# AutoPad-R2-RevA-Pads.net
KiCad netlist of a schematic drawn in EAGLE
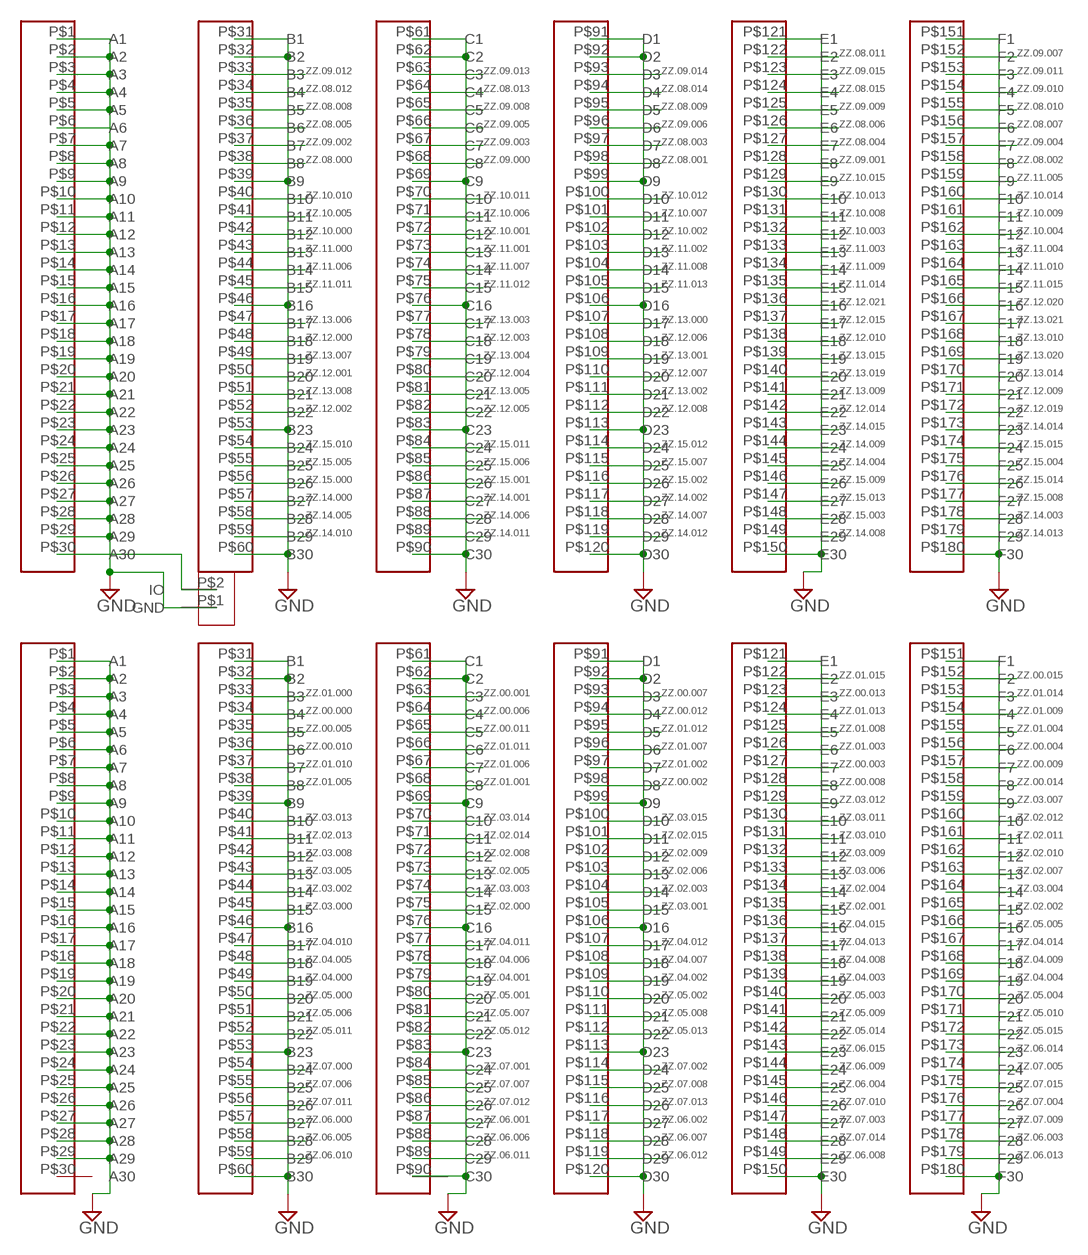
[diagram p0: schematic, sheet 1]
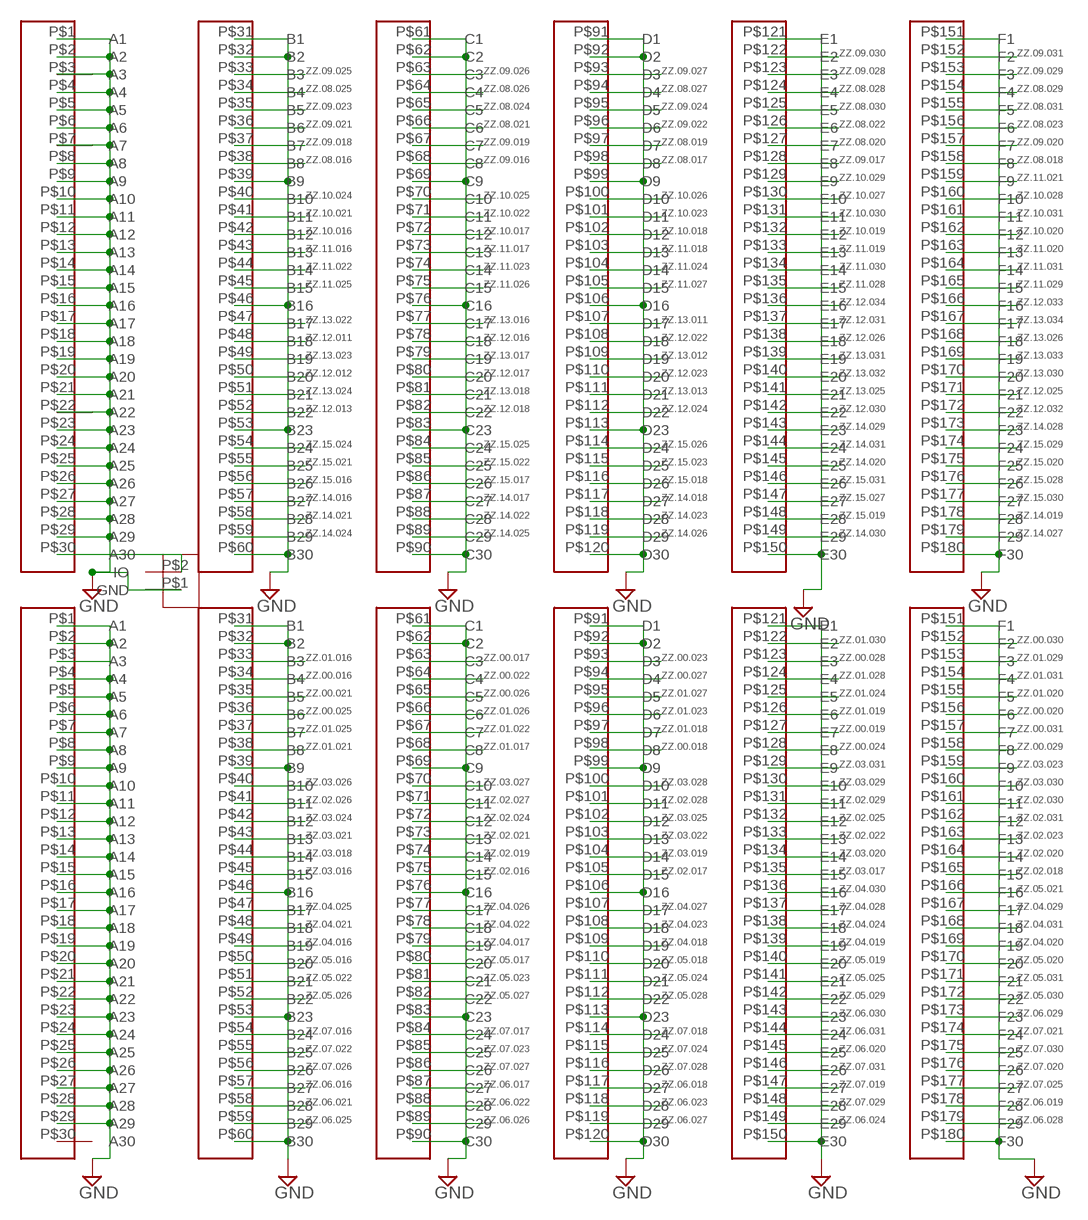
[diagram p1: schematic, sheet 2]
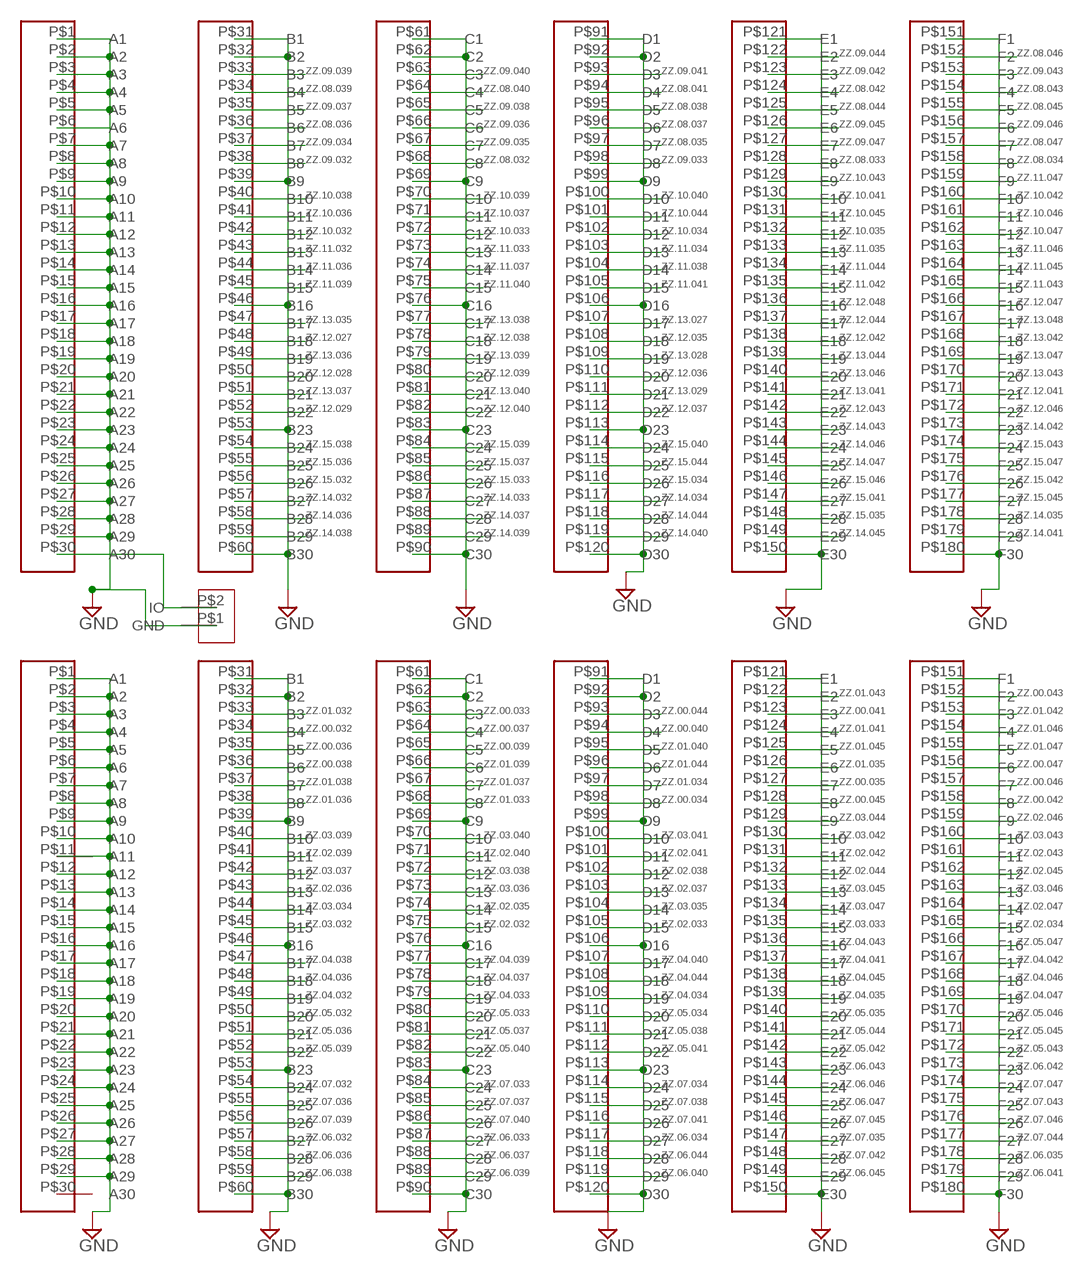
[diagram p2: schematic, sheet 3]
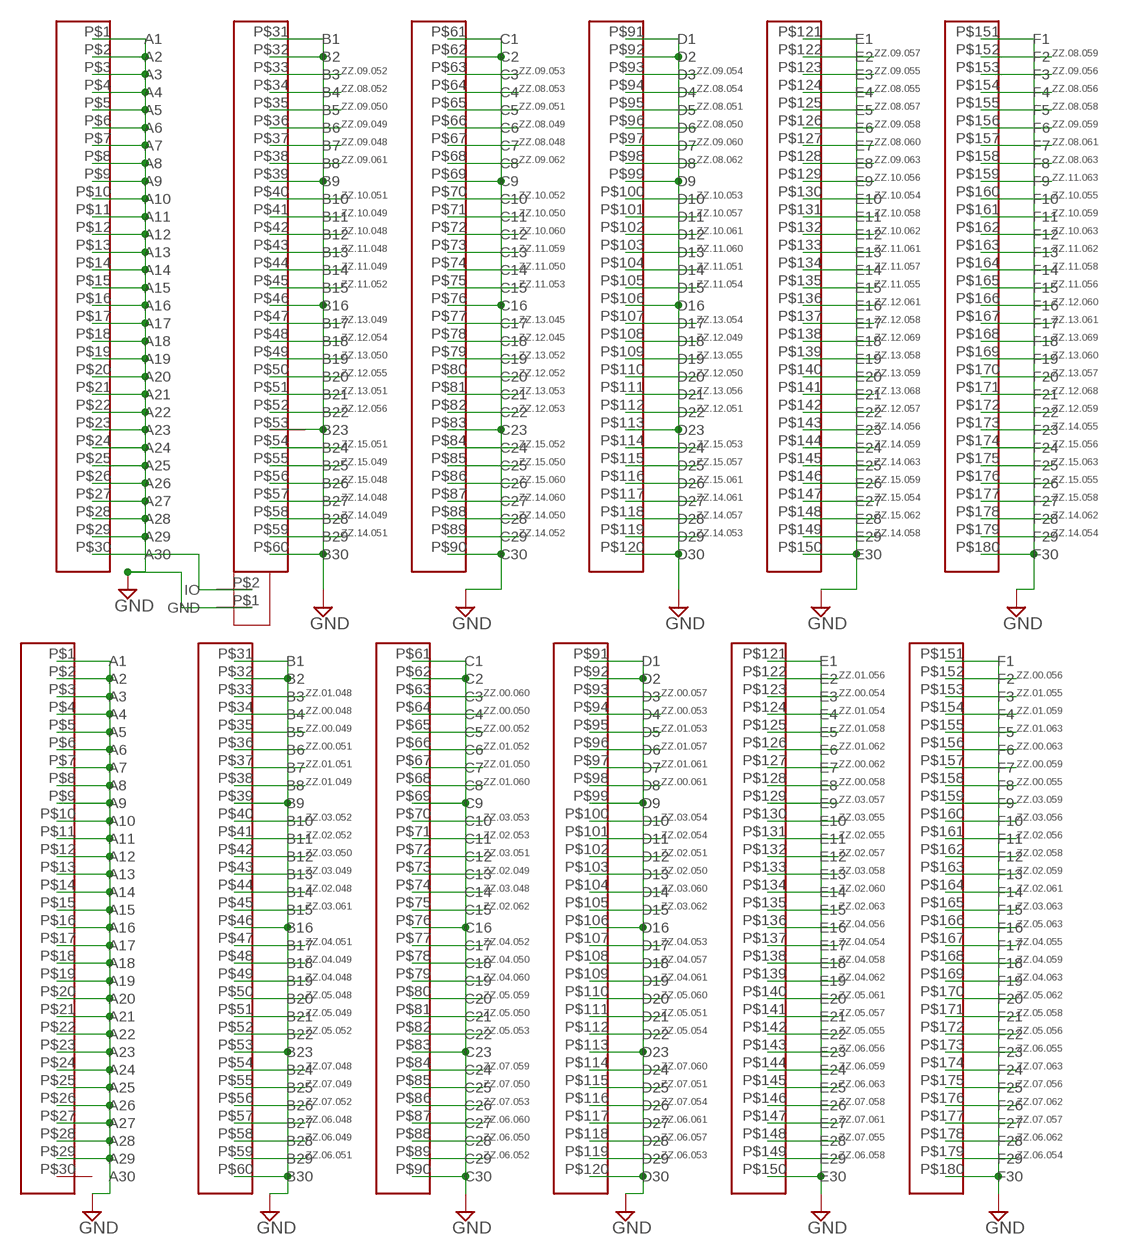
[diagram p3: schematic, sheet 4]
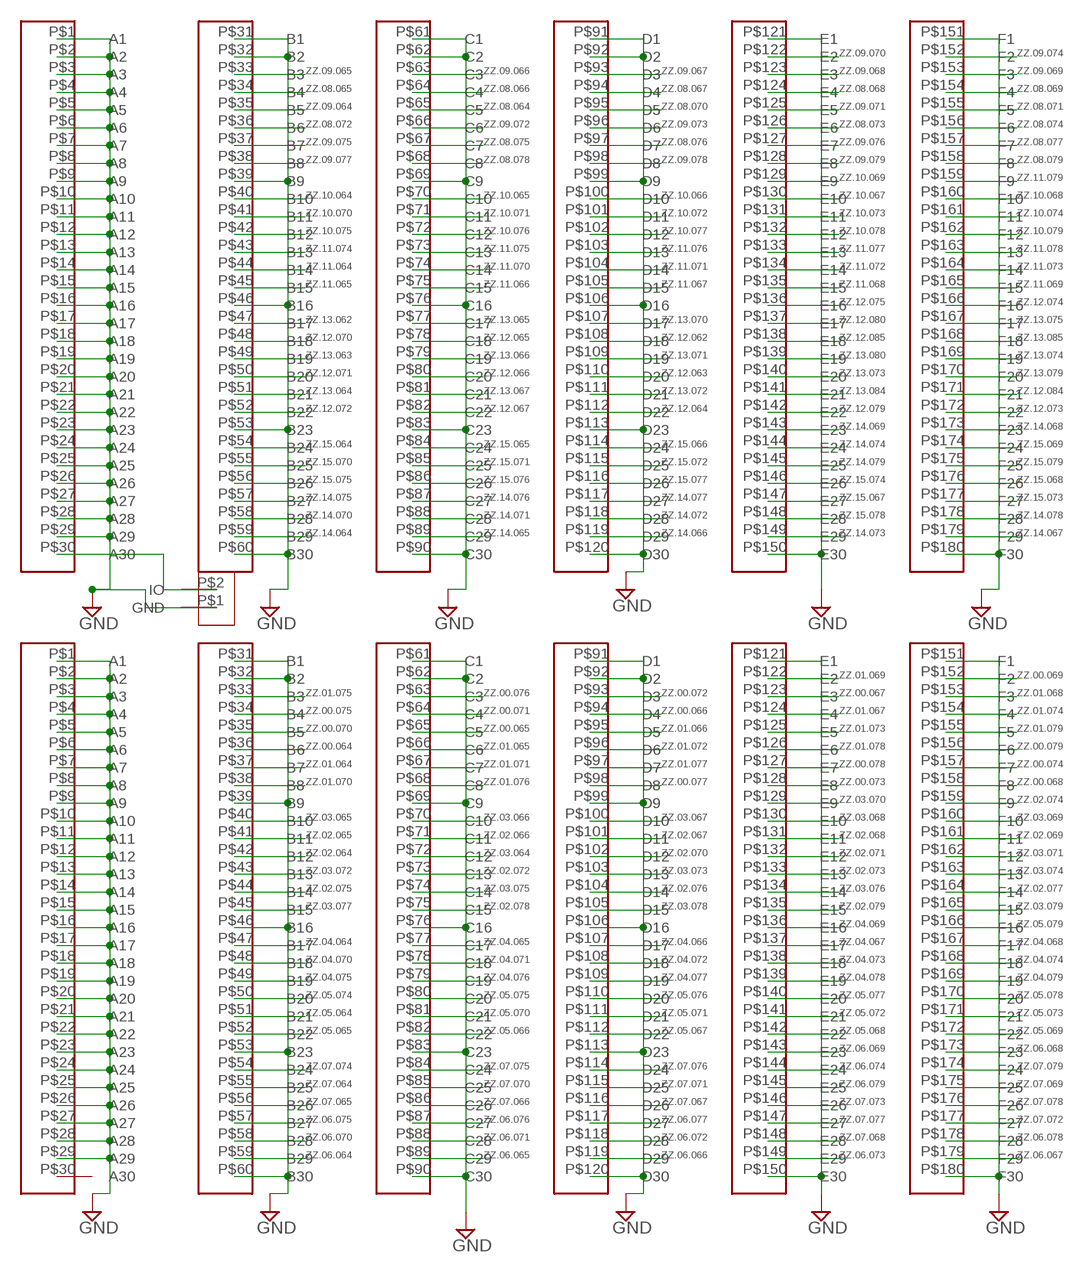
[diagram p4: schematic, sheet 5]
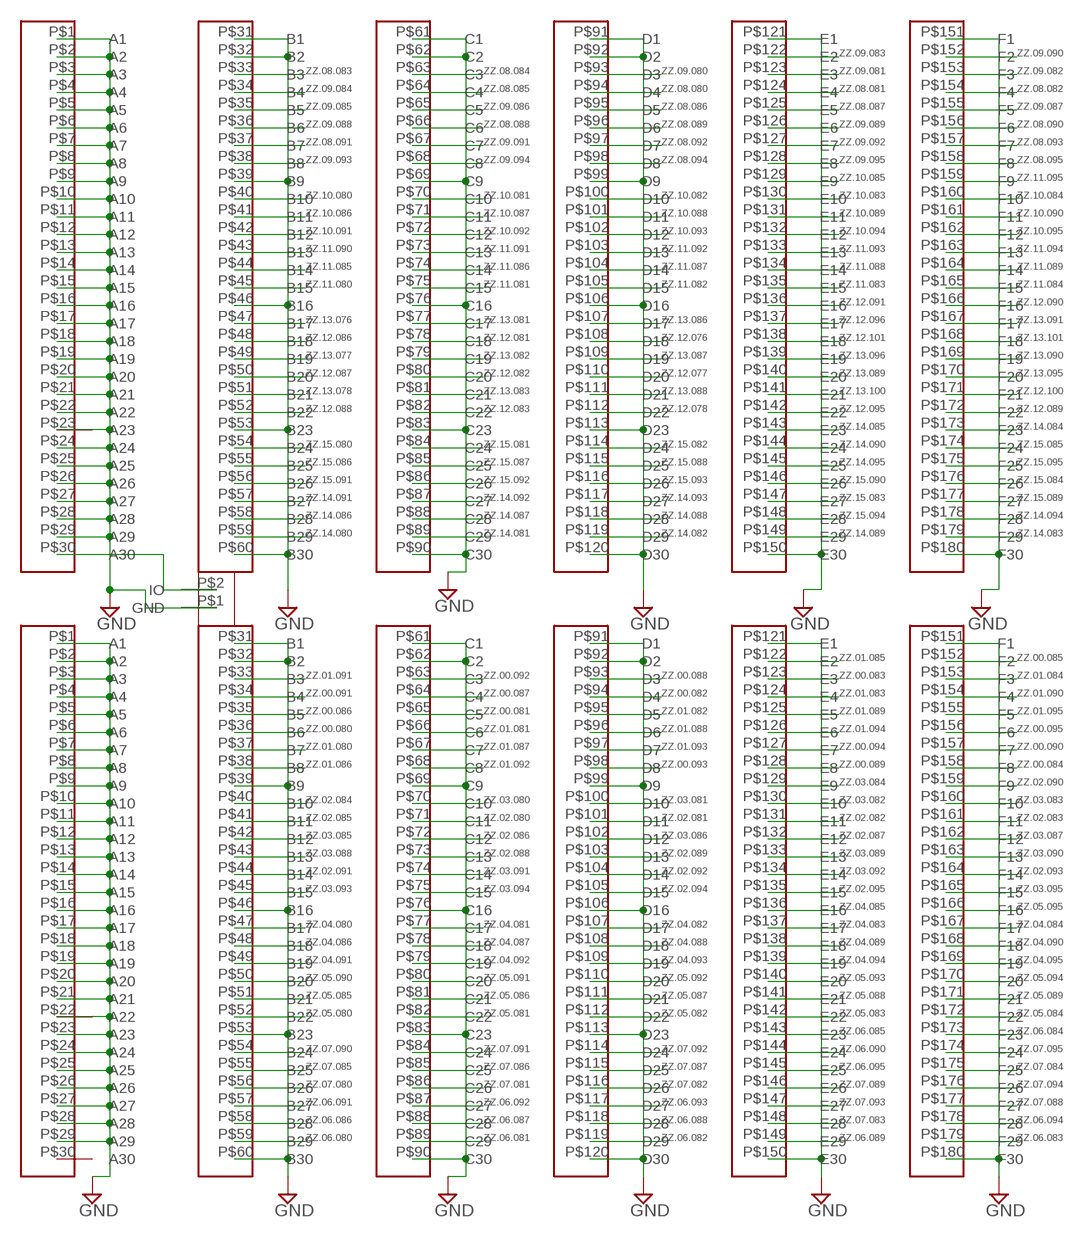
[diagram p5: schematic, sheet 6]
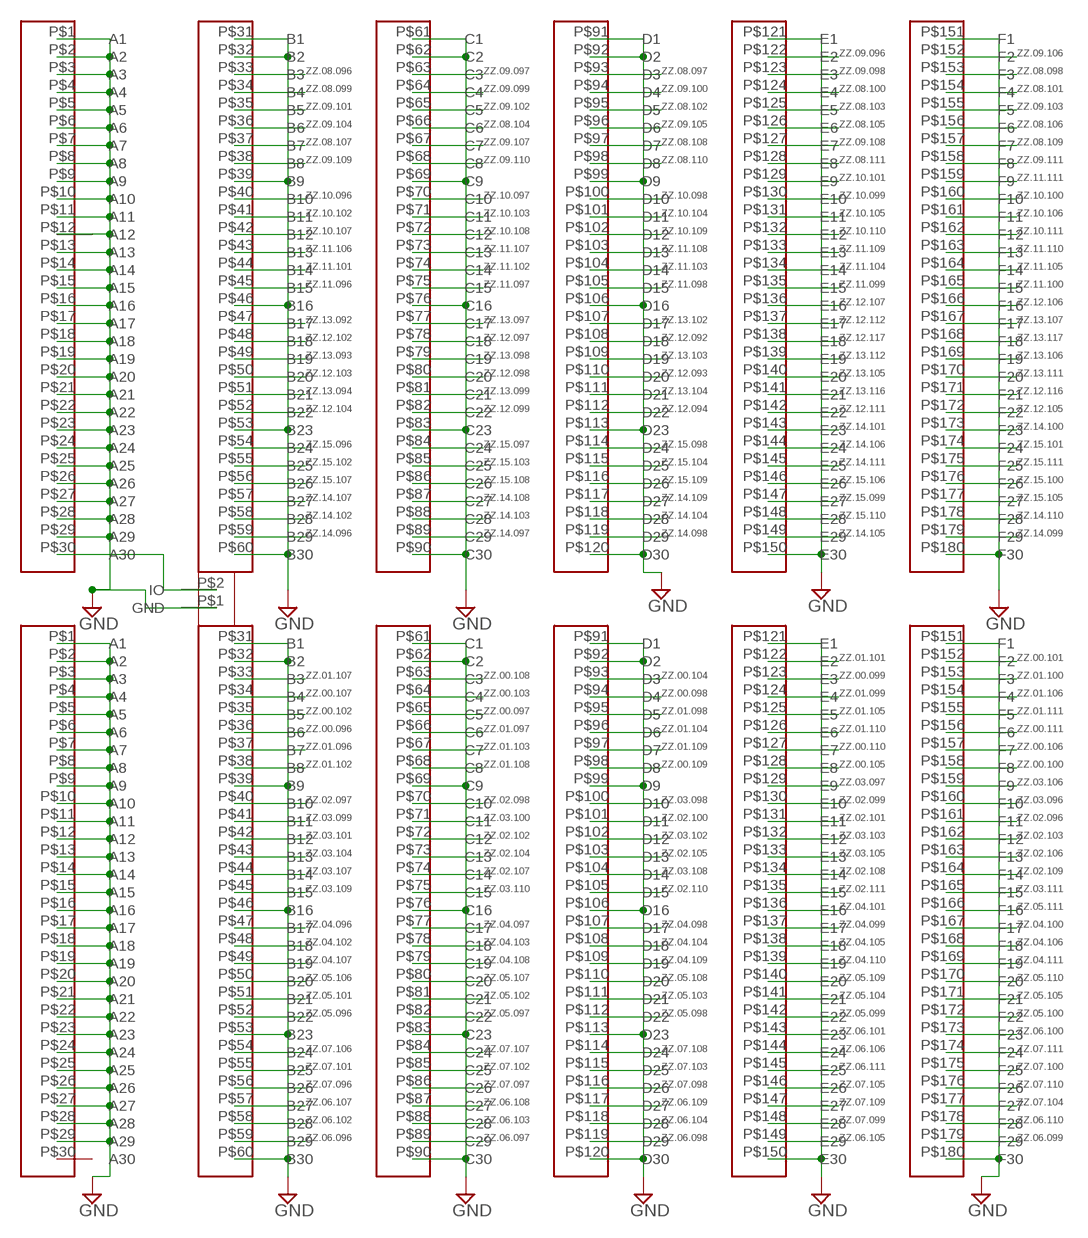
[diagram p6: schematic, sheet 7]
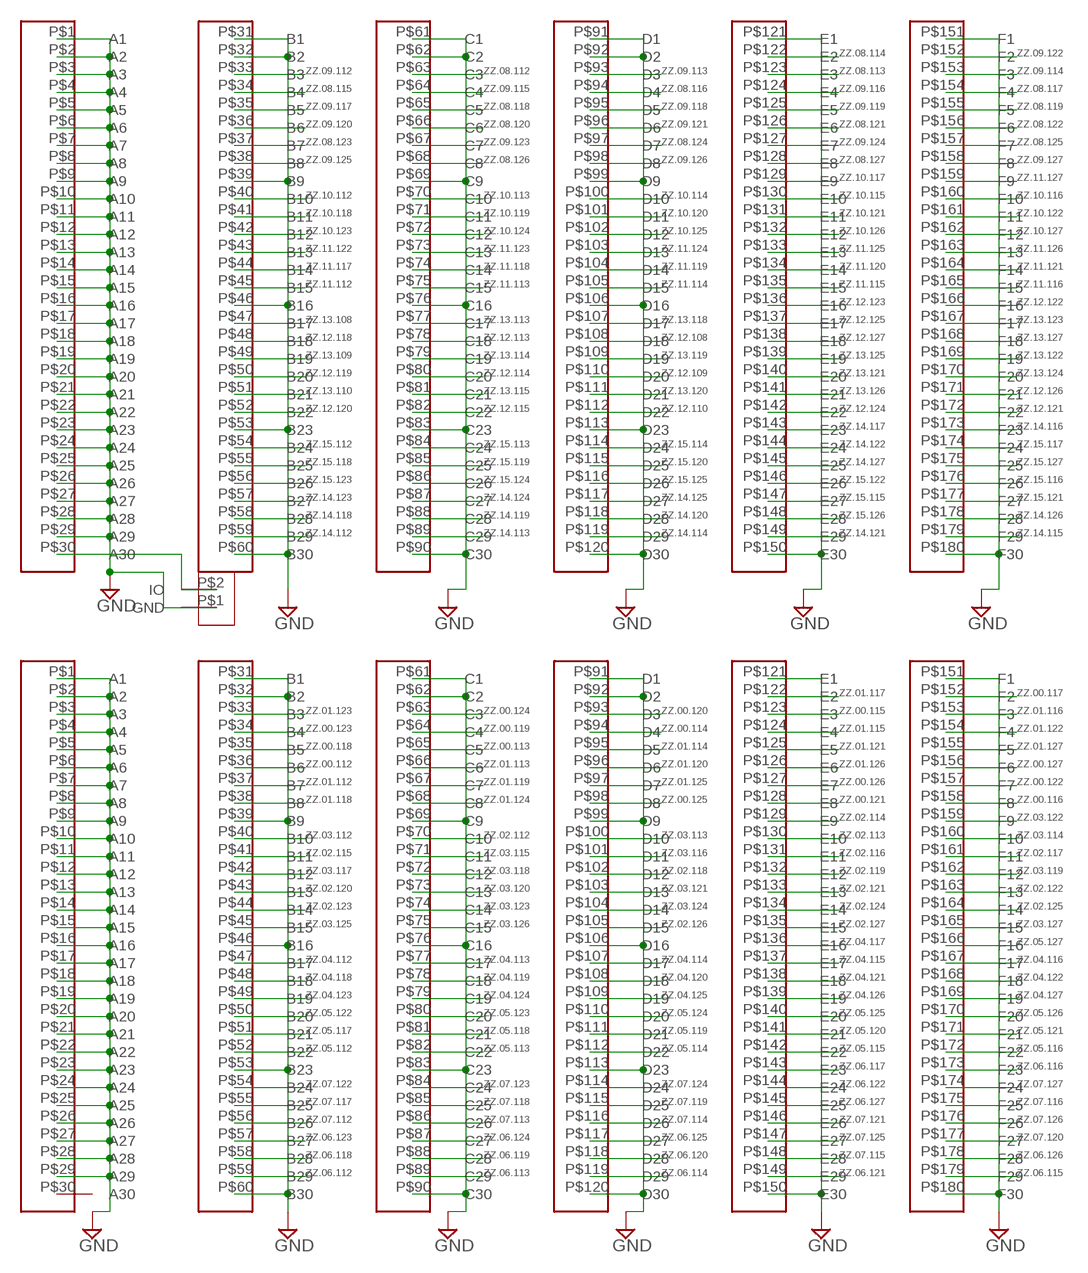
[diagram p7: schematic, sheet 8]

(export (version "E")
  (design (tool "Eeschema 10.0.6"))
  (components
    (comp (ref "U$9")
      (value "SEAM-30-02.0-L-06-1-A-K-TR")
      (footprint "eagle-import:SEAM-30-02.0-L-06-1-A-K-TR")
      (libsource (lib "eagle-import") (part "SEAM-30-02.0-L-06-1-A-K-TR"))
    )
    (comp (ref "U$10")
      (value "SEAM-30-02.0-L-06-1-A-K-TR")
      (footprint "eagle-import:SEAM-30-02.0-L-06-1-A-K-TR")
      (libsource (lib "eagle-import") (part "SEAM-30-02.0-L-06-1-A-K-TR"))
    )
    (comp (ref "U$21")
      (value "DS2431")
      (footprint "eagle-import:SD2431")
      (libsource (lib "eagle-import") (part "DS2431"))
    )
    (comp (ref "U$3")
      (value "SEAM-30-02.0-L-06-1-A-K-TR")
      (footprint "eagle-import:SEAM-30-02.0-L-06-1-A-K-TR")
      (libsource (lib "eagle-import") (part "SEAM-30-02.0-L-06-1-A-K-TR"))
    )
    (comp (ref "U$4")
      (value "SEAM-30-02.0-L-06-1-A-K-TR")
      (footprint "eagle-import:SEAM-30-02.0-L-06-1-A-K-TR")
      (libsource (lib "eagle-import") (part "SEAM-30-02.0-L-06-1-A-K-TR"))
    )
    (comp (ref "U$18")
      (value "DS2431")
      (footprint "eagle-import:SD2431")
      (libsource (lib "eagle-import") (part "DS2431"))
    )
    (comp (ref "U$15")
      (value "SEAM-30-02.0-L-06-1-A-K-TR")
      (footprint "eagle-import:SEAM-30-02.0-L-06-1-A-K-TR")
      (libsource (lib "eagle-import") (part "SEAM-30-02.0-L-06-1-A-K-TR"))
    )
    (comp (ref "U$16")
      (value "SEAM-30-02.0-L-06-1-A-K-TR")
      (footprint "eagle-import:SEAM-30-02.0-L-06-1-A-K-TR")
      (libsource (lib "eagle-import") (part "SEAM-30-02.0-L-06-1-A-K-TR"))
    )
    (comp (ref "U$24")
      (value "DS2431")
      (footprint "eagle-import:SD2431")
      (libsource (lib "eagle-import") (part "DS2431"))
    )
    (comp (ref "U$13")
      (value "SEAM-30-02.0-L-06-1-A-K-TR")
      (footprint "eagle-import:SEAM-30-02.0-L-06-1-A-K-TR")
      (libsource (lib "eagle-import") (part "SEAM-30-02.0-L-06-1-A-K-TR"))
    )
    (comp (ref "U$14")
      (value "SEAM-30-02.0-L-06-1-A-K-TR")
      (footprint "eagle-import:SEAM-30-02.0-L-06-1-A-K-TR")
      (libsource (lib "eagle-import") (part "SEAM-30-02.0-L-06-1-A-K-TR"))
    )
    (comp (ref "U$23")
      (value "DS2431")
      (footprint "eagle-import:SD2431")
      (libsource (lib "eagle-import") (part "DS2431"))
    )
    (comp (ref "U$1")
      (value "SEAM-30-02.0-L-06-1-A-K-TR")
      (footprint "eagle-import:SEAM-30-02.0-L-06-1-A-K-TR")
      (libsource (lib "eagle-import") (part "SEAM-30-02.0-L-06-1-A-K-TR"))
    )
    (comp (ref "U$2")
      (value "SEAM-30-02.0-L-06-1-A-K-TR")
      (footprint "eagle-import:SEAM-30-02.0-L-06-1-A-K-TR")
      (libsource (lib "eagle-import") (part "SEAM-30-02.0-L-06-1-A-K-TR"))
    )
    (comp (ref "U$17")
      (value "DS2431")
      (footprint "eagle-import:SD2431")
      (libsource (lib "eagle-import") (part "DS2431"))
    )
    (comp (ref "U$5")
      (value "SEAM-30-02.0-L-06-1-A-K-TR")
      (footprint "eagle-import:SEAM-30-02.0-L-06-1-A-K-TR")
      (libsource (lib "eagle-import") (part "SEAM-30-02.0-L-06-1-A-K-TR"))
    )
    (comp (ref "U$6")
      (value "SEAM-30-02.0-L-06-1-A-K-TR")
      (footprint "eagle-import:SEAM-30-02.0-L-06-1-A-K-TR")
      (libsource (lib "eagle-import") (part "SEAM-30-02.0-L-06-1-A-K-TR"))
    )
    (comp (ref "U$19")
      (value "DS2431")
      (footprint "eagle-import:SD2431")
      (libsource (lib "eagle-import") (part "DS2431"))
    )
    (comp (ref "U$11")
      (value "SEAM-30-02.0-L-06-1-A-K-TR")
      (footprint "eagle-import:SEAM-30-02.0-L-06-1-A-K-TR")
      (libsource (lib "eagle-import") (part "SEAM-30-02.0-L-06-1-A-K-TR"))
    )
    (comp (ref "U$12")
      (value "SEAM-30-02.0-L-06-1-A-K-TR")
      (footprint "eagle-import:SEAM-30-02.0-L-06-1-A-K-TR")
      (libsource (lib "eagle-import") (part "SEAM-30-02.0-L-06-1-A-K-TR"))
    )
    (comp (ref "U$22")
      (value "DS2431")
      (footprint "eagle-import:SD2431")
      (libsource (lib "eagle-import") (part "DS2431"))
    )
    (comp (ref "U$7")
      (value "SEAM-30-02.0-L-06-1-A-K-TR")
      (footprint "eagle-import:SEAM-30-02.0-L-06-1-A-K-TR")
      (libsource (lib "eagle-import") (part "SEAM-30-02.0-L-06-1-A-K-TR"))
    )
    (comp (ref "U$8")
      (value "SEAM-30-02.0-L-06-1-A-K-TR")
      (footprint "eagle-import:SEAM-30-02.0-L-06-1-A-K-TR")
      (libsource (lib "eagle-import") (part "SEAM-30-02.0-L-06-1-A-K-TR"))
    )
    (comp (ref "U$20")
      (value "DS2431")
      (footprint "eagle-import:SD2431")
      (libsource (lib "eagle-import") (part "DS2431"))
    )
  )
  (nets
    (net (code "1") (name "GND") (class "Default")
      (node (ref "U$1") (pin "P$1") (pinfunction "A1_P$1") (pintype "bidirectional"))
      (node (ref "U$1") (pin "P$10") (pinfunction "A10_P$10") (pintype "bidirectional"))
      (node (ref "U$1") (pin "P$106") (pinfunction "D16_P$106") (pintype "bidirectional"))
      (node (ref "U$1") (pin "P$11") (pinfunction "A11_P$11") (pintype "bidirectional"))
      (node (ref "U$1") (pin "P$113") (pinfunction "D23_P$113") (pintype "bidirectional"))
      (node (ref "U$1") (pin "P$12") (pinfunction "A12_P$12") (pintype "bidirectional"))
      (node (ref "U$1") (pin "P$120") (pinfunction "D30_P$120") (pintype "bidirectional"))
      (node (ref "U$1") (pin "P$121") (pinfunction "E1_P$121") (pintype "bidirectional"))
      (node (ref "U$1") (pin "P$13") (pinfunction "A13_P$13") (pintype "bidirectional"))
      (node (ref "U$1") (pin "P$14") (pinfunction "A14_P$14") (pintype "bidirectional"))
      (node (ref "U$1") (pin "P$15") (pinfunction "A15_P$15") (pintype "bidirectional"))
      (node (ref "U$1") (pin "P$150") (pinfunction "E30_P$150") (pintype "bidirectional"))
      (node (ref "U$1") (pin "P$151") (pinfunction "F1_P$151") (pintype "bidirectional"))
      (node (ref "U$1") (pin "P$16") (pinfunction "A16_P$16") (pintype "bidirectional"))
      (node (ref "U$1") (pin "P$17") (pinfunction "A17_P$17") (pintype "bidirectional"))
      (node (ref "U$1") (pin "P$18") (pinfunction "A18_P$18") (pintype "bidirectional"))
      (node (ref "U$1") (pin "P$180") (pinfunction "F30_P$180") (pintype "bidirectional"))
      (node (ref "U$1") (pin "P$19") (pinfunction "A19_P$19") (pintype "bidirectional"))
      (node (ref "U$1") (pin "P$2") (pinfunction "A2_P$2") (pintype "bidirectional"))
      (node (ref "U$1") (pin "P$20") (pinfunction "A20_P$20") (pintype "bidirectional"))
      (node (ref "U$1") (pin "P$21") (pinfunction "A21_P$21") (pintype "bidirectional"))
      (node (ref "U$1") (pin "P$22") (pinfunction "A22_P$22") (pintype "bidirectional"))
      (node (ref "U$1") (pin "P$23") (pinfunction "A23_P$23") (pintype "bidirectional"))
      (node (ref "U$1") (pin "P$24") (pinfunction "A24_P$24") (pintype "bidirectional"))
      (node (ref "U$1") (pin "P$25") (pinfunction "A25_P$25") (pintype "bidirectional"))
      (node (ref "U$1") (pin "P$26") (pinfunction "A26_P$26") (pintype "bidirectional"))
      (node (ref "U$1") (pin "P$27") (pinfunction "A27_P$27") (pintype "bidirectional"))
      (node (ref "U$1") (pin "P$28") (pinfunction "A28_P$28") (pintype "bidirectional"))
      (node (ref "U$1") (pin "P$29") (pinfunction "A29_P$29") (pintype "bidirectional"))
      (node (ref "U$1") (pin "P$3") (pinfunction "A3_P$3") (pintype "bidirectional"))
      (node (ref "U$1") (pin "P$31") (pinfunction "B1_P$31") (pintype "bidirectional"))
      (node (ref "U$1") (pin "P$32") (pinfunction "B2_P$32") (pintype "bidirectional"))
      (node (ref "U$1") (pin "P$39") (pinfunction "B9_P$39") (pintype "bidirectional"))
      (node (ref "U$1") (pin "P$4") (pinfunction "A4_P$4") (pintype "bidirectional"))
      (node (ref "U$1") (pin "P$46") (pinfunction "B16_P$46") (pintype "bidirectional"))
      (node (ref "U$1") (pin "P$5") (pinfunction "A5_P$5") (pintype "bidirectional"))
      (node (ref "U$1") (pin "P$53") (pinfunction "B23_P$53") (pintype "bidirectional"))
      (node (ref "U$1") (pin "P$6") (pinfunction "A6_P$6") (pintype "bidirectional"))
      (node (ref "U$1") (pin "P$60") (pinfunction "B30_P$60") (pintype "bidirectional"))
      (node (ref "U$1") (pin "P$61") (pinfunction "C1_P$61") (pintype "bidirectional"))
      (node (ref "U$1") (pin "P$62") (pinfunction "C2_P$62") (pintype "bidirectional"))
      (node (ref "U$1") (pin "P$69") (pinfunction "C9_P$69") (pintype "bidirectional"))
      (node (ref "U$1") (pin "P$7") (pinfunction "A7_P$7") (pintype "bidirectional"))
      (node (ref "U$1") (pin "P$76") (pinfunction "C16_P$76") (pintype "bidirectional"))
      (node (ref "U$1") (pin "P$8") (pinfunction "A8_P$8") (pintype "bidirectional"))
      (node (ref "U$1") (pin "P$83") (pinfunction "C23_P$83") (pintype "bidirectional"))
      (node (ref "U$1") (pin "P$9") (pinfunction "A9_P$9") (pintype "bidirectional"))
      (node (ref "U$1") (pin "P$90") (pinfunction "C30_P$90") (pintype "bidirectional"))
      (node (ref "U$1") (pin "P$91") (pinfunction "D1_P$91") (pintype "bidirectional"))
      (node (ref "U$1") (pin "P$92") (pinfunction "D2_P$92") (pintype "bidirectional"))
      (node (ref "U$1") (pin "P$99") (pinfunction "D9_P$99") (pintype "bidirectional"))
      (node (ref "U$10") (pin "P$1") (pinfunction "A1_P$1") (pintype "bidirectional"))
      (node (ref "U$10") (pin "P$10") (pinfunction "A10_P$10") (pintype "bidirectional"))
      (node (ref "U$10") (pin "P$106") (pinfunction "D16_P$106") (pintype "bidirectional"))
      (node (ref "U$10") (pin "P$11") (pinfunction "A11_P$11") (pintype "bidirectional"))
      (node (ref "U$10") (pin "P$113") (pinfunction "D23_P$113") (pintype "bidirectional"))
      (node (ref "U$10") (pin "P$12") (pinfunction "A12_P$12") (pintype "bidirectional"))
      (node (ref "U$10") (pin "P$120") (pinfunction "D30_P$120") (pintype "bidirectional"))
      (node (ref "U$10") (pin "P$121") (pinfunction "E1_P$121") (pintype "bidirectional"))
      (node (ref "U$10") (pin "P$13") (pinfunction "A13_P$13") (pintype "bidirectional"))
      (node (ref "U$10") (pin "P$14") (pinfunction "A14_P$14") (pintype "bidirectional"))
      (node (ref "U$10") (pin "P$15") (pinfunction "A15_P$15") (pintype "bidirectional"))
      (node (ref "U$10") (pin "P$150") (pinfunction "E30_P$150") (pintype "bidirectional"))
      (node (ref "U$10") (pin "P$151") (pinfunction "F1_P$151") (pintype "bidirectional"))
      (node (ref "U$10") (pin "P$16") (pinfunction "A16_P$16") (pintype "bidirectional"))
      (node (ref "U$10") (pin "P$17") (pinfunction "A17_P$17") (pintype "bidirectional"))
      (node (ref "U$10") (pin "P$18") (pinfunction "A18_P$18") (pintype "bidirectional"))
      (node (ref "U$10") (pin "P$180") (pinfunction "F30_P$180") (pintype "bidirectional"))
      (node (ref "U$10") (pin "P$19") (pinfunction "A19_P$19") (pintype "bidirectional"))
      (node (ref "U$10") (pin "P$2") (pinfunction "A2_P$2") (pintype "bidirectional"))
      (node (ref "U$10") (pin "P$20") (pinfunction "A20_P$20") (pintype "bidirectional"))
      (node (ref "U$10") (pin "P$21") (pinfunction "A21_P$21") (pintype "bidirectional"))
      (node (ref "U$10") (pin "P$22") (pinfunction "A22_P$22") (pintype "bidirectional"))
      (node (ref "U$10") (pin "P$23") (pinfunction "A23_P$23") (pintype "bidirectional"))
      (node (ref "U$10") (pin "P$24") (pinfunction "A24_P$24") (pintype "bidirectional"))
      (node (ref "U$10") (pin "P$25") (pinfunction "A25_P$25") (pintype "bidirectional"))
      (node (ref "U$10") (pin "P$26") (pinfunction "A26_P$26") (pintype "bidirectional"))
      (node (ref "U$10") (pin "P$27") (pinfunction "A27_P$27") (pintype "bidirectional"))
      (node (ref "U$10") (pin "P$28") (pinfunction "A28_P$28") (pintype "bidirectional"))
      (node (ref "U$10") (pin "P$29") (pinfunction "A29_P$29") (pintype "bidirectional"))
      (node (ref "U$10") (pin "P$3") (pinfunction "A3_P$3") (pintype "bidirectional"))
      (node (ref "U$10") (pin "P$31") (pinfunction "B1_P$31") (pintype "bidirectional"))
      (node (ref "U$10") (pin "P$32") (pinfunction "B2_P$32") (pintype "bidirectional"))
      (node (ref "U$10") (pin "P$39") (pinfunction "B9_P$39") (pintype "bidirectional"))
      (node (ref "U$10") (pin "P$4") (pinfunction "A4_P$4") (pintype "bidirectional"))
      (node (ref "U$10") (pin "P$46") (pinfunction "B16_P$46") (pintype "bidirectional"))
      (node (ref "U$10") (pin "P$5") (pinfunction "A5_P$5") (pintype "bidirectional"))
      (node (ref "U$10") (pin "P$53") (pinfunction "B23_P$53") (pintype "bidirectional"))
      (node (ref "U$10") (pin "P$6") (pinfunction "A6_P$6") (pintype "bidirectional"))
      (node (ref "U$10") (pin "P$60") (pinfunction "B30_P$60") (pintype "bidirectional"))
      (node (ref "U$10") (pin "P$61") (pinfunction "C1_P$61") (pintype "bidirectional"))
      (node (ref "U$10") (pin "P$62") (pinfunction "C2_P$62") (pintype "bidirectional"))
      (node (ref "U$10") (pin "P$69") (pinfunction "C9_P$69") (pintype "bidirectional"))
      (node (ref "U$10") (pin "P$7") (pinfunction "A7_P$7") (pintype "bidirectional"))
      (node (ref "U$10") (pin "P$76") (pinfunction "C16_P$76") (pintype "bidirectional"))
      (node (ref "U$10") (pin "P$8") (pinfunction "A8_P$8") (pintype "bidirectional"))
      (node (ref "U$10") (pin "P$83") (pinfunction "C23_P$83") (pintype "bidirectional"))
      (node (ref "U$10") (pin "P$9") (pinfunction "A9_P$9") (pintype "bidirectional"))
      (node (ref "U$10") (pin "P$90") (pinfunction "C30_P$90") (pintype "bidirectional"))
      (node (ref "U$10") (pin "P$91") (pinfunction "D1_P$91") (pintype "bidirectional"))
      (node (ref "U$10") (pin "P$92") (pinfunction "D2_P$92") (pintype "bidirectional"))
      (node (ref "U$10") (pin "P$99") (pinfunction "D9_P$99") (pintype "bidirectional"))
      (node (ref "U$11") (pin "P$1") (pinfunction "A1_P$1") (pintype "bidirectional"))
      (node (ref "U$11") (pin "P$10") (pinfunction "A10_P$10") (pintype "bidirectional"))
      (node (ref "U$11") (pin "P$106") (pinfunction "D16_P$106") (pintype "bidirectional"))
      (node (ref "U$11") (pin "P$11") (pinfunction "A11_P$11") (pintype "bidirectional"))
      (node (ref "U$11") (pin "P$113") (pinfunction "D23_P$113") (pintype "bidirectional"))
      (node (ref "U$11") (pin "P$12") (pinfunction "A12_P$12") (pintype "bidirectional"))
      (node (ref "U$11") (pin "P$120") (pinfunction "D30_P$120") (pintype "bidirectional"))
      (node (ref "U$11") (pin "P$121") (pinfunction "E1_P$121") (pintype "bidirectional"))
      (node (ref "U$11") (pin "P$13") (pinfunction "A13_P$13") (pintype "bidirectional"))
      (node (ref "U$11") (pin "P$14") (pinfunction "A14_P$14") (pintype "bidirectional"))
      (node (ref "U$11") (pin "P$15") (pinfunction "A15_P$15") (pintype "bidirectional"))
      (node (ref "U$11") (pin "P$150") (pinfunction "E30_P$150") (pintype "bidirectional"))
      (node (ref "U$11") (pin "P$151") (pinfunction "F1_P$151") (pintype "bidirectional"))
      (node (ref "U$11") (pin "P$16") (pinfunction "A16_P$16") (pintype "bidirectional"))
      (node (ref "U$11") (pin "P$17") (pinfunction "A17_P$17") (pintype "bidirectional"))
      (node (ref "U$11") (pin "P$18") (pinfunction "A18_P$18") (pintype "bidirectional"))
      (node (ref "U$11") (pin "P$180") (pinfunction "F30_P$180") (pintype "bidirectional"))
      (node (ref "U$11") (pin "P$19") (pinfunction "A19_P$19") (pintype "bidirectional"))
      (node (ref "U$11") (pin "P$2") (pinfunction "A2_P$2") (pintype "bidirectional"))
      (node (ref "U$11") (pin "P$20") (pinfunction "A20_P$20") (pintype "bidirectional"))
      (node (ref "U$11") (pin "P$21") (pinfunction "A21_P$21") (pintype "bidirectional"))
      (node (ref "U$11") (pin "P$22") (pinfunction "A22_P$22") (pintype "bidirectional"))
      (node (ref "U$11") (pin "P$23") (pinfunction "A23_P$23") (pintype "bidirectional"))
      (node (ref "U$11") (pin "P$24") (pinfunction "A24_P$24") (pintype "bidirectional"))
      (node (ref "U$11") (pin "P$25") (pinfunction "A25_P$25") (pintype "bidirectional"))
      (node (ref "U$11") (pin "P$26") (pinfunction "A26_P$26") (pintype "bidirectional"))
      (node (ref "U$11") (pin "P$27") (pinfunction "A27_P$27") (pintype "bidirectional"))
      (node (ref "U$11") (pin "P$28") (pinfunction "A28_P$28") (pintype "bidirectional"))
      (node (ref "U$11") (pin "P$29") (pinfunction "A29_P$29") (pintype "bidirectional"))
      (node (ref "U$11") (pin "P$3") (pinfunction "A3_P$3") (pintype "bidirectional"))
      (node (ref "U$11") (pin "P$31") (pinfunction "B1_P$31") (pintype "bidirectional"))
      (node (ref "U$11") (pin "P$32") (pinfunction "B2_P$32") (pintype "bidirectional"))
      (node (ref "U$11") (pin "P$39") (pinfunction "B9_P$39") (pintype "bidirectional"))
      (node (ref "U$11") (pin "P$4") (pinfunction "A4_P$4") (pintype "bidirectional"))
      (node (ref "U$11") (pin "P$46") (pinfunction "B16_P$46") (pintype "bidirectional"))
      (node (ref "U$11") (pin "P$5") (pinfunction "A5_P$5") (pintype "bidirectional"))
      (node (ref "U$11") (pin "P$53") (pinfunction "B23_P$53") (pintype "bidirectional"))
      (node (ref "U$11") (pin "P$6") (pinfunction "A6_P$6") (pintype "bidirectional"))
      (node (ref "U$11") (pin "P$60") (pinfunction "B30_P$60") (pintype "bidirectional"))
      (node (ref "U$11") (pin "P$61") (pinfunction "C1_P$61") (pintype "bidirectional"))
      (node (ref "U$11") (pin "P$62") (pinfunction "C2_P$62") (pintype "bidirectional"))
      (node (ref "U$11") (pin "P$69") (pinfunction "C9_P$69") (pintype "bidirectional"))
      (node (ref "U$11") (pin "P$7") (pinfunction "A7_P$7") (pintype "bidirectional"))
      (node (ref "U$11") (pin "P$76") (pinfunction "C16_P$76") (pintype "bidirectional"))
      (node (ref "U$11") (pin "P$8") (pinfunction "A8_P$8") (pintype "bidirectional"))
      (node (ref "U$11") (pin "P$83") (pinfunction "C23_P$83") (pintype "bidirectional"))
      (node (ref "U$11") (pin "P$9") (pinfunction "A9_P$9") (pintype "bidirectional"))
      (node (ref "U$11") (pin "P$90") (pinfunction "C30_P$90") (pintype "bidirectional"))
      (node (ref "U$11") (pin "P$91") (pinfunction "D1_P$91") (pintype "bidirectional"))
      (node (ref "U$11") (pin "P$92") (pinfunction "D2_P$92") (pintype "bidirectional"))
      (node (ref "U$11") (pin "P$99") (pinfunction "D9_P$99") (pintype "bidirectional"))
      (node (ref "U$12") (pin "P$1") (pinfunction "A1_P$1") (pintype "bidirectional"))
      (node (ref "U$12") (pin "P$10") (pinfunction "A10_P$10") (pintype "bidirectional"))
      (node (ref "U$12") (pin "P$106") (pinfunction "D16_P$106") (pintype "bidirectional"))
      (node (ref "U$12") (pin "P$11") (pinfunction "A11_P$11") (pintype "bidirectional"))
      (node (ref "U$12") (pin "P$113") (pinfunction "D23_P$113") (pintype "bidirectional"))
      (node (ref "U$12") (pin "P$12") (pinfunction "A12_P$12") (pintype "bidirectional"))
      (node (ref "U$12") (pin "P$120") (pinfunction "D30_P$120") (pintype "bidirectional"))
      (node (ref "U$12") (pin "P$121") (pinfunction "E1_P$121") (pintype "bidirectional"))
      (node (ref "U$12") (pin "P$13") (pinfunction "A13_P$13") (pintype "bidirectional"))
      (node (ref "U$12") (pin "P$14") (pinfunction "A14_P$14") (pintype "bidirectional"))
      (node (ref "U$12") (pin "P$15") (pinfunction "A15_P$15") (pintype "bidirectional"))
      (node (ref "U$12") (pin "P$150") (pinfunction "E30_P$150") (pintype "bidirectional"))
      (node (ref "U$12") (pin "P$151") (pinfunction "F1_P$151") (pintype "bidirectional"))
      (node (ref "U$12") (pin "P$16") (pinfunction "A16_P$16") (pintype "bidirectional"))
      (node (ref "U$12") (pin "P$17") (pinfunction "A17_P$17") (pintype "bidirectional"))
      (node (ref "U$12") (pin "P$18") (pinfunction "A18_P$18") (pintype "bidirectional"))
      (node (ref "U$12") (pin "P$180") (pinfunction "F30_P$180") (pintype "bidirectional"))
      (node (ref "U$12") (pin "P$19") (pinfunction "A19_P$19") (pintype "bidirectional"))
      (node (ref "U$12") (pin "P$2") (pinfunction "A2_P$2") (pintype "bidirectional"))
      (node (ref "U$12") (pin "P$20") (pinfunction "A20_P$20") (pintype "bidirectional"))
      (node (ref "U$12") (pin "P$21") (pinfunction "A21_P$21") (pintype "bidirectional"))
      (node (ref "U$12") (pin "P$22") (pinfunction "A22_P$22") (pintype "bidirectional"))
      (node (ref "U$12") (pin "P$23") (pinfunction "A23_P$23") (pintype "bidirectional"))
      (node (ref "U$12") (pin "P$24") (pinfunction "A24_P$24") (pintype "bidirectional"))
      (node (ref "U$12") (pin "P$25") (pinfunction "A25_P$25") (pintype "bidirectional"))
      (node (ref "U$12") (pin "P$26") (pinfunction "A26_P$26") (pintype "bidirectional"))
      (node (ref "U$12") (pin "P$27") (pinfunction "A27_P$27") (pintype "bidirectional"))
      (node (ref "U$12") (pin "P$28") (pinfunction "A28_P$28") (pintype "bidirectional"))
      (node (ref "U$12") (pin "P$29") (pinfunction "A29_P$29") (pintype "bidirectional"))
      (node (ref "U$12") (pin "P$3") (pinfunction "A3_P$3") (pintype "bidirectional"))
      (node (ref "U$12") (pin "P$31") (pinfunction "B1_P$31") (pintype "bidirectional"))
      (node (ref "U$12") (pin "P$32") (pinfunction "B2_P$32") (pintype "bidirectional"))
      (node (ref "U$12") (pin "P$39") (pinfunction "B9_P$39") (pintype "bidirectional"))
      (node (ref "U$12") (pin "P$4") (pinfunction "A4_P$4") (pintype "bidirectional"))
      (node (ref "U$12") (pin "P$46") (pinfunction "B16_P$46") (pintype "bidirectional"))
      (node (ref "U$12") (pin "P$5") (pinfunction "A5_P$5") (pintype "bidirectional"))
      (node (ref "U$12") (pin "P$53") (pinfunction "B23_P$53") (pintype "bidirectional"))
      (node (ref "U$12") (pin "P$6") (pinfunction "A6_P$6") (pintype "bidirectional"))
      (node (ref "U$12") (pin "P$60") (pinfunction "B30_P$60") (pintype "bidirectional"))
      (node (ref "U$12") (pin "P$61") (pinfunction "C1_P$61") (pintype "bidirectional"))
      (node (ref "U$12") (pin "P$62") (pinfunction "C2_P$62") (pintype "bidirectional"))
      (node (ref "U$12") (pin "P$69") (pinfunction "C9_P$69") (pintype "bidirectional"))
      (node (ref "U$12") (pin "P$7") (pinfunction "A7_P$7") (pintype "bidirectional"))
      (node (ref "U$12") (pin "P$76") (pinfunction "C16_P$76") (pintype "bidirectional"))
      (node (ref "U$12") (pin "P$8") (pinfunction "A8_P$8") (pintype "bidirectional"))
      (node (ref "U$12") (pin "P$83") (pinfunction "C23_P$83") (pintype "bidirectional"))
      (node (ref "U$12") (pin "P$9") (pinfunction "A9_P$9") (pintype "bidirectional"))
      (node (ref "U$12") (pin "P$90") (pinfunction "C30_P$90") (pintype "bidirectional"))
      (node (ref "U$12") (pin "P$91") (pinfunction "D1_P$91") (pintype "bidirectional"))
      (node (ref "U$12") (pin "P$92") (pinfunction "D2_P$92") (pintype "bidirectional"))
      (node (ref "U$12") (pin "P$99") (pinfunction "D9_P$99") (pintype "bidirectional"))
      (node (ref "U$13") (pin "P$1") (pinfunction "A1_P$1") (pintype "bidirectional"))
      (node (ref "U$13") (pin "P$10") (pinfunction "A10_P$10") (pintype "bidirectional"))
      (node (ref "U$13") (pin "P$106") (pinfunction "D16_P$106") (pintype "bidirectional"))
      (node (ref "U$13") (pin "P$11") (pinfunction "A11_P$11") (pintype "bidirectional"))
      (node (ref "U$13") (pin "P$113") (pinfunction "D23_P$113") (pintype "bidirectional"))
      (node (ref "U$13") (pin "P$12") (pinfunction "A12_P$12") (pintype "bidirectional"))
      (node (ref "U$13") (pin "P$120") (pinfunction "D30_P$120") (pintype "bidirectional"))
      (node (ref "U$13") (pin "P$121") (pinfunction "E1_P$121") (pintype "bidirectional"))
      (node (ref "U$13") (pin "P$13") (pinfunction "A13_P$13") (pintype "bidirectional"))
      (node (ref "U$13") (pin "P$14") (pinfunction "A14_P$14") (pintype "bidirectional"))
      (node (ref "U$13") (pin "P$15") (pinfunction "A15_P$15") (pintype "bidirectional"))
      (node (ref "U$13") (pin "P$150") (pinfunction "E30_P$150") (pintype "bidirectional"))
      (node (ref "U$13") (pin "P$151") (pinfunction "F1_P$151") (pintype "bidirectional"))
      (node (ref "U$13") (pin "P$16") (pinfunction "A16_P$16") (pintype "bidirectional"))
      (node (ref "U$13") (pin "P$17") (pinfunction "A17_P$17") (pintype "bidirectional"))
      (node (ref "U$13") (pin "P$18") (pinfunction "A18_P$18") (pintype "bidirectional"))
      (node (ref "U$13") (pin "P$180") (pinfunction "F30_P$180") (pintype "bidirectional"))
      (node (ref "U$13") (pin "P$19") (pinfunction "A19_P$19") (pintype "bidirectional"))
      (node (ref "U$13") (pin "P$2") (pinfunction "A2_P$2") (pintype "bidirectional"))
      (node (ref "U$13") (pin "P$20") (pinfunction "A20_P$20") (pintype "bidirectional"))
      (node (ref "U$13") (pin "P$21") (pinfunction "A21_P$21") (pintype "bidirectional"))
      (node (ref "U$13") (pin "P$22") (pinfunction "A22_P$22") (pintype "bidirectional"))
      (node (ref "U$13") (pin "P$23") (pinfunction "A23_P$23") (pintype "bidirectional"))
      (node (ref "U$13") (pin "P$24") (pinfunction "A24_P$24") (pintype "bidirectional"))
      (node (ref "U$13") (pin "P$25") (pinfunction "A25_P$25") (pintype "bidirectional"))
      (node (ref "U$13") (pin "P$26") (pinfunction "A26_P$26") (pintype "bidirectional"))
      (node (ref "U$13") (pin "P$27") (pinfunction "A27_P$27") (pintype "bidirectional"))
      (node (ref "U$13") (pin "P$28") (pinfunction "A28_P$28") (pintype "bidirectional"))
      (node (ref "U$13") (pin "P$29") (pinfunction "A29_P$29") (pintype "bidirectional"))
      (node (ref "U$13") (pin "P$3") (pinfunction "A3_P$3") (pintype "bidirectional"))
      (node (ref "U$13") (pin "P$31") (pinfunction "B1_P$31") (pintype "bidirectional"))
      (node (ref "U$13") (pin "P$32") (pinfunction "B2_P$32") (pintype "bidirectional"))
      (node (ref "U$13") (pin "P$39") (pinfunction "B9_P$39") (pintype "bidirectional"))
      (node (ref "U$13") (pin "P$4") (pinfunction "A4_P$4") (pintype "bidirectional"))
      (node (ref "U$13") (pin "P$46") (pinfunction "B16_P$46") (pintype "bidirectional"))
      (node (ref "U$13") (pin "P$5") (pinfunction "A5_P$5") (pintype "bidirectional"))
      (node (ref "U$13") (pin "P$53") (pinfunction "B23_P$53") (pintype "bidirectional"))
      (node (ref "U$13") (pin "P$6") (pinfunction "A6_P$6") (pintype "bidirectional"))
      (node (ref "U$13") (pin "P$60") (pinfunction "B30_P$60") (pintype "bidirectional"))
      (node (ref "U$13") (pin "P$61") (pinfunction "C1_P$61") (pintype "bidirectional"))
      (node (ref "U$13") (pin "P$62") (pinfunction "C2_P$62") (pintype "bidirectional"))
      (node (ref "U$13") (pin "P$69") (pinfunction "C9_P$69") (pintype "bidirectional"))
      (node (ref "U$13") (pin "P$7") (pinfunction "A7_P$7") (pintype "bidirectional"))
      (node (ref "U$13") (pin "P$76") (pinfunction "C16_P$76") (pintype "bidirectional"))
      (node (ref "U$13") (pin "P$8") (pinfunction "A8_P$8") (pintype "bidirectional"))
      (node (ref "U$13") (pin "P$83") (pinfunction "C23_P$83") (pintype "bidirectional"))
      (node (ref "U$13") (pin "P$9") (pinfunction "A9_P$9") (pintype "bidirectional"))
      (node (ref "U$13") (pin "P$90") (pinfunction "C30_P$90") (pintype "bidirectional"))
      (node (ref "U$13") (pin "P$91") (pinfunction "D1_P$91") (pintype "bidirectional"))
      (node (ref "U$13") (pin "P$92") (pinfunction "D2_P$92") (pintype "bidirectional"))
      (node (ref "U$13") (pin "P$99") (pinfunction "D9_P$99") (pintype "bidirectional"))
      (node (ref "U$14") (pin "P$1") (pinfunction "A1_P$1") (pintype "bidirectional"))
      (node (ref "U$14") (pin "P$10") (pinfunction "A10_P$10") (pintype "bidirectional"))
      (node (ref "U$14") (pin "P$106") (pinfunction "D16_P$106") (pintype "bidirectional"))
      (node (ref "U$14") (pin "P$11") (pinfunction "A11_P$11") (pintype "bidirectional"))
      (node (ref "U$14") (pin "P$113") (pinfunction "D23_P$113") (pintype "bidirectional"))
      (node (ref "U$14") (pin "P$12") (pinfunction "A12_P$12") (pintype "bidirectional"))
      (node (ref "U$14") (pin "P$120") (pinfunction "D30_P$120") (pintype "bidirectional"))
      (node (ref "U$14") (pin "P$121") (pinfunction "E1_P$121") (pintype "bidirectional"))
      (node (ref "U$14") (pin "P$13") (pinfunction "A13_P$13") (pintype "bidirectional"))
      (node (ref "U$14") (pin "P$14") (pinfunction "A14_P$14") (pintype "bidirectional"))
      (node (ref "U$14") (pin "P$15") (pinfunction "A15_P$15") (pintype "bidirectional"))
      (node (ref "U$14") (pin "P$150") (pinfunction "E30_P$150") (pintype "bidirectional"))
      (node (ref "U$14") (pin "P$151") (pinfunction "F1_P$151") (pintype "bidirectional"))
      (node (ref "U$14") (pin "P$16") (pinfunction "A16_P$16") (pintype "bidirectional"))
      (node (ref "U$14") (pin "P$17") (pinfunction "A17_P$17") (pintype "bidirectional"))
      (node (ref "U$14") (pin "P$18") (pinfunction "A18_P$18") (pintype "bidirectional"))
      (node (ref "U$14") (pin "P$180") (pinfunction "F30_P$180") (pintype "bidirectional"))
      (node (ref "U$14") (pin "P$19") (pinfunction "A19_P$19") (pintype "bidirectional"))
      (node (ref "U$14") (pin "P$2") (pinfunction "A2_P$2") (pintype "bidirectional"))
      (node (ref "U$14") (pin "P$20") (pinfunction "A20_P$20") (pintype "bidirectional"))
      (node (ref "U$14") (pin "P$21") (pinfunction "A21_P$21") (pintype "bidirectional"))
      (node (ref "U$14") (pin "P$22") (pinfunction "A22_P$22") (pintype "bidirectional"))
      (node (ref "U$14") (pin "P$23") (pinfunction "A23_P$23") (pintype "bidirectional"))
      (node (ref "U$14") (pin "P$24") (pinfunction "A24_P$24") (pintype "bidirectional"))
      (node (ref "U$14") (pin "P$25") (pinfunction "A25_P$25") (pintype "bidirectional"))
      (node (ref "U$14") (pin "P$26") (pinfunction "A26_P$26") (pintype "bidirectional"))
      (node (ref "U$14") (pin "P$27") (pinfunction "A27_P$27") (pintype "bidirectional"))
      (node (ref "U$14") (pin "P$28") (pinfunction "A28_P$28") (pintype "bidirectional"))
      (node (ref "U$14") (pin "P$29") (pinfunction "A29_P$29") (pintype "bidirectional"))
      (node (ref "U$14") (pin "P$3") (pinfunction "A3_P$3") (pintype "bidirectional"))
      (node (ref "U$14") (pin "P$31") (pinfunction "B1_P$31") (pintype "bidirectional"))
      (node (ref "U$14") (pin "P$32") (pinfunction "B2_P$32") (pintype "bidirectional"))
      (node (ref "U$14") (pin "P$39") (pinfunction "B9_P$39") (pintype "bidirectional"))
      (node (ref "U$14") (pin "P$4") (pinfunction "A4_P$4") (pintype "bidirectional"))
      (node (ref "U$14") (pin "P$46") (pinfunction "B16_P$46") (pintype "bidirectional"))
      (node (ref "U$14") (pin "P$5") (pinfunction "A5_P$5") (pintype "bidirectional"))
      (node (ref "U$14") (pin "P$53") (pinfunction "B23_P$53") (pintype "bidirectional"))
      (node (ref "U$14") (pin "P$6") (pinfunction "A6_P$6") (pintype "bidirectional"))
      (node (ref "U$14") (pin "P$60") (pinfunction "B30_P$60") (pintype "bidirectional"))
      (node (ref "U$14") (pin "P$61") (pinfunction "C1_P$61") (pintype "bidirectional"))
      (node (ref "U$14") (pin "P$62") (pinfunction "C2_P$62") (pintype "bidirectional"))
      (node (ref "U$14") (pin "P$69") (pinfunction "C9_P$69") (pintype "bidirectional"))
      (node (ref "U$14") (pin "P$7") (pinfunction "A7_P$7") (pintype "bidirectional"))
      (node (ref "U$14") (pin "P$76") (pinfunction "C16_P$76") (pintype "bidirectional"))
      (node (ref "U$14") (pin "P$8") (pinfunction "A8_P$8") (pintype "bidirectional"))
      (node (ref "U$14") (pin "P$83") (pinfunction "C23_P$83") (pintype "bidirectional"))
      (node (ref "U$14") (pin "P$9") (pinfunction "A9_P$9") (pintype "bidirectional"))
      (node (ref "U$14") (pin "P$90") (pinfunction "C30_P$90") (pintype "bidirectional"))
      (node (ref "U$14") (pin "P$91") (pinfunction "D1_P$91") (pintype "bidirectional"))
      (node (ref "U$14") (pin "P$92") (pinfunction "D2_P$92") (pintype "bidirectional"))
      (node (ref "U$14") (pin "P$99") (pinfunction "D9_P$99") (pintype "bidirectional"))
      (node (ref "U$15") (pin "P$1") (pinfunction "A1_P$1") (pintype "bidirectional"))
      (node (ref "U$15") (pin "P$10") (pinfunction "A10_P$10") (pintype "bidirectional"))
      (node (ref "U$15") (pin "P$106") (pinfunction "D16_P$106") (pintype "bidirectional"))
      (node (ref "U$15") (pin "P$11") (pinfunction "A11_P$11") (pintype "bidirectional"))
      (node (ref "U$15") (pin "P$113") (pinfunction "D23_P$113") (pintype "bidirectional"))
      (node (ref "U$15") (pin "P$12") (pinfunction "A12_P$12") (pintype "bidirectional"))
      (node (ref "U$15") (pin "P$120") (pinfunction "D30_P$120") (pintype "bidirectional"))
      (node (ref "U$15") (pin "P$121") (pinfunction "E1_P$121") (pintype "bidirectional"))
      (node (ref "U$15") (pin "P$13") (pinfunction "A13_P$13") (pintype "bidirectional"))
      (node (ref "U$15") (pin "P$14") (pinfunction "A14_P$14") (pintype "bidirectional"))
      (node (ref "U$15") (pin "P$15") (pinfunction "A15_P$15") (pintype "bidirectional"))
      (node (ref "U$15") (pin "P$150") (pinfunction "E30_P$150") (pintype "bidirectional"))
      (node (ref "U$15") (pin "P$151") (pinfunction "F1_P$151") (pintype "bidirectional"))
      (node (ref "U$15") (pin "P$16") (pinfunction "A16_P$16") (pintype "bidirectional"))
      (node (ref "U$15") (pin "P$17") (pinfunction "A17_P$17") (pintype "bidirectional"))
      (node (ref "U$15") (pin "P$18") (pinfunction "A18_P$18") (pintype "bidirectional"))
      (node (ref "U$15") (pin "P$180") (pinfunction "F30_P$180") (pintype "bidirectional"))
      (node (ref "U$15") (pin "P$19") (pinfunction "A19_P$19") (pintype "bidirectional"))
      (node (ref "U$15") (pin "P$2") (pinfunction "A2_P$2") (pintype "bidirectional"))
      (node (ref "U$15") (pin "P$20") (pinfunction "A20_P$20") (pintype "bidirectional"))
      (node (ref "U$15") (pin "P$21") (pinfunction "A21_P$21") (pintype "bidirectional"))
      (node (ref "U$15") (pin "P$22") (pinfunction "A22_P$22") (pintype "bidirectional"))
      (node (ref "U$15") (pin "P$23") (pinfunction "A23_P$23") (pintype "bidirectional"))
      (node (ref "U$15") (pin "P$24") (pinfunction "A24_P$24") (pintype "bidirectional"))
      (node (ref "U$15") (pin "P$25") (pinfunction "A25_P$25") (pintype "bidirectional"))
      (node (ref "U$15") (pin "P$26") (pinfunction "A26_P$26") (pintype "bidirectional"))
      (node (ref "U$15") (pin "P$27") (pinfunction "A27_P$27") (pintype "bidirectional"))
      (node (ref "U$15") (pin "P$28") (pinfunction "A28_P$28") (pintype "bidirectional"))
      (node (ref "U$15") (pin "P$29") (pinfunction "A29_P$29") (pintype "bidirectional"))
      (node (ref "U$15") (pin "P$3") (pinfunction "A3_P$3") (pintype "bidirectional"))
      (node (ref "U$15") (pin "P$31") (pinfunction "B1_P$31") (pintype "bidirectional"))
      (node (ref "U$15") (pin "P$32") (pinfunction "B2_P$32") (pintype "bidirectional"))
      (node (ref "U$15") (pin "P$39") (pinfunction "B9_P$39") (pintype "bidirectional"))
      (node (ref "U$15") (pin "P$4") (pinfunction "A4_P$4") (pintype "bidirectional"))
      (node (ref "U$15") (pin "P$46") (pinfunction "B16_P$46") (pintype "bidirectional"))
      (node (ref "U$15") (pin "P$5") (pinfunction "A5_P$5") (pintype "bidirectional"))
      (node (ref "U$15") (pin "P$53") (pinfunction "B23_P$53") (pintype "bidirectional"))
      (node (ref "U$15") (pin "P$6") (pinfunction "A6_P$6") (pintype "bidirectional"))
      (node (ref "U$15") (pin "P$60") (pinfunction "B30_P$60") (pintype "bidirectional"))
      (node (ref "U$15") (pin "P$61") (pinfunction "C1_P$61") (pintype "bidirectional"))
      (node (ref "U$15") (pin "P$62") (pinfunction "C2_P$62") (pintype "bidirectional"))
      (node (ref "U$15") (pin "P$69") (pinfunction "C9_P$69") (pintype "bidirectional"))
      (node (ref "U$15") (pin "P$7") (pinfunction "A7_P$7") (pintype "bidirectional"))
      (node (ref "U$15") (pin "P$76") (pinfunction "C16_P$76") (pintype "bidirectional"))
      (node (ref "U$15") (pin "P$8") (pinfunction "A8_P$8") (pintype "bidirectional"))
      (node (ref "U$15") (pin "P$83") (pinfunction "C23_P$83") (pintype "bidirectional"))
      (node (ref "U$15") (pin "P$9") (pinfunction "A9_P$9") (pintype "bidirectional"))
      (node (ref "U$15") (pin "P$90") (pinfunction "C30_P$90") (pintype "bidirectional"))
      (node (ref "U$15") (pin "P$91") (pinfunction "D1_P$91") (pintype "bidirectional"))
      (node (ref "U$15") (pin "P$92") (pinfunction "D2_P$92") (pintype "bidirectional"))
      (node (ref "U$15") (pin "P$99") (pinfunction "D9_P$99") (pintype "bidirectional"))
      (node (ref "U$16") (pin "P$1") (pinfunction "A1_P$1") (pintype "bidirectional"))
      (node (ref "U$16") (pin "P$10") (pinfunction "A10_P$10") (pintype "bidirectional"))
      (node (ref "U$16") (pin "P$106") (pinfunction "D16_P$106") (pintype "bidirectional"))
      (node (ref "U$16") (pin "P$11") (pinfunction "A11_P$11") (pintype "bidirectional"))
      (node (ref "U$16") (pin "P$113") (pinfunction "D23_P$113") (pintype "bidirectional"))
      (node (ref "U$16") (pin "P$12") (pinfunction "A12_P$12") (pintype "bidirectional"))
      (node (ref "U$16") (pin "P$120") (pinfunction "D30_P$120") (pintype "bidirectional"))
      (node (ref "U$16") (pin "P$121") (pinfunction "E1_P$121") (pintype "bidirectional"))
      (node (ref "U$16") (pin "P$13") (pinfunction "A13_P$13") (pintype "bidirectional"))
      (node (ref "U$16") (pin "P$14") (pinfunction "A14_P$14") (pintype "bidirectional"))
      (node (ref "U$16") (pin "P$15") (pinfunction "A15_P$15") (pintype "bidirectional"))
      (node (ref "U$16") (pin "P$150") (pinfunction "E30_P$150") (pintype "bidirectional"))
      (node (ref "U$16") (pin "P$151") (pinfunction "F1_P$151") (pintype "bidirectional"))
      (node (ref "U$16") (pin "P$16") (pinfunction "A16_P$16") (pintype "bidirectional"))
      (node (ref "U$16") (pin "P$17") (pinfunction "A17_P$17") (pintype "bidirectional"))
      (node (ref "U$16") (pin "P$18") (pinfunction "A18_P$18") (pintype "bidirectional"))
      (node (ref "U$16") (pin "P$180") (pinfunction "F30_P$180") (pintype "bidirectional"))
      (node (ref "U$16") (pin "P$19") (pinfunction "A19_P$19") (pintype "bidirectional"))
      (node (ref "U$16") (pin "P$2") (pinfunction "A2_P$2") (pintype "bidirectional"))
      (node (ref "U$16") (pin "P$20") (pinfunction "A20_P$20") (pintype "bidirectional"))
      (node (ref "U$16") (pin "P$21") (pinfunction "A21_P$21") (pintype "bidirectional"))
      (node (ref "U$16") (pin "P$22") (pinfunction "A22_P$22") (pintype "bidirectional"))
      (node (ref "U$16") (pin "P$23") (pinfunction "A23_P$23") (pintype "bidirectional"))
      (node (ref "U$16") (pin "P$24") (pinfunction "A24_P$24") (pintype "bidirectional"))
      (node (ref "U$16") (pin "P$25") (pinfunction "A25_P$25") (pintype "bidirectional"))
      (node (ref "U$16") (pin "P$26") (pinfunction "A26_P$26") (pintype "bidirectional"))
      (node (ref "U$16") (pin "P$27") (pinfunction "A27_P$27") (pintype "bidirectional"))
      (node (ref "U$16") (pin "P$28") (pinfunction "A28_P$28") (pintype "bidirectional"))
      (node (ref "U$16") (pin "P$29") (pinfunction "A29_P$29") (pintype "bidirectional"))
      (node (ref "U$16") (pin "P$3") (pinfunction "A3_P$3") (pintype "bidirectional"))
      (node (ref "U$16") (pin "P$31") (pinfunction "B1_P$31") (pintype "bidirectional"))
      (node (ref "U$16") (pin "P$32") (pinfunction "B2_P$32") (pintype "bidirectional"))
      (node (ref "U$16") (pin "P$39") (pinfunction "B9_P$39") (pintype "bidirectional"))
      (node (ref "U$16") (pin "P$4") (pinfunction "A4_P$4") (pintype "bidirectional"))
      (node (ref "U$16") (pin "P$46") (pinfunction "B16_P$46") (pintype "bidirectional"))
      (node (ref "U$16") (pin "P$5") (pinfunction "A5_P$5") (pintype "bidirectional"))
      (node (ref "U$16") (pin "P$53") (pinfunction "B23_P$53") (pintype "bidirectional"))
      (node (ref "U$16") (pin "P$6") (pinfunction "A6_P$6") (pintype "bidirectional"))
      (node (ref "U$16") (pin "P$60") (pinfunction "B30_P$60") (pintype "bidirectional"))
      (node (ref "U$16") (pin "P$61") (pinfunction "C1_P$61") (pintype "bidirectional"))
      (node (ref "U$16") (pin "P$62") (pinfunction "C2_P$62") (pintype "bidirectional"))
      (node (ref "U$16") (pin "P$69") (pinfunction "C9_P$69") (pintype "bidirectional"))
      (node (ref "U$16") (pin "P$7") (pinfunction "A7_P$7") (pintype "bidirectional"))
      (node (ref "U$16") (pin "P$76") (pinfunction "C16_P$76") (pintype "bidirectional"))
      (node (ref "U$16") (pin "P$8") (pinfunction "A8_P$8") (pintype "bidirectional"))
      (node (ref "U$16") (pin "P$83") (pinfunction "C23_P$83") (pintype "bidirectional"))
      (node (ref "U$16") (pin "P$9") (pinfunction "A9_P$9") (pintype "bidirectional"))
      (node (ref "U$16") (pin "P$90") (pinfunction "C30_P$90") (pintype "bidirectional"))
      (node (ref "U$16") (pin "P$91") (pinfunction "D1_P$91") (pintype "bidirectional"))
      (node (ref "U$16") (pin "P$92") (pinfunction "D2_P$92") (pintype "bidirectional"))
      (node (ref "U$16") (pin "P$99") (pinfunction "D9_P$99") (pintype "bidirectional"))
      (node (ref "U$17") (pin "P$1") (pinfunction "GND_P$1") (pintype "bidirectional"))
      (node (ref "U$18") (pin "P$1") (pinfunction "GND_P$1") (pintype "bidirectional"))
      (node (ref "U$19") (pin "P$1") (pinfunction "GND_P$1") (pintype "bidirectional"))
      (node (ref "U$2") (pin "P$1") (pinfunction "A1_P$1") (pintype "bidirectional"))
      (node (ref "U$2") (pin "P$10") (pinfunction "A10_P$10") (pintype "bidirectional"))
      (node (ref "U$2") (pin "P$106") (pinfunction "D16_P$106") (pintype "bidirectional"))
      (node (ref "U$2") (pin "P$11") (pinfunction "A11_P$11") (pintype "bidirectional"))
      (node (ref "U$2") (pin "P$113") (pinfunction "D23_P$113") (pintype "bidirectional"))
      (node (ref "U$2") (pin "P$12") (pinfunction "A12_P$12") (pintype "bidirectional"))
      (node (ref "U$2") (pin "P$120") (pinfunction "D30_P$120") (pintype "bidirectional"))
      (node (ref "U$2") (pin "P$121") (pinfunction "E1_P$121") (pintype "bidirectional"))
      (node (ref "U$2") (pin "P$13") (pinfunction "A13_P$13") (pintype "bidirectional"))
      (node (ref "U$2") (pin "P$14") (pinfunction "A14_P$14") (pintype "bidirectional"))
      (node (ref "U$2") (pin "P$15") (pinfunction "A15_P$15") (pintype "bidirectional"))
      (node (ref "U$2") (pin "P$150") (pinfunction "E30_P$150") (pintype "bidirectional"))
      (node (ref "U$2") (pin "P$151") (pinfunction "F1_P$151") (pintype "bidirectional"))
      (node (ref "U$2") (pin "P$16") (pinfunction "A16_P$16") (pintype "bidirectional"))
      (node (ref "U$2") (pin "P$17") (pinfunction "A17_P$17") (pintype "bidirectional"))
      (node (ref "U$2") (pin "P$18") (pinfunction "A18_P$18") (pintype "bidirectional"))
      (node (ref "U$2") (pin "P$180") (pinfunction "F30_P$180") (pintype "bidirectional"))
      (node (ref "U$2") (pin "P$19") (pinfunction "A19_P$19") (pintype "bidirectional"))
      (node (ref "U$2") (pin "P$2") (pinfunction "A2_P$2") (pintype "bidirectional"))
      (node (ref "U$2") (pin "P$20") (pinfunction "A20_P$20") (pintype "bidirectional"))
      (node (ref "U$2") (pin "P$21") (pinfunction "A21_P$21") (pintype "bidirectional"))
      (node (ref "U$2") (pin "P$22") (pinfunction "A22_P$22") (pintype "bidirectional"))
      (node (ref "U$2") (pin "P$23") (pinfunction "A23_P$23") (pintype "bidirectional"))
      (node (ref "U$2") (pin "P$24") (pinfunction "A24_P$24") (pintype "bidirectional"))
      (node (ref "U$2") (pin "P$25") (pinfunction "A25_P$25") (pintype "bidirectional"))
      (node (ref "U$2") (pin "P$26") (pinfunction "A26_P$26") (pintype "bidirectional"))
      (node (ref "U$2") (pin "P$27") (pinfunction "A27_P$27") (pintype "bidirectional"))
      (node (ref "U$2") (pin "P$28") (pinfunction "A28_P$28") (pintype "bidirectional"))
      (node (ref "U$2") (pin "P$29") (pinfunction "A29_P$29") (pintype "bidirectional"))
      (node (ref "U$2") (pin "P$3") (pinfunction "A3_P$3") (pintype "bidirectional"))
      (node (ref "U$2") (pin "P$31") (pinfunction "B1_P$31") (pintype "bidirectional"))
      (node (ref "U$2") (pin "P$32") (pinfunction "B2_P$32") (pintype "bidirectional"))
      (node (ref "U$2") (pin "P$39") (pinfunction "B9_P$39") (pintype "bidirectional"))
      (node (ref "U$2") (pin "P$4") (pinfunction "A4_P$4") (pintype "bidirectional"))
      (node (ref "U$2") (pin "P$46") (pinfunction "B16_P$46") (pintype "bidirectional"))
      (node (ref "U$2") (pin "P$5") (pinfunction "A5_P$5") (pintype "bidirectional"))
      (node (ref "U$2") (pin "P$53") (pinfunction "B23_P$53") (pintype "bidirectional"))
      (node (ref "U$2") (pin "P$6") (pinfunction "A6_P$6") (pintype "bidirectional"))
      (node (ref "U$2") (pin "P$60") (pinfunction "B30_P$60") (pintype "bidirectional"))
      (node (ref "U$2") (pin "P$61") (pinfunction "C1_P$61") (pintype "bidirectional"))
      (node (ref "U$2") (pin "P$62") (pinfunction "C2_P$62") (pintype "bidirectional"))
      (node (ref "U$2") (pin "P$69") (pinfunction "C9_P$69") (pintype "bidirectional"))
      (node (ref "U$2") (pin "P$7") (pinfunction "A7_P$7") (pintype "bidirectional"))
      (node (ref "U$2") (pin "P$76") (pinfunction "C16_P$76") (pintype "bidirectional"))
      (node (ref "U$2") (pin "P$8") (pinfunction "A8_P$8") (pintype "bidirectional"))
      (node (ref "U$2") (pin "P$83") (pinfunction "C23_P$83") (pintype "bidirectional"))
      (node (ref "U$2") (pin "P$9") (pinfunction "A9_P$9") (pintype "bidirectional"))
      (node (ref "U$2") (pin "P$90") (pinfunction "C30_P$90") (pintype "bidirectional"))
      (node (ref "U$2") (pin "P$91") (pinfunction "D1_P$91") (pintype "bidirectional"))
      (node (ref "U$2") (pin "P$92") (pinfunction "D2_P$92") (pintype "bidirectional"))
      (node (ref "U$2") (pin "P$99") (pinfunction "D9_P$99") (pintype "bidirectional"))
      (node (ref "U$20") (pin "P$1") (pinfunction "GND_P$1") (pintype "bidirectional"))
      (node (ref "U$21") (pin "P$1") (pinfunction "GND_P$1") (pintype "bidirectional"))
      (node (ref "U$22") (pin "P$1") (pinfunction "GND_P$1") (pintype "bidirectional"))
      (node (ref "U$23") (pin "P$1") (pinfunction "GND_P$1") (pintype "bidirectional"))
      (node (ref "U$24") (pin "P$1") (pinfunction "GND_P$1") (pintype "bidirectional"))
      (node (ref "U$3") (pin "P$1") (pinfunction "A1_P$1") (pintype "bidirectional"))
      (node (ref "U$3") (pin "P$10") (pinfunction "A10_P$10") (pintype "bidirectional"))
      (node (ref "U$3") (pin "P$106") (pinfunction "D16_P$106") (pintype "bidirectional"))
      (node (ref "U$3") (pin "P$11") (pinfunction "A11_P$11") (pintype "bidirectional"))
      (node (ref "U$3") (pin "P$113") (pinfunction "D23_P$113") (pintype "bidirectional"))
      (node (ref "U$3") (pin "P$12") (pinfunction "A12_P$12") (pintype "bidirectional"))
      (node (ref "U$3") (pin "P$120") (pinfunction "D30_P$120") (pintype "bidirectional"))
      (node (ref "U$3") (pin "P$121") (pinfunction "E1_P$121") (pintype "bidirectional"))
      (node (ref "U$3") (pin "P$13") (pinfunction "A13_P$13") (pintype "bidirectional"))
      (node (ref "U$3") (pin "P$14") (pinfunction "A14_P$14") (pintype "bidirectional"))
      (node (ref "U$3") (pin "P$15") (pinfunction "A15_P$15") (pintype "bidirectional"))
      (node (ref "U$3") (pin "P$150") (pinfunction "E30_P$150") (pintype "bidirectional"))
      (node (ref "U$3") (pin "P$151") (pinfunction "F1_P$151") (pintype "bidirectional"))
      (node (ref "U$3") (pin "P$16") (pinfunction "A16_P$16") (pintype "bidirectional"))
      (node (ref "U$3") (pin "P$17") (pinfunction "A17_P$17") (pintype "bidirectional"))
      (node (ref "U$3") (pin "P$18") (pinfunction "A18_P$18") (pintype "bidirectional"))
      (node (ref "U$3") (pin "P$180") (pinfunction "F30_P$180") (pintype "bidirectional"))
      (node (ref "U$3") (pin "P$19") (pinfunction "A19_P$19") (pintype "bidirectional"))
      (node (ref "U$3") (pin "P$2") (pinfunction "A2_P$2") (pintype "bidirectional"))
      (node (ref "U$3") (pin "P$20") (pinfunction "A20_P$20") (pintype "bidirectional"))
      (node (ref "U$3") (pin "P$21") (pinfunction "A21_P$21") (pintype "bidirectional"))
      (node (ref "U$3") (pin "P$22") (pinfunction "A22_P$22") (pintype "bidirectional"))
      (node (ref "U$3") (pin "P$23") (pinfunction "A23_P$23") (pintype "bidirectional"))
      (node (ref "U$3") (pin "P$24") (pinfunction "A24_P$24") (pintype "bidirectional"))
      (node (ref "U$3") (pin "P$25") (pinfunction "A25_P$25") (pintype "bidirectional"))
      (node (ref "U$3") (pin "P$26") (pinfunction "A26_P$26") (pintype "bidirectional"))
      (node (ref "U$3") (pin "P$27") (pinfunction "A27_P$27") (pintype "bidirectional"))
      (node (ref "U$3") (pin "P$28") (pinfunction "A28_P$28") (pintype "bidirectional"))
      (node (ref "U$3") (pin "P$29") (pinfunction "A29_P$29") (pintype "bidirectional"))
      (node (ref "U$3") (pin "P$3") (pinfunction "A3_P$3") (pintype "bidirectional"))
      (node (ref "U$3") (pin "P$31") (pinfunction "B1_P$31") (pintype "bidirectional"))
      (node (ref "U$3") (pin "P$32") (pinfunction "B2_P$32") (pintype "bidirectional"))
      (node (ref "U$3") (pin "P$39") (pinfunction "B9_P$39") (pintype "bidirectional"))
      (node (ref "U$3") (pin "P$4") (pinfunction "A4_P$4") (pintype "bidirectional"))
      (node (ref "U$3") (pin "P$46") (pinfunction "B16_P$46") (pintype "bidirectional"))
      (node (ref "U$3") (pin "P$5") (pinfunction "A5_P$5") (pintype "bidirectional"))
      (node (ref "U$3") (pin "P$53") (pinfunction "B23_P$53") (pintype "bidirectional"))
      (node (ref "U$3") (pin "P$6") (pinfunction "A6_P$6") (pintype "bidirectional"))
      (node (ref "U$3") (pin "P$60") (pinfunction "B30_P$60") (pintype "bidirectional"))
      (node (ref "U$3") (pin "P$61") (pinfunction "C1_P$61") (pintype "bidirectional"))
      (node (ref "U$3") (pin "P$62") (pinfunction "C2_P$62") (pintype "bidirectional"))
      (node (ref "U$3") (pin "P$69") (pinfunction "C9_P$69") (pintype "bidirectional"))
      (node (ref "U$3") (pin "P$7") (pinfunction "A7_P$7") (pintype "bidirectional"))
      (node (ref "U$3") (pin "P$76") (pinfunction "C16_P$76") (pintype "bidirectional"))
      (node (ref "U$3") (pin "P$8") (pinfunction "A8_P$8") (pintype "bidirectional"))
      (node (ref "U$3") (pin "P$83") (pinfunction "C23_P$83") (pintype "bidirectional"))
      (node (ref "U$3") (pin "P$9") (pinfunction "A9_P$9") (pintype "bidirectional"))
      (node (ref "U$3") (pin "P$90") (pinfunction "C30_P$90") (pintype "bidirectional"))
      (node (ref "U$3") (pin "P$91") (pinfunction "D1_P$91") (pintype "bidirectional"))
      (node (ref "U$3") (pin "P$92") (pinfunction "D2_P$92") (pintype "bidirectional"))
      (node (ref "U$3") (pin "P$99") (pinfunction "D9_P$99") (pintype "bidirectional"))
      (node (ref "U$4") (pin "P$1") (pinfunction "A1_P$1") (pintype "bidirectional"))
      (node (ref "U$4") (pin "P$10") (pinfunction "A10_P$10") (pintype "bidirectional"))
      (node (ref "U$4") (pin "P$106") (pinfunction "D16_P$106") (pintype "bidirectional"))
      (node (ref "U$4") (pin "P$11") (pinfunction "A11_P$11") (pintype "bidirectional"))
      (node (ref "U$4") (pin "P$113") (pinfunction "D23_P$113") (pintype "bidirectional"))
      (node (ref "U$4") (pin "P$12") (pinfunction "A12_P$12") (pintype "bidirectional"))
      (node (ref "U$4") (pin "P$120") (pinfunction "D30_P$120") (pintype "bidirectional"))
      (node (ref "U$4") (pin "P$121") (pinfunction "E1_P$121") (pintype "bidirectional"))
      (node (ref "U$4") (pin "P$13") (pinfunction "A13_P$13") (pintype "bidirectional"))
      (node (ref "U$4") (pin "P$14") (pinfunction "A14_P$14") (pintype "bidirectional"))
      (node (ref "U$4") (pin "P$15") (pinfunction "A15_P$15") (pintype "bidirectional"))
      (node (ref "U$4") (pin "P$150") (pinfunction "E30_P$150") (pintype "bidirectional"))
      (node (ref "U$4") (pin "P$151") (pinfunction "F1_P$151") (pintype "bidirectional"))
      (node (ref "U$4") (pin "P$16") (pinfunction "A16_P$16") (pintype "bidirectional"))
      (node (ref "U$4") (pin "P$17") (pinfunction "A17_P$17") (pintype "bidirectional"))
      (node (ref "U$4") (pin "P$18") (pinfunction "A18_P$18") (pintype "bidirectional"))
      (node (ref "U$4") (pin "P$180") (pinfunction "F30_P$180") (pintype "bidirectional"))
      (node (ref "U$4") (pin "P$19") (pinfunction "A19_P$19") (pintype "bidirectional"))
      (node (ref "U$4") (pin "P$2") (pinfunction "A2_P$2") (pintype "bidirectional"))
      (node (ref "U$4") (pin "P$20") (pinfunction "A20_P$20") (pintype "bidirectional"))
      (node (ref "U$4") (pin "P$21") (pinfunction "A21_P$21") (pintype "bidirectional"))
      (node (ref "U$4") (pin "P$22") (pinfunction "A22_P$22") (pintype "bidirectional"))
      (node (ref "U$4") (pin "P$23") (pinfunction "A23_P$23") (pintype "bidirectional"))
      (node (ref "U$4") (pin "P$24") (pinfunction "A24_P$24") (pintype "bidirectional"))
      (node (ref "U$4") (pin "P$25") (pinfunction "A25_P$25") (pintype "bidirectional"))
      (node (ref "U$4") (pin "P$26") (pinfunction "A26_P$26") (pintype "bidirectional"))
      (node (ref "U$4") (pin "P$27") (pinfunction "A27_P$27") (pintype "bidirectional"))
      (node (ref "U$4") (pin "P$28") (pinfunction "A28_P$28") (pintype "bidirectional"))
      (node (ref "U$4") (pin "P$29") (pinfunction "A29_P$29") (pintype "bidirectional"))
      (node (ref "U$4") (pin "P$3") (pinfunction "A3_P$3") (pintype "bidirectional"))
      (node (ref "U$4") (pin "P$31") (pinfunction "B1_P$31") (pintype "bidirectional"))
      (node (ref "U$4") (pin "P$32") (pinfunction "B2_P$32") (pintype "bidirectional"))
      (node (ref "U$4") (pin "P$39") (pinfunction "B9_P$39") (pintype "bidirectional"))
      (node (ref "U$4") (pin "P$4") (pinfunction "A4_P$4") (pintype "bidirectional"))
      (node (ref "U$4") (pin "P$46") (pinfunction "B16_P$46") (pintype "bidirectional"))
      (node (ref "U$4") (pin "P$5") (pinfunction "A5_P$5") (pintype "bidirectional"))
      (node (ref "U$4") (pin "P$53") (pinfunction "B23_P$53") (pintype "bidirectional"))
      (node (ref "U$4") (pin "P$6") (pinfunction "A6_P$6") (pintype "bidirectional"))
      (node (ref "U$4") (pin "P$60") (pinfunction "B30_P$60") (pintype "bidirectional"))
      (node (ref "U$4") (pin "P$61") (pinfunction "C1_P$61") (pintype "bidirectional"))
      (node (ref "U$4") (pin "P$62") (pinfunction "C2_P$62") (pintype "bidirectional"))
      (node (ref "U$4") (pin "P$69") (pinfunction "C9_P$69") (pintype "bidirectional"))
      (node (ref "U$4") (pin "P$7") (pinfunction "A7_P$7") (pintype "bidirectional"))
      (node (ref "U$4") (pin "P$76") (pinfunction "C16_P$76") (pintype "bidirectional"))
      (node (ref "U$4") (pin "P$8") (pinfunction "A8_P$8") (pintype "bidirectional"))
      (node (ref "U$4") (pin "P$83") (pinfunction "C23_P$83") (pintype "bidirectional"))
      (node (ref "U$4") (pin "P$9") (pinfunction "A9_P$9") (pintype "bidirectional"))
      (node (ref "U$4") (pin "P$90") (pinfunction "C30_P$90") (pintype "bidirectional"))
      (node (ref "U$4") (pin "P$91") (pinfunction "D1_P$91") (pintype "bidirectional"))
      (node (ref "U$4") (pin "P$92") (pinfunction "D2_P$92") (pintype "bidirectional"))
      (node (ref "U$4") (pin "P$99") (pinfunction "D9_P$99") (pintype "bidirectional"))
      (node (ref "U$5") (pin "P$1") (pinfunction "A1_P$1") (pintype "bidirectional"))
      (node (ref "U$5") (pin "P$10") (pinfunction "A10_P$10") (pintype "bidirectional"))
      (node (ref "U$5") (pin "P$106") (pinfunction "D16_P$106") (pintype "bidirectional"))
      (node (ref "U$5") (pin "P$11") (pinfunction "A11_P$11") (pintype "bidirectional"))
      (node (ref "U$5") (pin "P$113") (pinfunction "D23_P$113") (pintype "bidirectional"))
      (node (ref "U$5") (pin "P$12") (pinfunction "A12_P$12") (pintype "bidirectional"))
      (node (ref "U$5") (pin "P$120") (pinfunction "D30_P$120") (pintype "bidirectional"))
      (node (ref "U$5") (pin "P$121") (pinfunction "E1_P$121") (pintype "bidirectional"))
      (node (ref "U$5") (pin "P$13") (pinfunction "A13_P$13") (pintype "bidirectional"))
      (node (ref "U$5") (pin "P$14") (pinfunction "A14_P$14") (pintype "bidirectional"))
      (node (ref "U$5") (pin "P$15") (pinfunction "A15_P$15") (pintype "bidirectional"))
      (node (ref "U$5") (pin "P$150") (pinfunction "E30_P$150") (pintype "bidirectional"))
      (node (ref "U$5") (pin "P$151") (pinfunction "F1_P$151") (pintype "bidirectional"))
      (node (ref "U$5") (pin "P$16") (pinfunction "A16_P$16") (pintype "bidirectional"))
      (node (ref "U$5") (pin "P$17") (pinfunction "A17_P$17") (pintype "bidirectional"))
      (node (ref "U$5") (pin "P$18") (pinfunction "A18_P$18") (pintype "bidirectional"))
      (node (ref "U$5") (pin "P$180") (pinfunction "F30_P$180") (pintype "bidirectional"))
      (node (ref "U$5") (pin "P$19") (pinfunction "A19_P$19") (pintype "bidirectional"))
      (node (ref "U$5") (pin "P$2") (pinfunction "A2_P$2") (pintype "bidirectional"))
      (node (ref "U$5") (pin "P$20") (pinfunction "A20_P$20") (pintype "bidirectional"))
      (node (ref "U$5") (pin "P$21") (pinfunction "A21_P$21") (pintype "bidirectional"))
      (node (ref "U$5") (pin "P$22") (pinfunction "A22_P$22") (pintype "bidirectional"))
      (node (ref "U$5") (pin "P$23") (pinfunction "A23_P$23") (pintype "bidirectional"))
      (node (ref "U$5") (pin "P$24") (pinfunction "A24_P$24") (pintype "bidirectional"))
      (node (ref "U$5") (pin "P$25") (pinfunction "A25_P$25") (pintype "bidirectional"))
      (node (ref "U$5") (pin "P$26") (pinfunction "A26_P$26") (pintype "bidirectional"))
      (node (ref "U$5") (pin "P$27") (pinfunction "A27_P$27") (pintype "bidirectional"))
      (node (ref "U$5") (pin "P$28") (pinfunction "A28_P$28") (pintype "bidirectional"))
      (node (ref "U$5") (pin "P$29") (pinfunction "A29_P$29") (pintype "bidirectional"))
      (node (ref "U$5") (pin "P$3") (pinfunction "A3_P$3") (pintype "bidirectional"))
      (node (ref "U$5") (pin "P$31") (pinfunction "B1_P$31") (pintype "bidirectional"))
      (node (ref "U$5") (pin "P$32") (pinfunction "B2_P$32") (pintype "bidirectional"))
      (node (ref "U$5") (pin "P$39") (pinfunction "B9_P$39") (pintype "bidirectional"))
      (node (ref "U$5") (pin "P$4") (pinfunction "A4_P$4") (pintype "bidirectional"))
      (node (ref "U$5") (pin "P$46") (pinfunction "B16_P$46") (pintype "bidirectional"))
      (node (ref "U$5") (pin "P$5") (pinfunction "A5_P$5") (pintype "bidirectional"))
      (node (ref "U$5") (pin "P$53") (pinfunction "B23_P$53") (pintype "bidirectional"))
      (node (ref "U$5") (pin "P$6") (pinfunction "A6_P$6") (pintype "bidirectional"))
      (node (ref "U$5") (pin "P$60") (pinfunction "B30_P$60") (pintype "bidirectional"))
      (node (ref "U$5") (pin "P$61") (pinfunction "C1_P$61") (pintype "bidirectional"))
      (node (ref "U$5") (pin "P$62") (pinfunction "C2_P$62") (pintype "bidirectional"))
      (node (ref "U$5") (pin "P$69") (pinfunction "C9_P$69") (pintype "bidirectional"))
      (node (ref "U$5") (pin "P$7") (pinfunction "A7_P$7") (pintype "bidirectional"))
      (node (ref "U$5") (pin "P$76") (pinfunction "C16_P$76") (pintype "bidirectional"))
      (node (ref "U$5") (pin "P$8") (pinfunction "A8_P$8") (pintype "bidirectional"))
      (node (ref "U$5") (pin "P$83") (pinfunction "C23_P$83") (pintype "bidirectional"))
      (node (ref "U$5") (pin "P$9") (pinfunction "A9_P$9") (pintype "bidirectional"))
      (node (ref "U$5") (pin "P$90") (pinfunction "C30_P$90") (pintype "bidirectional"))
      (node (ref "U$5") (pin "P$91") (pinfunction "D1_P$91") (pintype "bidirectional"))
      (node (ref "U$5") (pin "P$92") (pinfunction "D2_P$92") (pintype "bidirectional"))
      (node (ref "U$5") (pin "P$99") (pinfunction "D9_P$99") (pintype "bidirectional"))
      (node (ref "U$6") (pin "P$1") (pinfunction "A1_P$1") (pintype "bidirectional"))
      (node (ref "U$6") (pin "P$10") (pinfunction "A10_P$10") (pintype "bidirectional"))
      (node (ref "U$6") (pin "P$106") (pinfunction "D16_P$106") (pintype "bidirectional"))
      (node (ref "U$6") (pin "P$11") (pinfunction "A11_P$11") (pintype "bidirectional"))
      (node (ref "U$6") (pin "P$113") (pinfunction "D23_P$113") (pintype "bidirectional"))
      (node (ref "U$6") (pin "P$12") (pinfunction "A12_P$12") (pintype "bidirectional"))
      (node (ref "U$6") (pin "P$120") (pinfunction "D30_P$120") (pintype "bidirectional"))
      (node (ref "U$6") (pin "P$121") (pinfunction "E1_P$121") (pintype "bidirectional"))
      (node (ref "U$6") (pin "P$13") (pinfunction "A13_P$13") (pintype "bidirectional"))
      (node (ref "U$6") (pin "P$14") (pinfunction "A14_P$14") (pintype "bidirectional"))
      (node (ref "U$6") (pin "P$15") (pinfunction "A15_P$15") (pintype "bidirectional"))
      (node (ref "U$6") (pin "P$150") (pinfunction "E30_P$150") (pintype "bidirectional"))
      (node (ref "U$6") (pin "P$151") (pinfunction "F1_P$151") (pintype "bidirectional"))
      (node (ref "U$6") (pin "P$16") (pinfunction "A16_P$16") (pintype "bidirectional"))
      (node (ref "U$6") (pin "P$17") (pinfunction "A17_P$17") (pintype "bidirectional"))
      (node (ref "U$6") (pin "P$18") (pinfunction "A18_P$18") (pintype "bidirectional"))
      (node (ref "U$6") (pin "P$180") (pinfunction "F30_P$180") (pintype "bidirectional"))
      (node (ref "U$6") (pin "P$19") (pinfunction "A19_P$19") (pintype "bidirectional"))
      (node (ref "U$6") (pin "P$2") (pinfunction "A2_P$2") (pintype "bidirectional"))
      (node (ref "U$6") (pin "P$20") (pinfunction "A20_P$20") (pintype "bidirectional"))
      (node (ref "U$6") (pin "P$21") (pinfunction "A21_P$21") (pintype "bidirectional"))
      (node (ref "U$6") (pin "P$22") (pinfunction "A22_P$22") (pintype "bidirectional"))
      (node (ref "U$6") (pin "P$23") (pinfunction "A23_P$23") (pintype "bidirectional"))
      (node (ref "U$6") (pin "P$24") (pinfunction "A24_P$24") (pintype "bidirectional"))
      (node (ref "U$6") (pin "P$25") (pinfunction "A25_P$25") (pintype "bidirectional"))
      (node (ref "U$6") (pin "P$26") (pinfunction "A26_P$26") (pintype "bidirectional"))
      (node (ref "U$6") (pin "P$27") (pinfunction "A27_P$27") (pintype "bidirectional"))
      (node (ref "U$6") (pin "P$28") (pinfunction "A28_P$28") (pintype "bidirectional"))
      (node (ref "U$6") (pin "P$29") (pinfunction "A29_P$29") (pintype "bidirectional"))
      (node (ref "U$6") (pin "P$3") (pinfunction "A3_P$3") (pintype "bidirectional"))
      (node (ref "U$6") (pin "P$31") (pinfunction "B1_P$31") (pintype "bidirectional"))
      (node (ref "U$6") (pin "P$32") (pinfunction "B2_P$32") (pintype "bidirectional"))
      (node (ref "U$6") (pin "P$39") (pinfunction "B9_P$39") (pintype "bidirectional"))
      (node (ref "U$6") (pin "P$4") (pinfunction "A4_P$4") (pintype "bidirectional"))
      (node (ref "U$6") (pin "P$46") (pinfunction "B16_P$46") (pintype "bidirectional"))
      (node (ref "U$6") (pin "P$5") (pinfunction "A5_P$5") (pintype "bidirectional"))
      (node (ref "U$6") (pin "P$53") (pinfunction "B23_P$53") (pintype "bidirectional"))
      (node (ref "U$6") (pin "P$6") (pinfunction "A6_P$6") (pintype "bidirectional"))
      (node (ref "U$6") (pin "P$60") (pinfunction "B30_P$60") (pintype "bidirectional"))
      (node (ref "U$6") (pin "P$61") (pinfunction "C1_P$61") (pintype "bidirectional"))
      (node (ref "U$6") (pin "P$62") (pinfunction "C2_P$62") (pintype "bidirectional"))
      (node (ref "U$6") (pin "P$69") (pinfunction "C9_P$69") (pintype "bidirectional"))
      (node (ref "U$6") (pin "P$7") (pinfunction "A7_P$7") (pintype "bidirectional"))
      (node (ref "U$6") (pin "P$76") (pinfunction "C16_P$76") (pintype "bidirectional"))
      (node (ref "U$6") (pin "P$8") (pinfunction "A8_P$8") (pintype "bidirectional"))
      (node (ref "U$6") (pin "P$83") (pinfunction "C23_P$83") (pintype "bidirectional"))
      (node (ref "U$6") (pin "P$9") (pinfunction "A9_P$9") (pintype "bidirectional"))
      (node (ref "U$6") (pin "P$90") (pinfunction "C30_P$90") (pintype "bidirectional"))
      (node (ref "U$6") (pin "P$91") (pinfunction "D1_P$91") (pintype "bidirectional"))
      (node (ref "U$6") (pin "P$92") (pinfunction "D2_P$92") (pintype "bidirectional"))
      (node (ref "U$6") (pin "P$99") (pinfunction "D9_P$99") (pintype "bidirectional"))
      (node (ref "U$7") (pin "P$1") (pinfunction "A1_P$1") (pintype "bidirectional"))
      (node (ref "U$7") (pin "P$10") (pinfunction "A10_P$10") (pintype "bidirectional"))
      (node (ref "U$7") (pin "P$106") (pinfunction "D16_P$106") (pintype "bidirectional"))
      (node (ref "U$7") (pin "P$11") (pinfunction "A11_P$11") (pintype "bidirectional"))
      (node (ref "U$7") (pin "P$113") (pinfunction "D23_P$113") (pintype "bidirectional"))
      (node (ref "U$7") (pin "P$12") (pinfunction "A12_P$12") (pintype "bidirectional"))
      (node (ref "U$7") (pin "P$120") (pinfunction "D30_P$120") (pintype "bidirectional"))
      (node (ref "U$7") (pin "P$121") (pinfunction "E1_P$121") (pintype "bidirectional"))
      (node (ref "U$7") (pin "P$13") (pinfunction "A13_P$13") (pintype "bidirectional"))
      (node (ref "U$7") (pin "P$14") (pinfunction "A14_P$14") (pintype "bidirectional"))
      (node (ref "U$7") (pin "P$15") (pinfunction "A15_P$15") (pintype "bidirectional"))
      (node (ref "U$7") (pin "P$150") (pinfunction "E30_P$150") (pintype "bidirectional"))
      (node (ref "U$7") (pin "P$151") (pinfunction "F1_P$151") (pintype "bidirectional"))
      (node (ref "U$7") (pin "P$16") (pinfunction "A16_P$16") (pintype "bidirectional"))
      (node (ref "U$7") (pin "P$17") (pinfunction "A17_P$17") (pintype "bidirectional"))
      (node (ref "U$7") (pin "P$18") (pinfunction "A18_P$18") (pintype "bidirectional"))
      (node (ref "U$7") (pin "P$180") (pinfunction "F30_P$180") (pintype "bidirectional"))
      (node (ref "U$7") (pin "P$19") (pinfunction "A19_P$19") (pintype "bidirectional"))
      (node (ref "U$7") (pin "P$2") (pinfunction "A2_P$2") (pintype "bidirectional"))
      (node (ref "U$7") (pin "P$20") (pinfunction "A20_P$20") (pintype "bidirectional"))
      (node (ref "U$7") (pin "P$21") (pinfunction "A21_P$21") (pintype "bidirectional"))
      (node (ref "U$7") (pin "P$22") (pinfunction "A22_P$22") (pintype "bidirectional"))
      (node (ref "U$7") (pin "P$23") (pinfunction "A23_P$23") (pintype "bidirectional"))
      (node (ref "U$7") (pin "P$24") (pinfunction "A24_P$24") (pintype "bidirectional"))
      (node (ref "U$7") (pin "P$25") (pinfunction "A25_P$25") (pintype "bidirectional"))
      (node (ref "U$7") (pin "P$26") (pinfunction "A26_P$26") (pintype "bidirectional"))
      (node (ref "U$7") (pin "P$27") (pinfunction "A27_P$27") (pintype "bidirectional"))
      (node (ref "U$7") (pin "P$28") (pinfunction "A28_P$28") (pintype "bidirectional"))
      (node (ref "U$7") (pin "P$29") (pinfunction "A29_P$29") (pintype "bidirectional"))
      (node (ref "U$7") (pin "P$3") (pinfunction "A3_P$3") (pintype "bidirectional"))
      (node (ref "U$7") (pin "P$31") (pinfunction "B1_P$31") (pintype "bidirectional"))
      (node (ref "U$7") (pin "P$32") (pinfunction "B2_P$32") (pintype "bidirectional"))
      (node (ref "U$7") (pin "P$39") (pinfunction "B9_P$39") (pintype "bidirectional"))
      (node (ref "U$7") (pin "P$4") (pinfunction "A4_P$4") (pintype "bidirectional"))
      (node (ref "U$7") (pin "P$46") (pinfunction "B16_P$46") (pintype "bidirectional"))
      (node (ref "U$7") (pin "P$5") (pinfunction "A5_P$5") (pintype "bidirectional"))
      (node (ref "U$7") (pin "P$53") (pinfunction "B23_P$53") (pintype "bidirectional"))
      (node (ref "U$7") (pin "P$6") (pinfunction "A6_P$6") (pintype "bidirectional"))
      (node (ref "U$7") (pin "P$60") (pinfunction "B30_P$60") (pintype "bidirectional"))
      (node (ref "U$7") (pin "P$61") (pinfunction "C1_P$61") (pintype "bidirectional"))
      (node (ref "U$7") (pin "P$62") (pinfunction "C2_P$62") (pintype "bidirectional"))
      (node (ref "U$7") (pin "P$69") (pinfunction "C9_P$69") (pintype "bidirectional"))
      (node (ref "U$7") (pin "P$7") (pinfunction "A7_P$7") (pintype "bidirectional"))
      (node (ref "U$7") (pin "P$76") (pinfunction "C16_P$76") (pintype "bidirectional"))
      (node (ref "U$7") (pin "P$8") (pinfunction "A8_P$8") (pintype "bidirectional"))
      (node (ref "U$7") (pin "P$83") (pinfunction "C23_P$83") (pintype "bidirectional"))
      (node (ref "U$7") (pin "P$9") (pinfunction "A9_P$9") (pintype "bidirectional"))
      (node (ref "U$7") (pin "P$90") (pinfunction "C30_P$90") (pintype "bidirectional"))
      (node (ref "U$7") (pin "P$91") (pinfunction "D1_P$91") (pintype "bidirectional"))
      (node (ref "U$7") (pin "P$92") (pinfunction "D2_P$92") (pintype "bidirectional"))
      (node (ref "U$7") (pin "P$99") (pinfunction "D9_P$99") (pintype "bidirectional"))
      (node (ref "U$8") (pin "P$1") (pinfunction "A1_P$1") (pintype "bidirectional"))
      (node (ref "U$8") (pin "P$10") (pinfunction "A10_P$10") (pintype "bidirectional"))
      (node (ref "U$8") (pin "P$106") (pinfunction "D16_P$106") (pintype "bidirectional"))
      (node (ref "U$8") (pin "P$11") (pinfunction "A11_P$11") (pintype "bidirectional"))
      (node (ref "U$8") (pin "P$113") (pinfunction "D23_P$113") (pintype "bidirectional"))
      (node (ref "U$8") (pin "P$12") (pinfunction "A12_P$12") (pintype "bidirectional"))
      (node (ref "U$8") (pin "P$120") (pinfunction "D30_P$120") (pintype "bidirectional"))
      (node (ref "U$8") (pin "P$121") (pinfunction "E1_P$121") (pintype "bidirectional"))
      (node (ref "U$8") (pin "P$13") (pinfunction "A13_P$13") (pintype "bidirectional"))
      (node (ref "U$8") (pin "P$14") (pinfunction "A14_P$14") (pintype "bidirectional"))
      (node (ref "U$8") (pin "P$15") (pinfunction "A15_P$15") (pintype "bidirectional"))
      (node (ref "U$8") (pin "P$150") (pinfunction "E30_P$150") (pintype "bidirectional"))
      (node (ref "U$8") (pin "P$151") (pinfunction "F1_P$151") (pintype "bidirectional"))
      (node (ref "U$8") (pin "P$16") (pinfunction "A16_P$16") (pintype "bidirectional"))
      (node (ref "U$8") (pin "P$17") (pinfunction "A17_P$17") (pintype "bidirectional"))
      (node (ref "U$8") (pin "P$18") (pinfunction "A18_P$18") (pintype "bidirectional"))
      (node (ref "U$8") (pin "P$180") (pinfunction "F30_P$180") (pintype "bidirectional"))
      (node (ref "U$8") (pin "P$19") (pinfunction "A19_P$19") (pintype "bidirectional"))
      (node (ref "U$8") (pin "P$2") (pinfunction "A2_P$2") (pintype "bidirectional"))
      (node (ref "U$8") (pin "P$20") (pinfunction "A20_P$20") (pintype "bidirectional"))
      (node (ref "U$8") (pin "P$21") (pinfunction "A21_P$21") (pintype "bidirectional"))
      (node (ref "U$8") (pin "P$22") (pinfunction "A22_P$22") (pintype "bidirectional"))
      (node (ref "U$8") (pin "P$23") (pinfunction "A23_P$23") (pintype "bidirectional"))
      (node (ref "U$8") (pin "P$24") (pinfunction "A24_P$24") (pintype "bidirectional"))
      (node (ref "U$8") (pin "P$25") (pinfunction "A25_P$25") (pintype "bidirectional"))
      (node (ref "U$8") (pin "P$26") (pinfunction "A26_P$26") (pintype "bidirectional"))
      (node (ref "U$8") (pin "P$27") (pinfunction "A27_P$27") (pintype "bidirectional"))
      (node (ref "U$8") (pin "P$28") (pinfunction "A28_P$28") (pintype "bidirectional"))
      (node (ref "U$8") (pin "P$29") (pinfunction "A29_P$29") (pintype "bidirectional"))
      (node (ref "U$8") (pin "P$3") (pinfunction "A3_P$3") (pintype "bidirectional"))
      (node (ref "U$8") (pin "P$31") (pinfunction "B1_P$31") (pintype "bidirectional"))
      (node (ref "U$8") (pin "P$32") (pinfunction "B2_P$32") (pintype "bidirectional"))
      (node (ref "U$8") (pin "P$39") (pinfunction "B9_P$39") (pintype "bidirectional"))
      (node (ref "U$8") (pin "P$4") (pinfunction "A4_P$4") (pintype "bidirectional"))
      (node (ref "U$8") (pin "P$46") (pinfunction "B16_P$46") (pintype "bidirectional"))
      (node (ref "U$8") (pin "P$5") (pinfunction "A5_P$5") (pintype "bidirectional"))
      (node (ref "U$8") (pin "P$53") (pinfunction "B23_P$53") (pintype "bidirectional"))
      (node (ref "U$8") (pin "P$6") (pinfunction "A6_P$6") (pintype "bidirectional"))
      (node (ref "U$8") (pin "P$60") (pinfunction "B30_P$60") (pintype "bidirectional"))
      (node (ref "U$8") (pin "P$61") (pinfunction "C1_P$61") (pintype "bidirectional"))
      (node (ref "U$8") (pin "P$62") (pinfunction "C2_P$62") (pintype "bidirectional"))
      (node (ref "U$8") (pin "P$69") (pinfunction "C9_P$69") (pintype "bidirectional"))
      (node (ref "U$8") (pin "P$7") (pinfunction "A7_P$7") (pintype "bidirectional"))
      (node (ref "U$8") (pin "P$76") (pinfunction "C16_P$76") (pintype "bidirectional"))
      (node (ref "U$8") (pin "P$8") (pinfunction "A8_P$8") (pintype "bidirectional"))
      (node (ref "U$8") (pin "P$83") (pinfunction "C23_P$83") (pintype "bidirectional"))
      (node (ref "U$8") (pin "P$9") (pinfunction "A9_P$9") (pintype "bidirectional"))
      (node (ref "U$8") (pin "P$90") (pinfunction "C30_P$90") (pintype "bidirectional"))
      (node (ref "U$8") (pin "P$91") (pinfunction "D1_P$91") (pintype "bidirectional"))
      (node (ref "U$8") (pin "P$92") (pinfunction "D2_P$92") (pintype "bidirectional"))
      (node (ref "U$8") (pin "P$99") (pinfunction "D9_P$99") (pintype "bidirectional"))
      (node (ref "U$9") (pin "P$1") (pinfunction "A1_P$1") (pintype "bidirectional"))
      (node (ref "U$9") (pin "P$10") (pinfunction "A10_P$10") (pintype "bidirectional"))
      (node (ref "U$9") (pin "P$106") (pinfunction "D16_P$106") (pintype "bidirectional"))
      (node (ref "U$9") (pin "P$11") (pinfunction "A11_P$11") (pintype "bidirectional"))
      (node (ref "U$9") (pin "P$113") (pinfunction "D23_P$113") (pintype "bidirectional"))
      (node (ref "U$9") (pin "P$12") (pinfunction "A12_P$12") (pintype "bidirectional"))
      (node (ref "U$9") (pin "P$120") (pinfunction "D30_P$120") (pintype "bidirectional"))
      (node (ref "U$9") (pin "P$121") (pinfunction "E1_P$121") (pintype "bidirectional"))
      (node (ref "U$9") (pin "P$13") (pinfunction "A13_P$13") (pintype "bidirectional"))
      (node (ref "U$9") (pin "P$14") (pinfunction "A14_P$14") (pintype "bidirectional"))
      (node (ref "U$9") (pin "P$15") (pinfunction "A15_P$15") (pintype "bidirectional"))
      (node (ref "U$9") (pin "P$150") (pinfunction "E30_P$150") (pintype "bidirectional"))
      (node (ref "U$9") (pin "P$151") (pinfunction "F1_P$151") (pintype "bidirectional"))
      (node (ref "U$9") (pin "P$16") (pinfunction "A16_P$16") (pintype "bidirectional"))
      (node (ref "U$9") (pin "P$17") (pinfunction "A17_P$17") (pintype "bidirectional"))
      (node (ref "U$9") (pin "P$18") (pinfunction "A18_P$18") (pintype "bidirectional"))
      (node (ref "U$9") (pin "P$180") (pinfunction "F30_P$180") (pintype "bidirectional"))
      (node (ref "U$9") (pin "P$19") (pinfunction "A19_P$19") (pintype "bidirectional"))
      (node (ref "U$9") (pin "P$2") (pinfunction "A2_P$2") (pintype "bidirectional"))
      (node (ref "U$9") (pin "P$20") (pinfunction "A20_P$20") (pintype "bidirectional"))
      (node (ref "U$9") (pin "P$21") (pinfunction "A21_P$21") (pintype "bidirectional"))
      (node (ref "U$9") (pin "P$22") (pinfunction "A22_P$22") (pintype "bidirectional"))
      (node (ref "U$9") (pin "P$23") (pinfunction "A23_P$23") (pintype "bidirectional"))
      (node (ref "U$9") (pin "P$24") (pinfunction "A24_P$24") (pintype "bidirectional"))
      (node (ref "U$9") (pin "P$25") (pinfunction "A25_P$25") (pintype "bidirectional"))
      (node (ref "U$9") (pin "P$26") (pinfunction "A26_P$26") (pintype "bidirectional"))
      (node (ref "U$9") (pin "P$27") (pinfunction "A27_P$27") (pintype "bidirectional"))
      (node (ref "U$9") (pin "P$28") (pinfunction "A28_P$28") (pintype "bidirectional"))
      (node (ref "U$9") (pin "P$29") (pinfunction "A29_P$29") (pintype "bidirectional"))
      (node (ref "U$9") (pin "P$3") (pinfunction "A3_P$3") (pintype "bidirectional"))
      (node (ref "U$9") (pin "P$31") (pinfunction "B1_P$31") (pintype "bidirectional"))
      (node (ref "U$9") (pin "P$32") (pinfunction "B2_P$32") (pintype "bidirectional"))
      (node (ref "U$9") (pin "P$39") (pinfunction "B9_P$39") (pintype "bidirectional"))
      (node (ref "U$9") (pin "P$4") (pinfunction "A4_P$4") (pintype "bidirectional"))
      (node (ref "U$9") (pin "P$46") (pinfunction "B16_P$46") (pintype "bidirectional"))
      (node (ref "U$9") (pin "P$5") (pinfunction "A5_P$5") (pintype "bidirectional"))
      (node (ref "U$9") (pin "P$53") (pinfunction "B23_P$53") (pintype "bidirectional"))
      (node (ref "U$9") (pin "P$6") (pinfunction "A6_P$6") (pintype "bidirectional"))
      (node (ref "U$9") (pin "P$60") (pinfunction "B30_P$60") (pintype "bidirectional"))
      (node (ref "U$9") (pin "P$61") (pinfunction "C1_P$61") (pintype "bidirectional"))
      (node (ref "U$9") (pin "P$62") (pinfunction "C2_P$62") (pintype "bidirectional"))
      (node (ref "U$9") (pin "P$69") (pinfunction "C9_P$69") (pintype "bidirectional"))
      (node (ref "U$9") (pin "P$7") (pinfunction "A7_P$7") (pintype "bidirectional"))
      (node (ref "U$9") (pin "P$76") (pinfunction "C16_P$76") (pintype "bidirectional"))
      (node (ref "U$9") (pin "P$8") (pinfunction "A8_P$8") (pintype "bidirectional"))
      (node (ref "U$9") (pin "P$83") (pinfunction "C23_P$83") (pintype "bidirectional"))
      (node (ref "U$9") (pin "P$9") (pinfunction "A9_P$9") (pintype "bidirectional"))
      (node (ref "U$9") (pin "P$90") (pinfunction "C30_P$90") (pintype "bidirectional"))
      (node (ref "U$9") (pin "P$91") (pinfunction "D1_P$91") (pintype "bidirectional"))
      (node (ref "U$9") (pin "P$92") (pinfunction "D2_P$92") (pintype "bidirectional"))
      (node (ref "U$9") (pin "P$99") (pinfunction "D9_P$99") (pintype "bidirectional"))
    )
    (net (code "2") (name "Net-(U$1-A30)") (class "Default")
      (node (ref "U$1") (pin "P$30") (pinfunction "A30_P$30") (pintype "bidirectional"))
      (node (ref "U$17") (pin "P$2") (pinfunction "IO_P$2") (pintype "bidirectional"))
    )
    (net (code "3") (name "Net-(U$11-A30)") (class "Default")
      (node (ref "U$11") (pin "P$30") (pinfunction "A30_P$30") (pintype "bidirectional"))
      (node (ref "U$22") (pin "P$2") (pinfunction "IO_P$2") (pintype "bidirectional"))
    )
    (net (code "4") (name "Net-(U$13-A30)") (class "Default")
      (node (ref "U$13") (pin "P$30") (pinfunction "A30_P$30") (pintype "bidirectional"))
      (node (ref "U$23") (pin "P$2") (pinfunction "IO_P$2") (pintype "bidirectional"))
    )
    (net (code "5") (name "Net-(U$15-A30)") (class "Default")
      (node (ref "U$15") (pin "P$30") (pinfunction "A30_P$30") (pintype "bidirectional"))
      (node (ref "U$24") (pin "P$2") (pinfunction "IO_P$2") (pintype "bidirectional"))
    )
    (net (code "6") (name "Net-(U$18-IO)") (class "Default")
      (node (ref "U$18") (pin "P$2") (pinfunction "IO_P$2") (pintype "bidirectional"))
      (node (ref "U$3") (pin "P$30") (pinfunction "A30_P$30") (pintype "bidirectional"))
    )
    (net (code "7") (name "Net-(U$19-IO)") (class "Default")
      (node (ref "U$19") (pin "P$2") (pinfunction "IO_P$2") (pintype "bidirectional"))
      (node (ref "U$5") (pin "P$30") (pinfunction "A30_P$30") (pintype "bidirectional"))
    )
    (net (code "8") (name "Net-(U$20-IO)") (class "Default")
      (node (ref "U$20") (pin "P$2") (pinfunction "IO_P$2") (pintype "bidirectional"))
      (node (ref "U$7") (pin "P$30") (pinfunction "A30_P$30") (pintype "bidirectional"))
    )
    (net (code "9") (name "Net-(U$21-IO)") (class "Default")
      (node (ref "U$21") (pin "P$2") (pinfunction "IO_P$2") (pintype "bidirectional"))
      (node (ref "U$9") (pin "P$30") (pinfunction "A30_P$30") (pintype "bidirectional"))
    )
    (net (code "10") (name "ZZ.00.000") (class "Default")
      (node (ref "U$2") (pin "P$34") (pinfunction "B4_P$34") (pintype "bidirectional"))
    )
    (net (code "11") (name "ZZ.00.001") (class "Default")
      (node (ref "U$2") (pin "P$63") (pinfunction "C3_P$63") (pintype "bidirectional"))
    )
    (net (code "12") (name "ZZ.00.002") (class "Default")
      (node (ref "U$2") (pin "P$98") (pinfunction "D8_P$98") (pintype "bidirectional"))
    )
    (net (code "13") (name "ZZ.00.003") (class "Default")
      (node (ref "U$2") (pin "P$127") (pinfunction "E7_P$127") (pintype "bidirectional"))
    )
    (net (code "14") (name "ZZ.00.004") (class "Default")
      (node (ref "U$2") (pin "P$156") (pinfunction "F6_P$156") (pintype "bidirectional"))
    )
    (net (code "15") (name "ZZ.00.005") (class "Default")
      (node (ref "U$2") (pin "P$35") (pinfunction "B5_P$35") (pintype "bidirectional"))
    )
    (net (code "16") (name "ZZ.00.006") (class "Default")
      (node (ref "U$2") (pin "P$64") (pinfunction "C4_P$64") (pintype "bidirectional"))
    )
    (net (code "17") (name "ZZ.00.007") (class "Default")
      (node (ref "U$2") (pin "P$93") (pinfunction "D3_P$93") (pintype "bidirectional"))
    )
    (net (code "18") (name "ZZ.00.008") (class "Default")
      (node (ref "U$2") (pin "P$128") (pinfunction "E8_P$128") (pintype "bidirectional"))
    )
    (net (code "19") (name "ZZ.00.009") (class "Default")
      (node (ref "U$2") (pin "P$157") (pinfunction "F7_P$157") (pintype "bidirectional"))
    )
    (net (code "20") (name "ZZ.00.010") (class "Default")
      (node (ref "U$2") (pin "P$36") (pinfunction "B6_P$36") (pintype "bidirectional"))
    )
    (net (code "21") (name "ZZ.00.011") (class "Default")
      (node (ref "U$2") (pin "P$65") (pinfunction "C5_P$65") (pintype "bidirectional"))
    )
    (net (code "22") (name "ZZ.00.012") (class "Default")
      (node (ref "U$2") (pin "P$94") (pinfunction "D4_P$94") (pintype "bidirectional"))
    )
    (net (code "23") (name "ZZ.00.013") (class "Default")
      (node (ref "U$2") (pin "P$123") (pinfunction "E3_P$123") (pintype "bidirectional"))
    )
    (net (code "24") (name "ZZ.00.014") (class "Default")
      (node (ref "U$2") (pin "P$158") (pinfunction "F8_P$158") (pintype "bidirectional"))
    )
    (net (code "25") (name "ZZ.00.015") (class "Default")
      (node (ref "U$2") (pin "P$152") (pinfunction "F2_P$152") (pintype "bidirectional"))
    )
    (net (code "26") (name "ZZ.00.016") (class "Default")
      (node (ref "U$4") (pin "P$34") (pinfunction "B4_P$34") (pintype "bidirectional"))
    )
    (net (code "27") (name "ZZ.00.017") (class "Default")
      (node (ref "U$4") (pin "P$63") (pinfunction "C3_P$63") (pintype "bidirectional"))
    )
    (net (code "28") (name "ZZ.00.018") (class "Default")
      (node (ref "U$4") (pin "P$98") (pinfunction "D8_P$98") (pintype "bidirectional"))
    )
    (net (code "29") (name "ZZ.00.019") (class "Default")
      (node (ref "U$4") (pin "P$127") (pinfunction "E7_P$127") (pintype "bidirectional"))
    )
    (net (code "30") (name "ZZ.00.020") (class "Default")
      (node (ref "U$4") (pin "P$156") (pinfunction "F6_P$156") (pintype "bidirectional"))
    )
    (net (code "31") (name "ZZ.00.021") (class "Default")
      (node (ref "U$4") (pin "P$35") (pinfunction "B5_P$35") (pintype "bidirectional"))
    )
    (net (code "32") (name "ZZ.00.022") (class "Default")
      (node (ref "U$4") (pin "P$64") (pinfunction "C4_P$64") (pintype "bidirectional"))
    )
    (net (code "33") (name "ZZ.00.023") (class "Default")
      (node (ref "U$4") (pin "P$93") (pinfunction "D3_P$93") (pintype "bidirectional"))
    )
    (net (code "34") (name "ZZ.00.024") (class "Default")
      (node (ref "U$4") (pin "P$128") (pinfunction "E8_P$128") (pintype "bidirectional"))
    )
    (net (code "35") (name "ZZ.00.025") (class "Default")
      (node (ref "U$4") (pin "P$36") (pinfunction "B6_P$36") (pintype "bidirectional"))
    )
    (net (code "36") (name "ZZ.00.026") (class "Default")
      (node (ref "U$4") (pin "P$65") (pinfunction "C5_P$65") (pintype "bidirectional"))
    )
    (net (code "37") (name "ZZ.00.027") (class "Default")
      (node (ref "U$4") (pin "P$94") (pinfunction "D4_P$94") (pintype "bidirectional"))
    )
    (net (code "38") (name "ZZ.00.028") (class "Default")
      (node (ref "U$4") (pin "P$123") (pinfunction "E3_P$123") (pintype "bidirectional"))
    )
    (net (code "39") (name "ZZ.00.029") (class "Default")
      (node (ref "U$4") (pin "P$158") (pinfunction "F8_P$158") (pintype "bidirectional"))
    )
    (net (code "40") (name "ZZ.00.030") (class "Default")
      (node (ref "U$4") (pin "P$152") (pinfunction "F2_P$152") (pintype "bidirectional"))
    )
    (net (code "41") (name "ZZ.00.031") (class "Default")
      (node (ref "U$4") (pin "P$157") (pinfunction "F7_P$157") (pintype "bidirectional"))
    )
    (net (code "42") (name "ZZ.00.032") (class "Default")
      (node (ref "U$6") (pin "P$34") (pinfunction "B4_P$34") (pintype "bidirectional"))
    )
    (net (code "43") (name "ZZ.00.033") (class "Default")
      (node (ref "U$6") (pin "P$63") (pinfunction "C3_P$63") (pintype "bidirectional"))
    )
    (net (code "44") (name "ZZ.00.034") (class "Default")
      (node (ref "U$6") (pin "P$98") (pinfunction "D8_P$98") (pintype "bidirectional"))
    )
    (net (code "45") (name "ZZ.00.035") (class "Default")
      (node (ref "U$6") (pin "P$127") (pinfunction "E7_P$127") (pintype "bidirectional"))
    )
    (net (code "46") (name "ZZ.00.036") (class "Default")
      (node (ref "U$6") (pin "P$35") (pinfunction "B5_P$35") (pintype "bidirectional"))
    )
    (net (code "47") (name "ZZ.00.037") (class "Default")
      (node (ref "U$6") (pin "P$64") (pinfunction "C4_P$64") (pintype "bidirectional"))
    )
    (net (code "48") (name "ZZ.00.038") (class "Default")
      (node (ref "U$6") (pin "P$36") (pinfunction "B6_P$36") (pintype "bidirectional"))
    )
    (net (code "49") (name "ZZ.00.039") (class "Default")
      (node (ref "U$6") (pin "P$65") (pinfunction "C5_P$65") (pintype "bidirectional"))
    )
    (net (code "50") (name "ZZ.00.040") (class "Default")
      (node (ref "U$6") (pin "P$94") (pinfunction "D4_P$94") (pintype "bidirectional"))
    )
    (net (code "51") (name "ZZ.00.041") (class "Default")
      (node (ref "U$6") (pin "P$123") (pinfunction "E3_P$123") (pintype "bidirectional"))
    )
    (net (code "52") (name "ZZ.00.042") (class "Default")
      (node (ref "U$6") (pin "P$158") (pinfunction "F8_P$158") (pintype "bidirectional"))
    )
    (net (code "53") (name "ZZ.00.043") (class "Default")
      (node (ref "U$6") (pin "P$152") (pinfunction "F2_P$152") (pintype "bidirectional"))
    )
    (net (code "54") (name "ZZ.00.044") (class "Default")
      (node (ref "U$6") (pin "P$93") (pinfunction "D3_P$93") (pintype "bidirectional"))
    )
    (net (code "55") (name "ZZ.00.045") (class "Default")
      (node (ref "U$6") (pin "P$128") (pinfunction "E8_P$128") (pintype "bidirectional"))
    )
    (net (code "56") (name "ZZ.00.046") (class "Default")
      (node (ref "U$6") (pin "P$157") (pinfunction "F7_P$157") (pintype "bidirectional"))
    )
    (net (code "57") (name "ZZ.00.047") (class "Default")
      (node (ref "U$6") (pin "P$156") (pinfunction "F6_P$156") (pintype "bidirectional"))
    )
    (net (code "58") (name "ZZ.00.048") (class "Default")
      (node (ref "U$8") (pin "P$34") (pinfunction "B4_P$34") (pintype "bidirectional"))
    )
    (net (code "59") (name "ZZ.00.049") (class "Default")
      (node (ref "U$8") (pin "P$35") (pinfunction "B5_P$35") (pintype "bidirectional"))
    )
    (net (code "60") (name "ZZ.00.050") (class "Default")
      (node (ref "U$8") (pin "P$64") (pinfunction "C4_P$64") (pintype "bidirectional"))
    )
    (net (code "61") (name "ZZ.00.051") (class "Default")
      (node (ref "U$8") (pin "P$36") (pinfunction "B6_P$36") (pintype "bidirectional"))
    )
    (net (code "62") (name "ZZ.00.052") (class "Default")
      (node (ref "U$8") (pin "P$65") (pinfunction "C5_P$65") (pintype "bidirectional"))
    )
    (net (code "63") (name "ZZ.00.053") (class "Default")
      (node (ref "U$8") (pin "P$94") (pinfunction "D4_P$94") (pintype "bidirectional"))
    )
    (net (code "64") (name "ZZ.00.054") (class "Default")
      (node (ref "U$8") (pin "P$123") (pinfunction "E3_P$123") (pintype "bidirectional"))
    )
    (net (code "65") (name "ZZ.00.055") (class "Default")
      (node (ref "U$8") (pin "P$158") (pinfunction "F8_P$158") (pintype "bidirectional"))
    )
    (net (code "66") (name "ZZ.00.056") (class "Default")
      (node (ref "U$8") (pin "P$152") (pinfunction "F2_P$152") (pintype "bidirectional"))
    )
    (net (code "67") (name "ZZ.00.057") (class "Default")
      (node (ref "U$8") (pin "P$93") (pinfunction "D3_P$93") (pintype "bidirectional"))
    )
    (net (code "68") (name "ZZ.00.058") (class "Default")
      (node (ref "U$8") (pin "P$128") (pinfunction "E8_P$128") (pintype "bidirectional"))
    )
    (net (code "69") (name "ZZ.00.059") (class "Default")
      (node (ref "U$8") (pin "P$157") (pinfunction "F7_P$157") (pintype "bidirectional"))
    )
    (net (code "70") (name "ZZ.00.060") (class "Default")
      (node (ref "U$8") (pin "P$63") (pinfunction "C3_P$63") (pintype "bidirectional"))
    )
    (net (code "71") (name "ZZ.00.061") (class "Default")
      (node (ref "U$8") (pin "P$98") (pinfunction "D8_P$98") (pintype "bidirectional"))
    )
    (net (code "72") (name "ZZ.00.062") (class "Default")
      (node (ref "U$8") (pin "P$127") (pinfunction "E7_P$127") (pintype "bidirectional"))
    )
    (net (code "73") (name "ZZ.00.063") (class "Default")
      (node (ref "U$8") (pin "P$156") (pinfunction "F6_P$156") (pintype "bidirectional"))
    )
    (net (code "74") (name "ZZ.00.064") (class "Default")
      (node (ref "U$10") (pin "P$36") (pinfunction "B6_P$36") (pintype "bidirectional"))
    )
    (net (code "75") (name "ZZ.00.065") (class "Default")
      (node (ref "U$10") (pin "P$65") (pinfunction "C5_P$65") (pintype "bidirectional"))
    )
    (net (code "76") (name "ZZ.00.066") (class "Default")
      (node (ref "U$10") (pin "P$94") (pinfunction "D4_P$94") (pintype "bidirectional"))
    )
    (net (code "77") (name "ZZ.00.067") (class "Default")
      (node (ref "U$10") (pin "P$123") (pinfunction "E3_P$123") (pintype "bidirectional"))
    )
    (net (code "78") (name "ZZ.00.068") (class "Default")
      (node (ref "U$10") (pin "P$158") (pinfunction "F8_P$158") (pintype "bidirectional"))
    )
    (net (code "79") (name "ZZ.00.069") (class "Default")
      (node (ref "U$10") (pin "P$152") (pinfunction "F2_P$152") (pintype "bidirectional"))
    )
    (net (code "80") (name "ZZ.00.070") (class "Default")
      (node (ref "U$10") (pin "P$35") (pinfunction "B5_P$35") (pintype "bidirectional"))
    )
    (net (code "81") (name "ZZ.00.071") (class "Default")
      (node (ref "U$10") (pin "P$64") (pinfunction "C4_P$64") (pintype "bidirectional"))
    )
    (net (code "82") (name "ZZ.00.072") (class "Default")
      (node (ref "U$10") (pin "P$93") (pinfunction "D3_P$93") (pintype "bidirectional"))
    )
    (net (code "83") (name "ZZ.00.073") (class "Default")
      (node (ref "U$10") (pin "P$128") (pinfunction "E8_P$128") (pintype "bidirectional"))
    )
    (net (code "84") (name "ZZ.00.074") (class "Default")
      (node (ref "U$10") (pin "P$157") (pinfunction "F7_P$157") (pintype "bidirectional"))
    )
    (net (code "85") (name "ZZ.00.075") (class "Default")
      (node (ref "U$10") (pin "P$34") (pinfunction "B4_P$34") (pintype "bidirectional"))
    )
    (net (code "86") (name "ZZ.00.076") (class "Default")
      (node (ref "U$10") (pin "P$63") (pinfunction "C3_P$63") (pintype "bidirectional"))
    )
    (net (code "87") (name "ZZ.00.077") (class "Default")
      (node (ref "U$10") (pin "P$98") (pinfunction "D8_P$98") (pintype "bidirectional"))
    )
    (net (code "88") (name "ZZ.00.078") (class "Default")
      (node (ref "U$10") (pin "P$127") (pinfunction "E7_P$127") (pintype "bidirectional"))
    )
    (net (code "89") (name "ZZ.00.079") (class "Default")
      (node (ref "U$10") (pin "P$156") (pinfunction "F6_P$156") (pintype "bidirectional"))
    )
    (net (code "90") (name "ZZ.00.080") (class "Default")
      (node (ref "U$12") (pin "P$36") (pinfunction "B6_P$36") (pintype "bidirectional"))
    )
    (net (code "91") (name "ZZ.00.081") (class "Default")
      (node (ref "U$12") (pin "P$65") (pinfunction "C5_P$65") (pintype "bidirectional"))
    )
    (net (code "92") (name "ZZ.00.082") (class "Default")
      (node (ref "U$12") (pin "P$94") (pinfunction "D4_P$94") (pintype "bidirectional"))
    )
    (net (code "93") (name "ZZ.00.083") (class "Default")
      (node (ref "U$12") (pin "P$123") (pinfunction "E3_P$123") (pintype "bidirectional"))
    )
    (net (code "94") (name "ZZ.00.084") (class "Default")
      (node (ref "U$12") (pin "P$158") (pinfunction "F8_P$158") (pintype "bidirectional"))
    )
    (net (code "95") (name "ZZ.00.085") (class "Default")
      (node (ref "U$12") (pin "P$152") (pinfunction "F2_P$152") (pintype "bidirectional"))
    )
    (net (code "96") (name "ZZ.00.086") (class "Default")
      (node (ref "U$12") (pin "P$35") (pinfunction "B5_P$35") (pintype "bidirectional"))
    )
    (net (code "97") (name "ZZ.00.087") (class "Default")
      (node (ref "U$12") (pin "P$64") (pinfunction "C4_P$64") (pintype "bidirectional"))
    )
    (net (code "98") (name "ZZ.00.088") (class "Default")
      (node (ref "U$12") (pin "P$93") (pinfunction "D3_P$93") (pintype "bidirectional"))
    )
    (net (code "99") (name "ZZ.00.089") (class "Default")
      (node (ref "U$12") (pin "P$128") (pinfunction "E8_P$128") (pintype "bidirectional"))
    )
    (net (code "100") (name "ZZ.00.090") (class "Default")
      (node (ref "U$12") (pin "P$157") (pinfunction "F7_P$157") (pintype "bidirectional"))
    )
    (net (code "101") (name "ZZ.00.091") (class "Default")
      (node (ref "U$12") (pin "P$34") (pinfunction "B4_P$34") (pintype "bidirectional"))
    )
    (net (code "102") (name "ZZ.00.092") (class "Default")
      (node (ref "U$12") (pin "P$63") (pinfunction "C3_P$63") (pintype "bidirectional"))
    )
    (net (code "103") (name "ZZ.00.093") (class "Default")
      (node (ref "U$12") (pin "P$98") (pinfunction "D8_P$98") (pintype "bidirectional"))
    )
    (net (code "104") (name "ZZ.00.094") (class "Default")
      (node (ref "U$12") (pin "P$127") (pinfunction "E7_P$127") (pintype "bidirectional"))
    )
    (net (code "105") (name "ZZ.00.095") (class "Default")
      (node (ref "U$12") (pin "P$156") (pinfunction "F6_P$156") (pintype "bidirectional"))
    )
    (net (code "106") (name "ZZ.00.096") (class "Default")
      (node (ref "U$14") (pin "P$36") (pinfunction "B6_P$36") (pintype "bidirectional"))
    )
    (net (code "107") (name "ZZ.00.097") (class "Default")
      (node (ref "U$14") (pin "P$65") (pinfunction "C5_P$65") (pintype "bidirectional"))
    )
    (net (code "108") (name "ZZ.00.098") (class "Default")
      (node (ref "U$14") (pin "P$94") (pinfunction "D4_P$94") (pintype "bidirectional"))
    )
    (net (code "109") (name "ZZ.00.099") (class "Default")
      (node (ref "U$14") (pin "P$123") (pinfunction "E3_P$123") (pintype "bidirectional"))
    )
    (net (code "110") (name "ZZ.00.100") (class "Default")
      (node (ref "U$14") (pin "P$158") (pinfunction "F8_P$158") (pintype "bidirectional"))
    )
    (net (code "111") (name "ZZ.00.101") (class "Default")
      (node (ref "U$14") (pin "P$152") (pinfunction "F2_P$152") (pintype "bidirectional"))
    )
    (net (code "112") (name "ZZ.00.102") (class "Default")
      (node (ref "U$14") (pin "P$35") (pinfunction "B5_P$35") (pintype "bidirectional"))
    )
    (net (code "113") (name "ZZ.00.103") (class "Default")
      (node (ref "U$14") (pin "P$64") (pinfunction "C4_P$64") (pintype "bidirectional"))
    )
    (net (code "114") (name "ZZ.00.104") (class "Default")
      (node (ref "U$14") (pin "P$93") (pinfunction "D3_P$93") (pintype "bidirectional"))
    )
    (net (code "115") (name "ZZ.00.105") (class "Default")
      (node (ref "U$14") (pin "P$128") (pinfunction "E8_P$128") (pintype "bidirectional"))
    )
    (net (code "116") (name "ZZ.00.106") (class "Default")
      (node (ref "U$14") (pin "P$157") (pinfunction "F7_P$157") (pintype "bidirectional"))
    )
    (net (code "117") (name "ZZ.00.107") (class "Default")
      (node (ref "U$14") (pin "P$34") (pinfunction "B4_P$34") (pintype "bidirectional"))
    )
    (net (code "118") (name "ZZ.00.108") (class "Default")
      (node (ref "U$14") (pin "P$63") (pinfunction "C3_P$63") (pintype "bidirectional"))
    )
    (net (code "119") (name "ZZ.00.109") (class "Default")
      (node (ref "U$14") (pin "P$98") (pinfunction "D8_P$98") (pintype "bidirectional"))
    )
    (net (code "120") (name "ZZ.00.110") (class "Default")
      (node (ref "U$14") (pin "P$127") (pinfunction "E7_P$127") (pintype "bidirectional"))
    )
    (net (code "121") (name "ZZ.00.111") (class "Default")
      (node (ref "U$14") (pin "P$156") (pinfunction "F6_P$156") (pintype "bidirectional"))
    )
    (net (code "122") (name "ZZ.00.112") (class "Default")
      (node (ref "U$16") (pin "P$36") (pinfunction "B6_P$36") (pintype "bidirectional"))
    )
    (net (code "123") (name "ZZ.00.113") (class "Default")
      (node (ref "U$16") (pin "P$65") (pinfunction "C5_P$65") (pintype "bidirectional"))
    )
    (net (code "124") (name "ZZ.00.114") (class "Default")
      (node (ref "U$16") (pin "P$94") (pinfunction "D4_P$94") (pintype "bidirectional"))
    )
    (net (code "125") (name "ZZ.00.115") (class "Default")
      (node (ref "U$16") (pin "P$123") (pinfunction "E3_P$123") (pintype "bidirectional"))
    )
    (net (code "126") (name "ZZ.00.116") (class "Default")
      (node (ref "U$16") (pin "P$158") (pinfunction "F8_P$158") (pintype "bidirectional"))
    )
    (net (code "127") (name "ZZ.00.117") (class "Default")
      (node (ref "U$16") (pin "P$152") (pinfunction "F2_P$152") (pintype "bidirectional"))
    )
    (net (code "128") (name "ZZ.00.118") (class "Default")
      (node (ref "U$16") (pin "P$35") (pinfunction "B5_P$35") (pintype "bidirectional"))
    )
    (net (code "129") (name "ZZ.00.119") (class "Default")
      (node (ref "U$16") (pin "P$64") (pinfunction "C4_P$64") (pintype "bidirectional"))
    )
    (net (code "130") (name "ZZ.00.120") (class "Default")
      (node (ref "U$16") (pin "P$93") (pinfunction "D3_P$93") (pintype "bidirectional"))
    )
    (net (code "131") (name "ZZ.00.121") (class "Default")
      (node (ref "U$16") (pin "P$128") (pinfunction "E8_P$128") (pintype "bidirectional"))
    )
    (net (code "132") (name "ZZ.00.122") (class "Default")
      (node (ref "U$16") (pin "P$157") (pinfunction "F7_P$157") (pintype "bidirectional"))
    )
    (net (code "133") (name "ZZ.00.123") (class "Default")
      (node (ref "U$16") (pin "P$34") (pinfunction "B4_P$34") (pintype "bidirectional"))
    )
    (net (code "134") (name "ZZ.00.124") (class "Default")
      (node (ref "U$16") (pin "P$63") (pinfunction "C3_P$63") (pintype "bidirectional"))
    )
    (net (code "135") (name "ZZ.00.125") (class "Default")
      (node (ref "U$16") (pin "P$98") (pinfunction "D8_P$98") (pintype "bidirectional"))
    )
    (net (code "136") (name "ZZ.00.126") (class "Default")
      (node (ref "U$16") (pin "P$127") (pinfunction "E7_P$127") (pintype "bidirectional"))
    )
    (net (code "137") (name "ZZ.00.127") (class "Default")
      (node (ref "U$16") (pin "P$156") (pinfunction "F6_P$156") (pintype "bidirectional"))
    )
    (net (code "138") (name "ZZ.01.000") (class "Default")
      (node (ref "U$2") (pin "P$33") (pinfunction "B3_P$33") (pintype "bidirectional"))
    )
    (net (code "139") (name "ZZ.01.001") (class "Default")
      (node (ref "U$2") (pin "P$68") (pinfunction "C8_P$68") (pintype "bidirectional"))
    )
    (net (code "140") (name "ZZ.01.002") (class "Default")
      (node (ref "U$2") (pin "P$97") (pinfunction "D7_P$97") (pintype "bidirectional"))
    )
    (net (code "141") (name "ZZ.01.003") (class "Default")
      (node (ref "U$2") (pin "P$126") (pinfunction "E6_P$126") (pintype "bidirectional"))
    )
    (net (code "142") (name "ZZ.01.004") (class "Default")
      (node (ref "U$2") (pin "P$155") (pinfunction "F5_P$155") (pintype "bidirectional"))
    )
    (net (code "143") (name "ZZ.01.005") (class "Default")
      (node (ref "U$2") (pin "P$38") (pinfunction "B8_P$38") (pintype "bidirectional"))
    )
    (net (code "144") (name "ZZ.01.006") (class "Default")
      (node (ref "U$2") (pin "P$67") (pinfunction "C7_P$67") (pintype "bidirectional"))
    )
    (net (code "145") (name "ZZ.01.007") (class "Default")
      (node (ref "U$2") (pin "P$96") (pinfunction "D6_P$96") (pintype "bidirectional"))
    )
    (net (code "146") (name "ZZ.01.008") (class "Default")
      (node (ref "U$2") (pin "P$125") (pinfunction "E5_P$125") (pintype "bidirectional"))
    )
    (net (code "147") (name "ZZ.01.009") (class "Default")
      (node (ref "U$2") (pin "P$154") (pinfunction "F4_P$154") (pintype "bidirectional"))
    )
    (net (code "148") (name "ZZ.01.010") (class "Default")
      (node (ref "U$2") (pin "P$37") (pinfunction "B7_P$37") (pintype "bidirectional"))
    )
    (net (code "149") (name "ZZ.01.011") (class "Default")
      (node (ref "U$2") (pin "P$66") (pinfunction "C6_P$66") (pintype "bidirectional"))
    )
    (net (code "150") (name "ZZ.01.012") (class "Default")
      (node (ref "U$2") (pin "P$95") (pinfunction "D5_P$95") (pintype "bidirectional"))
    )
    (net (code "151") (name "ZZ.01.013") (class "Default")
      (node (ref "U$2") (pin "P$124") (pinfunction "E4_P$124") (pintype "bidirectional"))
    )
    (net (code "152") (name "ZZ.01.014") (class "Default")
      (node (ref "U$2") (pin "P$153") (pinfunction "F3_P$153") (pintype "bidirectional"))
    )
    (net (code "153") (name "ZZ.01.015") (class "Default")
      (node (ref "U$2") (pin "P$122") (pinfunction "E2_P$122") (pintype "bidirectional"))
    )
    (net (code "154") (name "ZZ.01.016") (class "Default")
      (node (ref "U$4") (pin "P$33") (pinfunction "B3_P$33") (pintype "bidirectional"))
    )
    (net (code "155") (name "ZZ.01.017") (class "Default")
      (node (ref "U$4") (pin "P$68") (pinfunction "C8_P$68") (pintype "bidirectional"))
    )
    (net (code "156") (name "ZZ.01.018") (class "Default")
      (node (ref "U$4") (pin "P$97") (pinfunction "D7_P$97") (pintype "bidirectional"))
    )
    (net (code "157") (name "ZZ.01.019") (class "Default")
      (node (ref "U$4") (pin "P$126") (pinfunction "E6_P$126") (pintype "bidirectional"))
    )
    (net (code "158") (name "ZZ.01.020") (class "Default")
      (node (ref "U$4") (pin "P$155") (pinfunction "F5_P$155") (pintype "bidirectional"))
    )
    (net (code "159") (name "ZZ.01.021") (class "Default")
      (node (ref "U$4") (pin "P$38") (pinfunction "B8_P$38") (pintype "bidirectional"))
    )
    (net (code "160") (name "ZZ.01.022") (class "Default")
      (node (ref "U$4") (pin "P$67") (pinfunction "C7_P$67") (pintype "bidirectional"))
    )
    (net (code "161") (name "ZZ.01.023") (class "Default")
      (node (ref "U$4") (pin "P$96") (pinfunction "D6_P$96") (pintype "bidirectional"))
    )
    (net (code "162") (name "ZZ.01.024") (class "Default")
      (node (ref "U$4") (pin "P$125") (pinfunction "E5_P$125") (pintype "bidirectional"))
    )
    (net (code "163") (name "ZZ.01.025") (class "Default")
      (node (ref "U$4") (pin "P$37") (pinfunction "B7_P$37") (pintype "bidirectional"))
    )
    (net (code "164") (name "ZZ.01.026") (class "Default")
      (node (ref "U$4") (pin "P$66") (pinfunction "C6_P$66") (pintype "bidirectional"))
    )
    (net (code "165") (name "ZZ.01.027") (class "Default")
      (node (ref "U$4") (pin "P$95") (pinfunction "D5_P$95") (pintype "bidirectional"))
    )
    (net (code "166") (name "ZZ.01.028") (class "Default")
      (node (ref "U$4") (pin "P$124") (pinfunction "E4_P$124") (pintype "bidirectional"))
    )
    (net (code "167") (name "ZZ.01.029") (class "Default")
      (node (ref "U$4") (pin "P$153") (pinfunction "F3_P$153") (pintype "bidirectional"))
    )
    (net (code "168") (name "ZZ.01.030") (class "Default")
      (node (ref "U$4") (pin "P$122") (pinfunction "E2_P$122") (pintype "bidirectional"))
    )
    (net (code "169") (name "ZZ.01.031") (class "Default")
      (node (ref "U$4") (pin "P$154") (pinfunction "F4_P$154") (pintype "bidirectional"))
    )
    (net (code "170") (name "ZZ.01.032") (class "Default")
      (node (ref "U$6") (pin "P$33") (pinfunction "B3_P$33") (pintype "bidirectional"))
    )
    (net (code "171") (name "ZZ.01.033") (class "Default")
      (node (ref "U$6") (pin "P$68") (pinfunction "C8_P$68") (pintype "bidirectional"))
    )
    (net (code "172") (name "ZZ.01.034") (class "Default")
      (node (ref "U$6") (pin "P$97") (pinfunction "D7_P$97") (pintype "bidirectional"))
    )
    (net (code "173") (name "ZZ.01.035") (class "Default")
      (node (ref "U$6") (pin "P$126") (pinfunction "E6_P$126") (pintype "bidirectional"))
    )
    (net (code "174") (name "ZZ.01.036") (class "Default")
      (node (ref "U$6") (pin "P$38") (pinfunction "B8_P$38") (pintype "bidirectional"))
    )
    (net (code "175") (name "ZZ.01.037") (class "Default")
      (node (ref "U$6") (pin "P$67") (pinfunction "C7_P$67") (pintype "bidirectional"))
    )
    (net (code "176") (name "ZZ.01.038") (class "Default")
      (node (ref "U$6") (pin "P$37") (pinfunction "B7_P$37") (pintype "bidirectional"))
    )
    (net (code "177") (name "ZZ.01.039") (class "Default")
      (node (ref "U$6") (pin "P$66") (pinfunction "C6_P$66") (pintype "bidirectional"))
    )
    (net (code "178") (name "ZZ.01.040") (class "Default")
      (node (ref "U$6") (pin "P$95") (pinfunction "D5_P$95") (pintype "bidirectional"))
    )
    (net (code "179") (name "ZZ.01.041") (class "Default")
      (node (ref "U$6") (pin "P$124") (pinfunction "E4_P$124") (pintype "bidirectional"))
    )
    (net (code "180") (name "ZZ.01.042") (class "Default")
      (node (ref "U$6") (pin "P$153") (pinfunction "F3_P$153") (pintype "bidirectional"))
    )
    (net (code "181") (name "ZZ.01.043") (class "Default")
      (node (ref "U$6") (pin "P$122") (pinfunction "E2_P$122") (pintype "bidirectional"))
    )
    (net (code "182") (name "ZZ.01.044") (class "Default")
      (node (ref "U$6") (pin "P$96") (pinfunction "D6_P$96") (pintype "bidirectional"))
    )
    (net (code "183") (name "ZZ.01.045") (class "Default")
      (node (ref "U$6") (pin "P$125") (pinfunction "E5_P$125") (pintype "bidirectional"))
    )
    (net (code "184") (name "ZZ.01.046") (class "Default")
      (node (ref "U$6") (pin "P$154") (pinfunction "F4_P$154") (pintype "bidirectional"))
    )
    (net (code "185") (name "ZZ.01.047") (class "Default")
      (node (ref "U$6") (pin "P$155") (pinfunction "F5_P$155") (pintype "bidirectional"))
    )
    (net (code "186") (name "ZZ.01.048") (class "Default")
      (node (ref "U$8") (pin "P$33") (pinfunction "B3_P$33") (pintype "bidirectional"))
    )
    (net (code "187") (name "ZZ.01.049") (class "Default")
      (node (ref "U$8") (pin "P$38") (pinfunction "B8_P$38") (pintype "bidirectional"))
    )
    (net (code "188") (name "ZZ.01.050") (class "Default")
      (node (ref "U$8") (pin "P$67") (pinfunction "C7_P$67") (pintype "bidirectional"))
    )
    (net (code "189") (name "ZZ.01.051") (class "Default")
      (node (ref "U$8") (pin "P$37") (pinfunction "B7_P$37") (pintype "bidirectional"))
    )
    (net (code "190") (name "ZZ.01.052") (class "Default")
      (node (ref "U$8") (pin "P$66") (pinfunction "C6_P$66") (pintype "bidirectional"))
    )
    (net (code "191") (name "ZZ.01.053") (class "Default")
      (node (ref "U$8") (pin "P$95") (pinfunction "D5_P$95") (pintype "bidirectional"))
    )
    (net (code "192") (name "ZZ.01.054") (class "Default")
      (node (ref "U$8") (pin "P$124") (pinfunction "E4_P$124") (pintype "bidirectional"))
    )
    (net (code "193") (name "ZZ.01.055") (class "Default")
      (node (ref "U$8") (pin "P$153") (pinfunction "F3_P$153") (pintype "bidirectional"))
    )
    (net (code "194") (name "ZZ.01.056") (class "Default")
      (node (ref "U$8") (pin "P$122") (pinfunction "E2_P$122") (pintype "bidirectional"))
    )
    (net (code "195") (name "ZZ.01.057") (class "Default")
      (node (ref "U$8") (pin "P$96") (pinfunction "D6_P$96") (pintype "bidirectional"))
    )
    (net (code "196") (name "ZZ.01.058") (class "Default")
      (node (ref "U$8") (pin "P$125") (pinfunction "E5_P$125") (pintype "bidirectional"))
    )
    (net (code "197") (name "ZZ.01.059") (class "Default")
      (node (ref "U$8") (pin "P$154") (pinfunction "F4_P$154") (pintype "bidirectional"))
    )
    (net (code "198") (name "ZZ.01.060") (class "Default")
      (node (ref "U$8") (pin "P$68") (pinfunction "C8_P$68") (pintype "bidirectional"))
    )
    (net (code "199") (name "ZZ.01.061") (class "Default")
      (node (ref "U$8") (pin "P$97") (pinfunction "D7_P$97") (pintype "bidirectional"))
    )
    (net (code "200") (name "ZZ.01.062") (class "Default")
      (node (ref "U$8") (pin "P$126") (pinfunction "E6_P$126") (pintype "bidirectional"))
    )
    (net (code "201") (name "ZZ.01.063") (class "Default")
      (node (ref "U$8") (pin "P$155") (pinfunction "F5_P$155") (pintype "bidirectional"))
    )
    (net (code "202") (name "ZZ.01.064") (class "Default")
      (node (ref "U$10") (pin "P$37") (pinfunction "B7_P$37") (pintype "bidirectional"))
    )
    (net (code "203") (name "ZZ.01.065") (class "Default")
      (node (ref "U$10") (pin "P$66") (pinfunction "C6_P$66") (pintype "bidirectional"))
    )
    (net (code "204") (name "ZZ.01.066") (class "Default")
      (node (ref "U$10") (pin "P$95") (pinfunction "D5_P$95") (pintype "bidirectional"))
    )
    (net (code "205") (name "ZZ.01.067") (class "Default")
      (node (ref "U$10") (pin "P$124") (pinfunction "E4_P$124") (pintype "bidirectional"))
    )
    (net (code "206") (name "ZZ.01.068") (class "Default")
      (node (ref "U$10") (pin "P$153") (pinfunction "F3_P$153") (pintype "bidirectional"))
    )
    (net (code "207") (name "ZZ.01.069") (class "Default")
      (node (ref "U$10") (pin "P$122") (pinfunction "E2_P$122") (pintype "bidirectional"))
    )
    (net (code "208") (name "ZZ.01.070") (class "Default")
      (node (ref "U$10") (pin "P$38") (pinfunction "B8_P$38") (pintype "bidirectional"))
    )
    (net (code "209") (name "ZZ.01.071") (class "Default")
      (node (ref "U$10") (pin "P$67") (pinfunction "C7_P$67") (pintype "bidirectional"))
    )
    (net (code "210") (name "ZZ.01.072") (class "Default")
      (node (ref "U$10") (pin "P$96") (pinfunction "D6_P$96") (pintype "bidirectional"))
    )
    (net (code "211") (name "ZZ.01.073") (class "Default")
      (node (ref "U$10") (pin "P$125") (pinfunction "E5_P$125") (pintype "bidirectional"))
    )
    (net (code "212") (name "ZZ.01.074") (class "Default")
      (node (ref "U$10") (pin "P$154") (pinfunction "F4_P$154") (pintype "bidirectional"))
    )
    (net (code "213") (name "ZZ.01.075") (class "Default")
      (node (ref "U$10") (pin "P$33") (pinfunction "B3_P$33") (pintype "bidirectional"))
    )
    (net (code "214") (name "ZZ.01.076") (class "Default")
      (node (ref "U$10") (pin "P$68") (pinfunction "C8_P$68") (pintype "bidirectional"))
    )
    (net (code "215") (name "ZZ.01.077") (class "Default")
      (node (ref "U$10") (pin "P$97") (pinfunction "D7_P$97") (pintype "bidirectional"))
    )
    (net (code "216") (name "ZZ.01.078") (class "Default")
      (node (ref "U$10") (pin "P$126") (pinfunction "E6_P$126") (pintype "bidirectional"))
    )
    (net (code "217") (name "ZZ.01.079") (class "Default")
      (node (ref "U$10") (pin "P$155") (pinfunction "F5_P$155") (pintype "bidirectional"))
    )
    (net (code "218") (name "ZZ.01.080") (class "Default")
      (node (ref "U$12") (pin "P$37") (pinfunction "B7_P$37") (pintype "bidirectional"))
    )
    (net (code "219") (name "ZZ.01.081") (class "Default")
      (node (ref "U$12") (pin "P$66") (pinfunction "C6_P$66") (pintype "bidirectional"))
    )
    (net (code "220") (name "ZZ.01.082") (class "Default")
      (node (ref "U$12") (pin "P$95") (pinfunction "D5_P$95") (pintype "bidirectional"))
    )
    (net (code "221") (name "ZZ.01.083") (class "Default")
      (node (ref "U$12") (pin "P$124") (pinfunction "E4_P$124") (pintype "bidirectional"))
    )
    (net (code "222") (name "ZZ.01.084") (class "Default")
      (node (ref "U$12") (pin "P$153") (pinfunction "F3_P$153") (pintype "bidirectional"))
    )
    (net (code "223") (name "ZZ.01.085") (class "Default")
      (node (ref "U$12") (pin "P$122") (pinfunction "E2_P$122") (pintype "bidirectional"))
    )
    (net (code "224") (name "ZZ.01.086") (class "Default")
      (node (ref "U$12") (pin "P$38") (pinfunction "B8_P$38") (pintype "bidirectional"))
    )
    (net (code "225") (name "ZZ.01.087") (class "Default")
      (node (ref "U$12") (pin "P$67") (pinfunction "C7_P$67") (pintype "bidirectional"))
    )
    (net (code "226") (name "ZZ.01.088") (class "Default")
      (node (ref "U$12") (pin "P$96") (pinfunction "D6_P$96") (pintype "bidirectional"))
    )
    (net (code "227") (name "ZZ.01.089") (class "Default")
      (node (ref "U$12") (pin "P$125") (pinfunction "E5_P$125") (pintype "bidirectional"))
    )
    (net (code "228") (name "ZZ.01.090") (class "Default")
      (node (ref "U$12") (pin "P$154") (pinfunction "F4_P$154") (pintype "bidirectional"))
    )
    (net (code "229") (name "ZZ.01.091") (class "Default")
      (node (ref "U$12") (pin "P$33") (pinfunction "B3_P$33") (pintype "bidirectional"))
    )
    (net (code "230") (name "ZZ.01.092") (class "Default")
      (node (ref "U$12") (pin "P$68") (pinfunction "C8_P$68") (pintype "bidirectional"))
    )
    (net (code "231") (name "ZZ.01.093") (class "Default")
      (node (ref "U$12") (pin "P$97") (pinfunction "D7_P$97") (pintype "bidirectional"))
    )
    (net (code "232") (name "ZZ.01.094") (class "Default")
      (node (ref "U$12") (pin "P$126") (pinfunction "E6_P$126") (pintype "bidirectional"))
    )
    (net (code "233") (name "ZZ.01.095") (class "Default")
      (node (ref "U$12") (pin "P$155") (pinfunction "F5_P$155") (pintype "bidirectional"))
    )
    (net (code "234") (name "ZZ.01.096") (class "Default")
      (node (ref "U$14") (pin "P$37") (pinfunction "B7_P$37") (pintype "bidirectional"))
    )
    (net (code "235") (name "ZZ.01.097") (class "Default")
      (node (ref "U$14") (pin "P$66") (pinfunction "C6_P$66") (pintype "bidirectional"))
    )
    (net (code "236") (name "ZZ.01.098") (class "Default")
      (node (ref "U$14") (pin "P$95") (pinfunction "D5_P$95") (pintype "bidirectional"))
    )
    (net (code "237") (name "ZZ.01.099") (class "Default")
      (node (ref "U$14") (pin "P$124") (pinfunction "E4_P$124") (pintype "bidirectional"))
    )
    (net (code "238") (name "ZZ.01.100") (class "Default")
      (node (ref "U$14") (pin "P$153") (pinfunction "F3_P$153") (pintype "bidirectional"))
    )
    (net (code "239") (name "ZZ.01.101") (class "Default")
      (node (ref "U$14") (pin "P$122") (pinfunction "E2_P$122") (pintype "bidirectional"))
    )
    (net (code "240") (name "ZZ.01.102") (class "Default")
      (node (ref "U$14") (pin "P$38") (pinfunction "B8_P$38") (pintype "bidirectional"))
    )
    (net (code "241") (name "ZZ.01.103") (class "Default")
      (node (ref "U$14") (pin "P$67") (pinfunction "C7_P$67") (pintype "bidirectional"))
    )
    (net (code "242") (name "ZZ.01.104") (class "Default")
      (node (ref "U$14") (pin "P$96") (pinfunction "D6_P$96") (pintype "bidirectional"))
    )
    (net (code "243") (name "ZZ.01.105") (class "Default")
      (node (ref "U$14") (pin "P$125") (pinfunction "E5_P$125") (pintype "bidirectional"))
    )
    (net (code "244") (name "ZZ.01.106") (class "Default")
      (node (ref "U$14") (pin "P$154") (pinfunction "F4_P$154") (pintype "bidirectional"))
    )
    (net (code "245") (name "ZZ.01.107") (class "Default")
      (node (ref "U$14") (pin "P$33") (pinfunction "B3_P$33") (pintype "bidirectional"))
    )
    (net (code "246") (name "ZZ.01.108") (class "Default")
      (node (ref "U$14") (pin "P$68") (pinfunction "C8_P$68") (pintype "bidirectional"))
    )
    (net (code "247") (name "ZZ.01.109") (class "Default")
      (node (ref "U$14") (pin "P$97") (pinfunction "D7_P$97") (pintype "bidirectional"))
    )
    (net (code "248") (name "ZZ.01.110") (class "Default")
      (node (ref "U$14") (pin "P$126") (pinfunction "E6_P$126") (pintype "bidirectional"))
    )
    (net (code "249") (name "ZZ.01.111") (class "Default")
      (node (ref "U$14") (pin "P$155") (pinfunction "F5_P$155") (pintype "bidirectional"))
    )
    (net (code "250") (name "ZZ.01.112") (class "Default")
      (node (ref "U$16") (pin "P$37") (pinfunction "B7_P$37") (pintype "bidirectional"))
    )
    (net (code "251") (name "ZZ.01.113") (class "Default")
      (node (ref "U$16") (pin "P$66") (pinfunction "C6_P$66") (pintype "bidirectional"))
    )
    (net (code "252") (name "ZZ.01.114") (class "Default")
      (node (ref "U$16") (pin "P$95") (pinfunction "D5_P$95") (pintype "bidirectional"))
    )
    (net (code "253") (name "ZZ.01.115") (class "Default")
      (node (ref "U$16") (pin "P$124") (pinfunction "E4_P$124") (pintype "bidirectional"))
    )
    (net (code "254") (name "ZZ.01.116") (class "Default")
      (node (ref "U$16") (pin "P$153") (pinfunction "F3_P$153") (pintype "bidirectional"))
    )
    (net (code "255") (name "ZZ.01.117") (class "Default")
      (node (ref "U$16") (pin "P$122") (pinfunction "E2_P$122") (pintype "bidirectional"))
    )
    (net (code "256") (name "ZZ.01.118") (class "Default")
      (node (ref "U$16") (pin "P$38") (pinfunction "B8_P$38") (pintype "bidirectional"))
    )
    (net (code "257") (name "ZZ.01.119") (class "Default")
      (node (ref "U$16") (pin "P$67") (pinfunction "C7_P$67") (pintype "bidirectional"))
    )
    (net (code "258") (name "ZZ.01.120") (class "Default")
      (node (ref "U$16") (pin "P$96") (pinfunction "D6_P$96") (pintype "bidirectional"))
    )
    (net (code "259") (name "ZZ.01.121") (class "Default")
      (node (ref "U$16") (pin "P$125") (pinfunction "E5_P$125") (pintype "bidirectional"))
    )
    (net (code "260") (name "ZZ.01.122") (class "Default")
      (node (ref "U$16") (pin "P$154") (pinfunction "F4_P$154") (pintype "bidirectional"))
    )
    (net (code "261") (name "ZZ.01.123") (class "Default")
      (node (ref "U$16") (pin "P$33") (pinfunction "B3_P$33") (pintype "bidirectional"))
    )
    (net (code "262") (name "ZZ.01.124") (class "Default")
      (node (ref "U$16") (pin "P$68") (pinfunction "C8_P$68") (pintype "bidirectional"))
    )
    (net (code "263") (name "ZZ.01.125") (class "Default")
      (node (ref "U$16") (pin "P$97") (pinfunction "D7_P$97") (pintype "bidirectional"))
    )
    (net (code "264") (name "ZZ.01.126") (class "Default")
      (node (ref "U$16") (pin "P$126") (pinfunction "E6_P$126") (pintype "bidirectional"))
    )
    (net (code "265") (name "ZZ.01.127") (class "Default")
      (node (ref "U$16") (pin "P$155") (pinfunction "F5_P$155") (pintype "bidirectional"))
    )
    (net (code "266") (name "ZZ.02.000") (class "Default")
      (node (ref "U$2") (pin "P$75") (pinfunction "C15_P$75") (pintype "bidirectional"))
    )
    (net (code "267") (name "ZZ.02.001") (class "Default")
      (node (ref "U$2") (pin "P$135") (pinfunction "E15_P$135") (pintype "bidirectional"))
    )
    (net (code "268") (name "ZZ.02.002") (class "Default")
      (node (ref "U$2") (pin "P$165") (pinfunction "F15_P$165") (pintype "bidirectional"))
    )
    (net (code "269") (name "ZZ.02.003") (class "Default")
      (node (ref "U$2") (pin "P$104") (pinfunction "D14_P$104") (pintype "bidirectional"))
    )
    (net (code "270") (name "ZZ.02.004") (class "Default")
      (node (ref "U$2") (pin "P$134") (pinfunction "E14_P$134") (pintype "bidirectional"))
    )
    (net (code "271") (name "ZZ.02.005") (class "Default")
      (node (ref "U$2") (pin "P$73") (pinfunction "C13_P$73") (pintype "bidirectional"))
    )
    (net (code "272") (name "ZZ.02.006") (class "Default")
      (node (ref "U$2") (pin "P$103") (pinfunction "D13_P$103") (pintype "bidirectional"))
    )
    (net (code "273") (name "ZZ.02.007") (class "Default")
      (node (ref "U$2") (pin "P$163") (pinfunction "F13_P$163") (pintype "bidirectional"))
    )
    (net (code "274") (name "ZZ.02.008") (class "Default")
      (node (ref "U$2") (pin "P$72") (pinfunction "C12_P$72") (pintype "bidirectional"))
    )
    (net (code "275") (name "ZZ.02.009") (class "Default")
      (node (ref "U$2") (pin "P$102") (pinfunction "D12_P$102") (pintype "bidirectional"))
    )
    (net (code "276") (name "ZZ.02.010") (class "Default")
      (node (ref "U$2") (pin "P$162") (pinfunction "F12_P$162") (pintype "bidirectional"))
    )
    (net (code "277") (name "ZZ.02.011") (class "Default")
      (node (ref "U$2") (pin "P$161") (pinfunction "F11_P$161") (pintype "bidirectional"))
    )
    (net (code "278") (name "ZZ.02.012") (class "Default")
      (node (ref "U$2") (pin "P$160") (pinfunction "F10_P$160") (pintype "bidirectional"))
    )
    (net (code "279") (name "ZZ.02.013") (class "Default")
      (node (ref "U$2") (pin "P$41") (pinfunction "B11_P$41") (pintype "bidirectional"))
    )
    (net (code "280") (name "ZZ.02.014") (class "Default")
      (node (ref "U$2") (pin "P$71") (pinfunction "C11_P$71") (pintype "bidirectional"))
    )
    (net (code "281") (name "ZZ.02.015") (class "Default")
      (node (ref "U$2") (pin "P$101") (pinfunction "D11_P$101") (pintype "bidirectional"))
    )
    (net (code "282") (name "ZZ.02.016") (class "Default")
      (node (ref "U$4") (pin "P$75") (pinfunction "C15_P$75") (pintype "bidirectional"))
    )
    (net (code "283") (name "ZZ.02.017") (class "Default")
      (node (ref "U$4") (pin "P$105") (pinfunction "D15_P$105") (pintype "bidirectional"))
    )
    (net (code "284") (name "ZZ.02.018") (class "Default")
      (node (ref "U$4") (pin "P$165") (pinfunction "F15_P$165") (pintype "bidirectional"))
    )
    (net (code "285") (name "ZZ.02.019") (class "Default")
      (node (ref "U$4") (pin "P$74") (pinfunction "C14_P$74") (pintype "bidirectional"))
    )
    (net (code "286") (name "ZZ.02.020") (class "Default")
      (node (ref "U$4") (pin "P$164") (pinfunction "F14_P$164") (pintype "bidirectional"))
    )
    (net (code "287") (name "ZZ.02.021") (class "Default")
      (node (ref "U$4") (pin "P$73") (pinfunction "C13_P$73") (pintype "bidirectional"))
    )
    (net (code "288") (name "ZZ.02.022") (class "Default")
      (node (ref "U$4") (pin "P$133") (pinfunction "E13_P$133") (pintype "bidirectional"))
    )
    (net (code "289") (name "ZZ.02.023") (class "Default")
      (node (ref "U$4") (pin "P$163") (pinfunction "F13_P$163") (pintype "bidirectional"))
    )
    (net (code "290") (name "ZZ.02.024") (class "Default")
      (node (ref "U$4") (pin "P$72") (pinfunction "C12_P$72") (pintype "bidirectional"))
    )
    (net (code "291") (name "ZZ.02.025") (class "Default")
      (node (ref "U$4") (pin "P$132") (pinfunction "E12_P$132") (pintype "bidirectional"))
    )
    (net (code "292") (name "ZZ.02.026") (class "Default")
      (node (ref "U$4") (pin "P$41") (pinfunction "B11_P$41") (pintype "bidirectional"))
    )
    (net (code "293") (name "ZZ.02.027") (class "Default")
      (node (ref "U$4") (pin "P$71") (pinfunction "C11_P$71") (pintype "bidirectional"))
    )
    (net (code "294") (name "ZZ.02.028") (class "Default")
      (node (ref "U$4") (pin "P$101") (pinfunction "D11_P$101") (pintype "bidirectional"))
    )
    (net (code "295") (name "ZZ.02.029") (class "Default")
      (node (ref "U$4") (pin "P$131") (pinfunction "E11_P$131") (pintype "bidirectional"))
    )
    (net (code "296") (name "ZZ.02.030") (class "Default")
      (node (ref "U$4") (pin "P$161") (pinfunction "F11_P$161") (pintype "bidirectional"))
    )
    (net (code "297") (name "ZZ.02.031") (class "Default")
      (node (ref "U$4") (pin "P$162") (pinfunction "F12_P$162") (pintype "bidirectional"))
    )
    (net (code "298") (name "ZZ.02.032") (class "Default")
      (node (ref "U$6") (pin "P$75") (pinfunction "C15_P$75") (pintype "bidirectional"))
    )
    (net (code "299") (name "ZZ.02.033") (class "Default")
      (node (ref "U$6") (pin "P$105") (pinfunction "D15_P$105") (pintype "bidirectional"))
    )
    (net (code "300") (name "ZZ.02.034") (class "Default")
      (node (ref "U$6") (pin "P$165") (pinfunction "F15_P$165") (pintype "bidirectional"))
    )
    (net (code "301") (name "ZZ.02.035") (class "Default")
      (node (ref "U$6") (pin "P$74") (pinfunction "C14_P$74") (pintype "bidirectional"))
    )
    (net (code "302") (name "ZZ.02.036") (class "Default")
      (node (ref "U$6") (pin "P$43") (pinfunction "B13_P$43") (pintype "bidirectional"))
    )
    (net (code "303") (name "ZZ.02.037") (class "Default")
      (node (ref "U$6") (pin "P$103") (pinfunction "D13_P$103") (pintype "bidirectional"))
    )
    (net (code "304") (name "ZZ.02.038") (class "Default")
      (node (ref "U$6") (pin "P$102") (pinfunction "D12_P$102") (pintype "bidirectional"))
    )
    (net (code "305") (name "ZZ.02.039") (class "Default")
      (node (ref "U$6") (pin "P$41") (pinfunction "B11_P$41") (pintype "bidirectional"))
    )
    (net (code "306") (name "ZZ.02.040") (class "Default")
      (node (ref "U$6") (pin "P$71") (pinfunction "C11_P$71") (pintype "bidirectional"))
    )
    (net (code "307") (name "ZZ.02.041") (class "Default")
      (node (ref "U$6") (pin "P$101") (pinfunction "D11_P$101") (pintype "bidirectional"))
    )
    (net (code "308") (name "ZZ.02.042") (class "Default")
      (node (ref "U$6") (pin "P$131") (pinfunction "E11_P$131") (pintype "bidirectional"))
    )
    (net (code "309") (name "ZZ.02.043") (class "Default")
      (node (ref "U$6") (pin "P$161") (pinfunction "F11_P$161") (pintype "bidirectional"))
    )
    (net (code "310") (name "ZZ.02.044") (class "Default")
      (node (ref "U$6") (pin "P$132") (pinfunction "E12_P$132") (pintype "bidirectional"))
    )
    (net (code "311") (name "ZZ.02.045") (class "Default")
      (node (ref "U$6") (pin "P$162") (pinfunction "F12_P$162") (pintype "bidirectional"))
    )
    (net (code "312") (name "ZZ.02.046") (class "Default")
      (node (ref "U$6") (pin "P$159") (pinfunction "F9_P$159") (pintype "bidirectional"))
    )
    (net (code "313") (name "ZZ.02.047") (class "Default")
      (node (ref "U$6") (pin "P$164") (pinfunction "F14_P$164") (pintype "bidirectional"))
    )
    (net (code "314") (name "ZZ.02.048") (class "Default")
      (node (ref "U$8") (pin "P$44") (pinfunction "B14_P$44") (pintype "bidirectional"))
    )
    (net (code "315") (name "ZZ.02.049") (class "Default")
      (node (ref "U$8") (pin "P$73") (pinfunction "C13_P$73") (pintype "bidirectional"))
    )
    (net (code "316") (name "ZZ.02.050") (class "Default")
      (node (ref "U$8") (pin "P$103") (pinfunction "D13_P$103") (pintype "bidirectional"))
    )
    (net (code "317") (name "ZZ.02.051") (class "Default")
      (node (ref "U$8") (pin "P$102") (pinfunction "D12_P$102") (pintype "bidirectional"))
    )
    (net (code "318") (name "ZZ.02.052") (class "Default")
      (node (ref "U$8") (pin "P$41") (pinfunction "B11_P$41") (pintype "bidirectional"))
    )
    (net (code "319") (name "ZZ.02.053") (class "Default")
      (node (ref "U$8") (pin "P$71") (pinfunction "C11_P$71") (pintype "bidirectional"))
    )
    (net (code "320") (name "ZZ.02.054") (class "Default")
      (node (ref "U$8") (pin "P$101") (pinfunction "D11_P$101") (pintype "bidirectional"))
    )
    (net (code "321") (name "ZZ.02.055") (class "Default")
      (node (ref "U$8") (pin "P$131") (pinfunction "E11_P$131") (pintype "bidirectional"))
    )
    (net (code "322") (name "ZZ.02.056") (class "Default")
      (node (ref "U$8") (pin "P$161") (pinfunction "F11_P$161") (pintype "bidirectional"))
    )
    (net (code "323") (name "ZZ.02.057") (class "Default")
      (node (ref "U$8") (pin "P$132") (pinfunction "E12_P$132") (pintype "bidirectional"))
    )
    (net (code "324") (name "ZZ.02.058") (class "Default")
      (node (ref "U$8") (pin "P$162") (pinfunction "F12_P$162") (pintype "bidirectional"))
    )
    (net (code "325") (name "ZZ.02.059") (class "Default")
      (node (ref "U$8") (pin "P$163") (pinfunction "F13_P$163") (pintype "bidirectional"))
    )
    (net (code "326") (name "ZZ.02.060") (class "Default")
      (node (ref "U$8") (pin "P$134") (pinfunction "E14_P$134") (pintype "bidirectional"))
    )
    (net (code "327") (name "ZZ.02.061") (class "Default")
      (node (ref "U$8") (pin "P$164") (pinfunction "F14_P$164") (pintype "bidirectional"))
    )
    (net (code "328") (name "ZZ.02.062") (class "Default")
      (node (ref "U$8") (pin "P$75") (pinfunction "C15_P$75") (pintype "bidirectional"))
    )
    (net (code "329") (name "ZZ.02.063") (class "Default")
      (node (ref "U$8") (pin "P$135") (pinfunction "E15_P$135") (pintype "bidirectional"))
    )
    (net (code "330") (name "ZZ.02.064") (class "Default")
      (node (ref "U$10") (pin "P$42") (pinfunction "B12_P$42") (pintype "bidirectional"))
    )
    (net (code "331") (name "ZZ.02.065") (class "Default")
      (node (ref "U$10") (pin "P$41") (pinfunction "B11_P$41") (pintype "bidirectional"))
    )
    (net (code "332") (name "ZZ.02.066") (class "Default")
      (node (ref "U$10") (pin "P$71") (pinfunction "C11_P$71") (pintype "bidirectional"))
    )
    (net (code "333") (name "ZZ.02.067") (class "Default")
      (node (ref "U$10") (pin "P$101") (pinfunction "D11_P$101") (pintype "bidirectional"))
    )
    (net (code "334") (name "ZZ.02.068") (class "Default")
      (node (ref "U$10") (pin "P$131") (pinfunction "E11_P$131") (pintype "bidirectional"))
    )
    (net (code "335") (name "ZZ.02.069") (class "Default")
      (node (ref "U$10") (pin "P$161") (pinfunction "F11_P$161") (pintype "bidirectional"))
    )
    (net (code "336") (name "ZZ.02.070") (class "Default")
      (node (ref "U$10") (pin "P$102") (pinfunction "D12_P$102") (pintype "bidirectional"))
    )
    (net (code "337") (name "ZZ.02.071") (class "Default")
      (node (ref "U$10") (pin "P$132") (pinfunction "E12_P$132") (pintype "bidirectional"))
    )
    (net (code "338") (name "ZZ.02.072") (class "Default")
      (node (ref "U$10") (pin "P$73") (pinfunction "C13_P$73") (pintype "bidirectional"))
    )
    (net (code "339") (name "ZZ.02.073") (class "Default")
      (node (ref "U$10") (pin "P$133") (pinfunction "E13_P$133") (pintype "bidirectional"))
    )
    (net (code "340") (name "ZZ.02.074") (class "Default")
      (node (ref "U$10") (pin "P$159") (pinfunction "F9_P$159") (pintype "bidirectional"))
    )
    (net (code "341") (name "ZZ.02.075") (class "Default")
      (node (ref "U$10") (pin "P$44") (pinfunction "B14_P$44") (pintype "bidirectional"))
    )
    (net (code "342") (name "ZZ.02.076") (class "Default")
      (node (ref "U$10") (pin "P$104") (pinfunction "D14_P$104") (pintype "bidirectional"))
    )
    (net (code "343") (name "ZZ.02.077") (class "Default")
      (node (ref "U$10") (pin "P$164") (pinfunction "F14_P$164") (pintype "bidirectional"))
    )
    (net (code "344") (name "ZZ.02.078") (class "Default")
      (node (ref "U$10") (pin "P$75") (pinfunction "C15_P$75") (pintype "bidirectional"))
    )
    (net (code "345") (name "ZZ.02.079") (class "Default")
      (node (ref "U$10") (pin "P$135") (pinfunction "E15_P$135") (pintype "bidirectional"))
    )
    (net (code "346") (name "ZZ.02.080") (class "Default")
      (node (ref "U$12") (pin "P$71") (pinfunction "C11_P$71") (pintype "bidirectional"))
    )
    (net (code "347") (name "ZZ.02.081") (class "Default")
      (node (ref "U$12") (pin "P$101") (pinfunction "D11_P$101") (pintype "bidirectional"))
    )
    (net (code "348") (name "ZZ.02.082") (class "Default")
      (node (ref "U$12") (pin "P$131") (pinfunction "E11_P$131") (pintype "bidirectional"))
    )
    (net (code "349") (name "ZZ.02.083") (class "Default")
      (node (ref "U$12") (pin "P$161") (pinfunction "F11_P$161") (pintype "bidirectional"))
    )
    (net (code "350") (name "ZZ.02.084") (class "Default")
      (node (ref "U$12") (pin "P$40") (pinfunction "B10_P$40") (pintype "bidirectional"))
    )
    (net (code "351") (name "ZZ.02.085") (class "Default")
      (node (ref "U$12") (pin "P$41") (pinfunction "B11_P$41") (pintype "bidirectional"))
    )
    (net (code "352") (name "ZZ.02.086") (class "Default")
      (node (ref "U$12") (pin "P$72") (pinfunction "C12_P$72") (pintype "bidirectional"))
    )
    (net (code "353") (name "ZZ.02.087") (class "Default")
      (node (ref "U$12") (pin "P$132") (pinfunction "E12_P$132") (pintype "bidirectional"))
    )
    (net (code "354") (name "ZZ.02.088") (class "Default")
      (node (ref "U$12") (pin "P$73") (pinfunction "C13_P$73") (pintype "bidirectional"))
    )
    (net (code "355") (name "ZZ.02.089") (class "Default")
      (node (ref "U$12") (pin "P$103") (pinfunction "D13_P$103") (pintype "bidirectional"))
    )
    (net (code "356") (name "ZZ.02.090") (class "Default")
      (node (ref "U$12") (pin "P$159") (pinfunction "F9_P$159") (pintype "bidirectional"))
    )
    (net (code "357") (name "ZZ.02.091") (class "Default")
      (node (ref "U$12") (pin "P$44") (pinfunction "B14_P$44") (pintype "bidirectional"))
    )
    (net (code "358") (name "ZZ.02.092") (class "Default")
      (node (ref "U$12") (pin "P$104") (pinfunction "D14_P$104") (pintype "bidirectional"))
    )
    (net (code "359") (name "ZZ.02.093") (class "Default")
      (node (ref "U$12") (pin "P$164") (pinfunction "F14_P$164") (pintype "bidirectional"))
    )
    (net (code "360") (name "ZZ.02.094") (class "Default")
      (node (ref "U$12") (pin "P$105") (pinfunction "D15_P$105") (pintype "bidirectional"))
    )
    (net (code "361") (name "ZZ.02.095") (class "Default")
      (node (ref "U$12") (pin "P$135") (pinfunction "E15_P$135") (pintype "bidirectional"))
    )
    (net (code "362") (name "ZZ.02.096") (class "Default")
      (node (ref "U$14") (pin "P$161") (pinfunction "F11_P$161") (pintype "bidirectional"))
    )
    (net (code "363") (name "ZZ.02.097") (class "Default")
      (node (ref "U$14") (pin "P$40") (pinfunction "B10_P$40") (pintype "bidirectional"))
    )
    (net (code "364") (name "ZZ.02.098") (class "Default")
      (node (ref "U$14") (pin "P$70") (pinfunction "C10_P$70") (pintype "bidirectional"))
    )
    (net (code "365") (name "ZZ.02.099") (class "Default")
      (node (ref "U$14") (pin "P$130") (pinfunction "E10_P$130") (pintype "bidirectional"))
    )
    (net (code "366") (name "ZZ.02.100") (class "Default")
      (node (ref "U$14") (pin "P$101") (pinfunction "D11_P$101") (pintype "bidirectional"))
    )
    (net (code "367") (name "ZZ.02.101") (class "Default")
      (node (ref "U$14") (pin "P$131") (pinfunction "E11_P$131") (pintype "bidirectional"))
    )
    (net (code "368") (name "ZZ.02.102") (class "Default")
      (node (ref "U$14") (pin "P$72") (pinfunction "C12_P$72") (pintype "bidirectional"))
    )
    (net (code "369") (name "ZZ.02.103") (class "Default")
      (node (ref "U$14") (pin "P$162") (pinfunction "F12_P$162") (pintype "bidirectional"))
    )
    (net (code "370") (name "ZZ.02.104") (class "Default")
      (node (ref "U$14") (pin "P$73") (pinfunction "C13_P$73") (pintype "bidirectional"))
    )
    (net (code "371") (name "ZZ.02.105") (class "Default")
      (node (ref "U$14") (pin "P$103") (pinfunction "D13_P$103") (pintype "bidirectional"))
    )
    (net (code "372") (name "ZZ.02.106") (class "Default")
      (node (ref "U$14") (pin "P$163") (pinfunction "F13_P$163") (pintype "bidirectional"))
    )
    (net (code "373") (name "ZZ.02.107") (class "Default")
      (node (ref "U$14") (pin "P$74") (pinfunction "C14_P$74") (pintype "bidirectional"))
    )
    (net (code "374") (name "ZZ.02.108") (class "Default")
      (node (ref "U$14") (pin "P$134") (pinfunction "E14_P$134") (pintype "bidirectional"))
    )
    (net (code "375") (name "ZZ.02.109") (class "Default")
      (node (ref "U$14") (pin "P$164") (pinfunction "F14_P$164") (pintype "bidirectional"))
    )
    (net (code "376") (name "ZZ.02.110") (class "Default")
      (node (ref "U$14") (pin "P$105") (pinfunction "D15_P$105") (pintype "bidirectional"))
    )
    (net (code "377") (name "ZZ.02.111") (class "Default")
      (node (ref "U$14") (pin "P$135") (pinfunction "E15_P$135") (pintype "bidirectional"))
    )
    (net (code "378") (name "ZZ.02.112") (class "Default")
      (node (ref "U$16") (pin "P$70") (pinfunction "C10_P$70") (pintype "bidirectional"))
    )
    (net (code "379") (name "ZZ.02.113") (class "Default")
      (node (ref "U$16") (pin "P$130") (pinfunction "E10_P$130") (pintype "bidirectional"))
    )
    (net (code "380") (name "ZZ.02.114") (class "Default")
      (node (ref "U$16") (pin "P$129") (pinfunction "E9_P$129") (pintype "bidirectional"))
    )
    (net (code "381") (name "ZZ.02.115") (class "Default")
      (node (ref "U$16") (pin "P$41") (pinfunction "B11_P$41") (pintype "bidirectional"))
    )
    (net (code "382") (name "ZZ.02.116") (class "Default")
      (node (ref "U$16") (pin "P$131") (pinfunction "E11_P$131") (pintype "bidirectional"))
    )
    (net (code "383") (name "ZZ.02.117") (class "Default")
      (node (ref "U$16") (pin "P$161") (pinfunction "F11_P$161") (pintype "bidirectional"))
    )
    (net (code "384") (name "ZZ.02.118") (class "Default")
      (node (ref "U$16") (pin "P$102") (pinfunction "D12_P$102") (pintype "bidirectional"))
    )
    (net (code "385") (name "ZZ.02.119") (class "Default")
      (node (ref "U$16") (pin "P$132") (pinfunction "E12_P$132") (pintype "bidirectional"))
    )
    (net (code "386") (name "ZZ.02.120") (class "Default")
      (node (ref "U$16") (pin "P$43") (pinfunction "B13_P$43") (pintype "bidirectional"))
    )
    (net (code "387") (name "ZZ.02.121") (class "Default")
      (node (ref "U$16") (pin "P$133") (pinfunction "E13_P$133") (pintype "bidirectional"))
    )
    (net (code "388") (name "ZZ.02.122") (class "Default")
      (node (ref "U$16") (pin "P$163") (pinfunction "F13_P$163") (pintype "bidirectional"))
    )
    (net (code "389") (name "ZZ.02.123") (class "Default")
      (node (ref "U$16") (pin "P$44") (pinfunction "B14_P$44") (pintype "bidirectional"))
    )
    (net (code "390") (name "ZZ.02.124") (class "Default")
      (node (ref "U$16") (pin "P$134") (pinfunction "E14_P$134") (pintype "bidirectional"))
    )
    (net (code "391") (name "ZZ.02.125") (class "Default")
      (node (ref "U$16") (pin "P$164") (pinfunction "F14_P$164") (pintype "bidirectional"))
    )
    (net (code "392") (name "ZZ.02.126") (class "Default")
      (node (ref "U$16") (pin "P$105") (pinfunction "D15_P$105") (pintype "bidirectional"))
    )
    (net (code "393") (name "ZZ.02.127") (class "Default")
      (node (ref "U$16") (pin "P$135") (pinfunction "E15_P$135") (pintype "bidirectional"))
    )
    (net (code "394") (name "ZZ.03.000") (class "Default")
      (node (ref "U$2") (pin "P$45") (pinfunction "B15_P$45") (pintype "bidirectional"))
    )
    (net (code "395") (name "ZZ.03.001") (class "Default")
      (node (ref "U$2") (pin "P$105") (pinfunction "D15_P$105") (pintype "bidirectional"))
    )
    (net (code "396") (name "ZZ.03.002") (class "Default")
      (node (ref "U$2") (pin "P$44") (pinfunction "B14_P$44") (pintype "bidirectional"))
    )
    (net (code "397") (name "ZZ.03.003") (class "Default")
      (node (ref "U$2") (pin "P$74") (pinfunction "C14_P$74") (pintype "bidirectional"))
    )
    (net (code "398") (name "ZZ.03.004") (class "Default")
      (node (ref "U$2") (pin "P$164") (pinfunction "F14_P$164") (pintype "bidirectional"))
    )
    (net (code "399") (name "ZZ.03.005") (class "Default")
      (node (ref "U$2") (pin "P$43") (pinfunction "B13_P$43") (pintype "bidirectional"))
    )
    (net (code "400") (name "ZZ.03.006") (class "Default")
      (node (ref "U$2") (pin "P$133") (pinfunction "E13_P$133") (pintype "bidirectional"))
    )
    (net (code "401") (name "ZZ.03.007") (class "Default")
      (node (ref "U$2") (pin "P$159") (pinfunction "F9_P$159") (pintype "bidirectional"))
    )
    (net (code "402") (name "ZZ.03.008") (class "Default")
      (node (ref "U$2") (pin "P$42") (pinfunction "B12_P$42") (pintype "bidirectional"))
    )
    (net (code "403") (name "ZZ.03.009") (class "Default")
      (node (ref "U$2") (pin "P$132") (pinfunction "E12_P$132") (pintype "bidirectional"))
    )
    (net (code "404") (name "ZZ.03.010") (class "Default")
      (node (ref "U$2") (pin "P$131") (pinfunction "E11_P$131") (pintype "bidirectional"))
    )
    (net (code "405") (name "ZZ.03.011") (class "Default")
      (node (ref "U$2") (pin "P$130") (pinfunction "E10_P$130") (pintype "bidirectional"))
    )
    (net (code "406") (name "ZZ.03.012") (class "Default")
      (node (ref "U$2") (pin "P$129") (pinfunction "E9_P$129") (pintype "bidirectional"))
    )
    (net (code "407") (name "ZZ.03.013") (class "Default")
      (node (ref "U$2") (pin "P$40") (pinfunction "B10_P$40") (pintype "bidirectional"))
    )
    (net (code "408") (name "ZZ.03.014") (class "Default")
      (node (ref "U$2") (pin "P$70") (pinfunction "C10_P$70") (pintype "bidirectional"))
    )
    (net (code "409") (name "ZZ.03.015") (class "Default")
      (node (ref "U$2") (pin "P$100") (pinfunction "D10_P$100") (pintype "bidirectional"))
    )
    (net (code "410") (name "ZZ.03.016") (class "Default")
      (node (ref "U$4") (pin "P$45") (pinfunction "B15_P$45") (pintype "bidirectional"))
    )
    (net (code "411") (name "ZZ.03.017") (class "Default")
      (node (ref "U$4") (pin "P$135") (pinfunction "E15_P$135") (pintype "bidirectional"))
    )
    (net (code "412") (name "ZZ.03.018") (class "Default")
      (node (ref "U$4") (pin "P$44") (pinfunction "B14_P$44") (pintype "bidirectional"))
    )
    (net (code "413") (name "ZZ.03.019") (class "Default")
      (node (ref "U$4") (pin "P$104") (pinfunction "D14_P$104") (pintype "bidirectional"))
    )
    (net (code "414") (name "ZZ.03.020") (class "Default")
      (node (ref "U$4") (pin "P$134") (pinfunction "E14_P$134") (pintype "bidirectional"))
    )
    (net (code "415") (name "ZZ.03.021") (class "Default")
      (node (ref "U$4") (pin "P$43") (pinfunction "B13_P$43") (pintype "bidirectional"))
    )
    (net (code "416") (name "ZZ.03.022") (class "Default")
      (node (ref "U$4") (pin "P$103") (pinfunction "D13_P$103") (pintype "bidirectional"))
    )
    (net (code "417") (name "ZZ.03.023") (class "Default")
      (node (ref "U$4") (pin "P$159") (pinfunction "F9_P$159") (pintype "bidirectional"))
    )
    (net (code "418") (name "ZZ.03.024") (class "Default")
      (node (ref "U$4") (pin "P$42") (pinfunction "B12_P$42") (pintype "bidirectional"))
    )
    (net (code "419") (name "ZZ.03.025") (class "Default")
      (node (ref "U$4") (pin "P$102") (pinfunction "D12_P$102") (pintype "bidirectional"))
    )
    (net (code "420") (name "ZZ.03.026") (class "Default")
      (node (ref "U$4") (pin "P$40") (pinfunction "B10_P$40") (pintype "bidirectional"))
    )
    (net (code "421") (name "ZZ.03.027") (class "Default")
      (node (ref "U$4") (pin "P$70") (pinfunction "C10_P$70") (pintype "bidirectional"))
    )
    (net (code "422") (name "ZZ.03.028") (class "Default")
      (node (ref "U$4") (pin "P$100") (pinfunction "D10_P$100") (pintype "bidirectional"))
    )
    (net (code "423") (name "ZZ.03.029") (class "Default")
      (node (ref "U$4") (pin "P$130") (pinfunction "E10_P$130") (pintype "bidirectional"))
    )
    (net (code "424") (name "ZZ.03.030") (class "Default")
      (node (ref "U$4") (pin "P$160") (pinfunction "F10_P$160") (pintype "bidirectional"))
    )
    (net (code "425") (name "ZZ.03.031") (class "Default")
      (node (ref "U$4") (pin "P$129") (pinfunction "E9_P$129") (pintype "bidirectional"))
    )
    (net (code "426") (name "ZZ.03.032") (class "Default")
      (node (ref "U$6") (pin "P$45") (pinfunction "B15_P$45") (pintype "bidirectional"))
    )
    (net (code "427") (name "ZZ.03.033") (class "Default")
      (node (ref "U$6") (pin "P$135") (pinfunction "E15_P$135") (pintype "bidirectional"))
    )
    (net (code "428") (name "ZZ.03.034") (class "Default")
      (node (ref "U$6") (pin "P$44") (pinfunction "B14_P$44") (pintype "bidirectional"))
    )
    (net (code "429") (name "ZZ.03.035") (class "Default")
      (node (ref "U$6") (pin "P$104") (pinfunction "D14_P$104") (pintype "bidirectional"))
    )
    (net (code "430") (name "ZZ.03.036") (class "Default")
      (node (ref "U$6") (pin "P$73") (pinfunction "C13_P$73") (pintype "bidirectional"))
    )
    (net (code "431") (name "ZZ.03.037") (class "Default")
      (node (ref "U$6") (pin "P$42") (pinfunction "B12_P$42") (pintype "bidirectional"))
    )
    (net (code "432") (name "ZZ.03.038") (class "Default")
      (node (ref "U$6") (pin "P$72") (pinfunction "C12_P$72") (pintype "bidirectional"))
    )
    (net (code "433") (name "ZZ.03.039") (class "Default")
      (node (ref "U$6") (pin "P$40") (pinfunction "B10_P$40") (pintype "bidirectional"))
    )
    (net (code "434") (name "ZZ.03.040") (class "Default")
      (node (ref "U$6") (pin "P$70") (pinfunction "C10_P$70") (pintype "bidirectional"))
    )
    (net (code "435") (name "ZZ.03.041") (class "Default")
      (node (ref "U$6") (pin "P$100") (pinfunction "D10_P$100") (pintype "bidirectional"))
    )
    (net (code "436") (name "ZZ.03.042") (class "Default")
      (node (ref "U$6") (pin "P$130") (pinfunction "E10_P$130") (pintype "bidirectional"))
    )
    (net (code "437") (name "ZZ.03.043") (class "Default")
      (node (ref "U$6") (pin "P$160") (pinfunction "F10_P$160") (pintype "bidirectional"))
    )
    (net (code "438") (name "ZZ.03.044") (class "Default")
      (node (ref "U$6") (pin "P$129") (pinfunction "E9_P$129") (pintype "bidirectional"))
    )
    (net (code "439") (name "ZZ.03.045") (class "Default")
      (node (ref "U$6") (pin "P$133") (pinfunction "E13_P$133") (pintype "bidirectional"))
    )
    (net (code "440") (name "ZZ.03.046") (class "Default")
      (node (ref "U$6") (pin "P$163") (pinfunction "F13_P$163") (pintype "bidirectional"))
    )
    (net (code "441") (name "ZZ.03.047") (class "Default")
      (node (ref "U$6") (pin "P$134") (pinfunction "E14_P$134") (pintype "bidirectional"))
    )
    (net (code "442") (name "ZZ.03.048") (class "Default")
      (node (ref "U$8") (pin "P$74") (pinfunction "C14_P$74") (pintype "bidirectional"))
    )
    (net (code "443") (name "ZZ.03.049") (class "Default")
      (node (ref "U$8") (pin "P$43") (pinfunction "B13_P$43") (pintype "bidirectional"))
    )
    (net (code "444") (name "ZZ.03.050") (class "Default")
      (node (ref "U$8") (pin "P$42") (pinfunction "B12_P$42") (pintype "bidirectional"))
    )
    (net (code "445") (name "ZZ.03.051") (class "Default")
      (node (ref "U$8") (pin "P$72") (pinfunction "C12_P$72") (pintype "bidirectional"))
    )
    (net (code "446") (name "ZZ.03.052") (class "Default")
      (node (ref "U$8") (pin "P$40") (pinfunction "B10_P$40") (pintype "bidirectional"))
    )
    (net (code "447") (name "ZZ.03.053") (class "Default")
      (node (ref "U$8") (pin "P$70") (pinfunction "C10_P$70") (pintype "bidirectional"))
    )
    (net (code "448") (name "ZZ.03.054") (class "Default")
      (node (ref "U$8") (pin "P$100") (pinfunction "D10_P$100") (pintype "bidirectional"))
    )
    (net (code "449") (name "ZZ.03.055") (class "Default")
      (node (ref "U$8") (pin "P$130") (pinfunction "E10_P$130") (pintype "bidirectional"))
    )
    (net (code "450") (name "ZZ.03.056") (class "Default")
      (node (ref "U$8") (pin "P$160") (pinfunction "F10_P$160") (pintype "bidirectional"))
    )
    (net (code "451") (name "ZZ.03.057") (class "Default")
      (node (ref "U$8") (pin "P$129") (pinfunction "E9_P$129") (pintype "bidirectional"))
    )
    (net (code "452") (name "ZZ.03.058") (class "Default")
      (node (ref "U$8") (pin "P$133") (pinfunction "E13_P$133") (pintype "bidirectional"))
    )
    (net (code "453") (name "ZZ.03.059") (class "Default")
      (node (ref "U$8") (pin "P$159") (pinfunction "F9_P$159") (pintype "bidirectional"))
    )
    (net (code "454") (name "ZZ.03.060") (class "Default")
      (node (ref "U$8") (pin "P$104") (pinfunction "D14_P$104") (pintype "bidirectional"))
    )
    (net (code "455") (name "ZZ.03.061") (class "Default")
      (node (ref "U$8") (pin "P$45") (pinfunction "B15_P$45") (pintype "bidirectional"))
    )
    (net (code "456") (name "ZZ.03.062") (class "Default")
      (node (ref "U$8") (pin "P$105") (pinfunction "D15_P$105") (pintype "bidirectional"))
    )
    (net (code "457") (name "ZZ.03.063") (class "Default")
      (node (ref "U$8") (pin "P$165") (pinfunction "F15_P$165") (pintype "bidirectional"))
    )
    (net (code "458") (name "ZZ.03.064") (class "Default")
      (node (ref "U$10") (pin "P$72") (pinfunction "C12_P$72") (pintype "bidirectional"))
    )
    (net (code "459") (name "ZZ.03.065") (class "Default")
      (node (ref "U$10") (pin "P$40") (pinfunction "B10_P$40") (pintype "bidirectional"))
    )
    (net (code "460") (name "ZZ.03.066") (class "Default")
      (node (ref "U$10") (pin "P$70") (pinfunction "C10_P$70") (pintype "bidirectional"))
    )
    (net (code "461") (name "ZZ.03.067") (class "Default")
      (node (ref "U$10") (pin "P$100") (pinfunction "D10_P$100") (pintype "bidirectional"))
    )
    (net (code "462") (name "ZZ.03.068") (class "Default")
      (node (ref "U$10") (pin "P$130") (pinfunction "E10_P$130") (pintype "bidirectional"))
    )
    (net (code "463") (name "ZZ.03.069") (class "Default")
      (node (ref "U$10") (pin "P$160") (pinfunction "F10_P$160") (pintype "bidirectional"))
    )
    (net (code "464") (name "ZZ.03.070") (class "Default")
      (node (ref "U$10") (pin "P$129") (pinfunction "E9_P$129") (pintype "bidirectional"))
    )
    (net (code "465") (name "ZZ.03.071") (class "Default")
      (node (ref "U$10") (pin "P$162") (pinfunction "F12_P$162") (pintype "bidirectional"))
    )
    (net (code "466") (name "ZZ.03.072") (class "Default")
      (node (ref "U$10") (pin "P$43") (pinfunction "B13_P$43") (pintype "bidirectional"))
    )
    (net (code "467") (name "ZZ.03.073") (class "Default")
      (node (ref "U$10") (pin "P$103") (pinfunction "D13_P$103") (pintype "bidirectional"))
    )
    (net (code "468") (name "ZZ.03.074") (class "Default")
      (node (ref "U$10") (pin "P$163") (pinfunction "F13_P$163") (pintype "bidirectional"))
    )
    (net (code "469") (name "ZZ.03.075") (class "Default")
      (node (ref "U$10") (pin "P$74") (pinfunction "C14_P$74") (pintype "bidirectional"))
    )
    (net (code "470") (name "ZZ.03.076") (class "Default")
      (node (ref "U$10") (pin "P$134") (pinfunction "E14_P$134") (pintype "bidirectional"))
    )
    (net (code "471") (name "ZZ.03.077") (class "Default")
      (node (ref "U$10") (pin "P$45") (pinfunction "B15_P$45") (pintype "bidirectional"))
    )
    (net (code "472") (name "ZZ.03.078") (class "Default")
      (node (ref "U$10") (pin "P$105") (pinfunction "D15_P$105") (pintype "bidirectional"))
    )
    (net (code "473") (name "ZZ.03.079") (class "Default")
      (node (ref "U$10") (pin "P$165") (pinfunction "F15_P$165") (pintype "bidirectional"))
    )
    (net (code "474") (name "ZZ.03.080") (class "Default")
      (node (ref "U$12") (pin "P$70") (pinfunction "C10_P$70") (pintype "bidirectional"))
    )
    (net (code "475") (name "ZZ.03.081") (class "Default")
      (node (ref "U$12") (pin "P$100") (pinfunction "D10_P$100") (pintype "bidirectional"))
    )
    (net (code "476") (name "ZZ.03.082") (class "Default")
      (node (ref "U$12") (pin "P$130") (pinfunction "E10_P$130") (pintype "bidirectional"))
    )
    (net (code "477") (name "ZZ.03.083") (class "Default")
      (node (ref "U$12") (pin "P$160") (pinfunction "F10_P$160") (pintype "bidirectional"))
    )
    (net (code "478") (name "ZZ.03.084") (class "Default")
      (node (ref "U$12") (pin "P$129") (pinfunction "E9_P$129") (pintype "bidirectional"))
    )
    (net (code "479") (name "ZZ.03.085") (class "Default")
      (node (ref "U$12") (pin "P$42") (pinfunction "B12_P$42") (pintype "bidirectional"))
    )
    (net (code "480") (name "ZZ.03.086") (class "Default")
      (node (ref "U$12") (pin "P$102") (pinfunction "D12_P$102") (pintype "bidirectional"))
    )
    (net (code "481") (name "ZZ.03.087") (class "Default")
      (node (ref "U$12") (pin "P$162") (pinfunction "F12_P$162") (pintype "bidirectional"))
    )
    (net (code "482") (name "ZZ.03.088") (class "Default")
      (node (ref "U$12") (pin "P$43") (pinfunction "B13_P$43") (pintype "bidirectional"))
    )
    (net (code "483") (name "ZZ.03.089") (class "Default")
      (node (ref "U$12") (pin "P$133") (pinfunction "E13_P$133") (pintype "bidirectional"))
    )
    (net (code "484") (name "ZZ.03.090") (class "Default")
      (node (ref "U$12") (pin "P$163") (pinfunction "F13_P$163") (pintype "bidirectional"))
    )
    (net (code "485") (name "ZZ.03.091") (class "Default")
      (node (ref "U$12") (pin "P$74") (pinfunction "C14_P$74") (pintype "bidirectional"))
    )
    (net (code "486") (name "ZZ.03.092") (class "Default")
      (node (ref "U$12") (pin "P$134") (pinfunction "E14_P$134") (pintype "bidirectional"))
    )
    (net (code "487") (name "ZZ.03.093") (class "Default")
      (node (ref "U$12") (pin "P$45") (pinfunction "B15_P$45") (pintype "bidirectional"))
    )
    (net (code "488") (name "ZZ.03.094") (class "Default")
      (node (ref "U$12") (pin "P$75") (pinfunction "C15_P$75") (pintype "bidirectional"))
    )
    (net (code "489") (name "ZZ.03.095") (class "Default")
      (node (ref "U$12") (pin "P$165") (pinfunction "F15_P$165") (pintype "bidirectional"))
    )
    (net (code "490") (name "ZZ.03.096") (class "Default")
      (node (ref "U$14") (pin "P$160") (pinfunction "F10_P$160") (pintype "bidirectional"))
    )
    (net (code "491") (name "ZZ.03.097") (class "Default")
      (node (ref "U$14") (pin "P$129") (pinfunction "E9_P$129") (pintype "bidirectional"))
    )
    (net (code "492") (name "ZZ.03.098") (class "Default")
      (node (ref "U$14") (pin "P$100") (pinfunction "D10_P$100") (pintype "bidirectional"))
    )
    (net (code "493") (name "ZZ.03.099") (class "Default")
      (node (ref "U$14") (pin "P$41") (pinfunction "B11_P$41") (pintype "bidirectional"))
    )
    (net (code "494") (name "ZZ.03.100") (class "Default")
      (node (ref "U$14") (pin "P$71") (pinfunction "C11_P$71") (pintype "bidirectional"))
    )
    (net (code "495") (name "ZZ.03.101") (class "Default")
      (node (ref "U$14") (pin "P$42") (pinfunction "B12_P$42") (pintype "bidirectional"))
    )
    (net (code "496") (name "ZZ.03.102") (class "Default")
      (node (ref "U$14") (pin "P$102") (pinfunction "D12_P$102") (pintype "bidirectional"))
    )
    (net (code "497") (name "ZZ.03.103") (class "Default")
      (node (ref "U$14") (pin "P$132") (pinfunction "E12_P$132") (pintype "bidirectional"))
    )
    (net (code "498") (name "ZZ.03.104") (class "Default")
      (node (ref "U$14") (pin "P$43") (pinfunction "B13_P$43") (pintype "bidirectional"))
    )
    (net (code "499") (name "ZZ.03.105") (class "Default")
      (node (ref "U$14") (pin "P$133") (pinfunction "E13_P$133") (pintype "bidirectional"))
    )
    (net (code "500") (name "ZZ.03.106") (class "Default")
      (node (ref "U$14") (pin "P$159") (pinfunction "F9_P$159") (pintype "bidirectional"))
    )
    (net (code "501") (name "ZZ.03.107") (class "Default")
      (node (ref "U$14") (pin "P$44") (pinfunction "B14_P$44") (pintype "bidirectional"))
    )
    (net (code "502") (name "ZZ.03.108") (class "Default")
      (node (ref "U$14") (pin "P$104") (pinfunction "D14_P$104") (pintype "bidirectional"))
    )
    (net (code "503") (name "ZZ.03.109") (class "Default")
      (node (ref "U$14") (pin "P$45") (pinfunction "B15_P$45") (pintype "bidirectional"))
    )
    (net (code "504") (name "ZZ.03.110") (class "Default")
      (node (ref "U$14") (pin "P$75") (pinfunction "C15_P$75") (pintype "bidirectional"))
    )
    (net (code "505") (name "ZZ.03.111") (class "Default")
      (node (ref "U$14") (pin "P$165") (pinfunction "F15_P$165") (pintype "bidirectional"))
    )
    (net (code "506") (name "ZZ.03.112") (class "Default")
      (node (ref "U$16") (pin "P$40") (pinfunction "B10_P$40") (pintype "bidirectional"))
    )
    (net (code "507") (name "ZZ.03.113") (class "Default")
      (node (ref "U$16") (pin "P$100") (pinfunction "D10_P$100") (pintype "bidirectional"))
    )
    (net (code "508") (name "ZZ.03.114") (class "Default")
      (node (ref "U$16") (pin "P$160") (pinfunction "F10_P$160") (pintype "bidirectional"))
    )
    (net (code "509") (name "ZZ.03.115") (class "Default")
      (node (ref "U$16") (pin "P$71") (pinfunction "C11_P$71") (pintype "bidirectional"))
    )
    (net (code "510") (name "ZZ.03.116") (class "Default")
      (node (ref "U$16") (pin "P$101") (pinfunction "D11_P$101") (pintype "bidirectional"))
    )
    (net (code "511") (name "ZZ.03.117") (class "Default")
      (node (ref "U$16") (pin "P$42") (pinfunction "B12_P$42") (pintype "bidirectional"))
    )
    (net (code "512") (name "ZZ.03.118") (class "Default")
      (node (ref "U$16") (pin "P$72") (pinfunction "C12_P$72") (pintype "bidirectional"))
    )
    (net (code "513") (name "ZZ.03.119") (class "Default")
      (node (ref "U$16") (pin "P$162") (pinfunction "F12_P$162") (pintype "bidirectional"))
    )
    (net (code "514") (name "ZZ.03.120") (class "Default")
      (node (ref "U$16") (pin "P$73") (pinfunction "C13_P$73") (pintype "bidirectional"))
    )
    (net (code "515") (name "ZZ.03.121") (class "Default")
      (node (ref "U$16") (pin "P$103") (pinfunction "D13_P$103") (pintype "bidirectional"))
    )
    (net (code "516") (name "ZZ.03.122") (class "Default")
      (node (ref "U$16") (pin "P$159") (pinfunction "F9_P$159") (pintype "bidirectional"))
    )
    (net (code "517") (name "ZZ.03.123") (class "Default")
      (node (ref "U$16") (pin "P$74") (pinfunction "C14_P$74") (pintype "bidirectional"))
    )
    (net (code "518") (name "ZZ.03.124") (class "Default")
      (node (ref "U$16") (pin "P$104") (pinfunction "D14_P$104") (pintype "bidirectional"))
    )
    (net (code "519") (name "ZZ.03.125") (class "Default")
      (node (ref "U$16") (pin "P$45") (pinfunction "B15_P$45") (pintype "bidirectional"))
    )
    (net (code "520") (name "ZZ.03.126") (class "Default")
      (node (ref "U$16") (pin "P$75") (pinfunction "C15_P$75") (pintype "bidirectional"))
    )
    (net (code "521") (name "ZZ.03.127") (class "Default")
      (node (ref "U$16") (pin "P$165") (pinfunction "F15_P$165") (pintype "bidirectional"))
    )
    (net (code "522") (name "ZZ.04.000") (class "Default")
      (node (ref "U$2") (pin "P$49") (pinfunction "B19_P$49") (pintype "bidirectional"))
    )
    (net (code "523") (name "ZZ.04.001") (class "Default")
      (node (ref "U$2") (pin "P$79") (pinfunction "C19_P$79") (pintype "bidirectional"))
    )
    (net (code "524") (name "ZZ.04.002") (class "Default")
      (node (ref "U$2") (pin "P$109") (pinfunction "D19_P$109") (pintype "bidirectional"))
    )
    (net (code "525") (name "ZZ.04.003") (class "Default")
      (node (ref "U$2") (pin "P$139") (pinfunction "E19_P$139") (pintype "bidirectional"))
    )
    (net (code "526") (name "ZZ.04.004") (class "Default")
      (node (ref "U$2") (pin "P$169") (pinfunction "F19_P$169") (pintype "bidirectional"))
    )
    (net (code "527") (name "ZZ.04.005") (class "Default")
      (node (ref "U$2") (pin "P$48") (pinfunction "B18_P$48") (pintype "bidirectional"))
    )
    (net (code "528") (name "ZZ.04.006") (class "Default")
      (node (ref "U$2") (pin "P$78") (pinfunction "C18_P$78") (pintype "bidirectional"))
    )
    (net (code "529") (name "ZZ.04.007") (class "Default")
      (node (ref "U$2") (pin "P$108") (pinfunction "D18_P$108") (pintype "bidirectional"))
    )
    (net (code "530") (name "ZZ.04.008") (class "Default")
      (node (ref "U$2") (pin "P$138") (pinfunction "E18_P$138") (pintype "bidirectional"))
    )
    (net (code "531") (name "ZZ.04.009") (class "Default")
      (node (ref "U$2") (pin "P$168") (pinfunction "F18_P$168") (pintype "bidirectional"))
    )
    (net (code "532") (name "ZZ.04.010") (class "Default")
      (node (ref "U$2") (pin "P$47") (pinfunction "B17_P$47") (pintype "bidirectional"))
    )
    (net (code "533") (name "ZZ.04.011") (class "Default")
      (node (ref "U$2") (pin "P$77") (pinfunction "C17_P$77") (pintype "bidirectional"))
    )
    (net (code "534") (name "ZZ.04.012") (class "Default")
      (node (ref "U$2") (pin "P$107") (pinfunction "D17_P$107") (pintype "bidirectional"))
    )
    (net (code "535") (name "ZZ.04.013") (class "Default")
      (node (ref "U$2") (pin "P$137") (pinfunction "E17_P$137") (pintype "bidirectional"))
    )
    (net (code "536") (name "ZZ.04.014") (class "Default")
      (node (ref "U$2") (pin "P$167") (pinfunction "F17_P$167") (pintype "bidirectional"))
    )
    (net (code "537") (name "ZZ.04.015") (class "Default")
      (node (ref "U$2") (pin "P$136") (pinfunction "E16_P$136") (pintype "bidirectional"))
    )
    (net (code "538") (name "ZZ.04.016") (class "Default")
      (node (ref "U$4") (pin "P$49") (pinfunction "B19_P$49") (pintype "bidirectional"))
    )
    (net (code "539") (name "ZZ.04.017") (class "Default")
      (node (ref "U$4") (pin "P$79") (pinfunction "C19_P$79") (pintype "bidirectional"))
    )
    (net (code "540") (name "ZZ.04.018") (class "Default")
      (node (ref "U$4") (pin "P$109") (pinfunction "D19_P$109") (pintype "bidirectional"))
    )
    (net (code "541") (name "ZZ.04.019") (class "Default")
      (node (ref "U$4") (pin "P$139") (pinfunction "E19_P$139") (pintype "bidirectional"))
    )
    (net (code "542") (name "ZZ.04.020") (class "Default")
      (node (ref "U$4") (pin "P$169") (pinfunction "F19_P$169") (pintype "bidirectional"))
    )
    (net (code "543") (name "ZZ.04.021") (class "Default")
      (node (ref "U$4") (pin "P$48") (pinfunction "B18_P$48") (pintype "bidirectional"))
    )
    (net (code "544") (name "ZZ.04.022") (class "Default")
      (node (ref "U$4") (pin "P$78") (pinfunction "C18_P$78") (pintype "bidirectional"))
    )
    (net (code "545") (name "ZZ.04.023") (class "Default")
      (node (ref "U$4") (pin "P$108") (pinfunction "D18_P$108") (pintype "bidirectional"))
    )
    (net (code "546") (name "ZZ.04.024") (class "Default")
      (node (ref "U$4") (pin "P$138") (pinfunction "E18_P$138") (pintype "bidirectional"))
    )
    (net (code "547") (name "ZZ.04.025") (class "Default")
      (node (ref "U$4") (pin "P$47") (pinfunction "B17_P$47") (pintype "bidirectional"))
    )
    (net (code "548") (name "ZZ.04.026") (class "Default")
      (node (ref "U$4") (pin "P$77") (pinfunction "C17_P$77") (pintype "bidirectional"))
    )
    (net (code "549") (name "ZZ.04.027") (class "Default")
      (node (ref "U$4") (pin "P$107") (pinfunction "D17_P$107") (pintype "bidirectional"))
    )
    (net (code "550") (name "ZZ.04.028") (class "Default")
      (node (ref "U$4") (pin "P$137") (pinfunction "E17_P$137") (pintype "bidirectional"))
    )
    (net (code "551") (name "ZZ.04.029") (class "Default")
      (node (ref "U$4") (pin "P$167") (pinfunction "F17_P$167") (pintype "bidirectional"))
    )
    (net (code "552") (name "ZZ.04.030") (class "Default")
      (node (ref "U$4") (pin "P$136") (pinfunction "E16_P$136") (pintype "bidirectional"))
    )
    (net (code "553") (name "ZZ.04.031") (class "Default")
      (node (ref "U$4") (pin "P$168") (pinfunction "F18_P$168") (pintype "bidirectional"))
    )
    (net (code "554") (name "ZZ.04.032") (class "Default")
      (node (ref "U$6") (pin "P$49") (pinfunction "B19_P$49") (pintype "bidirectional"))
    )
    (net (code "555") (name "ZZ.04.033") (class "Default")
      (node (ref "U$6") (pin "P$79") (pinfunction "C19_P$79") (pintype "bidirectional"))
    )
    (net (code "556") (name "ZZ.04.034") (class "Default")
      (node (ref "U$6") (pin "P$109") (pinfunction "D19_P$109") (pintype "bidirectional"))
    )
    (net (code "557") (name "ZZ.04.035") (class "Default")
      (node (ref "U$6") (pin "P$139") (pinfunction "E19_P$139") (pintype "bidirectional"))
    )
    (net (code "558") (name "ZZ.04.036") (class "Default")
      (node (ref "U$6") (pin "P$48") (pinfunction "B18_P$48") (pintype "bidirectional"))
    )
    (net (code "559") (name "ZZ.04.037") (class "Default")
      (node (ref "U$6") (pin "P$78") (pinfunction "C18_P$78") (pintype "bidirectional"))
    )
    (net (code "560") (name "ZZ.04.038") (class "Default")
      (node (ref "U$6") (pin "P$47") (pinfunction "B17_P$47") (pintype "bidirectional"))
    )
    (net (code "561") (name "ZZ.04.039") (class "Default")
      (node (ref "U$6") (pin "P$77") (pinfunction "C17_P$77") (pintype "bidirectional"))
    )
    (net (code "562") (name "ZZ.04.040") (class "Default")
      (node (ref "U$6") (pin "P$107") (pinfunction "D17_P$107") (pintype "bidirectional"))
    )
    (net (code "563") (name "ZZ.04.041") (class "Default")
      (node (ref "U$6") (pin "P$137") (pinfunction "E17_P$137") (pintype "bidirectional"))
    )
    (net (code "564") (name "ZZ.04.042") (class "Default")
      (node (ref "U$6") (pin "P$167") (pinfunction "F17_P$167") (pintype "bidirectional"))
    )
    (net (code "565") (name "ZZ.04.043") (class "Default")
      (node (ref "U$6") (pin "P$136") (pinfunction "E16_P$136") (pintype "bidirectional"))
    )
    (net (code "566") (name "ZZ.04.044") (class "Default")
      (node (ref "U$6") (pin "P$108") (pinfunction "D18_P$108") (pintype "bidirectional"))
    )
    (net (code "567") (name "ZZ.04.045") (class "Default")
      (node (ref "U$6") (pin "P$138") (pinfunction "E18_P$138") (pintype "bidirectional"))
    )
    (net (code "568") (name "ZZ.04.046") (class "Default")
      (node (ref "U$6") (pin "P$168") (pinfunction "F18_P$168") (pintype "bidirectional"))
    )
    (net (code "569") (name "ZZ.04.047") (class "Default")
      (node (ref "U$6") (pin "P$169") (pinfunction "F19_P$169") (pintype "bidirectional"))
    )
    (net (code "570") (name "ZZ.04.048") (class "Default")
      (node (ref "U$8") (pin "P$49") (pinfunction "B19_P$49") (pintype "bidirectional"))
    )
    (net (code "571") (name "ZZ.04.049") (class "Default")
      (node (ref "U$8") (pin "P$48") (pinfunction "B18_P$48") (pintype "bidirectional"))
    )
    (net (code "572") (name "ZZ.04.050") (class "Default")
      (node (ref "U$8") (pin "P$78") (pinfunction "C18_P$78") (pintype "bidirectional"))
    )
    (net (code "573") (name "ZZ.04.051") (class "Default")
      (node (ref "U$8") (pin "P$47") (pinfunction "B17_P$47") (pintype "bidirectional"))
    )
    (net (code "574") (name "ZZ.04.052") (class "Default")
      (node (ref "U$8") (pin "P$77") (pinfunction "C17_P$77") (pintype "bidirectional"))
    )
    (net (code "575") (name "ZZ.04.053") (class "Default")
      (node (ref "U$8") (pin "P$107") (pinfunction "D17_P$107") (pintype "bidirectional"))
    )
    (net (code "576") (name "ZZ.04.054") (class "Default")
      (node (ref "U$8") (pin "P$137") (pinfunction "E17_P$137") (pintype "bidirectional"))
    )
    (net (code "577") (name "ZZ.04.055") (class "Default")
      (node (ref "U$8") (pin "P$167") (pinfunction "F17_P$167") (pintype "bidirectional"))
    )
    (net (code "578") (name "ZZ.04.056") (class "Default")
      (node (ref "U$8") (pin "P$136") (pinfunction "E16_P$136") (pintype "bidirectional"))
    )
    (net (code "579") (name "ZZ.04.057") (class "Default")
      (node (ref "U$8") (pin "P$108") (pinfunction "D18_P$108") (pintype "bidirectional"))
    )
    (net (code "580") (name "ZZ.04.058") (class "Default")
      (node (ref "U$8") (pin "P$138") (pinfunction "E18_P$138") (pintype "bidirectional"))
    )
    (net (code "581") (name "ZZ.04.059") (class "Default")
      (node (ref "U$8") (pin "P$168") (pinfunction "F18_P$168") (pintype "bidirectional"))
    )
    (net (code "582") (name "ZZ.04.060") (class "Default")
      (node (ref "U$8") (pin "P$79") (pinfunction "C19_P$79") (pintype "bidirectional"))
    )
    (net (code "583") (name "ZZ.04.061") (class "Default")
      (node (ref "U$8") (pin "P$109") (pinfunction "D19_P$109") (pintype "bidirectional"))
    )
    (net (code "584") (name "ZZ.04.062") (class "Default")
      (node (ref "U$8") (pin "P$139") (pinfunction "E19_P$139") (pintype "bidirectional"))
    )
    (net (code "585") (name "ZZ.04.063") (class "Default")
      (node (ref "U$8") (pin "P$169") (pinfunction "F19_P$169") (pintype "bidirectional"))
    )
    (net (code "586") (name "ZZ.04.064") (class "Default")
      (node (ref "U$10") (pin "P$47") (pinfunction "B17_P$47") (pintype "bidirectional"))
    )
    (net (code "587") (name "ZZ.04.065") (class "Default")
      (node (ref "U$10") (pin "P$77") (pinfunction "C17_P$77") (pintype "bidirectional"))
    )
    (net (code "588") (name "ZZ.04.066") (class "Default")
      (node (ref "U$10") (pin "P$107") (pinfunction "D17_P$107") (pintype "bidirectional"))
    )
    (net (code "589") (name "ZZ.04.067") (class "Default")
      (node (ref "U$10") (pin "P$137") (pinfunction "E17_P$137") (pintype "bidirectional"))
    )
    (net (code "590") (name "ZZ.04.068") (class "Default")
      (node (ref "U$10") (pin "P$167") (pinfunction "F17_P$167") (pintype "bidirectional"))
    )
    (net (code "591") (name "ZZ.04.069") (class "Default")
      (node (ref "U$10") (pin "P$136") (pinfunction "E16_P$136") (pintype "bidirectional"))
    )
    (net (code "592") (name "ZZ.04.070") (class "Default")
      (node (ref "U$10") (pin "P$48") (pinfunction "B18_P$48") (pintype "bidirectional"))
    )
    (net (code "593") (name "ZZ.04.071") (class "Default")
      (node (ref "U$10") (pin "P$78") (pinfunction "C18_P$78") (pintype "bidirectional"))
    )
    (net (code "594") (name "ZZ.04.072") (class "Default")
      (node (ref "U$10") (pin "P$108") (pinfunction "D18_P$108") (pintype "bidirectional"))
    )
    (net (code "595") (name "ZZ.04.073") (class "Default")
      (node (ref "U$10") (pin "P$138") (pinfunction "E18_P$138") (pintype "bidirectional"))
    )
    (net (code "596") (name "ZZ.04.074") (class "Default")
      (node (ref "U$10") (pin "P$168") (pinfunction "F18_P$168") (pintype "bidirectional"))
    )
    (net (code "597") (name "ZZ.04.075") (class "Default")
      (node (ref "U$10") (pin "P$49") (pinfunction "B19_P$49") (pintype "bidirectional"))
    )
    (net (code "598") (name "ZZ.04.076") (class "Default")
      (node (ref "U$10") (pin "P$79") (pinfunction "C19_P$79") (pintype "bidirectional"))
    )
    (net (code "599") (name "ZZ.04.077") (class "Default")
      (node (ref "U$10") (pin "P$109") (pinfunction "D19_P$109") (pintype "bidirectional"))
    )
    (net (code "600") (name "ZZ.04.078") (class "Default")
      (node (ref "U$10") (pin "P$139") (pinfunction "E19_P$139") (pintype "bidirectional"))
    )
    (net (code "601") (name "ZZ.04.079") (class "Default")
      (node (ref "U$10") (pin "P$169") (pinfunction "F19_P$169") (pintype "bidirectional"))
    )
    (net (code "602") (name "ZZ.04.080") (class "Default")
      (node (ref "U$12") (pin "P$47") (pinfunction "B17_P$47") (pintype "bidirectional"))
    )
    (net (code "603") (name "ZZ.04.081") (class "Default")
      (node (ref "U$12") (pin "P$77") (pinfunction "C17_P$77") (pintype "bidirectional"))
    )
    (net (code "604") (name "ZZ.04.082") (class "Default")
      (node (ref "U$12") (pin "P$107") (pinfunction "D17_P$107") (pintype "bidirectional"))
    )
    (net (code "605") (name "ZZ.04.083") (class "Default")
      (node (ref "U$12") (pin "P$137") (pinfunction "E17_P$137") (pintype "bidirectional"))
    )
    (net (code "606") (name "ZZ.04.084") (class "Default")
      (node (ref "U$12") (pin "P$167") (pinfunction "F17_P$167") (pintype "bidirectional"))
    )
    (net (code "607") (name "ZZ.04.085") (class "Default")
      (node (ref "U$12") (pin "P$136") (pinfunction "E16_P$136") (pintype "bidirectional"))
    )
    (net (code "608") (name "ZZ.04.086") (class "Default")
      (node (ref "U$12") (pin "P$48") (pinfunction "B18_P$48") (pintype "bidirectional"))
    )
    (net (code "609") (name "ZZ.04.087") (class "Default")
      (node (ref "U$12") (pin "P$78") (pinfunction "C18_P$78") (pintype "bidirectional"))
    )
    (net (code "610") (name "ZZ.04.088") (class "Default")
      (node (ref "U$12") (pin "P$108") (pinfunction "D18_P$108") (pintype "bidirectional"))
    )
    (net (code "611") (name "ZZ.04.089") (class "Default")
      (node (ref "U$12") (pin "P$138") (pinfunction "E18_P$138") (pintype "bidirectional"))
    )
    (net (code "612") (name "ZZ.04.090") (class "Default")
      (node (ref "U$12") (pin "P$168") (pinfunction "F18_P$168") (pintype "bidirectional"))
    )
    (net (code "613") (name "ZZ.04.091") (class "Default")
      (node (ref "U$12") (pin "P$49") (pinfunction "B19_P$49") (pintype "bidirectional"))
    )
    (net (code "614") (name "ZZ.04.092") (class "Default")
      (node (ref "U$12") (pin "P$79") (pinfunction "C19_P$79") (pintype "bidirectional"))
    )
    (net (code "615") (name "ZZ.04.093") (class "Default")
      (node (ref "U$12") (pin "P$109") (pinfunction "D19_P$109") (pintype "bidirectional"))
    )
    (net (code "616") (name "ZZ.04.094") (class "Default")
      (node (ref "U$12") (pin "P$139") (pinfunction "E19_P$139") (pintype "bidirectional"))
    )
    (net (code "617") (name "ZZ.04.095") (class "Default")
      (node (ref "U$12") (pin "P$169") (pinfunction "F19_P$169") (pintype "bidirectional"))
    )
    (net (code "618") (name "ZZ.04.096") (class "Default")
      (node (ref "U$14") (pin "P$47") (pinfunction "B17_P$47") (pintype "bidirectional"))
    )
    (net (code "619") (name "ZZ.04.097") (class "Default")
      (node (ref "U$14") (pin "P$77") (pinfunction "C17_P$77") (pintype "bidirectional"))
    )
    (net (code "620") (name "ZZ.04.098") (class "Default")
      (node (ref "U$14") (pin "P$107") (pinfunction "D17_P$107") (pintype "bidirectional"))
    )
    (net (code "621") (name "ZZ.04.099") (class "Default")
      (node (ref "U$14") (pin "P$137") (pinfunction "E17_P$137") (pintype "bidirectional"))
    )
    (net (code "622") (name "ZZ.04.100") (class "Default")
      (node (ref "U$14") (pin "P$167") (pinfunction "F17_P$167") (pintype "bidirectional"))
    )
    (net (code "623") (name "ZZ.04.101") (class "Default")
      (node (ref "U$14") (pin "P$136") (pinfunction "E16_P$136") (pintype "bidirectional"))
    )
    (net (code "624") (name "ZZ.04.102") (class "Default")
      (node (ref "U$14") (pin "P$48") (pinfunction "B18_P$48") (pintype "bidirectional"))
    )
    (net (code "625") (name "ZZ.04.103") (class "Default")
      (node (ref "U$14") (pin "P$78") (pinfunction "C18_P$78") (pintype "bidirectional"))
    )
    (net (code "626") (name "ZZ.04.104") (class "Default")
      (node (ref "U$14") (pin "P$108") (pinfunction "D18_P$108") (pintype "bidirectional"))
    )
    (net (code "627") (name "ZZ.04.105") (class "Default")
      (node (ref "U$14") (pin "P$138") (pinfunction "E18_P$138") (pintype "bidirectional"))
    )
    (net (code "628") (name "ZZ.04.106") (class "Default")
      (node (ref "U$14") (pin "P$168") (pinfunction "F18_P$168") (pintype "bidirectional"))
    )
    (net (code "629") (name "ZZ.04.107") (class "Default")
      (node (ref "U$14") (pin "P$49") (pinfunction "B19_P$49") (pintype "bidirectional"))
    )
    (net (code "630") (name "ZZ.04.108") (class "Default")
      (node (ref "U$14") (pin "P$79") (pinfunction "C19_P$79") (pintype "bidirectional"))
    )
    (net (code "631") (name "ZZ.04.109") (class "Default")
      (node (ref "U$14") (pin "P$109") (pinfunction "D19_P$109") (pintype "bidirectional"))
    )
    (net (code "632") (name "ZZ.04.110") (class "Default")
      (node (ref "U$14") (pin "P$139") (pinfunction "E19_P$139") (pintype "bidirectional"))
    )
    (net (code "633") (name "ZZ.04.111") (class "Default")
      (node (ref "U$14") (pin "P$169") (pinfunction "F19_P$169") (pintype "bidirectional"))
    )
    (net (code "634") (name "ZZ.04.112") (class "Default")
      (node (ref "U$16") (pin "P$47") (pinfunction "B17_P$47") (pintype "bidirectional"))
    )
    (net (code "635") (name "ZZ.04.113") (class "Default")
      (node (ref "U$16") (pin "P$77") (pinfunction "C17_P$77") (pintype "bidirectional"))
    )
    (net (code "636") (name "ZZ.04.114") (class "Default")
      (node (ref "U$16") (pin "P$107") (pinfunction "D17_P$107") (pintype "bidirectional"))
    )
    (net (code "637") (name "ZZ.04.115") (class "Default")
      (node (ref "U$16") (pin "P$137") (pinfunction "E17_P$137") (pintype "bidirectional"))
    )
    (net (code "638") (name "ZZ.04.116") (class "Default")
      (node (ref "U$16") (pin "P$167") (pinfunction "F17_P$167") (pintype "bidirectional"))
    )
    (net (code "639") (name "ZZ.04.117") (class "Default")
      (node (ref "U$16") (pin "P$136") (pinfunction "E16_P$136") (pintype "bidirectional"))
    )
    (net (code "640") (name "ZZ.04.118") (class "Default")
      (node (ref "U$16") (pin "P$48") (pinfunction "B18_P$48") (pintype "bidirectional"))
    )
    (net (code "641") (name "ZZ.04.119") (class "Default")
      (node (ref "U$16") (pin "P$78") (pinfunction "C18_P$78") (pintype "bidirectional"))
    )
    (net (code "642") (name "ZZ.04.120") (class "Default")
      (node (ref "U$16") (pin "P$108") (pinfunction "D18_P$108") (pintype "bidirectional"))
    )
    (net (code "643") (name "ZZ.04.121") (class "Default")
      (node (ref "U$16") (pin "P$138") (pinfunction "E18_P$138") (pintype "bidirectional"))
    )
    (net (code "644") (name "ZZ.04.122") (class "Default")
      (node (ref "U$16") (pin "P$168") (pinfunction "F18_P$168") (pintype "bidirectional"))
    )
    (net (code "645") (name "ZZ.04.123") (class "Default")
      (node (ref "U$16") (pin "P$49") (pinfunction "B19_P$49") (pintype "bidirectional"))
    )
    (net (code "646") (name "ZZ.04.124") (class "Default")
      (node (ref "U$16") (pin "P$79") (pinfunction "C19_P$79") (pintype "bidirectional"))
    )
    (net (code "647") (name "ZZ.04.125") (class "Default")
      (node (ref "U$16") (pin "P$109") (pinfunction "D19_P$109") (pintype "bidirectional"))
    )
    (net (code "648") (name "ZZ.04.126") (class "Default")
      (node (ref "U$16") (pin "P$139") (pinfunction "E19_P$139") (pintype "bidirectional"))
    )
    (net (code "649") (name "ZZ.04.127") (class "Default")
      (node (ref "U$16") (pin "P$169") (pinfunction "F19_P$169") (pintype "bidirectional"))
    )
    (net (code "650") (name "ZZ.05.000") (class "Default")
      (node (ref "U$2") (pin "P$50") (pinfunction "B20_P$50") (pintype "bidirectional"))
    )
    (net (code "651") (name "ZZ.05.001") (class "Default")
      (node (ref "U$2") (pin "P$80") (pinfunction "C20_P$80") (pintype "bidirectional"))
    )
    (net (code "652") (name "ZZ.05.002") (class "Default")
      (node (ref "U$2") (pin "P$110") (pinfunction "D20_P$110") (pintype "bidirectional"))
    )
    (net (code "653") (name "ZZ.05.003") (class "Default")
      (node (ref "U$2") (pin "P$140") (pinfunction "E20_P$140") (pintype "bidirectional"))
    )
    (net (code "654") (name "ZZ.05.004") (class "Default")
      (node (ref "U$2") (pin "P$170") (pinfunction "F20_P$170") (pintype "bidirectional"))
    )
    (net (code "655") (name "ZZ.05.005") (class "Default")
      (node (ref "U$2") (pin "P$166") (pinfunction "F16_P$166") (pintype "bidirectional"))
    )
    (net (code "656") (name "ZZ.05.006") (class "Default")
      (node (ref "U$2") (pin "P$51") (pinfunction "B21_P$51") (pintype "bidirectional"))
    )
    (net (code "657") (name "ZZ.05.007") (class "Default")
      (node (ref "U$2") (pin "P$81") (pinfunction "C21_P$81") (pintype "bidirectional"))
    )
    (net (code "658") (name "ZZ.05.008") (class "Default")
      (node (ref "U$2") (pin "P$111") (pinfunction "D21_P$111") (pintype "bidirectional"))
    )
    (net (code "659") (name "ZZ.05.009") (class "Default")
      (node (ref "U$2") (pin "P$141") (pinfunction "E21_P$141") (pintype "bidirectional"))
    )
    (net (code "660") (name "ZZ.05.010") (class "Default")
      (node (ref "U$2") (pin "P$171") (pinfunction "F21_P$171") (pintype "bidirectional"))
    )
    (net (code "661") (name "ZZ.05.011") (class "Default")
      (node (ref "U$2") (pin "P$52") (pinfunction "B22_P$52") (pintype "bidirectional"))
    )
    (net (code "662") (name "ZZ.05.012") (class "Default")
      (node (ref "U$2") (pin "P$82") (pinfunction "C22_P$82") (pintype "bidirectional"))
    )
    (net (code "663") (name "ZZ.05.013") (class "Default")
      (node (ref "U$2") (pin "P$112") (pinfunction "D22_P$112") (pintype "bidirectional"))
    )
    (net (code "664") (name "ZZ.05.014") (class "Default")
      (node (ref "U$2") (pin "P$142") (pinfunction "E22_P$142") (pintype "bidirectional"))
    )
    (net (code "665") (name "ZZ.05.015") (class "Default")
      (node (ref "U$2") (pin "P$172") (pinfunction "F22_P$172") (pintype "bidirectional"))
    )
    (net (code "666") (name "ZZ.05.016") (class "Default")
      (node (ref "U$4") (pin "P$50") (pinfunction "B20_P$50") (pintype "bidirectional"))
    )
    (net (code "667") (name "ZZ.05.017") (class "Default")
      (node (ref "U$4") (pin "P$80") (pinfunction "C20_P$80") (pintype "bidirectional"))
    )
    (net (code "668") (name "ZZ.05.018") (class "Default")
      (node (ref "U$4") (pin "P$110") (pinfunction "D20_P$110") (pintype "bidirectional"))
    )
    (net (code "669") (name "ZZ.05.019") (class "Default")
      (node (ref "U$4") (pin "P$140") (pinfunction "E20_P$140") (pintype "bidirectional"))
    )
    (net (code "670") (name "ZZ.05.020") (class "Default")
      (node (ref "U$4") (pin "P$170") (pinfunction "F20_P$170") (pintype "bidirectional"))
    )
    (net (code "671") (name "ZZ.05.021") (class "Default")
      (node (ref "U$4") (pin "P$166") (pinfunction "F16_P$166") (pintype "bidirectional"))
    )
    (net (code "672") (name "ZZ.05.022") (class "Default")
      (node (ref "U$4") (pin "P$51") (pinfunction "B21_P$51") (pintype "bidirectional"))
    )
    (net (code "673") (name "ZZ.05.023") (class "Default")
      (node (ref "U$4") (pin "P$81") (pinfunction "C21_P$81") (pintype "bidirectional"))
    )
    (net (code "674") (name "ZZ.05.024") (class "Default")
      (node (ref "U$4") (pin "P$111") (pinfunction "D21_P$111") (pintype "bidirectional"))
    )
    (net (code "675") (name "ZZ.05.025") (class "Default")
      (node (ref "U$4") (pin "P$141") (pinfunction "E21_P$141") (pintype "bidirectional"))
    )
    (net (code "676") (name "ZZ.05.026") (class "Default")
      (node (ref "U$4") (pin "P$52") (pinfunction "B22_P$52") (pintype "bidirectional"))
    )
    (net (code "677") (name "ZZ.05.027") (class "Default")
      (node (ref "U$4") (pin "P$82") (pinfunction "C22_P$82") (pintype "bidirectional"))
    )
    (net (code "678") (name "ZZ.05.028") (class "Default")
      (node (ref "U$4") (pin "P$112") (pinfunction "D22_P$112") (pintype "bidirectional"))
    )
    (net (code "679") (name "ZZ.05.029") (class "Default")
      (node (ref "U$4") (pin "P$142") (pinfunction "E22_P$142") (pintype "bidirectional"))
    )
    (net (code "680") (name "ZZ.05.030") (class "Default")
      (node (ref "U$4") (pin "P$172") (pinfunction "F22_P$172") (pintype "bidirectional"))
    )
    (net (code "681") (name "ZZ.05.031") (class "Default")
      (node (ref "U$4") (pin "P$171") (pinfunction "F21_P$171") (pintype "bidirectional"))
    )
    (net (code "682") (name "ZZ.05.032") (class "Default")
      (node (ref "U$6") (pin "P$50") (pinfunction "B20_P$50") (pintype "bidirectional"))
    )
    (net (code "683") (name "ZZ.05.033") (class "Default")
      (node (ref "U$6") (pin "P$80") (pinfunction "C20_P$80") (pintype "bidirectional"))
    )
    (net (code "684") (name "ZZ.05.034") (class "Default")
      (node (ref "U$6") (pin "P$110") (pinfunction "D20_P$110") (pintype "bidirectional"))
    )
    (net (code "685") (name "ZZ.05.035") (class "Default")
      (node (ref "U$6") (pin "P$140") (pinfunction "E20_P$140") (pintype "bidirectional"))
    )
    (net (code "686") (name "ZZ.05.036") (class "Default")
      (node (ref "U$6") (pin "P$51") (pinfunction "B21_P$51") (pintype "bidirectional"))
    )
    (net (code "687") (name "ZZ.05.037") (class "Default")
      (node (ref "U$6") (pin "P$81") (pinfunction "C21_P$81") (pintype "bidirectional"))
    )
    (net (code "688") (name "ZZ.05.038") (class "Default")
      (node (ref "U$6") (pin "P$111") (pinfunction "D21_P$111") (pintype "bidirectional"))
    )
    (net (code "689") (name "ZZ.05.039") (class "Default")
      (node (ref "U$6") (pin "P$52") (pinfunction "B22_P$52") (pintype "bidirectional"))
    )
    (net (code "690") (name "ZZ.05.040") (class "Default")
      (node (ref "U$6") (pin "P$82") (pinfunction "C22_P$82") (pintype "bidirectional"))
    )
    (net (code "691") (name "ZZ.05.041") (class "Default")
      (node (ref "U$6") (pin "P$112") (pinfunction "D22_P$112") (pintype "bidirectional"))
    )
    (net (code "692") (name "ZZ.05.042") (class "Default")
      (node (ref "U$6") (pin "P$142") (pinfunction "E22_P$142") (pintype "bidirectional"))
    )
    (net (code "693") (name "ZZ.05.043") (class "Default")
      (node (ref "U$6") (pin "P$172") (pinfunction "F22_P$172") (pintype "bidirectional"))
    )
    (net (code "694") (name "ZZ.05.044") (class "Default")
      (node (ref "U$6") (pin "P$141") (pinfunction "E21_P$141") (pintype "bidirectional"))
    )
    (net (code "695") (name "ZZ.05.045") (class "Default")
      (node (ref "U$6") (pin "P$171") (pinfunction "F21_P$171") (pintype "bidirectional"))
    )
    (net (code "696") (name "ZZ.05.046") (class "Default")
      (node (ref "U$6") (pin "P$170") (pinfunction "F20_P$170") (pintype "bidirectional"))
    )
    (net (code "697") (name "ZZ.05.047") (class "Default")
      (node (ref "U$6") (pin "P$166") (pinfunction "F16_P$166") (pintype "bidirectional"))
    )
    (net (code "698") (name "ZZ.05.048") (class "Default")
      (node (ref "U$8") (pin "P$50") (pinfunction "B20_P$50") (pintype "bidirectional"))
    )
    (net (code "699") (name "ZZ.05.049") (class "Default")
      (node (ref "U$8") (pin "P$51") (pinfunction "B21_P$51") (pintype "bidirectional"))
    )
    (net (code "700") (name "ZZ.05.050") (class "Default")
      (node (ref "U$8") (pin "P$81") (pinfunction "C21_P$81") (pintype "bidirectional"))
    )
    (net (code "701") (name "ZZ.05.051") (class "Default")
      (node (ref "U$8") (pin "P$111") (pinfunction "D21_P$111") (pintype "bidirectional"))
    )
    (net (code "702") (name "ZZ.05.052") (class "Default")
      (node (ref "U$8") (pin "P$52") (pinfunction "B22_P$52") (pintype "bidirectional"))
    )
    (net (code "703") (name "ZZ.05.053") (class "Default")
      (node (ref "U$8") (pin "P$82") (pinfunction "C22_P$82") (pintype "bidirectional"))
    )
    (net (code "704") (name "ZZ.05.054") (class "Default")
      (node (ref "U$8") (pin "P$112") (pinfunction "D22_P$112") (pintype "bidirectional"))
    )
    (net (code "705") (name "ZZ.05.055") (class "Default")
      (node (ref "U$8") (pin "P$142") (pinfunction "E22_P$142") (pintype "bidirectional"))
    )
    (net (code "706") (name "ZZ.05.056") (class "Default")
      (node (ref "U$8") (pin "P$172") (pinfunction "F22_P$172") (pintype "bidirectional"))
    )
    (net (code "707") (name "ZZ.05.057") (class "Default")
      (node (ref "U$8") (pin "P$141") (pinfunction "E21_P$141") (pintype "bidirectional"))
    )
    (net (code "708") (name "ZZ.05.058") (class "Default")
      (node (ref "U$8") (pin "P$171") (pinfunction "F21_P$171") (pintype "bidirectional"))
    )
    (net (code "709") (name "ZZ.05.059") (class "Default")
      (node (ref "U$8") (pin "P$80") (pinfunction "C20_P$80") (pintype "bidirectional"))
    )
    (net (code "710") (name "ZZ.05.060") (class "Default")
      (node (ref "U$8") (pin "P$110") (pinfunction "D20_P$110") (pintype "bidirectional"))
    )
    (net (code "711") (name "ZZ.05.061") (class "Default")
      (node (ref "U$8") (pin "P$140") (pinfunction "E20_P$140") (pintype "bidirectional"))
    )
    (net (code "712") (name "ZZ.05.062") (class "Default")
      (node (ref "U$8") (pin "P$170") (pinfunction "F20_P$170") (pintype "bidirectional"))
    )
    (net (code "713") (name "ZZ.05.063") (class "Default")
      (node (ref "U$8") (pin "P$166") (pinfunction "F16_P$166") (pintype "bidirectional"))
    )
    (net (code "714") (name "ZZ.05.064") (class "Default")
      (node (ref "U$10") (pin "P$51") (pinfunction "B21_P$51") (pintype "bidirectional"))
    )
    (net (code "715") (name "ZZ.05.065") (class "Default")
      (node (ref "U$10") (pin "P$52") (pinfunction "B22_P$52") (pintype "bidirectional"))
    )
    (net (code "716") (name "ZZ.05.066") (class "Default")
      (node (ref "U$10") (pin "P$82") (pinfunction "C22_P$82") (pintype "bidirectional"))
    )
    (net (code "717") (name "ZZ.05.067") (class "Default")
      (node (ref "U$10") (pin "P$112") (pinfunction "D22_P$112") (pintype "bidirectional"))
    )
    (net (code "718") (name "ZZ.05.068") (class "Default")
      (node (ref "U$10") (pin "P$142") (pinfunction "E22_P$142") (pintype "bidirectional"))
    )
    (net (code "719") (name "ZZ.05.069") (class "Default")
      (node (ref "U$10") (pin "P$172") (pinfunction "F22_P$172") (pintype "bidirectional"))
    )
    (net (code "720") (name "ZZ.05.070") (class "Default")
      (node (ref "U$10") (pin "P$81") (pinfunction "C21_P$81") (pintype "bidirectional"))
    )
    (net (code "721") (name "ZZ.05.071") (class "Default")
      (node (ref "U$10") (pin "P$111") (pinfunction "D21_P$111") (pintype "bidirectional"))
    )
    (net (code "722") (name "ZZ.05.072") (class "Default")
      (node (ref "U$10") (pin "P$141") (pinfunction "E21_P$141") (pintype "bidirectional"))
    )
    (net (code "723") (name "ZZ.05.073") (class "Default")
      (node (ref "U$10") (pin "P$171") (pinfunction "F21_P$171") (pintype "bidirectional"))
    )
    (net (code "724") (name "ZZ.05.074") (class "Default")
      (node (ref "U$10") (pin "P$50") (pinfunction "B20_P$50") (pintype "bidirectional"))
    )
    (net (code "725") (name "ZZ.05.075") (class "Default")
      (node (ref "U$10") (pin "P$80") (pinfunction "C20_P$80") (pintype "bidirectional"))
    )
    (net (code "726") (name "ZZ.05.076") (class "Default")
      (node (ref "U$10") (pin "P$110") (pinfunction "D20_P$110") (pintype "bidirectional"))
    )
    (net (code "727") (name "ZZ.05.077") (class "Default")
      (node (ref "U$10") (pin "P$140") (pinfunction "E20_P$140") (pintype "bidirectional"))
    )
    (net (code "728") (name "ZZ.05.078") (class "Default")
      (node (ref "U$10") (pin "P$170") (pinfunction "F20_P$170") (pintype "bidirectional"))
    )
    (net (code "729") (name "ZZ.05.079") (class "Default")
      (node (ref "U$10") (pin "P$166") (pinfunction "F16_P$166") (pintype "bidirectional"))
    )
    (net (code "730") (name "ZZ.05.080") (class "Default")
      (node (ref "U$12") (pin "P$52") (pinfunction "B22_P$52") (pintype "bidirectional"))
    )
    (net (code "731") (name "ZZ.05.081") (class "Default")
      (node (ref "U$12") (pin "P$82") (pinfunction "C22_P$82") (pintype "bidirectional"))
    )
    (net (code "732") (name "ZZ.05.082") (class "Default")
      (node (ref "U$12") (pin "P$112") (pinfunction "D22_P$112") (pintype "bidirectional"))
    )
    (net (code "733") (name "ZZ.05.083") (class "Default")
      (node (ref "U$12") (pin "P$142") (pinfunction "E22_P$142") (pintype "bidirectional"))
    )
    (net (code "734") (name "ZZ.05.084") (class "Default")
      (node (ref "U$12") (pin "P$172") (pinfunction "F22_P$172") (pintype "bidirectional"))
    )
    (net (code "735") (name "ZZ.05.085") (class "Default")
      (node (ref "U$12") (pin "P$51") (pinfunction "B21_P$51") (pintype "bidirectional"))
    )
    (net (code "736") (name "ZZ.05.086") (class "Default")
      (node (ref "U$12") (pin "P$81") (pinfunction "C21_P$81") (pintype "bidirectional"))
    )
    (net (code "737") (name "ZZ.05.087") (class "Default")
      (node (ref "U$12") (pin "P$111") (pinfunction "D21_P$111") (pintype "bidirectional"))
    )
    (net (code "738") (name "ZZ.05.088") (class "Default")
      (node (ref "U$12") (pin "P$141") (pinfunction "E21_P$141") (pintype "bidirectional"))
    )
    (net (code "739") (name "ZZ.05.089") (class "Default")
      (node (ref "U$12") (pin "P$171") (pinfunction "F21_P$171") (pintype "bidirectional"))
    )
    (net (code "740") (name "ZZ.05.090") (class "Default")
      (node (ref "U$12") (pin "P$50") (pinfunction "B20_P$50") (pintype "bidirectional"))
    )
    (net (code "741") (name "ZZ.05.091") (class "Default")
      (node (ref "U$12") (pin "P$80") (pinfunction "C20_P$80") (pintype "bidirectional"))
    )
    (net (code "742") (name "ZZ.05.092") (class "Default")
      (node (ref "U$12") (pin "P$110") (pinfunction "D20_P$110") (pintype "bidirectional"))
    )
    (net (code "743") (name "ZZ.05.093") (class "Default")
      (node (ref "U$12") (pin "P$140") (pinfunction "E20_P$140") (pintype "bidirectional"))
    )
    (net (code "744") (name "ZZ.05.094") (class "Default")
      (node (ref "U$12") (pin "P$170") (pinfunction "F20_P$170") (pintype "bidirectional"))
    )
    (net (code "745") (name "ZZ.05.095") (class "Default")
      (node (ref "U$12") (pin "P$166") (pinfunction "F16_P$166") (pintype "bidirectional"))
    )
    (net (code "746") (name "ZZ.05.096") (class "Default")
      (node (ref "U$14") (pin "P$52") (pinfunction "B22_P$52") (pintype "bidirectional"))
    )
    (net (code "747") (name "ZZ.05.097") (class "Default")
      (node (ref "U$14") (pin "P$82") (pinfunction "C22_P$82") (pintype "bidirectional"))
    )
    (net (code "748") (name "ZZ.05.098") (class "Default")
      (node (ref "U$14") (pin "P$112") (pinfunction "D22_P$112") (pintype "bidirectional"))
    )
    (net (code "749") (name "ZZ.05.099") (class "Default")
      (node (ref "U$14") (pin "P$142") (pinfunction "E22_P$142") (pintype "bidirectional"))
    )
    (net (code "750") (name "ZZ.05.100") (class "Default")
      (node (ref "U$14") (pin "P$172") (pinfunction "F22_P$172") (pintype "bidirectional"))
    )
    (net (code "751") (name "ZZ.05.101") (class "Default")
      (node (ref "U$14") (pin "P$51") (pinfunction "B21_P$51") (pintype "bidirectional"))
    )
    (net (code "752") (name "ZZ.05.102") (class "Default")
      (node (ref "U$14") (pin "P$81") (pinfunction "C21_P$81") (pintype "bidirectional"))
    )
    (net (code "753") (name "ZZ.05.103") (class "Default")
      (node (ref "U$14") (pin "P$111") (pinfunction "D21_P$111") (pintype "bidirectional"))
    )
    (net (code "754") (name "ZZ.05.104") (class "Default")
      (node (ref "U$14") (pin "P$141") (pinfunction "E21_P$141") (pintype "bidirectional"))
    )
    (net (code "755") (name "ZZ.05.105") (class "Default")
      (node (ref "U$14") (pin "P$171") (pinfunction "F21_P$171") (pintype "bidirectional"))
    )
    (net (code "756") (name "ZZ.05.106") (class "Default")
      (node (ref "U$14") (pin "P$50") (pinfunction "B20_P$50") (pintype "bidirectional"))
    )
    (net (code "757") (name "ZZ.05.107") (class "Default")
      (node (ref "U$14") (pin "P$80") (pinfunction "C20_P$80") (pintype "bidirectional"))
    )
    (net (code "758") (name "ZZ.05.108") (class "Default")
      (node (ref "U$14") (pin "P$110") (pinfunction "D20_P$110") (pintype "bidirectional"))
    )
    (net (code "759") (name "ZZ.05.109") (class "Default")
      (node (ref "U$14") (pin "P$140") (pinfunction "E20_P$140") (pintype "bidirectional"))
    )
    (net (code "760") (name "ZZ.05.110") (class "Default")
      (node (ref "U$14") (pin "P$170") (pinfunction "F20_P$170") (pintype "bidirectional"))
    )
    (net (code "761") (name "ZZ.05.111") (class "Default")
      (node (ref "U$14") (pin "P$166") (pinfunction "F16_P$166") (pintype "bidirectional"))
    )
    (net (code "762") (name "ZZ.05.112") (class "Default")
      (node (ref "U$16") (pin "P$52") (pinfunction "B22_P$52") (pintype "bidirectional"))
    )
    (net (code "763") (name "ZZ.05.113") (class "Default")
      (node (ref "U$16") (pin "P$82") (pinfunction "C22_P$82") (pintype "bidirectional"))
    )
    (net (code "764") (name "ZZ.05.114") (class "Default")
      (node (ref "U$16") (pin "P$112") (pinfunction "D22_P$112") (pintype "bidirectional"))
    )
    (net (code "765") (name "ZZ.05.115") (class "Default")
      (node (ref "U$16") (pin "P$142") (pinfunction "E22_P$142") (pintype "bidirectional"))
    )
    (net (code "766") (name "ZZ.05.116") (class "Default")
      (node (ref "U$16") (pin "P$172") (pinfunction "F22_P$172") (pintype "bidirectional"))
    )
    (net (code "767") (name "ZZ.05.117") (class "Default")
      (node (ref "U$16") (pin "P$51") (pinfunction "B21_P$51") (pintype "bidirectional"))
    )
    (net (code "768") (name "ZZ.05.118") (class "Default")
      (node (ref "U$16") (pin "P$81") (pinfunction "C21_P$81") (pintype "bidirectional"))
    )
    (net (code "769") (name "ZZ.05.119") (class "Default")
      (node (ref "U$16") (pin "P$111") (pinfunction "D21_P$111") (pintype "bidirectional"))
    )
    (net (code "770") (name "ZZ.05.120") (class "Default")
      (node (ref "U$16") (pin "P$141") (pinfunction "E21_P$141") (pintype "bidirectional"))
    )
    (net (code "771") (name "ZZ.05.121") (class "Default")
      (node (ref "U$16") (pin "P$171") (pinfunction "F21_P$171") (pintype "bidirectional"))
    )
    (net (code "772") (name "ZZ.05.122") (class "Default")
      (node (ref "U$16") (pin "P$50") (pinfunction "B20_P$50") (pintype "bidirectional"))
    )
    (net (code "773") (name "ZZ.05.123") (class "Default")
      (node (ref "U$16") (pin "P$80") (pinfunction "C20_P$80") (pintype "bidirectional"))
    )
    (net (code "774") (name "ZZ.05.124") (class "Default")
      (node (ref "U$16") (pin "P$110") (pinfunction "D20_P$110") (pintype "bidirectional"))
    )
    (net (code "775") (name "ZZ.05.125") (class "Default")
      (node (ref "U$16") (pin "P$140") (pinfunction "E20_P$140") (pintype "bidirectional"))
    )
    (net (code "776") (name "ZZ.05.126") (class "Default")
      (node (ref "U$16") (pin "P$170") (pinfunction "F20_P$170") (pintype "bidirectional"))
    )
    (net (code "777") (name "ZZ.05.127") (class "Default")
      (node (ref "U$16") (pin "P$166") (pinfunction "F16_P$166") (pintype "bidirectional"))
    )
    (net (code "778") (name "ZZ.06.000") (class "Default")
      (node (ref "U$2") (pin "P$57") (pinfunction "B27_P$57") (pintype "bidirectional"))
    )
    (net (code "779") (name "ZZ.06.001") (class "Default")
      (node (ref "U$2") (pin "P$87") (pinfunction "C27_P$87") (pintype "bidirectional"))
    )
    (net (code "780") (name "ZZ.06.002") (class "Default")
      (node (ref "U$2") (pin "P$117") (pinfunction "D27_P$117") (pintype "bidirectional"))
    )
    (net (code "781") (name "ZZ.06.003") (class "Default")
      (node (ref "U$2") (pin "P$178") (pinfunction "F28_P$178") (pintype "bidirectional"))
    )
    (net (code "782") (name "ZZ.06.004") (class "Default")
      (node (ref "U$2") (pin "P$145") (pinfunction "E25_P$145") (pintype "bidirectional"))
    )
    (net (code "783") (name "ZZ.06.005") (class "Default")
      (node (ref "U$2") (pin "P$58") (pinfunction "B28_P$58") (pintype "bidirectional"))
    )
    (net (code "784") (name "ZZ.06.006") (class "Default")
      (node (ref "U$2") (pin "P$88") (pinfunction "C28_P$88") (pintype "bidirectional"))
    )
    (net (code "785") (name "ZZ.06.007") (class "Default")
      (node (ref "U$2") (pin "P$118") (pinfunction "D28_P$118") (pintype "bidirectional"))
    )
    (net (code "786") (name "ZZ.06.008") (class "Default")
      (node (ref "U$2") (pin "P$149") (pinfunction "E29_P$149") (pintype "bidirectional"))
    )
    (net (code "787") (name "ZZ.06.009") (class "Default")
      (node (ref "U$2") (pin "P$144") (pinfunction "E24_P$144") (pintype "bidirectional"))
    )
    (net (code "788") (name "ZZ.06.010") (class "Default")
      (node (ref "U$2") (pin "P$59") (pinfunction "B29_P$59") (pintype "bidirectional"))
    )
    (net (code "789") (name "ZZ.06.011") (class "Default")
      (node (ref "U$2") (pin "P$89") (pinfunction "C29_P$89") (pintype "bidirectional"))
    )
    (net (code "790") (name "ZZ.06.012") (class "Default")
      (node (ref "U$2") (pin "P$119") (pinfunction "D29_P$119") (pintype "bidirectional"))
    )
    (net (code "791") (name "ZZ.06.013") (class "Default")
      (node (ref "U$2") (pin "P$179") (pinfunction "F29_P$179") (pintype "bidirectional"))
    )
    (net (code "792") (name "ZZ.06.014") (class "Default")
      (node (ref "U$2") (pin "P$173") (pinfunction "F23_P$173") (pintype "bidirectional"))
    )
    (net (code "793") (name "ZZ.06.015") (class "Default")
      (node (ref "U$2") (pin "P$143") (pinfunction "E23_P$143") (pintype "bidirectional"))
    )
    (net (code "794") (name "ZZ.06.016") (class "Default")
      (node (ref "U$4") (pin "P$57") (pinfunction "B27_P$57") (pintype "bidirectional"))
    )
    (net (code "795") (name "ZZ.06.017") (class "Default")
      (node (ref "U$4") (pin "P$87") (pinfunction "C27_P$87") (pintype "bidirectional"))
    )
    (net (code "796") (name "ZZ.06.018") (class "Default")
      (node (ref "U$4") (pin "P$117") (pinfunction "D27_P$117") (pintype "bidirectional"))
    )
    (net (code "797") (name "ZZ.06.019") (class "Default")
      (node (ref "U$4") (pin "P$178") (pinfunction "F28_P$178") (pintype "bidirectional"))
    )
    (net (code "798") (name "ZZ.06.020") (class "Default")
      (node (ref "U$4") (pin "P$145") (pinfunction "E25_P$145") (pintype "bidirectional"))
    )
    (net (code "799") (name "ZZ.06.021") (class "Default")
      (node (ref "U$4") (pin "P$58") (pinfunction "B28_P$58") (pintype "bidirectional"))
    )
    (net (code "800") (name "ZZ.06.022") (class "Default")
      (node (ref "U$4") (pin "P$88") (pinfunction "C28_P$88") (pintype "bidirectional"))
    )
    (net (code "801") (name "ZZ.06.023") (class "Default")
      (node (ref "U$4") (pin "P$118") (pinfunction "D28_P$118") (pintype "bidirectional"))
    )
    (net (code "802") (name "ZZ.06.024") (class "Default")
      (node (ref "U$4") (pin "P$149") (pinfunction "E29_P$149") (pintype "bidirectional"))
    )
    (net (code "803") (name "ZZ.06.025") (class "Default")
      (node (ref "U$4") (pin "P$59") (pinfunction "B29_P$59") (pintype "bidirectional"))
    )
    (net (code "804") (name "ZZ.06.026") (class "Default")
      (node (ref "U$4") (pin "P$89") (pinfunction "C29_P$89") (pintype "bidirectional"))
    )
    (net (code "805") (name "ZZ.06.027") (class "Default")
      (node (ref "U$4") (pin "P$119") (pinfunction "D29_P$119") (pintype "bidirectional"))
    )
    (net (code "806") (name "ZZ.06.028") (class "Default")
      (node (ref "U$4") (pin "P$179") (pinfunction "F29_P$179") (pintype "bidirectional"))
    )
    (net (code "807") (name "ZZ.06.029") (class "Default")
      (node (ref "U$4") (pin "P$173") (pinfunction "F23_P$173") (pintype "bidirectional"))
    )
    (net (code "808") (name "ZZ.06.030") (class "Default")
      (node (ref "U$4") (pin "P$143") (pinfunction "E23_P$143") (pintype "bidirectional"))
    )
    (net (code "809") (name "ZZ.06.031") (class "Default")
      (node (ref "U$4") (pin "P$144") (pinfunction "E24_P$144") (pintype "bidirectional"))
    )
    (net (code "810") (name "ZZ.06.032") (class "Default")
      (node (ref "U$6") (pin "P$57") (pinfunction "B27_P$57") (pintype "bidirectional"))
    )
    (net (code "811") (name "ZZ.06.033") (class "Default")
      (node (ref "U$6") (pin "P$87") (pinfunction "C27_P$87") (pintype "bidirectional"))
    )
    (net (code "812") (name "ZZ.06.034") (class "Default")
      (node (ref "U$6") (pin "P$117") (pinfunction "D27_P$117") (pintype "bidirectional"))
    )
    (net (code "813") (name "ZZ.06.035") (class "Default")
      (node (ref "U$6") (pin "P$178") (pinfunction "F28_P$178") (pintype "bidirectional"))
    )
    (net (code "814") (name "ZZ.06.036") (class "Default")
      (node (ref "U$6") (pin "P$58") (pinfunction "B28_P$58") (pintype "bidirectional"))
    )
    (net (code "815") (name "ZZ.06.037") (class "Default")
      (node (ref "U$6") (pin "P$88") (pinfunction "C28_P$88") (pintype "bidirectional"))
    )
    (net (code "816") (name "ZZ.06.038") (class "Default")
      (node (ref "U$6") (pin "P$59") (pinfunction "B29_P$59") (pintype "bidirectional"))
    )
    (net (code "817") (name "ZZ.06.039") (class "Default")
      (node (ref "U$6") (pin "P$89") (pinfunction "C29_P$89") (pintype "bidirectional"))
    )
    (net (code "818") (name "ZZ.06.040") (class "Default")
      (node (ref "U$6") (pin "P$119") (pinfunction "D29_P$119") (pintype "bidirectional"))
    )
    (net (code "819") (name "ZZ.06.041") (class "Default")
      (node (ref "U$6") (pin "P$179") (pinfunction "F29_P$179") (pintype "bidirectional"))
    )
    (net (code "820") (name "ZZ.06.042") (class "Default")
      (node (ref "U$6") (pin "P$173") (pinfunction "F23_P$173") (pintype "bidirectional"))
    )
    (net (code "821") (name "ZZ.06.043") (class "Default")
      (node (ref "U$6") (pin "P$143") (pinfunction "E23_P$143") (pintype "bidirectional"))
    )
    (net (code "822") (name "ZZ.06.044") (class "Default")
      (node (ref "U$6") (pin "P$118") (pinfunction "D28_P$118") (pintype "bidirectional"))
    )
    (net (code "823") (name "ZZ.06.045") (class "Default")
      (node (ref "U$6") (pin "P$149") (pinfunction "E29_P$149") (pintype "bidirectional"))
    )
    (net (code "824") (name "ZZ.06.046") (class "Default")
      (node (ref "U$6") (pin "P$144") (pinfunction "E24_P$144") (pintype "bidirectional"))
    )
    (net (code "825") (name "ZZ.06.047") (class "Default")
      (node (ref "U$6") (pin "P$145") (pinfunction "E25_P$145") (pintype "bidirectional"))
    )
    (net (code "826") (name "ZZ.06.048") (class "Default")
      (node (ref "U$8") (pin "P$57") (pinfunction "B27_P$57") (pintype "bidirectional"))
    )
    (net (code "827") (name "ZZ.06.049") (class "Default")
      (node (ref "U$8") (pin "P$58") (pinfunction "B28_P$58") (pintype "bidirectional"))
    )
    (net (code "828") (name "ZZ.06.050") (class "Default")
      (node (ref "U$8") (pin "P$88") (pinfunction "C28_P$88") (pintype "bidirectional"))
    )
    (net (code "829") (name "ZZ.06.051") (class "Default")
      (node (ref "U$8") (pin "P$59") (pinfunction "B29_P$59") (pintype "bidirectional"))
    )
    (net (code "830") (name "ZZ.06.052") (class "Default")
      (node (ref "U$8") (pin "P$89") (pinfunction "C29_P$89") (pintype "bidirectional"))
    )
    (net (code "831") (name "ZZ.06.053") (class "Default")
      (node (ref "U$8") (pin "P$119") (pinfunction "D29_P$119") (pintype "bidirectional"))
    )
    (net (code "832") (name "ZZ.06.054") (class "Default")
      (node (ref "U$8") (pin "P$179") (pinfunction "F29_P$179") (pintype "bidirectional"))
    )
    (net (code "833") (name "ZZ.06.055") (class "Default")
      (node (ref "U$8") (pin "P$173") (pinfunction "F23_P$173") (pintype "bidirectional"))
    )
    (net (code "834") (name "ZZ.06.056") (class "Default")
      (node (ref "U$8") (pin "P$143") (pinfunction "E23_P$143") (pintype "bidirectional"))
    )
    (net (code "835") (name "ZZ.06.057") (class "Default")
      (node (ref "U$8") (pin "P$118") (pinfunction "D28_P$118") (pintype "bidirectional"))
    )
    (net (code "836") (name "ZZ.06.058") (class "Default")
      (node (ref "U$8") (pin "P$149") (pinfunction "E29_P$149") (pintype "bidirectional"))
    )
    (net (code "837") (name "ZZ.06.059") (class "Default")
      (node (ref "U$8") (pin "P$144") (pinfunction "E24_P$144") (pintype "bidirectional"))
    )
    (net (code "838") (name "ZZ.06.060") (class "Default")
      (node (ref "U$8") (pin "P$87") (pinfunction "C27_P$87") (pintype "bidirectional"))
    )
    (net (code "839") (name "ZZ.06.061") (class "Default")
      (node (ref "U$8") (pin "P$117") (pinfunction "D27_P$117") (pintype "bidirectional"))
    )
    (net (code "840") (name "ZZ.06.062") (class "Default")
      (node (ref "U$8") (pin "P$178") (pinfunction "F28_P$178") (pintype "bidirectional"))
    )
    (net (code "841") (name "ZZ.06.063") (class "Default")
      (node (ref "U$8") (pin "P$145") (pinfunction "E25_P$145") (pintype "bidirectional"))
    )
    (net (code "842") (name "ZZ.06.064") (class "Default")
      (node (ref "U$10") (pin "P$59") (pinfunction "B29_P$59") (pintype "bidirectional"))
    )
    (net (code "843") (name "ZZ.06.065") (class "Default")
      (node (ref "U$10") (pin "P$89") (pinfunction "C29_P$89") (pintype "bidirectional"))
    )
    (net (code "844") (name "ZZ.06.066") (class "Default")
      (node (ref "U$10") (pin "P$119") (pinfunction "D29_P$119") (pintype "bidirectional"))
    )
    (net (code "845") (name "ZZ.06.067") (class "Default")
      (node (ref "U$10") (pin "P$179") (pinfunction "F29_P$179") (pintype "bidirectional"))
    )
    (net (code "846") (name "ZZ.06.068") (class "Default")
      (node (ref "U$10") (pin "P$173") (pinfunction "F23_P$173") (pintype "bidirectional"))
    )
    (net (code "847") (name "ZZ.06.069") (class "Default")
      (node (ref "U$10") (pin "P$143") (pinfunction "E23_P$143") (pintype "bidirectional"))
    )
    (net (code "848") (name "ZZ.06.070") (class "Default")
      (node (ref "U$10") (pin "P$58") (pinfunction "B28_P$58") (pintype "bidirectional"))
    )
    (net (code "849") (name "ZZ.06.071") (class "Default")
      (node (ref "U$10") (pin "P$88") (pinfunction "C28_P$88") (pintype "bidirectional"))
    )
    (net (code "850") (name "ZZ.06.072") (class "Default")
      (node (ref "U$10") (pin "P$118") (pinfunction "D28_P$118") (pintype "bidirectional"))
    )
    (net (code "851") (name "ZZ.06.073") (class "Default")
      (node (ref "U$10") (pin "P$149") (pinfunction "E29_P$149") (pintype "bidirectional"))
    )
    (net (code "852") (name "ZZ.06.074") (class "Default")
      (node (ref "U$10") (pin "P$144") (pinfunction "E24_P$144") (pintype "bidirectional"))
    )
    (net (code "853") (name "ZZ.06.075") (class "Default")
      (node (ref "U$10") (pin "P$57") (pinfunction "B27_P$57") (pintype "bidirectional"))
    )
    (net (code "854") (name "ZZ.06.076") (class "Default")
      (node (ref "U$10") (pin "P$87") (pinfunction "C27_P$87") (pintype "bidirectional"))
    )
    (net (code "855") (name "ZZ.06.077") (class "Default")
      (node (ref "U$10") (pin "P$117") (pinfunction "D27_P$117") (pintype "bidirectional"))
    )
    (net (code "856") (name "ZZ.06.078") (class "Default")
      (node (ref "U$10") (pin "P$178") (pinfunction "F28_P$178") (pintype "bidirectional"))
    )
    (net (code "857") (name "ZZ.06.079") (class "Default")
      (node (ref "U$10") (pin "P$145") (pinfunction "E25_P$145") (pintype "bidirectional"))
    )
    (net (code "858") (name "ZZ.06.080") (class "Default")
      (node (ref "U$12") (pin "P$59") (pinfunction "B29_P$59") (pintype "bidirectional"))
    )
    (net (code "859") (name "ZZ.06.081") (class "Default")
      (node (ref "U$12") (pin "P$89") (pinfunction "C29_P$89") (pintype "bidirectional"))
    )
    (net (code "860") (name "ZZ.06.082") (class "Default")
      (node (ref "U$12") (pin "P$119") (pinfunction "D29_P$119") (pintype "bidirectional"))
    )
    (net (code "861") (name "ZZ.06.083") (class "Default")
      (node (ref "U$12") (pin "P$179") (pinfunction "F29_P$179") (pintype "bidirectional"))
    )
    (net (code "862") (name "ZZ.06.084") (class "Default")
      (node (ref "U$12") (pin "P$173") (pinfunction "F23_P$173") (pintype "bidirectional"))
    )
    (net (code "863") (name "ZZ.06.085") (class "Default")
      (node (ref "U$12") (pin "P$143") (pinfunction "E23_P$143") (pintype "bidirectional"))
    )
    (net (code "864") (name "ZZ.06.086") (class "Default")
      (node (ref "U$12") (pin "P$58") (pinfunction "B28_P$58") (pintype "bidirectional"))
    )
    (net (code "865") (name "ZZ.06.087") (class "Default")
      (node (ref "U$12") (pin "P$88") (pinfunction "C28_P$88") (pintype "bidirectional"))
    )
    (net (code "866") (name "ZZ.06.088") (class "Default")
      (node (ref "U$12") (pin "P$118") (pinfunction "D28_P$118") (pintype "bidirectional"))
    )
    (net (code "867") (name "ZZ.06.089") (class "Default")
      (node (ref "U$12") (pin "P$149") (pinfunction "E29_P$149") (pintype "bidirectional"))
    )
    (net (code "868") (name "ZZ.06.090") (class "Default")
      (node (ref "U$12") (pin "P$144") (pinfunction "E24_P$144") (pintype "bidirectional"))
    )
    (net (code "869") (name "ZZ.06.091") (class "Default")
      (node (ref "U$12") (pin "P$57") (pinfunction "B27_P$57") (pintype "bidirectional"))
    )
    (net (code "870") (name "ZZ.06.092") (class "Default")
      (node (ref "U$12") (pin "P$87") (pinfunction "C27_P$87") (pintype "bidirectional"))
    )
    (net (code "871") (name "ZZ.06.093") (class "Default")
      (node (ref "U$12") (pin "P$117") (pinfunction "D27_P$117") (pintype "bidirectional"))
    )
    (net (code "872") (name "ZZ.06.094") (class "Default")
      (node (ref "U$12") (pin "P$178") (pinfunction "F28_P$178") (pintype "bidirectional"))
    )
    (net (code "873") (name "ZZ.06.095") (class "Default")
      (node (ref "U$12") (pin "P$145") (pinfunction "E25_P$145") (pintype "bidirectional"))
    )
    (net (code "874") (name "ZZ.06.096") (class "Default")
      (node (ref "U$14") (pin "P$59") (pinfunction "B29_P$59") (pintype "bidirectional"))
    )
    (net (code "875") (name "ZZ.06.097") (class "Default")
      (node (ref "U$14") (pin "P$89") (pinfunction "C29_P$89") (pintype "bidirectional"))
    )
    (net (code "876") (name "ZZ.06.098") (class "Default")
      (node (ref "U$14") (pin "P$119") (pinfunction "D29_P$119") (pintype "bidirectional"))
    )
    (net (code "877") (name "ZZ.06.099") (class "Default")
      (node (ref "U$14") (pin "P$179") (pinfunction "F29_P$179") (pintype "bidirectional"))
    )
    (net (code "878") (name "ZZ.06.100") (class "Default")
      (node (ref "U$14") (pin "P$173") (pinfunction "F23_P$173") (pintype "bidirectional"))
    )
    (net (code "879") (name "ZZ.06.101") (class "Default")
      (node (ref "U$14") (pin "P$143") (pinfunction "E23_P$143") (pintype "bidirectional"))
    )
    (net (code "880") (name "ZZ.06.102") (class "Default")
      (node (ref "U$14") (pin "P$58") (pinfunction "B28_P$58") (pintype "bidirectional"))
    )
    (net (code "881") (name "ZZ.06.103") (class "Default")
      (node (ref "U$14") (pin "P$88") (pinfunction "C28_P$88") (pintype "bidirectional"))
    )
    (net (code "882") (name "ZZ.06.104") (class "Default")
      (node (ref "U$14") (pin "P$118") (pinfunction "D28_P$118") (pintype "bidirectional"))
    )
    (net (code "883") (name "ZZ.06.105") (class "Default")
      (node (ref "U$14") (pin "P$149") (pinfunction "E29_P$149") (pintype "bidirectional"))
    )
    (net (code "884") (name "ZZ.06.106") (class "Default")
      (node (ref "U$14") (pin "P$144") (pinfunction "E24_P$144") (pintype "bidirectional"))
    )
    (net (code "885") (name "ZZ.06.107") (class "Default")
      (node (ref "U$14") (pin "P$57") (pinfunction "B27_P$57") (pintype "bidirectional"))
    )
    (net (code "886") (name "ZZ.06.108") (class "Default")
      (node (ref "U$14") (pin "P$87") (pinfunction "C27_P$87") (pintype "bidirectional"))
    )
    (net (code "887") (name "ZZ.06.109") (class "Default")
      (node (ref "U$14") (pin "P$117") (pinfunction "D27_P$117") (pintype "bidirectional"))
    )
    (net (code "888") (name "ZZ.06.110") (class "Default")
      (node (ref "U$14") (pin "P$178") (pinfunction "F28_P$178") (pintype "bidirectional"))
    )
    (net (code "889") (name "ZZ.06.111") (class "Default")
      (node (ref "U$14") (pin "P$145") (pinfunction "E25_P$145") (pintype "bidirectional"))
    )
    (net (code "890") (name "ZZ.06.112") (class "Default")
      (node (ref "U$16") (pin "P$59") (pinfunction "B29_P$59") (pintype "bidirectional"))
    )
    (net (code "891") (name "ZZ.06.113") (class "Default")
      (node (ref "U$16") (pin "P$89") (pinfunction "C29_P$89") (pintype "bidirectional"))
    )
    (net (code "892") (name "ZZ.06.114") (class "Default")
      (node (ref "U$16") (pin "P$119") (pinfunction "D29_P$119") (pintype "bidirectional"))
    )
    (net (code "893") (name "ZZ.06.115") (class "Default")
      (node (ref "U$16") (pin "P$179") (pinfunction "F29_P$179") (pintype "bidirectional"))
    )
    (net (code "894") (name "ZZ.06.116") (class "Default")
      (node (ref "U$16") (pin "P$173") (pinfunction "F23_P$173") (pintype "bidirectional"))
    )
    (net (code "895") (name "ZZ.06.117") (class "Default")
      (node (ref "U$16") (pin "P$143") (pinfunction "E23_P$143") (pintype "bidirectional"))
    )
    (net (code "896") (name "ZZ.06.118") (class "Default")
      (node (ref "U$16") (pin "P$58") (pinfunction "B28_P$58") (pintype "bidirectional"))
    )
    (net (code "897") (name "ZZ.06.119") (class "Default")
      (node (ref "U$16") (pin "P$88") (pinfunction "C28_P$88") (pintype "bidirectional"))
    )
    (net (code "898") (name "ZZ.06.120") (class "Default")
      (node (ref "U$16") (pin "P$118") (pinfunction "D28_P$118") (pintype "bidirectional"))
    )
    (net (code "899") (name "ZZ.06.121") (class "Default")
      (node (ref "U$16") (pin "P$149") (pinfunction "E29_P$149") (pintype "bidirectional"))
    )
    (net (code "900") (name "ZZ.06.122") (class "Default")
      (node (ref "U$16") (pin "P$144") (pinfunction "E24_P$144") (pintype "bidirectional"))
    )
    (net (code "901") (name "ZZ.06.123") (class "Default")
      (node (ref "U$16") (pin "P$57") (pinfunction "B27_P$57") (pintype "bidirectional"))
    )
    (net (code "902") (name "ZZ.06.124") (class "Default")
      (node (ref "U$16") (pin "P$87") (pinfunction "C27_P$87") (pintype "bidirectional"))
    )
    (net (code "903") (name "ZZ.06.125") (class "Default")
      (node (ref "U$16") (pin "P$117") (pinfunction "D27_P$117") (pintype "bidirectional"))
    )
    (net (code "904") (name "ZZ.06.126") (class "Default")
      (node (ref "U$16") (pin "P$178") (pinfunction "F28_P$178") (pintype "bidirectional"))
    )
    (net (code "905") (name "ZZ.06.127") (class "Default")
      (node (ref "U$16") (pin "P$145") (pinfunction "E25_P$145") (pintype "bidirectional"))
    )
    (net (code "906") (name "ZZ.07.000") (class "Default")
      (node (ref "U$2") (pin "P$54") (pinfunction "B24_P$54") (pintype "bidirectional"))
    )
    (net (code "907") (name "ZZ.07.001") (class "Default")
      (node (ref "U$2") (pin "P$84") (pinfunction "C24_P$84") (pintype "bidirectional"))
    )
    (net (code "908") (name "ZZ.07.002") (class "Default")
      (node (ref "U$2") (pin "P$114") (pinfunction "D24_P$114") (pintype "bidirectional"))
    )
    (net (code "909") (name "ZZ.07.003") (class "Default")
      (node (ref "U$2") (pin "P$147") (pinfunction "E27_P$147") (pintype "bidirectional"))
    )
    (net (code "910") (name "ZZ.07.004") (class "Default")
      (node (ref "U$2") (pin "P$176") (pinfunction "F26_P$176") (pintype "bidirectional"))
    )
    (net (code "911") (name "ZZ.07.005") (class "Default")
      (node (ref "U$2") (pin "P$174") (pinfunction "F24_P$174") (pintype "bidirectional"))
    )
    (net (code "912") (name "ZZ.07.006") (class "Default")
      (node (ref "U$2") (pin "P$55") (pinfunction "B25_P$55") (pintype "bidirectional"))
    )
    (net (code "913") (name "ZZ.07.007") (class "Default")
      (node (ref "U$2") (pin "P$85") (pinfunction "C25_P$85") (pintype "bidirectional"))
    )
    (net (code "914") (name "ZZ.07.008") (class "Default")
      (node (ref "U$2") (pin "P$115") (pinfunction "D25_P$115") (pintype "bidirectional"))
    )
    (net (code "915") (name "ZZ.07.009") (class "Default")
      (node (ref "U$2") (pin "P$177") (pinfunction "F27_P$177") (pintype "bidirectional"))
    )
    (net (code "916") (name "ZZ.07.010") (class "Default")
      (node (ref "U$2") (pin "P$146") (pinfunction "E26_P$146") (pintype "bidirectional"))
    )
    (net (code "917") (name "ZZ.07.011") (class "Default")
      (node (ref "U$2") (pin "P$56") (pinfunction "B26_P$56") (pintype "bidirectional"))
    )
    (net (code "918") (name "ZZ.07.012") (class "Default")
      (node (ref "U$2") (pin "P$86") (pinfunction "C26_P$86") (pintype "bidirectional"))
    )
    (net (code "919") (name "ZZ.07.013") (class "Default")
      (node (ref "U$2") (pin "P$116") (pinfunction "D26_P$116") (pintype "bidirectional"))
    )
    (net (code "920") (name "ZZ.07.014") (class "Default")
      (node (ref "U$2") (pin "P$148") (pinfunction "E28_P$148") (pintype "bidirectional"))
    )
    (net (code "921") (name "ZZ.07.015") (class "Default")
      (node (ref "U$2") (pin "P$175") (pinfunction "F25_P$175") (pintype "bidirectional"))
    )
    (net (code "922") (name "ZZ.07.016") (class "Default")
      (node (ref "U$4") (pin "P$54") (pinfunction "B24_P$54") (pintype "bidirectional"))
    )
    (net (code "923") (name "ZZ.07.017") (class "Default")
      (node (ref "U$4") (pin "P$84") (pinfunction "C24_P$84") (pintype "bidirectional"))
    )
    (net (code "924") (name "ZZ.07.018") (class "Default")
      (node (ref "U$4") (pin "P$114") (pinfunction "D24_P$114") (pintype "bidirectional"))
    )
    (net (code "925") (name "ZZ.07.019") (class "Default")
      (node (ref "U$4") (pin "P$147") (pinfunction "E27_P$147") (pintype "bidirectional"))
    )
    (net (code "926") (name "ZZ.07.020") (class "Default")
      (node (ref "U$4") (pin "P$176") (pinfunction "F26_P$176") (pintype "bidirectional"))
    )
    (net (code "927") (name "ZZ.07.021") (class "Default")
      (node (ref "U$4") (pin "P$174") (pinfunction "F24_P$174") (pintype "bidirectional"))
    )
    (net (code "928") (name "ZZ.07.022") (class "Default")
      (node (ref "U$4") (pin "P$55") (pinfunction "B25_P$55") (pintype "bidirectional"))
    )
    (net (code "929") (name "ZZ.07.023") (class "Default")
      (node (ref "U$4") (pin "P$85") (pinfunction "C25_P$85") (pintype "bidirectional"))
    )
    (net (code "930") (name "ZZ.07.024") (class "Default")
      (node (ref "U$4") (pin "P$115") (pinfunction "D25_P$115") (pintype "bidirectional"))
    )
    (net (code "931") (name "ZZ.07.025") (class "Default")
      (node (ref "U$4") (pin "P$177") (pinfunction "F27_P$177") (pintype "bidirectional"))
    )
    (net (code "932") (name "ZZ.07.026") (class "Default")
      (node (ref "U$4") (pin "P$56") (pinfunction "B26_P$56") (pintype "bidirectional"))
    )
    (net (code "933") (name "ZZ.07.027") (class "Default")
      (node (ref "U$4") (pin "P$86") (pinfunction "C26_P$86") (pintype "bidirectional"))
    )
    (net (code "934") (name "ZZ.07.028") (class "Default")
      (node (ref "U$4") (pin "P$116") (pinfunction "D26_P$116") (pintype "bidirectional"))
    )
    (net (code "935") (name "ZZ.07.029") (class "Default")
      (node (ref "U$4") (pin "P$148") (pinfunction "E28_P$148") (pintype "bidirectional"))
    )
    (net (code "936") (name "ZZ.07.030") (class "Default")
      (node (ref "U$4") (pin "P$175") (pinfunction "F25_P$175") (pintype "bidirectional"))
    )
    (net (code "937") (name "ZZ.07.031") (class "Default")
      (node (ref "U$4") (pin "P$146") (pinfunction "E26_P$146") (pintype "bidirectional"))
    )
    (net (code "938") (name "ZZ.07.032") (class "Default")
      (node (ref "U$6") (pin "P$54") (pinfunction "B24_P$54") (pintype "bidirectional"))
    )
    (net (code "939") (name "ZZ.07.033") (class "Default")
      (node (ref "U$6") (pin "P$84") (pinfunction "C24_P$84") (pintype "bidirectional"))
    )
    (net (code "940") (name "ZZ.07.034") (class "Default")
      (node (ref "U$6") (pin "P$114") (pinfunction "D24_P$114") (pintype "bidirectional"))
    )
    (net (code "941") (name "ZZ.07.035") (class "Default")
      (node (ref "U$6") (pin "P$147") (pinfunction "E27_P$147") (pintype "bidirectional"))
    )
    (net (code "942") (name "ZZ.07.036") (class "Default")
      (node (ref "U$6") (pin "P$55") (pinfunction "B25_P$55") (pintype "bidirectional"))
    )
    (net (code "943") (name "ZZ.07.037") (class "Default")
      (node (ref "U$6") (pin "P$85") (pinfunction "C25_P$85") (pintype "bidirectional"))
    )
    (net (code "944") (name "ZZ.07.038") (class "Default")
      (node (ref "U$6") (pin "P$115") (pinfunction "D25_P$115") (pintype "bidirectional"))
    )
    (net (code "945") (name "ZZ.07.039") (class "Default")
      (node (ref "U$6") (pin "P$56") (pinfunction "B26_P$56") (pintype "bidirectional"))
    )
    (net (code "946") (name "ZZ.07.040") (class "Default")
      (node (ref "U$6") (pin "P$86") (pinfunction "C26_P$86") (pintype "bidirectional"))
    )
    (net (code "947") (name "ZZ.07.041") (class "Default")
      (node (ref "U$6") (pin "P$116") (pinfunction "D26_P$116") (pintype "bidirectional"))
    )
    (net (code "948") (name "ZZ.07.042") (class "Default")
      (node (ref "U$6") (pin "P$148") (pinfunction "E28_P$148") (pintype "bidirectional"))
    )
    (net (code "949") (name "ZZ.07.043") (class "Default")
      (node (ref "U$6") (pin "P$175") (pinfunction "F25_P$175") (pintype "bidirectional"))
    )
    (net (code "950") (name "ZZ.07.044") (class "Default")
      (node (ref "U$6") (pin "P$177") (pinfunction "F27_P$177") (pintype "bidirectional"))
    )
    (net (code "951") (name "ZZ.07.045") (class "Default")
      (node (ref "U$6") (pin "P$146") (pinfunction "E26_P$146") (pintype "bidirectional"))
    )
    (net (code "952") (name "ZZ.07.046") (class "Default")
      (node (ref "U$6") (pin "P$176") (pinfunction "F26_P$176") (pintype "bidirectional"))
    )
    (net (code "953") (name "ZZ.07.047") (class "Default")
      (node (ref "U$6") (pin "P$174") (pinfunction "F24_P$174") (pintype "bidirectional"))
    )
    (net (code "954") (name "ZZ.07.048") (class "Default")
      (node (ref "U$8") (pin "P$54") (pinfunction "B24_P$54") (pintype "bidirectional"))
    )
    (net (code "955") (name "ZZ.07.049") (class "Default")
      (node (ref "U$8") (pin "P$55") (pinfunction "B25_P$55") (pintype "bidirectional"))
    )
    (net (code "956") (name "ZZ.07.050") (class "Default")
      (node (ref "U$8") (pin "P$85") (pinfunction "C25_P$85") (pintype "bidirectional"))
    )
    (net (code "957") (name "ZZ.07.051") (class "Default")
      (node (ref "U$8") (pin "P$115") (pinfunction "D25_P$115") (pintype "bidirectional"))
    )
    (net (code "958") (name "ZZ.07.052") (class "Default")
      (node (ref "U$8") (pin "P$56") (pinfunction "B26_P$56") (pintype "bidirectional"))
    )
    (net (code "959") (name "ZZ.07.053") (class "Default")
      (node (ref "U$8") (pin "P$86") (pinfunction "C26_P$86") (pintype "bidirectional"))
    )
    (net (code "960") (name "ZZ.07.054") (class "Default")
      (node (ref "U$8") (pin "P$116") (pinfunction "D26_P$116") (pintype "bidirectional"))
    )
    (net (code "961") (name "ZZ.07.055") (class "Default")
      (node (ref "U$8") (pin "P$148") (pinfunction "E28_P$148") (pintype "bidirectional"))
    )
    (net (code "962") (name "ZZ.07.056") (class "Default")
      (node (ref "U$8") (pin "P$175") (pinfunction "F25_P$175") (pintype "bidirectional"))
    )
    (net (code "963") (name "ZZ.07.057") (class "Default")
      (node (ref "U$8") (pin "P$177") (pinfunction "F27_P$177") (pintype "bidirectional"))
    )
    (net (code "964") (name "ZZ.07.058") (class "Default")
      (node (ref "U$8") (pin "P$146") (pinfunction "E26_P$146") (pintype "bidirectional"))
    )
    (net (code "965") (name "ZZ.07.059") (class "Default")
      (node (ref "U$8") (pin "P$84") (pinfunction "C24_P$84") (pintype "bidirectional"))
    )
    (net (code "966") (name "ZZ.07.060") (class "Default")
      (node (ref "U$8") (pin "P$114") (pinfunction "D24_P$114") (pintype "bidirectional"))
    )
    (net (code "967") (name "ZZ.07.061") (class "Default")
      (node (ref "U$8") (pin "P$147") (pinfunction "E27_P$147") (pintype "bidirectional"))
    )
    (net (code "968") (name "ZZ.07.062") (class "Default")
      (node (ref "U$8") (pin "P$176") (pinfunction "F26_P$176") (pintype "bidirectional"))
    )
    (net (code "969") (name "ZZ.07.063") (class "Default")
      (node (ref "U$8") (pin "P$174") (pinfunction "F24_P$174") (pintype "bidirectional"))
    )
    (net (code "970") (name "ZZ.07.064") (class "Default")
      (node (ref "U$10") (pin "P$55") (pinfunction "B25_P$55") (pintype "bidirectional"))
    )
    (net (code "971") (name "ZZ.07.065") (class "Default")
      (node (ref "U$10") (pin "P$56") (pinfunction "B26_P$56") (pintype "bidirectional"))
    )
    (net (code "972") (name "ZZ.07.066") (class "Default")
      (node (ref "U$10") (pin "P$86") (pinfunction "C26_P$86") (pintype "bidirectional"))
    )
    (net (code "973") (name "ZZ.07.067") (class "Default")
      (node (ref "U$10") (pin "P$116") (pinfunction "D26_P$116") (pintype "bidirectional"))
    )
    (net (code "974") (name "ZZ.07.068") (class "Default")
      (node (ref "U$10") (pin "P$148") (pinfunction "E28_P$148") (pintype "bidirectional"))
    )
    (net (code "975") (name "ZZ.07.069") (class "Default")
      (node (ref "U$10") (pin "P$175") (pinfunction "F25_P$175") (pintype "bidirectional"))
    )
    (net (code "976") (name "ZZ.07.070") (class "Default")
      (node (ref "U$10") (pin "P$85") (pinfunction "C25_P$85") (pintype "bidirectional"))
    )
    (net (code "977") (name "ZZ.07.071") (class "Default")
      (node (ref "U$10") (pin "P$115") (pinfunction "D25_P$115") (pintype "bidirectional"))
    )
    (net (code "978") (name "ZZ.07.072") (class "Default")
      (node (ref "U$10") (pin "P$177") (pinfunction "F27_P$177") (pintype "bidirectional"))
    )
    (net (code "979") (name "ZZ.07.073") (class "Default")
      (node (ref "U$10") (pin "P$146") (pinfunction "E26_P$146") (pintype "bidirectional"))
    )
    (net (code "980") (name "ZZ.07.074") (class "Default")
      (node (ref "U$10") (pin "P$54") (pinfunction "B24_P$54") (pintype "bidirectional"))
    )
    (net (code "981") (name "ZZ.07.075") (class "Default")
      (node (ref "U$10") (pin "P$84") (pinfunction "C24_P$84") (pintype "bidirectional"))
    )
    (net (code "982") (name "ZZ.07.076") (class "Default")
      (node (ref "U$10") (pin "P$114") (pinfunction "D24_P$114") (pintype "bidirectional"))
    )
    (net (code "983") (name "ZZ.07.077") (class "Default")
      (node (ref "U$10") (pin "P$147") (pinfunction "E27_P$147") (pintype "bidirectional"))
    )
    (net (code "984") (name "ZZ.07.078") (class "Default")
      (node (ref "U$10") (pin "P$176") (pinfunction "F26_P$176") (pintype "bidirectional"))
    )
    (net (code "985") (name "ZZ.07.079") (class "Default")
      (node (ref "U$10") (pin "P$174") (pinfunction "F24_P$174") (pintype "bidirectional"))
    )
    (net (code "986") (name "ZZ.07.080") (class "Default")
      (node (ref "U$12") (pin "P$56") (pinfunction "B26_P$56") (pintype "bidirectional"))
    )
    (net (code "987") (name "ZZ.07.081") (class "Default")
      (node (ref "U$12") (pin "P$86") (pinfunction "C26_P$86") (pintype "bidirectional"))
    )
    (net (code "988") (name "ZZ.07.082") (class "Default")
      (node (ref "U$12") (pin "P$116") (pinfunction "D26_P$116") (pintype "bidirectional"))
    )
    (net (code "989") (name "ZZ.07.083") (class "Default")
      (node (ref "U$12") (pin "P$148") (pinfunction "E28_P$148") (pintype "bidirectional"))
    )
    (net (code "990") (name "ZZ.07.084") (class "Default")
      (node (ref "U$12") (pin "P$175") (pinfunction "F25_P$175") (pintype "bidirectional"))
    )
    (net (code "991") (name "ZZ.07.085") (class "Default")
      (node (ref "U$12") (pin "P$55") (pinfunction "B25_P$55") (pintype "bidirectional"))
    )
    (net (code "992") (name "ZZ.07.086") (class "Default")
      (node (ref "U$12") (pin "P$85") (pinfunction "C25_P$85") (pintype "bidirectional"))
    )
    (net (code "993") (name "ZZ.07.087") (class "Default")
      (node (ref "U$12") (pin "P$115") (pinfunction "D25_P$115") (pintype "bidirectional"))
    )
    (net (code "994") (name "ZZ.07.088") (class "Default")
      (node (ref "U$12") (pin "P$177") (pinfunction "F27_P$177") (pintype "bidirectional"))
    )
    (net (code "995") (name "ZZ.07.089") (class "Default")
      (node (ref "U$12") (pin "P$146") (pinfunction "E26_P$146") (pintype "bidirectional"))
    )
    (net (code "996") (name "ZZ.07.090") (class "Default")
      (node (ref "U$12") (pin "P$54") (pinfunction "B24_P$54") (pintype "bidirectional"))
    )
    (net (code "997") (name "ZZ.07.091") (class "Default")
      (node (ref "U$12") (pin "P$84") (pinfunction "C24_P$84") (pintype "bidirectional"))
    )
    (net (code "998") (name "ZZ.07.092") (class "Default")
      (node (ref "U$12") (pin "P$114") (pinfunction "D24_P$114") (pintype "bidirectional"))
    )
    (net (code "999") (name "ZZ.07.093") (class "Default")
      (node (ref "U$12") (pin "P$147") (pinfunction "E27_P$147") (pintype "bidirectional"))
    )
    (net (code "1000") (name "ZZ.07.094") (class "Default")
      (node (ref "U$12") (pin "P$176") (pinfunction "F26_P$176") (pintype "bidirectional"))
    )
    (net (code "1001") (name "ZZ.07.095") (class "Default")
      (node (ref "U$12") (pin "P$174") (pinfunction "F24_P$174") (pintype "bidirectional"))
    )
    (net (code "1002") (name "ZZ.07.096") (class "Default")
      (node (ref "U$14") (pin "P$56") (pinfunction "B26_P$56") (pintype "bidirectional"))
    )
    (net (code "1003") (name "ZZ.07.097") (class "Default")
      (node (ref "U$14") (pin "P$86") (pinfunction "C26_P$86") (pintype "bidirectional"))
    )
    (net (code "1004") (name "ZZ.07.098") (class "Default")
      (node (ref "U$14") (pin "P$116") (pinfunction "D26_P$116") (pintype "bidirectional"))
    )
    (net (code "1005") (name "ZZ.07.099") (class "Default")
      (node (ref "U$14") (pin "P$148") (pinfunction "E28_P$148") (pintype "bidirectional"))
    )
    (net (code "1006") (name "ZZ.07.100") (class "Default")
      (node (ref "U$14") (pin "P$175") (pinfunction "F25_P$175") (pintype "bidirectional"))
    )
    (net (code "1007") (name "ZZ.07.101") (class "Default")
      (node (ref "U$14") (pin "P$55") (pinfunction "B25_P$55") (pintype "bidirectional"))
    )
    (net (code "1008") (name "ZZ.07.102") (class "Default")
      (node (ref "U$14") (pin "P$85") (pinfunction "C25_P$85") (pintype "bidirectional"))
    )
    (net (code "1009") (name "ZZ.07.103") (class "Default")
      (node (ref "U$14") (pin "P$115") (pinfunction "D25_P$115") (pintype "bidirectional"))
    )
    (net (code "1010") (name "ZZ.07.104") (class "Default")
      (node (ref "U$14") (pin "P$177") (pinfunction "F27_P$177") (pintype "bidirectional"))
    )
    (net (code "1011") (name "ZZ.07.105") (class "Default")
      (node (ref "U$14") (pin "P$146") (pinfunction "E26_P$146") (pintype "bidirectional"))
    )
    (net (code "1012") (name "ZZ.07.106") (class "Default")
      (node (ref "U$14") (pin "P$54") (pinfunction "B24_P$54") (pintype "bidirectional"))
    )
    (net (code "1013") (name "ZZ.07.107") (class "Default")
      (node (ref "U$14") (pin "P$84") (pinfunction "C24_P$84") (pintype "bidirectional"))
    )
    (net (code "1014") (name "ZZ.07.108") (class "Default")
      (node (ref "U$14") (pin "P$114") (pinfunction "D24_P$114") (pintype "bidirectional"))
    )
    (net (code "1015") (name "ZZ.07.109") (class "Default")
      (node (ref "U$14") (pin "P$147") (pinfunction "E27_P$147") (pintype "bidirectional"))
    )
    (net (code "1016") (name "ZZ.07.110") (class "Default")
      (node (ref "U$14") (pin "P$176") (pinfunction "F26_P$176") (pintype "bidirectional"))
    )
    (net (code "1017") (name "ZZ.07.111") (class "Default")
      (node (ref "U$14") (pin "P$174") (pinfunction "F24_P$174") (pintype "bidirectional"))
    )
    (net (code "1018") (name "ZZ.07.112") (class "Default")
      (node (ref "U$16") (pin "P$56") (pinfunction "B26_P$56") (pintype "bidirectional"))
    )
    (net (code "1019") (name "ZZ.07.113") (class "Default")
      (node (ref "U$16") (pin "P$86") (pinfunction "C26_P$86") (pintype "bidirectional"))
    )
    (net (code "1020") (name "ZZ.07.114") (class "Default")
      (node (ref "U$16") (pin "P$116") (pinfunction "D26_P$116") (pintype "bidirectional"))
    )
    (net (code "1021") (name "ZZ.07.115") (class "Default")
      (node (ref "U$16") (pin "P$148") (pinfunction "E28_P$148") (pintype "bidirectional"))
    )
    (net (code "1022") (name "ZZ.07.116") (class "Default")
      (node (ref "U$16") (pin "P$175") (pinfunction "F25_P$175") (pintype "bidirectional"))
    )
    (net (code "1023") (name "ZZ.07.117") (class "Default")
      (node (ref "U$16") (pin "P$55") (pinfunction "B25_P$55") (pintype "bidirectional"))
    )
    (net (code "1024") (name "ZZ.07.118") (class "Default")
      (node (ref "U$16") (pin "P$85") (pinfunction "C25_P$85") (pintype "bidirectional"))
    )
    (net (code "1025") (name "ZZ.07.119") (class "Default")
      (node (ref "U$16") (pin "P$115") (pinfunction "D25_P$115") (pintype "bidirectional"))
    )
    (net (code "1026") (name "ZZ.07.120") (class "Default")
      (node (ref "U$16") (pin "P$177") (pinfunction "F27_P$177") (pintype "bidirectional"))
    )
    (net (code "1027") (name "ZZ.07.121") (class "Default")
      (node (ref "U$16") (pin "P$146") (pinfunction "E26_P$146") (pintype "bidirectional"))
    )
    (net (code "1028") (name "ZZ.07.122") (class "Default")
      (node (ref "U$16") (pin "P$54") (pinfunction "B24_P$54") (pintype "bidirectional"))
    )
    (net (code "1029") (name "ZZ.07.123") (class "Default")
      (node (ref "U$16") (pin "P$84") (pinfunction "C24_P$84") (pintype "bidirectional"))
    )
    (net (code "1030") (name "ZZ.07.124") (class "Default")
      (node (ref "U$16") (pin "P$114") (pinfunction "D24_P$114") (pintype "bidirectional"))
    )
    (net (code "1031") (name "ZZ.07.125") (class "Default")
      (node (ref "U$16") (pin "P$147") (pinfunction "E27_P$147") (pintype "bidirectional"))
    )
    (net (code "1032") (name "ZZ.07.126") (class "Default")
      (node (ref "U$16") (pin "P$176") (pinfunction "F26_P$176") (pintype "bidirectional"))
    )
    (net (code "1033") (name "ZZ.07.127") (class "Default")
      (node (ref "U$16") (pin "P$174") (pinfunction "F24_P$174") (pintype "bidirectional"))
    )
    (net (code "1034") (name "ZZ.08.000") (class "Default")
      (node (ref "U$1") (pin "P$38") (pinfunction "B8_P$38") (pintype "bidirectional"))
    )
    (net (code "1035") (name "ZZ.08.001") (class "Default")
      (node (ref "U$1") (pin "P$98") (pinfunction "D8_P$98") (pintype "bidirectional"))
    )
    (net (code "1036") (name "ZZ.08.002") (class "Default")
      (node (ref "U$1") (pin "P$158") (pinfunction "F8_P$158") (pintype "bidirectional"))
    )
    (net (code "1037") (name "ZZ.08.003") (class "Default")
      (node (ref "U$1") (pin "P$97") (pinfunction "D7_P$97") (pintype "bidirectional"))
    )
    (net (code "1038") (name "ZZ.08.004") (class "Default")
      (node (ref "U$1") (pin "P$127") (pinfunction "E7_P$127") (pintype "bidirectional"))
    )
    (net (code "1039") (name "ZZ.08.005") (class "Default")
      (node (ref "U$1") (pin "P$36") (pinfunction "B6_P$36") (pintype "bidirectional"))
    )
    (net (code "1040") (name "ZZ.08.006") (class "Default")
      (node (ref "U$1") (pin "P$126") (pinfunction "E6_P$126") (pintype "bidirectional"))
    )
    (net (code "1041") (name "ZZ.08.007") (class "Default")
      (node (ref "U$1") (pin "P$156") (pinfunction "F6_P$156") (pintype "bidirectional"))
    )
    (net (code "1042") (name "ZZ.08.008") (class "Default")
      (node (ref "U$1") (pin "P$35") (pinfunction "B5_P$35") (pintype "bidirectional"))
    )
    (net (code "1043") (name "ZZ.08.009") (class "Default")
      (node (ref "U$1") (pin "P$95") (pinfunction "D5_P$95") (pintype "bidirectional"))
    )
    (net (code "1044") (name "ZZ.08.010") (class "Default")
      (node (ref "U$1") (pin "P$155") (pinfunction "F5_P$155") (pintype "bidirectional"))
    )
    (net (code "1045") (name "ZZ.08.011") (class "Default")
      (node (ref "U$1") (pin "P$122") (pinfunction "E2_P$122") (pintype "bidirectional"))
    )
    (net (code "1046") (name "ZZ.08.012") (class "Default")
      (node (ref "U$1") (pin "P$34") (pinfunction "B4_P$34") (pintype "bidirectional"))
    )
    (net (code "1047") (name "ZZ.08.013") (class "Default")
      (node (ref "U$1") (pin "P$64") (pinfunction "C4_P$64") (pintype "bidirectional"))
    )
    (net (code "1048") (name "ZZ.08.014") (class "Default")
      (node (ref "U$1") (pin "P$94") (pinfunction "D4_P$94") (pintype "bidirectional"))
    )
    (net (code "1049") (name "ZZ.08.015") (class "Default")
      (node (ref "U$1") (pin "P$124") (pinfunction "E4_P$124") (pintype "bidirectional"))
    )
    (net (code "1050") (name "ZZ.08.016") (class "Default")
      (node (ref "U$3") (pin "P$38") (pinfunction "B8_P$38") (pintype "bidirectional"))
    )
    (net (code "1051") (name "ZZ.08.017") (class "Default")
      (node (ref "U$3") (pin "P$98") (pinfunction "D8_P$98") (pintype "bidirectional"))
    )
    (net (code "1052") (name "ZZ.08.018") (class "Default")
      (node (ref "U$3") (pin "P$158") (pinfunction "F8_P$158") (pintype "bidirectional"))
    )
    (net (code "1053") (name "ZZ.08.019") (class "Default")
      (node (ref "U$3") (pin "P$97") (pinfunction "D7_P$97") (pintype "bidirectional"))
    )
    (net (code "1054") (name "ZZ.08.020") (class "Default")
      (node (ref "U$3") (pin "P$127") (pinfunction "E7_P$127") (pintype "bidirectional"))
    )
    (net (code "1055") (name "ZZ.08.021") (class "Default")
      (node (ref "U$3") (pin "P$66") (pinfunction "C6_P$66") (pintype "bidirectional"))
    )
    (net (code "1056") (name "ZZ.08.022") (class "Default")
      (node (ref "U$3") (pin "P$126") (pinfunction "E6_P$126") (pintype "bidirectional"))
    )
    (net (code "1057") (name "ZZ.08.023") (class "Default")
      (node (ref "U$3") (pin "P$156") (pinfunction "F6_P$156") (pintype "bidirectional"))
    )
    (net (code "1058") (name "ZZ.08.024") (class "Default")
      (node (ref "U$3") (pin "P$65") (pinfunction "C5_P$65") (pintype "bidirectional"))
    )
    (net (code "1059") (name "ZZ.08.025") (class "Default")
      (node (ref "U$3") (pin "P$34") (pinfunction "B4_P$34") (pintype "bidirectional"))
    )
    (net (code "1060") (name "ZZ.08.026") (class "Default")
      (node (ref "U$3") (pin "P$64") (pinfunction "C4_P$64") (pintype "bidirectional"))
    )
    (net (code "1061") (name "ZZ.08.027") (class "Default")
      (node (ref "U$3") (pin "P$94") (pinfunction "D4_P$94") (pintype "bidirectional"))
    )
    (net (code "1062") (name "ZZ.08.028") (class "Default")
      (node (ref "U$3") (pin "P$124") (pinfunction "E4_P$124") (pintype "bidirectional"))
    )
    (net (code "1063") (name "ZZ.08.029") (class "Default")
      (node (ref "U$3") (pin "P$154") (pinfunction "F4_P$154") (pintype "bidirectional"))
    )
    (net (code "1064") (name "ZZ.08.030") (class "Default")
      (node (ref "U$3") (pin "P$125") (pinfunction "E5_P$125") (pintype "bidirectional"))
    )
    (net (code "1065") (name "ZZ.08.031") (class "Default")
      (node (ref "U$3") (pin "P$155") (pinfunction "F5_P$155") (pintype "bidirectional"))
    )
    (net (code "1066") (name "ZZ.08.032") (class "Default")
      (node (ref "U$5") (pin "P$68") (pinfunction "C8_P$68") (pintype "bidirectional"))
    )
    (net (code "1067") (name "ZZ.08.033") (class "Default")
      (node (ref "U$5") (pin "P$128") (pinfunction "E8_P$128") (pintype "bidirectional"))
    )
    (net (code "1068") (name "ZZ.08.034") (class "Default")
      (node (ref "U$5") (pin "P$158") (pinfunction "F8_P$158") (pintype "bidirectional"))
    )
    (net (code "1069") (name "ZZ.08.035") (class "Default")
      (node (ref "U$5") (pin "P$97") (pinfunction "D7_P$97") (pintype "bidirectional"))
    )
    (net (code "1070") (name "ZZ.08.036") (class "Default")
      (node (ref "U$5") (pin "P$36") (pinfunction "B6_P$36") (pintype "bidirectional"))
    )
    (net (code "1071") (name "ZZ.08.037") (class "Default")
      (node (ref "U$5") (pin "P$96") (pinfunction "D6_P$96") (pintype "bidirectional"))
    )
    (net (code "1072") (name "ZZ.08.038") (class "Default")
      (node (ref "U$5") (pin "P$95") (pinfunction "D5_P$95") (pintype "bidirectional"))
    )
    (net (code "1073") (name "ZZ.08.039") (class "Default")
      (node (ref "U$5") (pin "P$34") (pinfunction "B4_P$34") (pintype "bidirectional"))
    )
    (net (code "1074") (name "ZZ.08.040") (class "Default")
      (node (ref "U$5") (pin "P$64") (pinfunction "C4_P$64") (pintype "bidirectional"))
    )
    (net (code "1075") (name "ZZ.08.041") (class "Default")
      (node (ref "U$5") (pin "P$94") (pinfunction "D4_P$94") (pintype "bidirectional"))
    )
    (net (code "1076") (name "ZZ.08.042") (class "Default")
      (node (ref "U$5") (pin "P$124") (pinfunction "E4_P$124") (pintype "bidirectional"))
    )
    (net (code "1077") (name "ZZ.08.043") (class "Default")
      (node (ref "U$5") (pin "P$154") (pinfunction "F4_P$154") (pintype "bidirectional"))
    )
    (net (code "1078") (name "ZZ.08.044") (class "Default")
      (node (ref "U$5") (pin "P$125") (pinfunction "E5_P$125") (pintype "bidirectional"))
    )
    (net (code "1079") (name "ZZ.08.045") (class "Default")
      (node (ref "U$5") (pin "P$155") (pinfunction "F5_P$155") (pintype "bidirectional"))
    )
    (net (code "1080") (name "ZZ.08.046") (class "Default")
      (node (ref "U$5") (pin "P$152") (pinfunction "F2_P$152") (pintype "bidirectional"))
    )
    (net (code "1081") (name "ZZ.08.047") (class "Default")
      (node (ref "U$5") (pin "P$157") (pinfunction "F7_P$157") (pintype "bidirectional"))
    )
    (net (code "1082") (name "ZZ.08.048") (class "Default")
      (node (ref "U$7") (pin "P$67") (pinfunction "C7_P$67") (pintype "bidirectional"))
    )
    (net (code "1083") (name "ZZ.08.049") (class "Default")
      (node (ref "U$7") (pin "P$66") (pinfunction "C6_P$66") (pintype "bidirectional"))
    )
    (net (code "1084") (name "ZZ.08.050") (class "Default")
      (node (ref "U$7") (pin "P$96") (pinfunction "D6_P$96") (pintype "bidirectional"))
    )
    (net (code "1085") (name "ZZ.08.051") (class "Default")
      (node (ref "U$7") (pin "P$95") (pinfunction "D5_P$95") (pintype "bidirectional"))
    )
    (net (code "1086") (name "ZZ.08.052") (class "Default")
      (node (ref "U$7") (pin "P$34") (pinfunction "B4_P$34") (pintype "bidirectional"))
    )
    (net (code "1087") (name "ZZ.08.053") (class "Default")
      (node (ref "U$7") (pin "P$64") (pinfunction "C4_P$64") (pintype "bidirectional"))
    )
    (net (code "1088") (name "ZZ.08.054") (class "Default")
      (node (ref "U$7") (pin "P$94") (pinfunction "D4_P$94") (pintype "bidirectional"))
    )
    (net (code "1089") (name "ZZ.08.055") (class "Default")
      (node (ref "U$7") (pin "P$124") (pinfunction "E4_P$124") (pintype "bidirectional"))
    )
    (net (code "1090") (name "ZZ.08.056") (class "Default")
      (node (ref "U$7") (pin "P$154") (pinfunction "F4_P$154") (pintype "bidirectional"))
    )
    (net (code "1091") (name "ZZ.08.057") (class "Default")
      (node (ref "U$7") (pin "P$125") (pinfunction "E5_P$125") (pintype "bidirectional"))
    )
    (net (code "1092") (name "ZZ.08.058") (class "Default")
      (node (ref "U$7") (pin "P$155") (pinfunction "F5_P$155") (pintype "bidirectional"))
    )
    (net (code "1093") (name "ZZ.08.059") (class "Default")
      (node (ref "U$7") (pin "P$152") (pinfunction "F2_P$152") (pintype "bidirectional"))
    )
    (net (code "1094") (name "ZZ.08.060") (class "Default")
      (node (ref "U$7") (pin "P$127") (pinfunction "E7_P$127") (pintype "bidirectional"))
    )
    (net (code "1095") (name "ZZ.08.061") (class "Default")
      (node (ref "U$7") (pin "P$157") (pinfunction "F7_P$157") (pintype "bidirectional"))
    )
    (net (code "1096") (name "ZZ.08.062") (class "Default")
      (node (ref "U$7") (pin "P$98") (pinfunction "D8_P$98") (pintype "bidirectional"))
    )
    (net (code "1097") (name "ZZ.08.063") (class "Default")
      (node (ref "U$7") (pin "P$158") (pinfunction "F8_P$158") (pintype "bidirectional"))
    )
    (net (code "1098") (name "ZZ.08.064") (class "Default")
      (node (ref "U$9") (pin "P$65") (pinfunction "C5_P$65") (pintype "bidirectional"))
    )
    (net (code "1099") (name "ZZ.08.065") (class "Default")
      (node (ref "U$9") (pin "P$34") (pinfunction "B4_P$34") (pintype "bidirectional"))
    )
    (net (code "1100") (name "ZZ.08.066") (class "Default")
      (node (ref "U$9") (pin "P$64") (pinfunction "C4_P$64") (pintype "bidirectional"))
    )
    (net (code "1101") (name "ZZ.08.067") (class "Default")
      (node (ref "U$9") (pin "P$94") (pinfunction "D4_P$94") (pintype "bidirectional"))
    )
    (net (code "1102") (name "ZZ.08.068") (class "Default")
      (node (ref "U$9") (pin "P$124") (pinfunction "E4_P$124") (pintype "bidirectional"))
    )
    (net (code "1103") (name "ZZ.08.069") (class "Default")
      (node (ref "U$9") (pin "P$154") (pinfunction "F4_P$154") (pintype "bidirectional"))
    )
    (net (code "1104") (name "ZZ.08.070") (class "Default")
      (node (ref "U$9") (pin "P$95") (pinfunction "D5_P$95") (pintype "bidirectional"))
    )
    (net (code "1105") (name "ZZ.08.071") (class "Default")
      (node (ref "U$9") (pin "P$155") (pinfunction "F5_P$155") (pintype "bidirectional"))
    )
    (net (code "1106") (name "ZZ.08.072") (class "Default")
      (node (ref "U$9") (pin "P$36") (pinfunction "B6_P$36") (pintype "bidirectional"))
    )
    (net (code "1107") (name "ZZ.08.073") (class "Default")
      (node (ref "U$9") (pin "P$126") (pinfunction "E6_P$126") (pintype "bidirectional"))
    )
    (net (code "1108") (name "ZZ.08.074") (class "Default")
      (node (ref "U$9") (pin "P$156") (pinfunction "F6_P$156") (pintype "bidirectional"))
    )
    (net (code "1109") (name "ZZ.08.075") (class "Default")
      (node (ref "U$9") (pin "P$67") (pinfunction "C7_P$67") (pintype "bidirectional"))
    )
    (net (code "1110") (name "ZZ.08.076") (class "Default")
      (node (ref "U$9") (pin "P$97") (pinfunction "D7_P$97") (pintype "bidirectional"))
    )
    (net (code "1111") (name "ZZ.08.077") (class "Default")
      (node (ref "U$9") (pin "P$157") (pinfunction "F7_P$157") (pintype "bidirectional"))
    )
    (net (code "1112") (name "ZZ.08.078") (class "Default")
      (node (ref "U$9") (pin "P$68") (pinfunction "C8_P$68") (pintype "bidirectional"))
    )
    (net (code "1113") (name "ZZ.08.079") (class "Default")
      (node (ref "U$9") (pin "P$158") (pinfunction "F8_P$158") (pintype "bidirectional"))
    )
    (net (code "1114") (name "ZZ.08.080") (class "Default")
      (node (ref "U$11") (pin "P$94") (pinfunction "D4_P$94") (pintype "bidirectional"))
    )
    (net (code "1115") (name "ZZ.08.081") (class "Default")
      (node (ref "U$11") (pin "P$124") (pinfunction "E4_P$124") (pintype "bidirectional"))
    )
    (net (code "1116") (name "ZZ.08.082") (class "Default")
      (node (ref "U$11") (pin "P$154") (pinfunction "F4_P$154") (pintype "bidirectional"))
    )
    (net (code "1117") (name "ZZ.08.083") (class "Default")
      (node (ref "U$11") (pin "P$33") (pinfunction "B3_P$33") (pintype "bidirectional"))
    )
    (net (code "1118") (name "ZZ.08.084") (class "Default")
      (node (ref "U$11") (pin "P$63") (pinfunction "C3_P$63") (pintype "bidirectional"))
    )
    (net (code "1119") (name "ZZ.08.085") (class "Default")
      (node (ref "U$11") (pin "P$64") (pinfunction "C4_P$64") (pintype "bidirectional"))
    )
    (net (code "1120") (name "ZZ.08.086") (class "Default")
      (node (ref "U$11") (pin "P$95") (pinfunction "D5_P$95") (pintype "bidirectional"))
    )
    (net (code "1121") (name "ZZ.08.087") (class "Default")
      (node (ref "U$11") (pin "P$125") (pinfunction "E5_P$125") (pintype "bidirectional"))
    )
    (net (code "1122") (name "ZZ.08.088") (class "Default")
      (node (ref "U$11") (pin "P$66") (pinfunction "C6_P$66") (pintype "bidirectional"))
    )
    (net (code "1123") (name "ZZ.08.089") (class "Default")
      (node (ref "U$11") (pin "P$96") (pinfunction "D6_P$96") (pintype "bidirectional"))
    )
    (net (code "1124") (name "ZZ.08.090") (class "Default")
      (node (ref "U$11") (pin "P$156") (pinfunction "F6_P$156") (pintype "bidirectional"))
    )
    (net (code "1125") (name "ZZ.08.091") (class "Default")
      (node (ref "U$11") (pin "P$37") (pinfunction "B7_P$37") (pintype "bidirectional"))
    )
    (net (code "1126") (name "ZZ.08.092") (class "Default")
      (node (ref "U$11") (pin "P$97") (pinfunction "D7_P$97") (pintype "bidirectional"))
    )
    (net (code "1127") (name "ZZ.08.093") (class "Default")
      (node (ref "U$11") (pin "P$157") (pinfunction "F7_P$157") (pintype "bidirectional"))
    )
    (net (code "1128") (name "ZZ.08.094") (class "Default")
      (node (ref "U$11") (pin "P$98") (pinfunction "D8_P$98") (pintype "bidirectional"))
    )
    (net (code "1129") (name "ZZ.08.095") (class "Default")
      (node (ref "U$11") (pin "P$158") (pinfunction "F8_P$158") (pintype "bidirectional"))
    )
    (net (code "1130") (name "ZZ.08.096") (class "Default")
      (node (ref "U$13") (pin "P$33") (pinfunction "B3_P$33") (pintype "bidirectional"))
    )
    (net (code "1131") (name "ZZ.08.097") (class "Default")
      (node (ref "U$13") (pin "P$93") (pinfunction "D3_P$93") (pintype "bidirectional"))
    )
    (net (code "1132") (name "ZZ.08.098") (class "Default")
      (node (ref "U$13") (pin "P$153") (pinfunction "F3_P$153") (pintype "bidirectional"))
    )
    (net (code "1133") (name "ZZ.08.099") (class "Default")
      (node (ref "U$13") (pin "P$34") (pinfunction "B4_P$34") (pintype "bidirectional"))
    )
    (net (code "1134") (name "ZZ.08.100") (class "Default")
      (node (ref "U$13") (pin "P$124") (pinfunction "E4_P$124") (pintype "bidirectional"))
    )
    (net (code "1135") (name "ZZ.08.101") (class "Default")
      (node (ref "U$13") (pin "P$154") (pinfunction "F4_P$154") (pintype "bidirectional"))
    )
    (net (code "1136") (name "ZZ.08.102") (class "Default")
      (node (ref "U$13") (pin "P$95") (pinfunction "D5_P$95") (pintype "bidirectional"))
    )
    (net (code "1137") (name "ZZ.08.103") (class "Default")
      (node (ref "U$13") (pin "P$125") (pinfunction "E5_P$125") (pintype "bidirectional"))
    )
    (net (code "1138") (name "ZZ.08.104") (class "Default")
      (node (ref "U$13") (pin "P$66") (pinfunction "C6_P$66") (pintype "bidirectional"))
    )
    (net (code "1139") (name "ZZ.08.105") (class "Default")
      (node (ref "U$13") (pin "P$126") (pinfunction "E6_P$126") (pintype "bidirectional"))
    )
    (net (code "1140") (name "ZZ.08.106") (class "Default")
      (node (ref "U$13") (pin "P$156") (pinfunction "F6_P$156") (pintype "bidirectional"))
    )
    (net (code "1141") (name "ZZ.08.107") (class "Default")
      (node (ref "U$13") (pin "P$37") (pinfunction "B7_P$37") (pintype "bidirectional"))
    )
    (net (code "1142") (name "ZZ.08.108") (class "Default")
      (node (ref "U$13") (pin "P$97") (pinfunction "D7_P$97") (pintype "bidirectional"))
    )
    (net (code "1143") (name "ZZ.08.109") (class "Default")
      (node (ref "U$13") (pin "P$157") (pinfunction "F7_P$157") (pintype "bidirectional"))
    )
    (net (code "1144") (name "ZZ.08.110") (class "Default")
      (node (ref "U$13") (pin "P$98") (pinfunction "D8_P$98") (pintype "bidirectional"))
    )
    (net (code "1145") (name "ZZ.08.111") (class "Default")
      (node (ref "U$13") (pin "P$128") (pinfunction "E8_P$128") (pintype "bidirectional"))
    )
    (net (code "1146") (name "ZZ.08.112") (class "Default")
      (node (ref "U$15") (pin "P$63") (pinfunction "C3_P$63") (pintype "bidirectional"))
    )
    (net (code "1147") (name "ZZ.08.113") (class "Default")
      (node (ref "U$15") (pin "P$123") (pinfunction "E3_P$123") (pintype "bidirectional"))
    )
    (net (code "1148") (name "ZZ.08.114") (class "Default")
      (node (ref "U$15") (pin "P$122") (pinfunction "E2_P$122") (pintype "bidirectional"))
    )
    (net (code "1149") (name "ZZ.08.115") (class "Default")
      (node (ref "U$15") (pin "P$34") (pinfunction "B4_P$34") (pintype "bidirectional"))
    )
    (net (code "1150") (name "ZZ.08.116") (class "Default")
      (node (ref "U$15") (pin "P$94") (pinfunction "D4_P$94") (pintype "bidirectional"))
    )
    (net (code "1151") (name "ZZ.08.117") (class "Default")
      (node (ref "U$15") (pin "P$154") (pinfunction "F4_P$154") (pintype "bidirectional"))
    )
    (net (code "1152") (name "ZZ.08.118") (class "Default")
      (node (ref "U$15") (pin "P$65") (pinfunction "C5_P$65") (pintype "bidirectional"))
    )
    (net (code "1153") (name "ZZ.08.119") (class "Default")
      (node (ref "U$15") (pin "P$155") (pinfunction "F5_P$155") (pintype "bidirectional"))
    )
    (net (code "1154") (name "ZZ.08.120") (class "Default")
      (node (ref "U$15") (pin "P$66") (pinfunction "C6_P$66") (pintype "bidirectional"))
    )
    (net (code "1155") (name "ZZ.08.121") (class "Default")
      (node (ref "U$15") (pin "P$126") (pinfunction "E6_P$126") (pintype "bidirectional"))
    )
    (net (code "1156") (name "ZZ.08.122") (class "Default")
      (node (ref "U$15") (pin "P$156") (pinfunction "F6_P$156") (pintype "bidirectional"))
    )
    (net (code "1157") (name "ZZ.08.123") (class "Default")
      (node (ref "U$15") (pin "P$37") (pinfunction "B7_P$37") (pintype "bidirectional"))
    )
    (net (code "1158") (name "ZZ.08.124") (class "Default")
      (node (ref "U$15") (pin "P$97") (pinfunction "D7_P$97") (pintype "bidirectional"))
    )
    (net (code "1159") (name "ZZ.08.125") (class "Default")
      (node (ref "U$15") (pin "P$157") (pinfunction "F7_P$157") (pintype "bidirectional"))
    )
    (net (code "1160") (name "ZZ.08.126") (class "Default")
      (node (ref "U$15") (pin "P$68") (pinfunction "C8_P$68") (pintype "bidirectional"))
    )
    (net (code "1161") (name "ZZ.08.127") (class "Default")
      (node (ref "U$15") (pin "P$128") (pinfunction "E8_P$128") (pintype "bidirectional"))
    )
    (net (code "1162") (name "ZZ.09.000") (class "Default")
      (node (ref "U$1") (pin "P$68") (pinfunction "C8_P$68") (pintype "bidirectional"))
    )
    (net (code "1163") (name "ZZ.09.001") (class "Default")
      (node (ref "U$1") (pin "P$128") (pinfunction "E8_P$128") (pintype "bidirectional"))
    )
    (net (code "1164") (name "ZZ.09.002") (class "Default")
      (node (ref "U$1") (pin "P$37") (pinfunction "B7_P$37") (pintype "bidirectional"))
    )
    (net (code "1165") (name "ZZ.09.003") (class "Default")
      (node (ref "U$1") (pin "P$67") (pinfunction "C7_P$67") (pintype "bidirectional"))
    )
    (net (code "1166") (name "ZZ.09.004") (class "Default")
      (node (ref "U$1") (pin "P$157") (pinfunction "F7_P$157") (pintype "bidirectional"))
    )
    (net (code "1167") (name "ZZ.09.005") (class "Default")
      (node (ref "U$1") (pin "P$66") (pinfunction "C6_P$66") (pintype "bidirectional"))
    )
    (net (code "1168") (name "ZZ.09.006") (class "Default")
      (node (ref "U$1") (pin "P$96") (pinfunction "D6_P$96") (pintype "bidirectional"))
    )
    (net (code "1169") (name "ZZ.09.007") (class "Default")
      (node (ref "U$1") (pin "P$152") (pinfunction "F2_P$152") (pintype "bidirectional"))
    )
    (net (code "1170") (name "ZZ.09.008") (class "Default")
      (node (ref "U$1") (pin "P$65") (pinfunction "C5_P$65") (pintype "bidirectional"))
    )
    (net (code "1171") (name "ZZ.09.009") (class "Default")
      (node (ref "U$1") (pin "P$125") (pinfunction "E5_P$125") (pintype "bidirectional"))
    )
    (net (code "1172") (name "ZZ.09.010") (class "Default")
      (node (ref "U$1") (pin "P$154") (pinfunction "F4_P$154") (pintype "bidirectional"))
    )
    (net (code "1173") (name "ZZ.09.011") (class "Default")
      (node (ref "U$1") (pin "P$153") (pinfunction "F3_P$153") (pintype "bidirectional"))
    )
    (net (code "1174") (name "ZZ.09.012") (class "Default")
      (node (ref "U$1") (pin "P$33") (pinfunction "B3_P$33") (pintype "bidirectional"))
    )
    (net (code "1175") (name "ZZ.09.013") (class "Default")
      (node (ref "U$1") (pin "P$63") (pinfunction "C3_P$63") (pintype "bidirectional"))
    )
    (net (code "1176") (name "ZZ.09.014") (class "Default")
      (node (ref "U$1") (pin "P$93") (pinfunction "D3_P$93") (pintype "bidirectional"))
    )
    (net (code "1177") (name "ZZ.09.015") (class "Default")
      (node (ref "U$1") (pin "P$123") (pinfunction "E3_P$123") (pintype "bidirectional"))
    )
    (net (code "1178") (name "ZZ.09.016") (class "Default")
      (node (ref "U$3") (pin "P$68") (pinfunction "C8_P$68") (pintype "bidirectional"))
    )
    (net (code "1179") (name "ZZ.09.017") (class "Default")
      (node (ref "U$3") (pin "P$128") (pinfunction "E8_P$128") (pintype "bidirectional"))
    )
    (net (code "1180") (name "ZZ.09.018") (class "Default")
      (node (ref "U$3") (pin "P$37") (pinfunction "B7_P$37") (pintype "bidirectional"))
    )
    (net (code "1181") (name "ZZ.09.019") (class "Default")
      (node (ref "U$3") (pin "P$67") (pinfunction "C7_P$67") (pintype "bidirectional"))
    )
    (net (code "1182") (name "ZZ.09.020") (class "Default")
      (node (ref "U$3") (pin "P$157") (pinfunction "F7_P$157") (pintype "bidirectional"))
    )
    (net (code "1183") (name "ZZ.09.021") (class "Default")
      (node (ref "U$3") (pin "P$36") (pinfunction "B6_P$36") (pintype "bidirectional"))
    )
    (net (code "1184") (name "ZZ.09.022") (class "Default")
      (node (ref "U$3") (pin "P$96") (pinfunction "D6_P$96") (pintype "bidirectional"))
    )
    (net (code "1185") (name "ZZ.09.023") (class "Default")
      (node (ref "U$3") (pin "P$35") (pinfunction "B5_P$35") (pintype "bidirectional"))
    )
    (net (code "1186") (name "ZZ.09.024") (class "Default")
      (node (ref "U$3") (pin "P$95") (pinfunction "D5_P$95") (pintype "bidirectional"))
    )
    (net (code "1187") (name "ZZ.09.025") (class "Default")
      (node (ref "U$3") (pin "P$33") (pinfunction "B3_P$33") (pintype "bidirectional"))
    )
    (net (code "1188") (name "ZZ.09.026") (class "Default")
      (node (ref "U$3") (pin "P$63") (pinfunction "C3_P$63") (pintype "bidirectional"))
    )
    (net (code "1189") (name "ZZ.09.027") (class "Default")
      (node (ref "U$3") (pin "P$93") (pinfunction "D3_P$93") (pintype "bidirectional"))
    )
    (net (code "1190") (name "ZZ.09.028") (class "Default")
      (node (ref "U$3") (pin "P$123") (pinfunction "E3_P$123") (pintype "bidirectional"))
    )
    (net (code "1191") (name "ZZ.09.029") (class "Default")
      (node (ref "U$3") (pin "P$153") (pinfunction "F3_P$153") (pintype "bidirectional"))
    )
    (net (code "1192") (name "ZZ.09.030") (class "Default")
      (node (ref "U$3") (pin "P$122") (pinfunction "E2_P$122") (pintype "bidirectional"))
    )
    (net (code "1193") (name "ZZ.09.031") (class "Default")
      (node (ref "U$3") (pin "P$152") (pinfunction "F2_P$152") (pintype "bidirectional"))
    )
    (net (code "1194") (name "ZZ.09.032") (class "Default")
      (node (ref "U$5") (pin "P$38") (pinfunction "B8_P$38") (pintype "bidirectional"))
    )
    (net (code "1195") (name "ZZ.09.033") (class "Default")
      (node (ref "U$5") (pin "P$98") (pinfunction "D8_P$98") (pintype "bidirectional"))
    )
    (net (code "1196") (name "ZZ.09.034") (class "Default")
      (node (ref "U$5") (pin "P$37") (pinfunction "B7_P$37") (pintype "bidirectional"))
    )
    (net (code "1197") (name "ZZ.09.035") (class "Default")
      (node (ref "U$5") (pin "P$67") (pinfunction "C7_P$67") (pintype "bidirectional"))
    )
    (net (code "1198") (name "ZZ.09.036") (class "Default")
      (node (ref "U$5") (pin "P$66") (pinfunction "C6_P$66") (pintype "bidirectional"))
    )
    (net (code "1199") (name "ZZ.09.037") (class "Default")
      (node (ref "U$5") (pin "P$35") (pinfunction "B5_P$35") (pintype "bidirectional"))
    )
    (net (code "1200") (name "ZZ.09.038") (class "Default")
      (node (ref "U$5") (pin "P$65") (pinfunction "C5_P$65") (pintype "bidirectional"))
    )
    (net (code "1201") (name "ZZ.09.039") (class "Default")
      (node (ref "U$5") (pin "P$33") (pinfunction "B3_P$33") (pintype "bidirectional"))
    )
    (net (code "1202") (name "ZZ.09.040") (class "Default")
      (node (ref "U$5") (pin "P$63") (pinfunction "C3_P$63") (pintype "bidirectional"))
    )
    (net (code "1203") (name "ZZ.09.041") (class "Default")
      (node (ref "U$5") (pin "P$93") (pinfunction "D3_P$93") (pintype "bidirectional"))
    )
    (net (code "1204") (name "ZZ.09.042") (class "Default")
      (node (ref "U$5") (pin "P$123") (pinfunction "E3_P$123") (pintype "bidirectional"))
    )
    (net (code "1205") (name "ZZ.09.043") (class "Default")
      (node (ref "U$5") (pin "P$153") (pinfunction "F3_P$153") (pintype "bidirectional"))
    )
    (net (code "1206") (name "ZZ.09.044") (class "Default")
      (node (ref "U$5") (pin "P$122") (pinfunction "E2_P$122") (pintype "bidirectional"))
    )
    (net (code "1207") (name "ZZ.09.045") (class "Default")
      (node (ref "U$5") (pin "P$126") (pinfunction "E6_P$126") (pintype "bidirectional"))
    )
    (net (code "1208") (name "ZZ.09.046") (class "Default")
      (node (ref "U$5") (pin "P$156") (pinfunction "F6_P$156") (pintype "bidirectional"))
    )
    (net (code "1209") (name "ZZ.09.047") (class "Default")
      (node (ref "U$5") (pin "P$127") (pinfunction "E7_P$127") (pintype "bidirectional"))
    )
    (net (code "1210") (name "ZZ.09.048") (class "Default")
      (node (ref "U$7") (pin "P$37") (pinfunction "B7_P$37") (pintype "bidirectional"))
    )
    (net (code "1211") (name "ZZ.09.049") (class "Default")
      (node (ref "U$7") (pin "P$36") (pinfunction "B6_P$36") (pintype "bidirectional"))
    )
    (net (code "1212") (name "ZZ.09.050") (class "Default")
      (node (ref "U$7") (pin "P$35") (pinfunction "B5_P$35") (pintype "bidirectional"))
    )
    (net (code "1213") (name "ZZ.09.051") (class "Default")
      (node (ref "U$7") (pin "P$65") (pinfunction "C5_P$65") (pintype "bidirectional"))
    )
    (net (code "1214") (name "ZZ.09.052") (class "Default")
      (node (ref "U$7") (pin "P$33") (pinfunction "B3_P$33") (pintype "bidirectional"))
    )
    (net (code "1215") (name "ZZ.09.053") (class "Default")
      (node (ref "U$7") (pin "P$63") (pinfunction "C3_P$63") (pintype "bidirectional"))
    )
    (net (code "1216") (name "ZZ.09.054") (class "Default")
      (node (ref "U$7") (pin "P$93") (pinfunction "D3_P$93") (pintype "bidirectional"))
    )
    (net (code "1217") (name "ZZ.09.055") (class "Default")
      (node (ref "U$7") (pin "P$123") (pinfunction "E3_P$123") (pintype "bidirectional"))
    )
    (net (code "1218") (name "ZZ.09.056") (class "Default")
      (node (ref "U$7") (pin "P$153") (pinfunction "F3_P$153") (pintype "bidirectional"))
    )
    (net (code "1219") (name "ZZ.09.057") (class "Default")
      (node (ref "U$7") (pin "P$122") (pinfunction "E2_P$122") (pintype "bidirectional"))
    )
    (net (code "1220") (name "ZZ.09.058") (class "Default")
      (node (ref "U$7") (pin "P$126") (pinfunction "E6_P$126") (pintype "bidirectional"))
    )
    (net (code "1221") (name "ZZ.09.059") (class "Default")
      (node (ref "U$7") (pin "P$156") (pinfunction "F6_P$156") (pintype "bidirectional"))
    )
    (net (code "1222") (name "ZZ.09.060") (class "Default")
      (node (ref "U$7") (pin "P$97") (pinfunction "D7_P$97") (pintype "bidirectional"))
    )
    (net (code "1223") (name "ZZ.09.061") (class "Default")
      (node (ref "U$7") (pin "P$38") (pinfunction "B8_P$38") (pintype "bidirectional"))
    )
    (net (code "1224") (name "ZZ.09.062") (class "Default")
      (node (ref "U$7") (pin "P$68") (pinfunction "C8_P$68") (pintype "bidirectional"))
    )
    (net (code "1225") (name "ZZ.09.063") (class "Default")
      (node (ref "U$7") (pin "P$128") (pinfunction "E8_P$128") (pintype "bidirectional"))
    )
    (net (code "1226") (name "ZZ.09.064") (class "Default")
      (node (ref "U$9") (pin "P$35") (pinfunction "B5_P$35") (pintype "bidirectional"))
    )
    (net (code "1227") (name "ZZ.09.065") (class "Default")
      (node (ref "U$9") (pin "P$33") (pinfunction "B3_P$33") (pintype "bidirectional"))
    )
    (net (code "1228") (name "ZZ.09.066") (class "Default")
      (node (ref "U$9") (pin "P$63") (pinfunction "C3_P$63") (pintype "bidirectional"))
    )
    (net (code "1229") (name "ZZ.09.067") (class "Default")
      (node (ref "U$9") (pin "P$93") (pinfunction "D3_P$93") (pintype "bidirectional"))
    )
    (net (code "1230") (name "ZZ.09.068") (class "Default")
      (node (ref "U$9") (pin "P$123") (pinfunction "E3_P$123") (pintype "bidirectional"))
    )
    (net (code "1231") (name "ZZ.09.069") (class "Default")
      (node (ref "U$9") (pin "P$153") (pinfunction "F3_P$153") (pintype "bidirectional"))
    )
    (net (code "1232") (name "ZZ.09.070") (class "Default")
      (node (ref "U$9") (pin "P$122") (pinfunction "E2_P$122") (pintype "bidirectional"))
    )
    (net (code "1233") (name "ZZ.09.071") (class "Default")
      (node (ref "U$9") (pin "P$125") (pinfunction "E5_P$125") (pintype "bidirectional"))
    )
    (net (code "1234") (name "ZZ.09.072") (class "Default")
      (node (ref "U$9") (pin "P$66") (pinfunction "C6_P$66") (pintype "bidirectional"))
    )
    (net (code "1235") (name "ZZ.09.073") (class "Default")
      (node (ref "U$9") (pin "P$96") (pinfunction "D6_P$96") (pintype "bidirectional"))
    )
    (net (code "1236") (name "ZZ.09.074") (class "Default")
      (node (ref "U$9") (pin "P$152") (pinfunction "F2_P$152") (pintype "bidirectional"))
    )
    (net (code "1237") (name "ZZ.09.075") (class "Default")
      (node (ref "U$9") (pin "P$37") (pinfunction "B7_P$37") (pintype "bidirectional"))
    )
    (net (code "1238") (name "ZZ.09.076") (class "Default")
      (node (ref "U$9") (pin "P$127") (pinfunction "E7_P$127") (pintype "bidirectional"))
    )
    (net (code "1239") (name "ZZ.09.077") (class "Default")
      (node (ref "U$9") (pin "P$38") (pinfunction "B8_P$38") (pintype "bidirectional"))
    )
    (net (code "1240") (name "ZZ.09.078") (class "Default")
      (node (ref "U$9") (pin "P$98") (pinfunction "D8_P$98") (pintype "bidirectional"))
    )
    (net (code "1241") (name "ZZ.09.079") (class "Default")
      (node (ref "U$9") (pin "P$128") (pinfunction "E8_P$128") (pintype "bidirectional"))
    )
    (net (code "1242") (name "ZZ.09.080") (class "Default")
      (node (ref "U$11") (pin "P$93") (pinfunction "D3_P$93") (pintype "bidirectional"))
    )
    (net (code "1243") (name "ZZ.09.081") (class "Default")
      (node (ref "U$11") (pin "P$123") (pinfunction "E3_P$123") (pintype "bidirectional"))
    )
    (net (code "1244") (name "ZZ.09.082") (class "Default")
      (node (ref "U$11") (pin "P$153") (pinfunction "F3_P$153") (pintype "bidirectional"))
    )
    (net (code "1245") (name "ZZ.09.083") (class "Default")
      (node (ref "U$11") (pin "P$122") (pinfunction "E2_P$122") (pintype "bidirectional"))
    )
    (net (code "1246") (name "ZZ.09.084") (class "Default")
      (node (ref "U$11") (pin "P$34") (pinfunction "B4_P$34") (pintype "bidirectional"))
    )
    (net (code "1247") (name "ZZ.09.085") (class "Default")
      (node (ref "U$11") (pin "P$35") (pinfunction "B5_P$35") (pintype "bidirectional"))
    )
    (net (code "1248") (name "ZZ.09.086") (class "Default")
      (node (ref "U$11") (pin "P$65") (pinfunction "C5_P$65") (pintype "bidirectional"))
    )
    (net (code "1249") (name "ZZ.09.087") (class "Default")
      (node (ref "U$11") (pin "P$155") (pinfunction "F5_P$155") (pintype "bidirectional"))
    )
    (net (code "1250") (name "ZZ.09.088") (class "Default")
      (node (ref "U$11") (pin "P$36") (pinfunction "B6_P$36") (pintype "bidirectional"))
    )
    (net (code "1251") (name "ZZ.09.089") (class "Default")
      (node (ref "U$11") (pin "P$126") (pinfunction "E6_P$126") (pintype "bidirectional"))
    )
    (net (code "1252") (name "ZZ.09.090") (class "Default")
      (node (ref "U$11") (pin "P$152") (pinfunction "F2_P$152") (pintype "bidirectional"))
    )
    (net (code "1253") (name "ZZ.09.091") (class "Default")
      (node (ref "U$11") (pin "P$67") (pinfunction "C7_P$67") (pintype "bidirectional"))
    )
    (net (code "1254") (name "ZZ.09.092") (class "Default")
      (node (ref "U$11") (pin "P$127") (pinfunction "E7_P$127") (pintype "bidirectional"))
    )
    (net (code "1255") (name "ZZ.09.093") (class "Default")
      (node (ref "U$11") (pin "P$38") (pinfunction "B8_P$38") (pintype "bidirectional"))
    )
    (net (code "1256") (name "ZZ.09.094") (class "Default")
      (node (ref "U$11") (pin "P$68") (pinfunction "C8_P$68") (pintype "bidirectional"))
    )
    (net (code "1257") (name "ZZ.09.095") (class "Default")
      (node (ref "U$11") (pin "P$128") (pinfunction "E8_P$128") (pintype "bidirectional"))
    )
    (net (code "1258") (name "ZZ.09.096") (class "Default")
      (node (ref "U$13") (pin "P$122") (pinfunction "E2_P$122") (pintype "bidirectional"))
    )
    (net (code "1259") (name "ZZ.09.097") (class "Default")
      (node (ref "U$13") (pin "P$63") (pinfunction "C3_P$63") (pintype "bidirectional"))
    )
    (net (code "1260") (name "ZZ.09.098") (class "Default")
      (node (ref "U$13") (pin "P$123") (pinfunction "E3_P$123") (pintype "bidirectional"))
    )
    (net (code "1261") (name "ZZ.09.099") (class "Default")
      (node (ref "U$13") (pin "P$64") (pinfunction "C4_P$64") (pintype "bidirectional"))
    )
    (net (code "1262") (name "ZZ.09.100") (class "Default")
      (node (ref "U$13") (pin "P$94") (pinfunction "D4_P$94") (pintype "bidirectional"))
    )
    (net (code "1263") (name "ZZ.09.101") (class "Default")
      (node (ref "U$13") (pin "P$35") (pinfunction "B5_P$35") (pintype "bidirectional"))
    )
    (net (code "1264") (name "ZZ.09.102") (class "Default")
      (node (ref "U$13") (pin "P$65") (pinfunction "C5_P$65") (pintype "bidirectional"))
    )
    (net (code "1265") (name "ZZ.09.103") (class "Default")
      (node (ref "U$13") (pin "P$155") (pinfunction "F5_P$155") (pintype "bidirectional"))
    )
    (net (code "1266") (name "ZZ.09.104") (class "Default")
      (node (ref "U$13") (pin "P$36") (pinfunction "B6_P$36") (pintype "bidirectional"))
    )
    (net (code "1267") (name "ZZ.09.105") (class "Default")
      (node (ref "U$13") (pin "P$96") (pinfunction "D6_P$96") (pintype "bidirectional"))
    )
    (net (code "1268") (name "ZZ.09.106") (class "Default")
      (node (ref "U$13") (pin "P$152") (pinfunction "F2_P$152") (pintype "bidirectional"))
    )
    (net (code "1269") (name "ZZ.09.107") (class "Default")
      (node (ref "U$13") (pin "P$67") (pinfunction "C7_P$67") (pintype "bidirectional"))
    )
    (net (code "1270") (name "ZZ.09.108") (class "Default")
      (node (ref "U$13") (pin "P$127") (pinfunction "E7_P$127") (pintype "bidirectional"))
    )
    (net (code "1271") (name "ZZ.09.109") (class "Default")
      (node (ref "U$13") (pin "P$38") (pinfunction "B8_P$38") (pintype "bidirectional"))
    )
    (net (code "1272") (name "ZZ.09.110") (class "Default")
      (node (ref "U$13") (pin "P$68") (pinfunction "C8_P$68") (pintype "bidirectional"))
    )
    (net (code "1273") (name "ZZ.09.111") (class "Default")
      (node (ref "U$13") (pin "P$158") (pinfunction "F8_P$158") (pintype "bidirectional"))
    )
    (net (code "1274") (name "ZZ.09.112") (class "Default")
      (node (ref "U$15") (pin "P$33") (pinfunction "B3_P$33") (pintype "bidirectional"))
    )
    (net (code "1275") (name "ZZ.09.113") (class "Default")
      (node (ref "U$15") (pin "P$93") (pinfunction "D3_P$93") (pintype "bidirectional"))
    )
    (net (code "1276") (name "ZZ.09.114") (class "Default")
      (node (ref "U$15") (pin "P$153") (pinfunction "F3_P$153") (pintype "bidirectional"))
    )
    (net (code "1277") (name "ZZ.09.115") (class "Default")
      (node (ref "U$15") (pin "P$64") (pinfunction "C4_P$64") (pintype "bidirectional"))
    )
    (net (code "1278") (name "ZZ.09.116") (class "Default")
      (node (ref "U$15") (pin "P$124") (pinfunction "E4_P$124") (pintype "bidirectional"))
    )
    (net (code "1279") (name "ZZ.09.117") (class "Default")
      (node (ref "U$15") (pin "P$35") (pinfunction "B5_P$35") (pintype "bidirectional"))
    )
    (net (code "1280") (name "ZZ.09.118") (class "Default")
      (node (ref "U$15") (pin "P$95") (pinfunction "D5_P$95") (pintype "bidirectional"))
    )
    (net (code "1281") (name "ZZ.09.119") (class "Default")
      (node (ref "U$15") (pin "P$125") (pinfunction "E5_P$125") (pintype "bidirectional"))
    )
    (net (code "1282") (name "ZZ.09.120") (class "Default")
      (node (ref "U$15") (pin "P$36") (pinfunction "B6_P$36") (pintype "bidirectional"))
    )
    (net (code "1283") (name "ZZ.09.121") (class "Default")
      (node (ref "U$15") (pin "P$96") (pinfunction "D6_P$96") (pintype "bidirectional"))
    )
    (net (code "1284") (name "ZZ.09.122") (class "Default")
      (node (ref "U$15") (pin "P$152") (pinfunction "F2_P$152") (pintype "bidirectional"))
    )
    (net (code "1285") (name "ZZ.09.123") (class "Default")
      (node (ref "U$15") (pin "P$67") (pinfunction "C7_P$67") (pintype "bidirectional"))
    )
    (net (code "1286") (name "ZZ.09.124") (class "Default")
      (node (ref "U$15") (pin "P$127") (pinfunction "E7_P$127") (pintype "bidirectional"))
    )
    (net (code "1287") (name "ZZ.09.125") (class "Default")
      (node (ref "U$15") (pin "P$38") (pinfunction "B8_P$38") (pintype "bidirectional"))
    )
    (net (code "1288") (name "ZZ.09.126") (class "Default")
      (node (ref "U$15") (pin "P$98") (pinfunction "D8_P$98") (pintype "bidirectional"))
    )
    (net (code "1289") (name "ZZ.09.127") (class "Default")
      (node (ref "U$15") (pin "P$158") (pinfunction "F8_P$158") (pintype "bidirectional"))
    )
    (net (code "1290") (name "ZZ.10.000") (class "Default")
      (node (ref "U$1") (pin "P$42") (pinfunction "B12_P$42") (pintype "bidirectional"))
    )
    (net (code "1291") (name "ZZ.10.001") (class "Default")
      (node (ref "U$1") (pin "P$72") (pinfunction "C12_P$72") (pintype "bidirectional"))
    )
    (net (code "1292") (name "ZZ.10.002") (class "Default")
      (node (ref "U$1") (pin "P$102") (pinfunction "D12_P$102") (pintype "bidirectional"))
    )
    (net (code "1293") (name "ZZ.10.003") (class "Default")
      (node (ref "U$1") (pin "P$132") (pinfunction "E12_P$132") (pintype "bidirectional"))
    )
    (net (code "1294") (name "ZZ.10.004") (class "Default")
      (node (ref "U$1") (pin "P$162") (pinfunction "F12_P$162") (pintype "bidirectional"))
    )
    (net (code "1295") (name "ZZ.10.005") (class "Default")
      (node (ref "U$1") (pin "P$41") (pinfunction "B11_P$41") (pintype "bidirectional"))
    )
    (net (code "1296") (name "ZZ.10.006") (class "Default")
      (node (ref "U$1") (pin "P$71") (pinfunction "C11_P$71") (pintype "bidirectional"))
    )
    (net (code "1297") (name "ZZ.10.007") (class "Default")
      (node (ref "U$1") (pin "P$101") (pinfunction "D11_P$101") (pintype "bidirectional"))
    )
    (net (code "1298") (name "ZZ.10.008") (class "Default")
      (node (ref "U$1") (pin "P$131") (pinfunction "E11_P$131") (pintype "bidirectional"))
    )
    (net (code "1299") (name "ZZ.10.009") (class "Default")
      (node (ref "U$1") (pin "P$161") (pinfunction "F11_P$161") (pintype "bidirectional"))
    )
    (net (code "1300") (name "ZZ.10.010") (class "Default")
      (node (ref "U$1") (pin "P$40") (pinfunction "B10_P$40") (pintype "bidirectional"))
    )
    (net (code "1301") (name "ZZ.10.011") (class "Default")
      (node (ref "U$1") (pin "P$70") (pinfunction "C10_P$70") (pintype "bidirectional"))
    )
    (net (code "1302") (name "ZZ.10.012") (class "Default")
      (node (ref "U$1") (pin "P$100") (pinfunction "D10_P$100") (pintype "bidirectional"))
    )
    (net (code "1303") (name "ZZ.10.013") (class "Default")
      (node (ref "U$1") (pin "P$130") (pinfunction "E10_P$130") (pintype "bidirectional"))
    )
    (net (code "1304") (name "ZZ.10.014") (class "Default")
      (node (ref "U$1") (pin "P$160") (pinfunction "F10_P$160") (pintype "bidirectional"))
    )
    (net (code "1305") (name "ZZ.10.015") (class "Default")
      (node (ref "U$1") (pin "P$129") (pinfunction "E9_P$129") (pintype "bidirectional"))
    )
    (net (code "1306") (name "ZZ.10.016") (class "Default")
      (node (ref "U$3") (pin "P$42") (pinfunction "B12_P$42") (pintype "bidirectional"))
    )
    (net (code "1307") (name "ZZ.10.017") (class "Default")
      (node (ref "U$3") (pin "P$72") (pinfunction "C12_P$72") (pintype "bidirectional"))
    )
    (net (code "1308") (name "ZZ.10.018") (class "Default")
      (node (ref "U$3") (pin "P$102") (pinfunction "D12_P$102") (pintype "bidirectional"))
    )
    (net (code "1309") (name "ZZ.10.019") (class "Default")
      (node (ref "U$3") (pin "P$132") (pinfunction "E12_P$132") (pintype "bidirectional"))
    )
    (net (code "1310") (name "ZZ.10.020") (class "Default")
      (node (ref "U$3") (pin "P$162") (pinfunction "F12_P$162") (pintype "bidirectional"))
    )
    (net (code "1311") (name "ZZ.10.021") (class "Default")
      (node (ref "U$3") (pin "P$41") (pinfunction "B11_P$41") (pintype "bidirectional"))
    )
    (net (code "1312") (name "ZZ.10.022") (class "Default")
      (node (ref "U$3") (pin "P$71") (pinfunction "C11_P$71") (pintype "bidirectional"))
    )
    (net (code "1313") (name "ZZ.10.023") (class "Default")
      (node (ref "U$3") (pin "P$101") (pinfunction "D11_P$101") (pintype "bidirectional"))
    )
    (net (code "1314") (name "ZZ.10.024") (class "Default")
      (node (ref "U$3") (pin "P$40") (pinfunction "B10_P$40") (pintype "bidirectional"))
    )
    (net (code "1315") (name "ZZ.10.025") (class "Default")
      (node (ref "U$3") (pin "P$70") (pinfunction "C10_P$70") (pintype "bidirectional"))
    )
    (net (code "1316") (name "ZZ.10.026") (class "Default")
      (node (ref "U$3") (pin "P$100") (pinfunction "D10_P$100") (pintype "bidirectional"))
    )
    (net (code "1317") (name "ZZ.10.027") (class "Default")
      (node (ref "U$3") (pin "P$130") (pinfunction "E10_P$130") (pintype "bidirectional"))
    )
    (net (code "1318") (name "ZZ.10.028") (class "Default")
      (node (ref "U$3") (pin "P$160") (pinfunction "F10_P$160") (pintype "bidirectional"))
    )
    (net (code "1319") (name "ZZ.10.029") (class "Default")
      (node (ref "U$3") (pin "P$129") (pinfunction "E9_P$129") (pintype "bidirectional"))
    )
    (net (code "1320") (name "ZZ.10.030") (class "Default")
      (node (ref "U$3") (pin "P$131") (pinfunction "E11_P$131") (pintype "bidirectional"))
    )
    (net (code "1321") (name "ZZ.10.031") (class "Default")
      (node (ref "U$3") (pin "P$161") (pinfunction "F11_P$161") (pintype "bidirectional"))
    )
    (net (code "1322") (name "ZZ.10.032") (class "Default")
      (node (ref "U$5") (pin "P$42") (pinfunction "B12_P$42") (pintype "bidirectional"))
    )
    (net (code "1323") (name "ZZ.10.033") (class "Default")
      (node (ref "U$5") (pin "P$72") (pinfunction "C12_P$72") (pintype "bidirectional"))
    )
    (net (code "1324") (name "ZZ.10.034") (class "Default")
      (node (ref "U$5") (pin "P$102") (pinfunction "D12_P$102") (pintype "bidirectional"))
    )
    (net (code "1325") (name "ZZ.10.035") (class "Default")
      (node (ref "U$5") (pin "P$132") (pinfunction "E12_P$132") (pintype "bidirectional"))
    )
    (net (code "1326") (name "ZZ.10.036") (class "Default")
      (node (ref "U$5") (pin "P$41") (pinfunction "B11_P$41") (pintype "bidirectional"))
    )
    (net (code "1327") (name "ZZ.10.037") (class "Default")
      (node (ref "U$5") (pin "P$71") (pinfunction "C11_P$71") (pintype "bidirectional"))
    )
    (net (code "1328") (name "ZZ.10.038") (class "Default")
      (node (ref "U$5") (pin "P$40") (pinfunction "B10_P$40") (pintype "bidirectional"))
    )
    (net (code "1329") (name "ZZ.10.039") (class "Default")
      (node (ref "U$5") (pin "P$70") (pinfunction "C10_P$70") (pintype "bidirectional"))
    )
    (net (code "1330") (name "ZZ.10.040") (class "Default")
      (node (ref "U$5") (pin "P$100") (pinfunction "D10_P$100") (pintype "bidirectional"))
    )
    (net (code "1331") (name "ZZ.10.041") (class "Default")
      (node (ref "U$5") (pin "P$130") (pinfunction "E10_P$130") (pintype "bidirectional"))
    )
    (net (code "1332") (name "ZZ.10.042") (class "Default")
      (node (ref "U$5") (pin "P$160") (pinfunction "F10_P$160") (pintype "bidirectional"))
    )
    (net (code "1333") (name "ZZ.10.043") (class "Default")
      (node (ref "U$5") (pin "P$129") (pinfunction "E9_P$129") (pintype "bidirectional"))
    )
    (net (code "1334") (name "ZZ.10.044") (class "Default")
      (node (ref "U$5") (pin "P$101") (pinfunction "D11_P$101") (pintype "bidirectional"))
    )
    (net (code "1335") (name "ZZ.10.045") (class "Default")
      (node (ref "U$5") (pin "P$131") (pinfunction "E11_P$131") (pintype "bidirectional"))
    )
    (net (code "1336") (name "ZZ.10.046") (class "Default")
      (node (ref "U$5") (pin "P$161") (pinfunction "F11_P$161") (pintype "bidirectional"))
    )
    (net (code "1337") (name "ZZ.10.047") (class "Default")
      (node (ref "U$5") (pin "P$162") (pinfunction "F12_P$162") (pintype "bidirectional"))
    )
    (net (code "1338") (name "ZZ.10.048") (class "Default")
      (node (ref "U$7") (pin "P$42") (pinfunction "B12_P$42") (pintype "bidirectional"))
    )
    (net (code "1339") (name "ZZ.10.049") (class "Default")
      (node (ref "U$7") (pin "P$41") (pinfunction "B11_P$41") (pintype "bidirectional"))
    )
    (net (code "1340") (name "ZZ.10.050") (class "Default")
      (node (ref "U$7") (pin "P$71") (pinfunction "C11_P$71") (pintype "bidirectional"))
    )
    (net (code "1341") (name "ZZ.10.051") (class "Default")
      (node (ref "U$7") (pin "P$40") (pinfunction "B10_P$40") (pintype "bidirectional"))
    )
    (net (code "1342") (name "ZZ.10.052") (class "Default")
      (node (ref "U$7") (pin "P$70") (pinfunction "C10_P$70") (pintype "bidirectional"))
    )
    (net (code "1343") (name "ZZ.10.053") (class "Default")
      (node (ref "U$7") (pin "P$100") (pinfunction "D10_P$100") (pintype "bidirectional"))
    )
    (net (code "1344") (name "ZZ.10.054") (class "Default")
      (node (ref "U$7") (pin "P$130") (pinfunction "E10_P$130") (pintype "bidirectional"))
    )
    (net (code "1345") (name "ZZ.10.055") (class "Default")
      (node (ref "U$7") (pin "P$160") (pinfunction "F10_P$160") (pintype "bidirectional"))
    )
    (net (code "1346") (name "ZZ.10.056") (class "Default")
      (node (ref "U$7") (pin "P$129") (pinfunction "E9_P$129") (pintype "bidirectional"))
    )
    (net (code "1347") (name "ZZ.10.057") (class "Default")
      (node (ref "U$7") (pin "P$101") (pinfunction "D11_P$101") (pintype "bidirectional"))
    )
    (net (code "1348") (name "ZZ.10.058") (class "Default")
      (node (ref "U$7") (pin "P$131") (pinfunction "E11_P$131") (pintype "bidirectional"))
    )
    (net (code "1349") (name "ZZ.10.059") (class "Default")
      (node (ref "U$7") (pin "P$161") (pinfunction "F11_P$161") (pintype "bidirectional"))
    )
    (net (code "1350") (name "ZZ.10.060") (class "Default")
      (node (ref "U$7") (pin "P$72") (pinfunction "C12_P$72") (pintype "bidirectional"))
    )
    (net (code "1351") (name "ZZ.10.061") (class "Default")
      (node (ref "U$7") (pin "P$102") (pinfunction "D12_P$102") (pintype "bidirectional"))
    )
    (net (code "1352") (name "ZZ.10.062") (class "Default")
      (node (ref "U$7") (pin "P$132") (pinfunction "E12_P$132") (pintype "bidirectional"))
    )
    (net (code "1353") (name "ZZ.10.063") (class "Default")
      (node (ref "U$7") (pin "P$162") (pinfunction "F12_P$162") (pintype "bidirectional"))
    )
    (net (code "1354") (name "ZZ.10.064") (class "Default")
      (node (ref "U$9") (pin "P$40") (pinfunction "B10_P$40") (pintype "bidirectional"))
    )
    (net (code "1355") (name "ZZ.10.065") (class "Default")
      (node (ref "U$9") (pin "P$70") (pinfunction "C10_P$70") (pintype "bidirectional"))
    )
    (net (code "1356") (name "ZZ.10.066") (class "Default")
      (node (ref "U$9") (pin "P$100") (pinfunction "D10_P$100") (pintype "bidirectional"))
    )
    (net (code "1357") (name "ZZ.10.067") (class "Default")
      (node (ref "U$9") (pin "P$130") (pinfunction "E10_P$130") (pintype "bidirectional"))
    )
    (net (code "1358") (name "ZZ.10.068") (class "Default")
      (node (ref "U$9") (pin "P$160") (pinfunction "F10_P$160") (pintype "bidirectional"))
    )
    (net (code "1359") (name "ZZ.10.069") (class "Default")
      (node (ref "U$9") (pin "P$129") (pinfunction "E9_P$129") (pintype "bidirectional"))
    )
    (net (code "1360") (name "ZZ.10.070") (class "Default")
      (node (ref "U$9") (pin "P$41") (pinfunction "B11_P$41") (pintype "bidirectional"))
    )
    (net (code "1361") (name "ZZ.10.071") (class "Default")
      (node (ref "U$9") (pin "P$71") (pinfunction "C11_P$71") (pintype "bidirectional"))
    )
    (net (code "1362") (name "ZZ.10.072") (class "Default")
      (node (ref "U$9") (pin "P$101") (pinfunction "D11_P$101") (pintype "bidirectional"))
    )
    (net (code "1363") (name "ZZ.10.073") (class "Default")
      (node (ref "U$9") (pin "P$131") (pinfunction "E11_P$131") (pintype "bidirectional"))
    )
    (net (code "1364") (name "ZZ.10.074") (class "Default")
      (node (ref "U$9") (pin "P$161") (pinfunction "F11_P$161") (pintype "bidirectional"))
    )
    (net (code "1365") (name "ZZ.10.075") (class "Default")
      (node (ref "U$9") (pin "P$42") (pinfunction "B12_P$42") (pintype "bidirectional"))
    )
    (net (code "1366") (name "ZZ.10.076") (class "Default")
      (node (ref "U$9") (pin "P$72") (pinfunction "C12_P$72") (pintype "bidirectional"))
    )
    (net (code "1367") (name "ZZ.10.077") (class "Default")
      (node (ref "U$9") (pin "P$102") (pinfunction "D12_P$102") (pintype "bidirectional"))
    )
    (net (code "1368") (name "ZZ.10.078") (class "Default")
      (node (ref "U$9") (pin "P$132") (pinfunction "E12_P$132") (pintype "bidirectional"))
    )
    (net (code "1369") (name "ZZ.10.079") (class "Default")
      (node (ref "U$9") (pin "P$162") (pinfunction "F12_P$162") (pintype "bidirectional"))
    )
    (net (code "1370") (name "ZZ.10.080") (class "Default")
      (node (ref "U$11") (pin "P$40") (pinfunction "B10_P$40") (pintype "bidirectional"))
    )
    (net (code "1371") (name "ZZ.10.081") (class "Default")
      (node (ref "U$11") (pin "P$70") (pinfunction "C10_P$70") (pintype "bidirectional"))
    )
    (net (code "1372") (name "ZZ.10.082") (class "Default")
      (node (ref "U$11") (pin "P$100") (pinfunction "D10_P$100") (pintype "bidirectional"))
    )
    (net (code "1373") (name "ZZ.10.083") (class "Default")
      (node (ref "U$11") (pin "P$130") (pinfunction "E10_P$130") (pintype "bidirectional"))
    )
    (net (code "1374") (name "ZZ.10.084") (class "Default")
      (node (ref "U$11") (pin "P$160") (pinfunction "F10_P$160") (pintype "bidirectional"))
    )
    (net (code "1375") (name "ZZ.10.085") (class "Default")
      (node (ref "U$11") (pin "P$129") (pinfunction "E9_P$129") (pintype "bidirectional"))
    )
    (net (code "1376") (name "ZZ.10.086") (class "Default")
      (node (ref "U$11") (pin "P$41") (pinfunction "B11_P$41") (pintype "bidirectional"))
    )
    (net (code "1377") (name "ZZ.10.087") (class "Default")
      (node (ref "U$11") (pin "P$71") (pinfunction "C11_P$71") (pintype "bidirectional"))
    )
    (net (code "1378") (name "ZZ.10.088") (class "Default")
      (node (ref "U$11") (pin "P$101") (pinfunction "D11_P$101") (pintype "bidirectional"))
    )
    (net (code "1379") (name "ZZ.10.089") (class "Default")
      (node (ref "U$11") (pin "P$131") (pinfunction "E11_P$131") (pintype "bidirectional"))
    )
    (net (code "1380") (name "ZZ.10.090") (class "Default")
      (node (ref "U$11") (pin "P$161") (pinfunction "F11_P$161") (pintype "bidirectional"))
    )
    (net (code "1381") (name "ZZ.10.091") (class "Default")
      (node (ref "U$11") (pin "P$42") (pinfunction "B12_P$42") (pintype "bidirectional"))
    )
    (net (code "1382") (name "ZZ.10.092") (class "Default")
      (node (ref "U$11") (pin "P$72") (pinfunction "C12_P$72") (pintype "bidirectional"))
    )
    (net (code "1383") (name "ZZ.10.093") (class "Default")
      (node (ref "U$11") (pin "P$102") (pinfunction "D12_P$102") (pintype "bidirectional"))
    )
    (net (code "1384") (name "ZZ.10.094") (class "Default")
      (node (ref "U$11") (pin "P$132") (pinfunction "E12_P$132") (pintype "bidirectional"))
    )
    (net (code "1385") (name "ZZ.10.095") (class "Default")
      (node (ref "U$11") (pin "P$162") (pinfunction "F12_P$162") (pintype "bidirectional"))
    )
    (net (code "1386") (name "ZZ.10.096") (class "Default")
      (node (ref "U$13") (pin "P$40") (pinfunction "B10_P$40") (pintype "bidirectional"))
    )
    (net (code "1387") (name "ZZ.10.097") (class "Default")
      (node (ref "U$13") (pin "P$70") (pinfunction "C10_P$70") (pintype "bidirectional"))
    )
    (net (code "1388") (name "ZZ.10.098") (class "Default")
      (node (ref "U$13") (pin "P$100") (pinfunction "D10_P$100") (pintype "bidirectional"))
    )
    (net (code "1389") (name "ZZ.10.099") (class "Default")
      (node (ref "U$13") (pin "P$130") (pinfunction "E10_P$130") (pintype "bidirectional"))
    )
    (net (code "1390") (name "ZZ.10.100") (class "Default")
      (node (ref "U$13") (pin "P$160") (pinfunction "F10_P$160") (pintype "bidirectional"))
    )
    (net (code "1391") (name "ZZ.10.101") (class "Default")
      (node (ref "U$13") (pin "P$129") (pinfunction "E9_P$129") (pintype "bidirectional"))
    )
    (net (code "1392") (name "ZZ.10.102") (class "Default")
      (node (ref "U$13") (pin "P$41") (pinfunction "B11_P$41") (pintype "bidirectional"))
    )
    (net (code "1393") (name "ZZ.10.103") (class "Default")
      (node (ref "U$13") (pin "P$71") (pinfunction "C11_P$71") (pintype "bidirectional"))
    )
    (net (code "1394") (name "ZZ.10.104") (class "Default")
      (node (ref "U$13") (pin "P$101") (pinfunction "D11_P$101") (pintype "bidirectional"))
    )
    (net (code "1395") (name "ZZ.10.105") (class "Default")
      (node (ref "U$13") (pin "P$131") (pinfunction "E11_P$131") (pintype "bidirectional"))
    )
    (net (code "1396") (name "ZZ.10.106") (class "Default")
      (node (ref "U$13") (pin "P$161") (pinfunction "F11_P$161") (pintype "bidirectional"))
    )
    (net (code "1397") (name "ZZ.10.107") (class "Default")
      (node (ref "U$13") (pin "P$42") (pinfunction "B12_P$42") (pintype "bidirectional"))
    )
    (net (code "1398") (name "ZZ.10.108") (class "Default")
      (node (ref "U$13") (pin "P$72") (pinfunction "C12_P$72") (pintype "bidirectional"))
    )
    (net (code "1399") (name "ZZ.10.109") (class "Default")
      (node (ref "U$13") (pin "P$102") (pinfunction "D12_P$102") (pintype "bidirectional"))
    )
    (net (code "1400") (name "ZZ.10.110") (class "Default")
      (node (ref "U$13") (pin "P$132") (pinfunction "E12_P$132") (pintype "bidirectional"))
    )
    (net (code "1401") (name "ZZ.10.111") (class "Default")
      (node (ref "U$13") (pin "P$162") (pinfunction "F12_P$162") (pintype "bidirectional"))
    )
    (net (code "1402") (name "ZZ.10.112") (class "Default")
      (node (ref "U$15") (pin "P$40") (pinfunction "B10_P$40") (pintype "bidirectional"))
    )
    (net (code "1403") (name "ZZ.10.113") (class "Default")
      (node (ref "U$15") (pin "P$70") (pinfunction "C10_P$70") (pintype "bidirectional"))
    )
    (net (code "1404") (name "ZZ.10.114") (class "Default")
      (node (ref "U$15") (pin "P$100") (pinfunction "D10_P$100") (pintype "bidirectional"))
    )
    (net (code "1405") (name "ZZ.10.115") (class "Default")
      (node (ref "U$15") (pin "P$130") (pinfunction "E10_P$130") (pintype "bidirectional"))
    )
    (net (code "1406") (name "ZZ.10.116") (class "Default")
      (node (ref "U$15") (pin "P$160") (pinfunction "F10_P$160") (pintype "bidirectional"))
    )
    (net (code "1407") (name "ZZ.10.117") (class "Default")
      (node (ref "U$15") (pin "P$129") (pinfunction "E9_P$129") (pintype "bidirectional"))
    )
    (net (code "1408") (name "ZZ.10.118") (class "Default")
      (node (ref "U$15") (pin "P$41") (pinfunction "B11_P$41") (pintype "bidirectional"))
    )
    (net (code "1409") (name "ZZ.10.119") (class "Default")
      (node (ref "U$15") (pin "P$71") (pinfunction "C11_P$71") (pintype "bidirectional"))
    )
    (net (code "1410") (name "ZZ.10.120") (class "Default")
      (node (ref "U$15") (pin "P$101") (pinfunction "D11_P$101") (pintype "bidirectional"))
    )
    (net (code "1411") (name "ZZ.10.121") (class "Default")
      (node (ref "U$15") (pin "P$131") (pinfunction "E11_P$131") (pintype "bidirectional"))
    )
    (net (code "1412") (name "ZZ.10.122") (class "Default")
      (node (ref "U$15") (pin "P$161") (pinfunction "F11_P$161") (pintype "bidirectional"))
    )
    (net (code "1413") (name "ZZ.10.123") (class "Default")
      (node (ref "U$15") (pin "P$42") (pinfunction "B12_P$42") (pintype "bidirectional"))
    )
    (net (code "1414") (name "ZZ.10.124") (class "Default")
      (node (ref "U$15") (pin "P$72") (pinfunction "C12_P$72") (pintype "bidirectional"))
    )
    (net (code "1415") (name "ZZ.10.125") (class "Default")
      (node (ref "U$15") (pin "P$102") (pinfunction "D12_P$102") (pintype "bidirectional"))
    )
    (net (code "1416") (name "ZZ.10.126") (class "Default")
      (node (ref "U$15") (pin "P$132") (pinfunction "E12_P$132") (pintype "bidirectional"))
    )
    (net (code "1417") (name "ZZ.10.127") (class "Default")
      (node (ref "U$15") (pin "P$162") (pinfunction "F12_P$162") (pintype "bidirectional"))
    )
    (net (code "1418") (name "ZZ.11.000") (class "Default")
      (node (ref "U$1") (pin "P$43") (pinfunction "B13_P$43") (pintype "bidirectional"))
    )
    (net (code "1419") (name "ZZ.11.001") (class "Default")
      (node (ref "U$1") (pin "P$73") (pinfunction "C13_P$73") (pintype "bidirectional"))
    )
    (net (code "1420") (name "ZZ.11.002") (class "Default")
      (node (ref "U$1") (pin "P$103") (pinfunction "D13_P$103") (pintype "bidirectional"))
    )
    (net (code "1421") (name "ZZ.11.003") (class "Default")
      (node (ref "U$1") (pin "P$133") (pinfunction "E13_P$133") (pintype "bidirectional"))
    )
    (net (code "1422") (name "ZZ.11.004") (class "Default")
      (node (ref "U$1") (pin "P$163") (pinfunction "F13_P$163") (pintype "bidirectional"))
    )
    (net (code "1423") (name "ZZ.11.005") (class "Default")
      (node (ref "U$1") (pin "P$159") (pinfunction "F9_P$159") (pintype "bidirectional"))
    )
    (net (code "1424") (name "ZZ.11.006") (class "Default")
      (node (ref "U$1") (pin "P$44") (pinfunction "B14_P$44") (pintype "bidirectional"))
    )
    (net (code "1425") (name "ZZ.11.007") (class "Default")
      (node (ref "U$1") (pin "P$74") (pinfunction "C14_P$74") (pintype "bidirectional"))
    )
    (net (code "1426") (name "ZZ.11.008") (class "Default")
      (node (ref "U$1") (pin "P$104") (pinfunction "D14_P$104") (pintype "bidirectional"))
    )
    (net (code "1427") (name "ZZ.11.009") (class "Default")
      (node (ref "U$1") (pin "P$134") (pinfunction "E14_P$134") (pintype "bidirectional"))
    )
    (net (code "1428") (name "ZZ.11.010") (class "Default")
      (node (ref "U$1") (pin "P$164") (pinfunction "F14_P$164") (pintype "bidirectional"))
    )
    (net (code "1429") (name "ZZ.11.011") (class "Default")
      (node (ref "U$1") (pin "P$45") (pinfunction "B15_P$45") (pintype "bidirectional"))
    )
    (net (code "1430") (name "ZZ.11.012") (class "Default")
      (node (ref "U$1") (pin "P$75") (pinfunction "C15_P$75") (pintype "bidirectional"))
    )
    (net (code "1431") (name "ZZ.11.013") (class "Default")
      (node (ref "U$1") (pin "P$105") (pinfunction "D15_P$105") (pintype "bidirectional"))
    )
    (net (code "1432") (name "ZZ.11.014") (class "Default")
      (node (ref "U$1") (pin "P$135") (pinfunction "E15_P$135") (pintype "bidirectional"))
    )
    (net (code "1433") (name "ZZ.11.015") (class "Default")
      (node (ref "U$1") (pin "P$165") (pinfunction "F15_P$165") (pintype "bidirectional"))
    )
    (net (code "1434") (name "ZZ.11.016") (class "Default")
      (node (ref "U$3") (pin "P$43") (pinfunction "B13_P$43") (pintype "bidirectional"))
    )
    (net (code "1435") (name "ZZ.11.017") (class "Default")
      (node (ref "U$3") (pin "P$73") (pinfunction "C13_P$73") (pintype "bidirectional"))
    )
    (net (code "1436") (name "ZZ.11.018") (class "Default")
      (node (ref "U$3") (pin "P$103") (pinfunction "D13_P$103") (pintype "bidirectional"))
    )
    (net (code "1437") (name "ZZ.11.019") (class "Default")
      (node (ref "U$3") (pin "P$133") (pinfunction "E13_P$133") (pintype "bidirectional"))
    )
    (net (code "1438") (name "ZZ.11.020") (class "Default")
      (node (ref "U$3") (pin "P$163") (pinfunction "F13_P$163") (pintype "bidirectional"))
    )
    (net (code "1439") (name "ZZ.11.021") (class "Default")
      (node (ref "U$3") (pin "P$159") (pinfunction "F9_P$159") (pintype "bidirectional"))
    )
    (net (code "1440") (name "ZZ.11.022") (class "Default")
      (node (ref "U$3") (pin "P$44") (pinfunction "B14_P$44") (pintype "bidirectional"))
    )
    (net (code "1441") (name "ZZ.11.023") (class "Default")
      (node (ref "U$3") (pin "P$74") (pinfunction "C14_P$74") (pintype "bidirectional"))
    )
    (net (code "1442") (name "ZZ.11.024") (class "Default")
      (node (ref "U$3") (pin "P$104") (pinfunction "D14_P$104") (pintype "bidirectional"))
    )
    (net (code "1443") (name "ZZ.11.025") (class "Default")
      (node (ref "U$3") (pin "P$45") (pinfunction "B15_P$45") (pintype "bidirectional"))
    )
    (net (code "1444") (name "ZZ.11.026") (class "Default")
      (node (ref "U$3") (pin "P$75") (pinfunction "C15_P$75") (pintype "bidirectional"))
    )
    (net (code "1445") (name "ZZ.11.027") (class "Default")
      (node (ref "U$3") (pin "P$105") (pinfunction "D15_P$105") (pintype "bidirectional"))
    )
    (net (code "1446") (name "ZZ.11.028") (class "Default")
      (node (ref "U$3") (pin "P$135") (pinfunction "E15_P$135") (pintype "bidirectional"))
    )
    (net (code "1447") (name "ZZ.11.029") (class "Default")
      (node (ref "U$3") (pin "P$165") (pinfunction "F15_P$165") (pintype "bidirectional"))
    )
    (net (code "1448") (name "ZZ.11.030") (class "Default")
      (node (ref "U$3") (pin "P$134") (pinfunction "E14_P$134") (pintype "bidirectional"))
    )
    (net (code "1449") (name "ZZ.11.031") (class "Default")
      (node (ref "U$3") (pin "P$164") (pinfunction "F14_P$164") (pintype "bidirectional"))
    )
    (net (code "1450") (name "ZZ.11.032") (class "Default")
      (node (ref "U$5") (pin "P$43") (pinfunction "B13_P$43") (pintype "bidirectional"))
    )
    (net (code "1451") (name "ZZ.11.033") (class "Default")
      (node (ref "U$5") (pin "P$73") (pinfunction "C13_P$73") (pintype "bidirectional"))
    )
    (net (code "1452") (name "ZZ.11.034") (class "Default")
      (node (ref "U$5") (pin "P$103") (pinfunction "D13_P$103") (pintype "bidirectional"))
    )
    (net (code "1453") (name "ZZ.11.035") (class "Default")
      (node (ref "U$5") (pin "P$133") (pinfunction "E13_P$133") (pintype "bidirectional"))
    )
    (net (code "1454") (name "ZZ.11.036") (class "Default")
      (node (ref "U$5") (pin "P$44") (pinfunction "B14_P$44") (pintype "bidirectional"))
    )
    (net (code "1455") (name "ZZ.11.037") (class "Default")
      (node (ref "U$5") (pin "P$74") (pinfunction "C14_P$74") (pintype "bidirectional"))
    )
    (net (code "1456") (name "ZZ.11.038") (class "Default")
      (node (ref "U$5") (pin "P$104") (pinfunction "D14_P$104") (pintype "bidirectional"))
    )
    (net (code "1457") (name "ZZ.11.039") (class "Default")
      (node (ref "U$5") (pin "P$45") (pinfunction "B15_P$45") (pintype "bidirectional"))
    )
    (net (code "1458") (name "ZZ.11.040") (class "Default")
      (node (ref "U$5") (pin "P$75") (pinfunction "C15_P$75") (pintype "bidirectional"))
    )
    (net (code "1459") (name "ZZ.11.041") (class "Default")
      (node (ref "U$5") (pin "P$105") (pinfunction "D15_P$105") (pintype "bidirectional"))
    )
    (net (code "1460") (name "ZZ.11.042") (class "Default")
      (node (ref "U$5") (pin "P$135") (pinfunction "E15_P$135") (pintype "bidirectional"))
    )
    (net (code "1461") (name "ZZ.11.043") (class "Default")
      (node (ref "U$5") (pin "P$165") (pinfunction "F15_P$165") (pintype "bidirectional"))
    )
    (net (code "1462") (name "ZZ.11.044") (class "Default")
      (node (ref "U$5") (pin "P$134") (pinfunction "E14_P$134") (pintype "bidirectional"))
    )
    (net (code "1463") (name "ZZ.11.045") (class "Default")
      (node (ref "U$5") (pin "P$164") (pinfunction "F14_P$164") (pintype "bidirectional"))
    )
    (net (code "1464") (name "ZZ.11.046") (class "Default")
      (node (ref "U$5") (pin "P$163") (pinfunction "F13_P$163") (pintype "bidirectional"))
    )
    (net (code "1465") (name "ZZ.11.047") (class "Default")
      (node (ref "U$5") (pin "P$159") (pinfunction "F9_P$159") (pintype "bidirectional"))
    )
    (net (code "1466") (name "ZZ.11.048") (class "Default")
      (node (ref "U$7") (pin "P$43") (pinfunction "B13_P$43") (pintype "bidirectional"))
    )
    (net (code "1467") (name "ZZ.11.049") (class "Default")
      (node (ref "U$7") (pin "P$44") (pinfunction "B14_P$44") (pintype "bidirectional"))
    )
    (net (code "1468") (name "ZZ.11.050") (class "Default")
      (node (ref "U$7") (pin "P$74") (pinfunction "C14_P$74") (pintype "bidirectional"))
    )
    (net (code "1469") (name "ZZ.11.051") (class "Default")
      (node (ref "U$7") (pin "P$104") (pinfunction "D14_P$104") (pintype "bidirectional"))
    )
    (net (code "1470") (name "ZZ.11.052") (class "Default")
      (node (ref "U$7") (pin "P$45") (pinfunction "B15_P$45") (pintype "bidirectional"))
    )
    (net (code "1471") (name "ZZ.11.053") (class "Default")
      (node (ref "U$7") (pin "P$75") (pinfunction "C15_P$75") (pintype "bidirectional"))
    )
    (net (code "1472") (name "ZZ.11.054") (class "Default")
      (node (ref "U$7") (pin "P$105") (pinfunction "D15_P$105") (pintype "bidirectional"))
    )
    (net (code "1473") (name "ZZ.11.055") (class "Default")
      (node (ref "U$7") (pin "P$135") (pinfunction "E15_P$135") (pintype "bidirectional"))
    )
    (net (code "1474") (name "ZZ.11.056") (class "Default")
      (node (ref "U$7") (pin "P$165") (pinfunction "F15_P$165") (pintype "bidirectional"))
    )
    (net (code "1475") (name "ZZ.11.057") (class "Default")
      (node (ref "U$7") (pin "P$134") (pinfunction "E14_P$134") (pintype "bidirectional"))
    )
    (net (code "1476") (name "ZZ.11.058") (class "Default")
      (node (ref "U$7") (pin "P$164") (pinfunction "F14_P$164") (pintype "bidirectional"))
    )
    (net (code "1477") (name "ZZ.11.059") (class "Default")
      (node (ref "U$7") (pin "P$73") (pinfunction "C13_P$73") (pintype "bidirectional"))
    )
    (net (code "1478") (name "ZZ.11.060") (class "Default")
      (node (ref "U$7") (pin "P$103") (pinfunction "D13_P$103") (pintype "bidirectional"))
    )
    (net (code "1479") (name "ZZ.11.061") (class "Default")
      (node (ref "U$7") (pin "P$133") (pinfunction "E13_P$133") (pintype "bidirectional"))
    )
    (net (code "1480") (name "ZZ.11.062") (class "Default")
      (node (ref "U$7") (pin "P$163") (pinfunction "F13_P$163") (pintype "bidirectional"))
    )
    (net (code "1481") (name "ZZ.11.063") (class "Default")
      (node (ref "U$7") (pin "P$159") (pinfunction "F9_P$159") (pintype "bidirectional"))
    )
    (net (code "1482") (name "ZZ.11.064") (class "Default")
      (node (ref "U$9") (pin "P$44") (pinfunction "B14_P$44") (pintype "bidirectional"))
    )
    (net (code "1483") (name "ZZ.11.065") (class "Default")
      (node (ref "U$9") (pin "P$45") (pinfunction "B15_P$45") (pintype "bidirectional"))
    )
    (net (code "1484") (name "ZZ.11.066") (class "Default")
      (node (ref "U$9") (pin "P$75") (pinfunction "C15_P$75") (pintype "bidirectional"))
    )
    (net (code "1485") (name "ZZ.11.067") (class "Default")
      (node (ref "U$9") (pin "P$105") (pinfunction "D15_P$105") (pintype "bidirectional"))
    )
    (net (code "1486") (name "ZZ.11.068") (class "Default")
      (node (ref "U$9") (pin "P$135") (pinfunction "E15_P$135") (pintype "bidirectional"))
    )
    (net (code "1487") (name "ZZ.11.069") (class "Default")
      (node (ref "U$9") (pin "P$165") (pinfunction "F15_P$165") (pintype "bidirectional"))
    )
    (net (code "1488") (name "ZZ.11.070") (class "Default")
      (node (ref "U$9") (pin "P$74") (pinfunction "C14_P$74") (pintype "bidirectional"))
    )
    (net (code "1489") (name "ZZ.11.071") (class "Default")
      (node (ref "U$9") (pin "P$104") (pinfunction "D14_P$104") (pintype "bidirectional"))
    )
    (net (code "1490") (name "ZZ.11.072") (class "Default")
      (node (ref "U$9") (pin "P$134") (pinfunction "E14_P$134") (pintype "bidirectional"))
    )
    (net (code "1491") (name "ZZ.11.073") (class "Default")
      (node (ref "U$9") (pin "P$164") (pinfunction "F14_P$164") (pintype "bidirectional"))
    )
    (net (code "1492") (name "ZZ.11.074") (class "Default")
      (node (ref "U$9") (pin "P$43") (pinfunction "B13_P$43") (pintype "bidirectional"))
    )
    (net (code "1493") (name "ZZ.11.075") (class "Default")
      (node (ref "U$9") (pin "P$73") (pinfunction "C13_P$73") (pintype "bidirectional"))
    )
    (net (code "1494") (name "ZZ.11.076") (class "Default")
      (node (ref "U$9") (pin "P$103") (pinfunction "D13_P$103") (pintype "bidirectional"))
    )
    (net (code "1495") (name "ZZ.11.077") (class "Default")
      (node (ref "U$9") (pin "P$133") (pinfunction "E13_P$133") (pintype "bidirectional"))
    )
    (net (code "1496") (name "ZZ.11.078") (class "Default")
      (node (ref "U$9") (pin "P$163") (pinfunction "F13_P$163") (pintype "bidirectional"))
    )
    (net (code "1497") (name "ZZ.11.079") (class "Default")
      (node (ref "U$9") (pin "P$159") (pinfunction "F9_P$159") (pintype "bidirectional"))
    )
    (net (code "1498") (name "ZZ.11.080") (class "Default")
      (node (ref "U$11") (pin "P$45") (pinfunction "B15_P$45") (pintype "bidirectional"))
    )
    (net (code "1499") (name "ZZ.11.081") (class "Default")
      (node (ref "U$11") (pin "P$75") (pinfunction "C15_P$75") (pintype "bidirectional"))
    )
    (net (code "1500") (name "ZZ.11.082") (class "Default")
      (node (ref "U$11") (pin "P$105") (pinfunction "D15_P$105") (pintype "bidirectional"))
    )
    (net (code "1501") (name "ZZ.11.083") (class "Default")
      (node (ref "U$11") (pin "P$135") (pinfunction "E15_P$135") (pintype "bidirectional"))
    )
    (net (code "1502") (name "ZZ.11.084") (class "Default")
      (node (ref "U$11") (pin "P$165") (pinfunction "F15_P$165") (pintype "bidirectional"))
    )
    (net (code "1503") (name "ZZ.11.085") (class "Default")
      (node (ref "U$11") (pin "P$44") (pinfunction "B14_P$44") (pintype "bidirectional"))
    )
    (net (code "1504") (name "ZZ.11.086") (class "Default")
      (node (ref "U$11") (pin "P$74") (pinfunction "C14_P$74") (pintype "bidirectional"))
    )
    (net (code "1505") (name "ZZ.11.087") (class "Default")
      (node (ref "U$11") (pin "P$104") (pinfunction "D14_P$104") (pintype "bidirectional"))
    )
    (net (code "1506") (name "ZZ.11.088") (class "Default")
      (node (ref "U$11") (pin "P$134") (pinfunction "E14_P$134") (pintype "bidirectional"))
    )
    (net (code "1507") (name "ZZ.11.089") (class "Default")
      (node (ref "U$11") (pin "P$164") (pinfunction "F14_P$164") (pintype "bidirectional"))
    )
    (net (code "1508") (name "ZZ.11.090") (class "Default")
      (node (ref "U$11") (pin "P$43") (pinfunction "B13_P$43") (pintype "bidirectional"))
    )
    (net (code "1509") (name "ZZ.11.091") (class "Default")
      (node (ref "U$11") (pin "P$73") (pinfunction "C13_P$73") (pintype "bidirectional"))
    )
    (net (code "1510") (name "ZZ.11.092") (class "Default")
      (node (ref "U$11") (pin "P$103") (pinfunction "D13_P$103") (pintype "bidirectional"))
    )
    (net (code "1511") (name "ZZ.11.093") (class "Default")
      (node (ref "U$11") (pin "P$133") (pinfunction "E13_P$133") (pintype "bidirectional"))
    )
    (net (code "1512") (name "ZZ.11.094") (class "Default")
      (node (ref "U$11") (pin "P$163") (pinfunction "F13_P$163") (pintype "bidirectional"))
    )
    (net (code "1513") (name "ZZ.11.095") (class "Default")
      (node (ref "U$11") (pin "P$159") (pinfunction "F9_P$159") (pintype "bidirectional"))
    )
    (net (code "1514") (name "ZZ.11.096") (class "Default")
      (node (ref "U$13") (pin "P$45") (pinfunction "B15_P$45") (pintype "bidirectional"))
    )
    (net (code "1515") (name "ZZ.11.097") (class "Default")
      (node (ref "U$13") (pin "P$75") (pinfunction "C15_P$75") (pintype "bidirectional"))
    )
    (net (code "1516") (name "ZZ.11.098") (class "Default")
      (node (ref "U$13") (pin "P$105") (pinfunction "D15_P$105") (pintype "bidirectional"))
    )
    (net (code "1517") (name "ZZ.11.099") (class "Default")
      (node (ref "U$13") (pin "P$135") (pinfunction "E15_P$135") (pintype "bidirectional"))
    )
    (net (code "1518") (name "ZZ.11.100") (class "Default")
      (node (ref "U$13") (pin "P$165") (pinfunction "F15_P$165") (pintype "bidirectional"))
    )
    (net (code "1519") (name "ZZ.11.101") (class "Default")
      (node (ref "U$13") (pin "P$44") (pinfunction "B14_P$44") (pintype "bidirectional"))
    )
    (net (code "1520") (name "ZZ.11.102") (class "Default")
      (node (ref "U$13") (pin "P$74") (pinfunction "C14_P$74") (pintype "bidirectional"))
    )
    (net (code "1521") (name "ZZ.11.103") (class "Default")
      (node (ref "U$13") (pin "P$104") (pinfunction "D14_P$104") (pintype "bidirectional"))
    )
    (net (code "1522") (name "ZZ.11.104") (class "Default")
      (node (ref "U$13") (pin "P$134") (pinfunction "E14_P$134") (pintype "bidirectional"))
    )
    (net (code "1523") (name "ZZ.11.105") (class "Default")
      (node (ref "U$13") (pin "P$164") (pinfunction "F14_P$164") (pintype "bidirectional"))
    )
    (net (code "1524") (name "ZZ.11.106") (class "Default")
      (node (ref "U$13") (pin "P$43") (pinfunction "B13_P$43") (pintype "bidirectional"))
    )
    (net (code "1525") (name "ZZ.11.107") (class "Default")
      (node (ref "U$13") (pin "P$73") (pinfunction "C13_P$73") (pintype "bidirectional"))
    )
    (net (code "1526") (name "ZZ.11.108") (class "Default")
      (node (ref "U$13") (pin "P$103") (pinfunction "D13_P$103") (pintype "bidirectional"))
    )
    (net (code "1527") (name "ZZ.11.109") (class "Default")
      (node (ref "U$13") (pin "P$133") (pinfunction "E13_P$133") (pintype "bidirectional"))
    )
    (net (code "1528") (name "ZZ.11.110") (class "Default")
      (node (ref "U$13") (pin "P$163") (pinfunction "F13_P$163") (pintype "bidirectional"))
    )
    (net (code "1529") (name "ZZ.11.111") (class "Default")
      (node (ref "U$13") (pin "P$159") (pinfunction "F9_P$159") (pintype "bidirectional"))
    )
    (net (code "1530") (name "ZZ.11.112") (class "Default")
      (node (ref "U$15") (pin "P$45") (pinfunction "B15_P$45") (pintype "bidirectional"))
    )
    (net (code "1531") (name "ZZ.11.113") (class "Default")
      (node (ref "U$15") (pin "P$75") (pinfunction "C15_P$75") (pintype "bidirectional"))
    )
    (net (code "1532") (name "ZZ.11.114") (class "Default")
      (node (ref "U$15") (pin "P$105") (pinfunction "D15_P$105") (pintype "bidirectional"))
    )
    (net (code "1533") (name "ZZ.11.115") (class "Default")
      (node (ref "U$15") (pin "P$135") (pinfunction "E15_P$135") (pintype "bidirectional"))
    )
    (net (code "1534") (name "ZZ.11.116") (class "Default")
      (node (ref "U$15") (pin "P$165") (pinfunction "F15_P$165") (pintype "bidirectional"))
    )
    (net (code "1535") (name "ZZ.11.117") (class "Default")
      (node (ref "U$15") (pin "P$44") (pinfunction "B14_P$44") (pintype "bidirectional"))
    )
    (net (code "1536") (name "ZZ.11.118") (class "Default")
      (node (ref "U$15") (pin "P$74") (pinfunction "C14_P$74") (pintype "bidirectional"))
    )
    (net (code "1537") (name "ZZ.11.119") (class "Default")
      (node (ref "U$15") (pin "P$104") (pinfunction "D14_P$104") (pintype "bidirectional"))
    )
    (net (code "1538") (name "ZZ.11.120") (class "Default")
      (node (ref "U$15") (pin "P$134") (pinfunction "E14_P$134") (pintype "bidirectional"))
    )
    (net (code "1539") (name "ZZ.11.121") (class "Default")
      (node (ref "U$15") (pin "P$164") (pinfunction "F14_P$164") (pintype "bidirectional"))
    )
    (net (code "1540") (name "ZZ.11.122") (class "Default")
      (node (ref "U$15") (pin "P$43") (pinfunction "B13_P$43") (pintype "bidirectional"))
    )
    (net (code "1541") (name "ZZ.11.123") (class "Default")
      (node (ref "U$15") (pin "P$73") (pinfunction "C13_P$73") (pintype "bidirectional"))
    )
    (net (code "1542") (name "ZZ.11.124") (class "Default")
      (node (ref "U$15") (pin "P$103") (pinfunction "D13_P$103") (pintype "bidirectional"))
    )
    (net (code "1543") (name "ZZ.11.125") (class "Default")
      (node (ref "U$15") (pin "P$133") (pinfunction "E13_P$133") (pintype "bidirectional"))
    )
    (net (code "1544") (name "ZZ.11.126") (class "Default")
      (node (ref "U$15") (pin "P$163") (pinfunction "F13_P$163") (pintype "bidirectional"))
    )
    (net (code "1545") (name "ZZ.11.127") (class "Default")
      (node (ref "U$15") (pin "P$159") (pinfunction "F9_P$159") (pintype "bidirectional"))
    )
    (net (code "1546") (name "ZZ.12.000") (class "Default")
      (node (ref "U$1") (pin "P$48") (pinfunction "B18_P$48") (pintype "bidirectional"))
    )
    (net (code "1547") (name "ZZ.12.001") (class "Default")
      (node (ref "U$1") (pin "P$50") (pinfunction "B20_P$50") (pintype "bidirectional"))
    )
    (net (code "1548") (name "ZZ.12.002") (class "Default")
      (node (ref "U$1") (pin "P$52") (pinfunction "B22_P$52") (pintype "bidirectional"))
    )
    (net (code "1549") (name "ZZ.12.003") (class "Default")
      (node (ref "U$1") (pin "P$78") (pinfunction "C18_P$78") (pintype "bidirectional"))
    )
    (net (code "1550") (name "ZZ.12.004") (class "Default")
      (node (ref "U$1") (pin "P$80") (pinfunction "C20_P$80") (pintype "bidirectional"))
    )
    (net (code "1551") (name "ZZ.12.005") (class "Default")
      (node (ref "U$1") (pin "P$82") (pinfunction "C22_P$82") (pintype "bidirectional"))
    )
    (net (code "1552") (name "ZZ.12.006") (class "Default")
      (node (ref "U$1") (pin "P$108") (pinfunction "D18_P$108") (pintype "bidirectional"))
    )
    (net (code "1553") (name "ZZ.12.007") (class "Default")
      (node (ref "U$1") (pin "P$110") (pinfunction "D20_P$110") (pintype "bidirectional"))
    )
    (net (code "1554") (name "ZZ.12.008") (class "Default")
      (node (ref "U$1") (pin "P$112") (pinfunction "D22_P$112") (pintype "bidirectional"))
    )
    (net (code "1555") (name "ZZ.12.009") (class "Default")
      (node (ref "U$1") (pin "P$171") (pinfunction "F21_P$171") (pintype "bidirectional"))
    )
    (net (code "1556") (name "ZZ.12.010") (class "Default")
      (node (ref "U$1") (pin "P$138") (pinfunction "E18_P$138") (pintype "bidirectional"))
    )
    (net (code "1557") (name "ZZ.12.011") (class "Default")
      (node (ref "U$3") (pin "P$48") (pinfunction "B18_P$48") (pintype "bidirectional"))
    )
    (net (code "1558") (name "ZZ.12.012") (class "Default")
      (node (ref "U$3") (pin "P$50") (pinfunction "B20_P$50") (pintype "bidirectional"))
    )
    (net (code "1559") (name "ZZ.12.013") (class "Default")
      (node (ref "U$3") (pin "P$52") (pinfunction "B22_P$52") (pintype "bidirectional"))
    )
    (net (code "1560") (name "ZZ.12.014") (class "Default")
      (node (ref "U$1") (pin "P$142") (pinfunction "E22_P$142") (pintype "bidirectional"))
    )
    (net (code "1561") (name "ZZ.12.015") (class "Default")
      (node (ref "U$1") (pin "P$137") (pinfunction "E17_P$137") (pintype "bidirectional"))
    )
    (net (code "1562") (name "ZZ.12.016") (class "Default")
      (node (ref "U$3") (pin "P$78") (pinfunction "C18_P$78") (pintype "bidirectional"))
    )
    (net (code "1563") (name "ZZ.12.017") (class "Default")
      (node (ref "U$3") (pin "P$80") (pinfunction "C20_P$80") (pintype "bidirectional"))
    )
    (net (code "1564") (name "ZZ.12.018") (class "Default")
      (node (ref "U$3") (pin "P$82") (pinfunction "C22_P$82") (pintype "bidirectional"))
    )
    (net (code "1565") (name "ZZ.12.019") (class "Default")
      (node (ref "U$1") (pin "P$172") (pinfunction "F22_P$172") (pintype "bidirectional"))
    )
    (net (code "1566") (name "ZZ.12.020") (class "Default")
      (node (ref "U$1") (pin "P$166") (pinfunction "F16_P$166") (pintype "bidirectional"))
    )
    (net (code "1567") (name "ZZ.12.021") (class "Default")
      (node (ref "U$1") (pin "P$136") (pinfunction "E16_P$136") (pintype "bidirectional"))
    )
    (net (code "1568") (name "ZZ.12.022") (class "Default")
      (node (ref "U$3") (pin "P$108") (pinfunction "D18_P$108") (pintype "bidirectional"))
    )
    (net (code "1569") (name "ZZ.12.023") (class "Default")
      (node (ref "U$3") (pin "P$110") (pinfunction "D20_P$110") (pintype "bidirectional"))
    )
    (net (code "1570") (name "ZZ.12.024") (class "Default")
      (node (ref "U$3") (pin "P$112") (pinfunction "D22_P$112") (pintype "bidirectional"))
    )
    (net (code "1571") (name "ZZ.12.025") (class "Default")
      (node (ref "U$3") (pin "P$171") (pinfunction "F21_P$171") (pintype "bidirectional"))
    )
    (net (code "1572") (name "ZZ.12.026") (class "Default")
      (node (ref "U$3") (pin "P$138") (pinfunction "E18_P$138") (pintype "bidirectional"))
    )
    (net (code "1573") (name "ZZ.12.027") (class "Default")
      (node (ref "U$5") (pin "P$48") (pinfunction "B18_P$48") (pintype "bidirectional"))
    )
    (net (code "1574") (name "ZZ.12.028") (class "Default")
      (node (ref "U$5") (pin "P$50") (pinfunction "B20_P$50") (pintype "bidirectional"))
    )
    (net (code "1575") (name "ZZ.12.029") (class "Default")
      (node (ref "U$5") (pin "P$52") (pinfunction "B22_P$52") (pintype "bidirectional"))
    )
    (net (code "1576") (name "ZZ.12.030") (class "Default")
      (node (ref "U$3") (pin "P$142") (pinfunction "E22_P$142") (pintype "bidirectional"))
    )
    (net (code "1577") (name "ZZ.12.031") (class "Default")
      (node (ref "U$3") (pin "P$137") (pinfunction "E17_P$137") (pintype "bidirectional"))
    )
    (net (code "1578") (name "ZZ.12.032") (class "Default")
      (node (ref "U$3") (pin "P$172") (pinfunction "F22_P$172") (pintype "bidirectional"))
    )
    (net (code "1579") (name "ZZ.12.033") (class "Default")
      (node (ref "U$3") (pin "P$166") (pinfunction "F16_P$166") (pintype "bidirectional"))
    )
    (net (code "1580") (name "ZZ.12.034") (class "Default")
      (node (ref "U$3") (pin "P$136") (pinfunction "E16_P$136") (pintype "bidirectional"))
    )
    (net (code "1581") (name "ZZ.12.035") (class "Default")
      (node (ref "U$5") (pin "P$108") (pinfunction "D18_P$108") (pintype "bidirectional"))
    )
    (net (code "1582") (name "ZZ.12.036") (class "Default")
      (node (ref "U$5") (pin "P$110") (pinfunction "D20_P$110") (pintype "bidirectional"))
    )
    (net (code "1583") (name "ZZ.12.037") (class "Default")
      (node (ref "U$5") (pin "P$112") (pinfunction "D22_P$112") (pintype "bidirectional"))
    )
    (net (code "1584") (name "ZZ.12.038") (class "Default")
      (node (ref "U$5") (pin "P$78") (pinfunction "C18_P$78") (pintype "bidirectional"))
    )
    (net (code "1585") (name "ZZ.12.039") (class "Default")
      (node (ref "U$5") (pin "P$80") (pinfunction "C20_P$80") (pintype "bidirectional"))
    )
    (net (code "1586") (name "ZZ.12.040") (class "Default")
      (node (ref "U$5") (pin "P$82") (pinfunction "C22_P$82") (pintype "bidirectional"))
    )
    (net (code "1587") (name "ZZ.12.041") (class "Default")
      (node (ref "U$5") (pin "P$171") (pinfunction "F21_P$171") (pintype "bidirectional"))
    )
    (net (code "1588") (name "ZZ.12.042") (class "Default")
      (node (ref "U$5") (pin "P$138") (pinfunction "E18_P$138") (pintype "bidirectional"))
    )
    (net (code "1589") (name "ZZ.12.043") (class "Default")
      (node (ref "U$5") (pin "P$142") (pinfunction "E22_P$142") (pintype "bidirectional"))
    )
    (net (code "1590") (name "ZZ.12.044") (class "Default")
      (node (ref "U$5") (pin "P$137") (pinfunction "E17_P$137") (pintype "bidirectional"))
    )
    (net (code "1591") (name "ZZ.12.045") (class "Default")
      (node (ref "U$7") (pin "P$78") (pinfunction "C18_P$78") (pintype "bidirectional"))
    )
    (net (code "1592") (name "ZZ.12.046") (class "Default")
      (node (ref "U$5") (pin "P$172") (pinfunction "F22_P$172") (pintype "bidirectional"))
    )
    (net (code "1593") (name "ZZ.12.047") (class "Default")
      (node (ref "U$5") (pin "P$166") (pinfunction "F16_P$166") (pintype "bidirectional"))
    )
    (net (code "1594") (name "ZZ.12.048") (class "Default")
      (node (ref "U$5") (pin "P$136") (pinfunction "E16_P$136") (pintype "bidirectional"))
    )
    (net (code "1595") (name "ZZ.12.049") (class "Default")
      (node (ref "U$7") (pin "P$108") (pinfunction "D18_P$108") (pintype "bidirectional"))
    )
    (net (code "1596") (name "ZZ.12.050") (class "Default")
      (node (ref "U$7") (pin "P$110") (pinfunction "D20_P$110") (pintype "bidirectional"))
    )
    (net (code "1597") (name "ZZ.12.051") (class "Default")
      (node (ref "U$7") (pin "P$112") (pinfunction "D22_P$112") (pintype "bidirectional"))
    )
    (net (code "1598") (name "ZZ.12.052") (class "Default")
      (node (ref "U$7") (pin "P$80") (pinfunction "C20_P$80") (pintype "bidirectional"))
    )
    (net (code "1599") (name "ZZ.12.053") (class "Default")
      (node (ref "U$7") (pin "P$82") (pinfunction "C22_P$82") (pintype "bidirectional"))
    )
    (net (code "1600") (name "ZZ.12.054") (class "Default")
      (node (ref "U$7") (pin "P$48") (pinfunction "B18_P$48") (pintype "bidirectional"))
    )
    (net (code "1601") (name "ZZ.12.055") (class "Default")
      (node (ref "U$7") (pin "P$50") (pinfunction "B20_P$50") (pintype "bidirectional"))
    )
    (net (code "1602") (name "ZZ.12.056") (class "Default")
      (node (ref "U$7") (pin "P$52") (pinfunction "B22_P$52") (pintype "bidirectional"))
    )
    (net (code "1603") (name "ZZ.12.057") (class "Default")
      (node (ref "U$7") (pin "P$142") (pinfunction "E22_P$142") (pintype "bidirectional"))
    )
    (net (code "1604") (name "ZZ.12.058") (class "Default")
      (node (ref "U$7") (pin "P$137") (pinfunction "E17_P$137") (pintype "bidirectional"))
    )
    (net (code "1605") (name "ZZ.12.059") (class "Default")
      (node (ref "U$7") (pin "P$172") (pinfunction "F22_P$172") (pintype "bidirectional"))
    )
    (net (code "1606") (name "ZZ.12.060") (class "Default")
      (node (ref "U$7") (pin "P$166") (pinfunction "F16_P$166") (pintype "bidirectional"))
    )
    (net (code "1607") (name "ZZ.12.061") (class "Default")
      (node (ref "U$7") (pin "P$136") (pinfunction "E16_P$136") (pintype "bidirectional"))
    )
    (net (code "1608") (name "ZZ.12.062") (class "Default")
      (node (ref "U$9") (pin "P$108") (pinfunction "D18_P$108") (pintype "bidirectional"))
    )
    (net (code "1609") (name "ZZ.12.063") (class "Default")
      (node (ref "U$9") (pin "P$110") (pinfunction "D20_P$110") (pintype "bidirectional"))
    )
    (net (code "1610") (name "ZZ.12.064") (class "Default")
      (node (ref "U$9") (pin "P$112") (pinfunction "D22_P$112") (pintype "bidirectional"))
    )
    (net (code "1611") (name "ZZ.12.065") (class "Default")
      (node (ref "U$9") (pin "P$78") (pinfunction "C18_P$78") (pintype "bidirectional"))
    )
    (net (code "1612") (name "ZZ.12.066") (class "Default")
      (node (ref "U$9") (pin "P$80") (pinfunction "C20_P$80") (pintype "bidirectional"))
    )
    (net (code "1613") (name "ZZ.12.067") (class "Default")
      (node (ref "U$9") (pin "P$82") (pinfunction "C22_P$82") (pintype "bidirectional"))
    )
    (net (code "1614") (name "ZZ.12.068") (class "Default")
      (node (ref "U$7") (pin "P$171") (pinfunction "F21_P$171") (pintype "bidirectional"))
    )
    (net (code "1615") (name "ZZ.12.069") (class "Default")
      (node (ref "U$7") (pin "P$138") (pinfunction "E18_P$138") (pintype "bidirectional"))
    )
    (net (code "1616") (name "ZZ.12.070") (class "Default")
      (node (ref "U$9") (pin "P$48") (pinfunction "B18_P$48") (pintype "bidirectional"))
    )
    (net (code "1617") (name "ZZ.12.071") (class "Default")
      (node (ref "U$9") (pin "P$50") (pinfunction "B20_P$50") (pintype "bidirectional"))
    )
    (net (code "1618") (name "ZZ.12.072") (class "Default")
      (node (ref "U$9") (pin "P$52") (pinfunction "B22_P$52") (pintype "bidirectional"))
    )
    (net (code "1619") (name "ZZ.12.073") (class "Default")
      (node (ref "U$9") (pin "P$172") (pinfunction "F22_P$172") (pintype "bidirectional"))
    )
    (net (code "1620") (name "ZZ.12.074") (class "Default")
      (node (ref "U$9") (pin "P$166") (pinfunction "F16_P$166") (pintype "bidirectional"))
    )
    (net (code "1621") (name "ZZ.12.075") (class "Default")
      (node (ref "U$9") (pin "P$136") (pinfunction "E16_P$136") (pintype "bidirectional"))
    )
    (net (code "1622") (name "ZZ.12.076") (class "Default")
      (node (ref "U$11") (pin "P$108") (pinfunction "D18_P$108") (pintype "bidirectional"))
    )
    (net (code "1623") (name "ZZ.12.077") (class "Default")
      (node (ref "U$11") (pin "P$110") (pinfunction "D20_P$110") (pintype "bidirectional"))
    )
    (net (code "1624") (name "ZZ.12.078") (class "Default")
      (node (ref "U$11") (pin "P$112") (pinfunction "D22_P$112") (pintype "bidirectional"))
    )
    (net (code "1625") (name "ZZ.12.079") (class "Default")
      (node (ref "U$9") (pin "P$142") (pinfunction "E22_P$142") (pintype "bidirectional"))
    )
    (net (code "1626") (name "ZZ.12.080") (class "Default")
      (node (ref "U$9") (pin "P$137") (pinfunction "E17_P$137") (pintype "bidirectional"))
    )
    (net (code "1627") (name "ZZ.12.081") (class "Default")
      (node (ref "U$11") (pin "P$78") (pinfunction "C18_P$78") (pintype "bidirectional"))
    )
    (net (code "1628") (name "ZZ.12.082") (class "Default")
      (node (ref "U$11") (pin "P$80") (pinfunction "C20_P$80") (pintype "bidirectional"))
    )
    (net (code "1629") (name "ZZ.12.083") (class "Default")
      (node (ref "U$11") (pin "P$82") (pinfunction "C22_P$82") (pintype "bidirectional"))
    )
    (net (code "1630") (name "ZZ.12.084") (class "Default")
      (node (ref "U$9") (pin "P$171") (pinfunction "F21_P$171") (pintype "bidirectional"))
    )
    (net (code "1631") (name "ZZ.12.085") (class "Default")
      (node (ref "U$9") (pin "P$138") (pinfunction "E18_P$138") (pintype "bidirectional"))
    )
    (net (code "1632") (name "ZZ.12.086") (class "Default")
      (node (ref "U$11") (pin "P$48") (pinfunction "B18_P$48") (pintype "bidirectional"))
    )
    (net (code "1633") (name "ZZ.12.087") (class "Default")
      (node (ref "U$11") (pin "P$50") (pinfunction "B20_P$50") (pintype "bidirectional"))
    )
    (net (code "1634") (name "ZZ.12.088") (class "Default")
      (node (ref "U$11") (pin "P$52") (pinfunction "B22_P$52") (pintype "bidirectional"))
    )
    (net (code "1635") (name "ZZ.12.089") (class "Default")
      (node (ref "U$11") (pin "P$172") (pinfunction "F22_P$172") (pintype "bidirectional"))
    )
    (net (code "1636") (name "ZZ.12.090") (class "Default")
      (node (ref "U$11") (pin "P$166") (pinfunction "F16_P$166") (pintype "bidirectional"))
    )
    (net (code "1637") (name "ZZ.12.091") (class "Default")
      (node (ref "U$11") (pin "P$136") (pinfunction "E16_P$136") (pintype "bidirectional"))
    )
    (net (code "1638") (name "ZZ.12.092") (class "Default")
      (node (ref "U$13") (pin "P$108") (pinfunction "D18_P$108") (pintype "bidirectional"))
    )
    (net (code "1639") (name "ZZ.12.093") (class "Default")
      (node (ref "U$13") (pin "P$110") (pinfunction "D20_P$110") (pintype "bidirectional"))
    )
    (net (code "1640") (name "ZZ.12.094") (class "Default")
      (node (ref "U$13") (pin "P$112") (pinfunction "D22_P$112") (pintype "bidirectional"))
    )
    (net (code "1641") (name "ZZ.12.095") (class "Default")
      (node (ref "U$11") (pin "P$142") (pinfunction "E22_P$142") (pintype "bidirectional"))
    )
    (net (code "1642") (name "ZZ.12.096") (class "Default")
      (node (ref "U$11") (pin "P$137") (pinfunction "E17_P$137") (pintype "bidirectional"))
    )
    (net (code "1643") (name "ZZ.12.097") (class "Default")
      (node (ref "U$13") (pin "P$78") (pinfunction "C18_P$78") (pintype "bidirectional"))
    )
    (net (code "1644") (name "ZZ.12.098") (class "Default")
      (node (ref "U$13") (pin "P$80") (pinfunction "C20_P$80") (pintype "bidirectional"))
    )
    (net (code "1645") (name "ZZ.12.099") (class "Default")
      (node (ref "U$13") (pin "P$82") (pinfunction "C22_P$82") (pintype "bidirectional"))
    )
    (net (code "1646") (name "ZZ.12.100") (class "Default")
      (node (ref "U$11") (pin "P$171") (pinfunction "F21_P$171") (pintype "bidirectional"))
    )
    (net (code "1647") (name "ZZ.12.101") (class "Default")
      (node (ref "U$11") (pin "P$138") (pinfunction "E18_P$138") (pintype "bidirectional"))
    )
    (net (code "1648") (name "ZZ.12.102") (class "Default")
      (node (ref "U$13") (pin "P$48") (pinfunction "B18_P$48") (pintype "bidirectional"))
    )
    (net (code "1649") (name "ZZ.12.103") (class "Default")
      (node (ref "U$13") (pin "P$50") (pinfunction "B20_P$50") (pintype "bidirectional"))
    )
    (net (code "1650") (name "ZZ.12.104") (class "Default")
      (node (ref "U$13") (pin "P$52") (pinfunction "B22_P$52") (pintype "bidirectional"))
    )
    (net (code "1651") (name "ZZ.12.105") (class "Default")
      (node (ref "U$13") (pin "P$172") (pinfunction "F22_P$172") (pintype "bidirectional"))
    )
    (net (code "1652") (name "ZZ.12.106") (class "Default")
      (node (ref "U$13") (pin "P$166") (pinfunction "F16_P$166") (pintype "bidirectional"))
    )
    (net (code "1653") (name "ZZ.12.107") (class "Default")
      (node (ref "U$13") (pin "P$136") (pinfunction "E16_P$136") (pintype "bidirectional"))
    )
    (net (code "1654") (name "ZZ.12.108") (class "Default")
      (node (ref "U$15") (pin "P$108") (pinfunction "D18_P$108") (pintype "bidirectional"))
    )
    (net (code "1655") (name "ZZ.12.109") (class "Default")
      (node (ref "U$15") (pin "P$110") (pinfunction "D20_P$110") (pintype "bidirectional"))
    )
    (net (code "1656") (name "ZZ.12.110") (class "Default")
      (node (ref "U$15") (pin "P$112") (pinfunction "D22_P$112") (pintype "bidirectional"))
    )
    (net (code "1657") (name "ZZ.12.111") (class "Default")
      (node (ref "U$13") (pin "P$142") (pinfunction "E22_P$142") (pintype "bidirectional"))
    )
    (net (code "1658") (name "ZZ.12.112") (class "Default")
      (node (ref "U$13") (pin "P$137") (pinfunction "E17_P$137") (pintype "bidirectional"))
    )
    (net (code "1659") (name "ZZ.12.113") (class "Default")
      (node (ref "U$15") (pin "P$78") (pinfunction "C18_P$78") (pintype "bidirectional"))
    )
    (net (code "1660") (name "ZZ.12.114") (class "Default")
      (node (ref "U$15") (pin "P$80") (pinfunction "C20_P$80") (pintype "bidirectional"))
    )
    (net (code "1661") (name "ZZ.12.115") (class "Default")
      (node (ref "U$15") (pin "P$82") (pinfunction "C22_P$82") (pintype "bidirectional"))
    )
    (net (code "1662") (name "ZZ.12.116") (class "Default")
      (node (ref "U$13") (pin "P$171") (pinfunction "F21_P$171") (pintype "bidirectional"))
    )
    (net (code "1663") (name "ZZ.12.117") (class "Default")
      (node (ref "U$13") (pin "P$138") (pinfunction "E18_P$138") (pintype "bidirectional"))
    )
    (net (code "1664") (name "ZZ.12.118") (class "Default")
      (node (ref "U$15") (pin "P$48") (pinfunction "B18_P$48") (pintype "bidirectional"))
    )
    (net (code "1665") (name "ZZ.12.119") (class "Default")
      (node (ref "U$15") (pin "P$50") (pinfunction "B20_P$50") (pintype "bidirectional"))
    )
    (net (code "1666") (name "ZZ.12.120") (class "Default")
      (node (ref "U$15") (pin "P$52") (pinfunction "B22_P$52") (pintype "bidirectional"))
    )
    (net (code "1667") (name "ZZ.12.121") (class "Default")
      (node (ref "U$15") (pin "P$172") (pinfunction "F22_P$172") (pintype "bidirectional"))
    )
    (net (code "1668") (name "ZZ.12.122") (class "Default")
      (node (ref "U$15") (pin "P$166") (pinfunction "F16_P$166") (pintype "bidirectional"))
    )
    (net (code "1669") (name "ZZ.12.123") (class "Default")
      (node (ref "U$15") (pin "P$136") (pinfunction "E16_P$136") (pintype "bidirectional"))
    )
    (net (code "1670") (name "ZZ.12.124") (class "Default")
      (node (ref "U$15") (pin "P$142") (pinfunction "E22_P$142") (pintype "bidirectional"))
    )
    (net (code "1671") (name "ZZ.12.125") (class "Default")
      (node (ref "U$15") (pin "P$137") (pinfunction "E17_P$137") (pintype "bidirectional"))
    )
    (net (code "1672") (name "ZZ.12.126") (class "Default")
      (node (ref "U$15") (pin "P$171") (pinfunction "F21_P$171") (pintype "bidirectional"))
    )
    (net (code "1673") (name "ZZ.12.127") (class "Default")
      (node (ref "U$15") (pin "P$138") (pinfunction "E18_P$138") (pintype "bidirectional"))
    )
    (net (code "1674") (name "ZZ.13.000") (class "Default")
      (node (ref "U$1") (pin "P$107") (pinfunction "D17_P$107") (pintype "bidirectional"))
    )
    (net (code "1675") (name "ZZ.13.001") (class "Default")
      (node (ref "U$1") (pin "P$109") (pinfunction "D19_P$109") (pintype "bidirectional"))
    )
    (net (code "1676") (name "ZZ.13.002") (class "Default")
      (node (ref "U$1") (pin "P$111") (pinfunction "D21_P$111") (pintype "bidirectional"))
    )
    (net (code "1677") (name "ZZ.13.003") (class "Default")
      (node (ref "U$1") (pin "P$77") (pinfunction "C17_P$77") (pintype "bidirectional"))
    )
    (net (code "1678") (name "ZZ.13.004") (class "Default")
      (node (ref "U$1") (pin "P$79") (pinfunction "C19_P$79") (pintype "bidirectional"))
    )
    (net (code "1679") (name "ZZ.13.005") (class "Default")
      (node (ref "U$1") (pin "P$81") (pinfunction "C21_P$81") (pintype "bidirectional"))
    )
    (net (code "1680") (name "ZZ.13.006") (class "Default")
      (node (ref "U$1") (pin "P$47") (pinfunction "B17_P$47") (pintype "bidirectional"))
    )
    (net (code "1681") (name "ZZ.13.007") (class "Default")
      (node (ref "U$1") (pin "P$49") (pinfunction "B19_P$49") (pintype "bidirectional"))
    )
    (net (code "1682") (name "ZZ.13.008") (class "Default")
      (node (ref "U$1") (pin "P$51") (pinfunction "B21_P$51") (pintype "bidirectional"))
    )
    (net (code "1683") (name "ZZ.13.009") (class "Default")
      (node (ref "U$1") (pin "P$141") (pinfunction "E21_P$141") (pintype "bidirectional"))
    )
    (net (code "1684") (name "ZZ.13.010") (class "Default")
      (node (ref "U$1") (pin "P$168") (pinfunction "F18_P$168") (pintype "bidirectional"))
    )
    (net (code "1685") (name "ZZ.13.011") (class "Default")
      (node (ref "U$3") (pin "P$107") (pinfunction "D17_P$107") (pintype "bidirectional"))
    )
    (net (code "1686") (name "ZZ.13.012") (class "Default")
      (node (ref "U$3") (pin "P$109") (pinfunction "D19_P$109") (pintype "bidirectional"))
    )
    (net (code "1687") (name "ZZ.13.013") (class "Default")
      (node (ref "U$3") (pin "P$111") (pinfunction "D21_P$111") (pintype "bidirectional"))
    )
    (net (code "1688") (name "ZZ.13.014") (class "Default")
      (node (ref "U$1") (pin "P$170") (pinfunction "F20_P$170") (pintype "bidirectional"))
    )
    (net (code "1689") (name "ZZ.13.015") (class "Default")
      (node (ref "U$1") (pin "P$139") (pinfunction "E19_P$139") (pintype "bidirectional"))
    )
    (net (code "1690") (name "ZZ.13.016") (class "Default")
      (node (ref "U$3") (pin "P$77") (pinfunction "C17_P$77") (pintype "bidirectional"))
    )
    (net (code "1691") (name "ZZ.13.017") (class "Default")
      (node (ref "U$3") (pin "P$79") (pinfunction "C19_P$79") (pintype "bidirectional"))
    )
    (net (code "1692") (name "ZZ.13.018") (class "Default")
      (node (ref "U$3") (pin "P$81") (pinfunction "C21_P$81") (pintype "bidirectional"))
    )
    (net (code "1693") (name "ZZ.13.019") (class "Default")
      (node (ref "U$1") (pin "P$140") (pinfunction "E20_P$140") (pintype "bidirectional"))
    )
    (net (code "1694") (name "ZZ.13.020") (class "Default")
      (node (ref "U$1") (pin "P$169") (pinfunction "F19_P$169") (pintype "bidirectional"))
    )
    (net (code "1695") (name "ZZ.13.021") (class "Default")
      (node (ref "U$1") (pin "P$167") (pinfunction "F17_P$167") (pintype "bidirectional"))
    )
    (net (code "1696") (name "ZZ.13.022") (class "Default")
      (node (ref "U$3") (pin "P$47") (pinfunction "B17_P$47") (pintype "bidirectional"))
    )
    (net (code "1697") (name "ZZ.13.023") (class "Default")
      (node (ref "U$3") (pin "P$49") (pinfunction "B19_P$49") (pintype "bidirectional"))
    )
    (net (code "1698") (name "ZZ.13.024") (class "Default")
      (node (ref "U$3") (pin "P$51") (pinfunction "B21_P$51") (pintype "bidirectional"))
    )
    (net (code "1699") (name "ZZ.13.025") (class "Default")
      (node (ref "U$3") (pin "P$141") (pinfunction "E21_P$141") (pintype "bidirectional"))
    )
    (net (code "1700") (name "ZZ.13.026") (class "Default")
      (node (ref "U$3") (pin "P$168") (pinfunction "F18_P$168") (pintype "bidirectional"))
    )
    (net (code "1701") (name "ZZ.13.027") (class "Default")
      (node (ref "U$5") (pin "P$107") (pinfunction "D17_P$107") (pintype "bidirectional"))
    )
    (net (code "1702") (name "ZZ.13.028") (class "Default")
      (node (ref "U$5") (pin "P$109") (pinfunction "D19_P$109") (pintype "bidirectional"))
    )
    (net (code "1703") (name "ZZ.13.029") (class "Default")
      (node (ref "U$5") (pin "P$111") (pinfunction "D21_P$111") (pintype "bidirectional"))
    )
    (net (code "1704") (name "ZZ.13.030") (class "Default")
      (node (ref "U$3") (pin "P$170") (pinfunction "F20_P$170") (pintype "bidirectional"))
    )
    (net (code "1705") (name "ZZ.13.031") (class "Default")
      (node (ref "U$3") (pin "P$139") (pinfunction "E19_P$139") (pintype "bidirectional"))
    )
    (net (code "1706") (name "ZZ.13.032") (class "Default")
      (node (ref "U$3") (pin "P$140") (pinfunction "E20_P$140") (pintype "bidirectional"))
    )
    (net (code "1707") (name "ZZ.13.033") (class "Default")
      (node (ref "U$3") (pin "P$169") (pinfunction "F19_P$169") (pintype "bidirectional"))
    )
    (net (code "1708") (name "ZZ.13.034") (class "Default")
      (node (ref "U$3") (pin "P$167") (pinfunction "F17_P$167") (pintype "bidirectional"))
    )
    (net (code "1709") (name "ZZ.13.035") (class "Default")
      (node (ref "U$5") (pin "P$47") (pinfunction "B17_P$47") (pintype "bidirectional"))
    )
    (net (code "1710") (name "ZZ.13.036") (class "Default")
      (node (ref "U$5") (pin "P$49") (pinfunction "B19_P$49") (pintype "bidirectional"))
    )
    (net (code "1711") (name "ZZ.13.037") (class "Default")
      (node (ref "U$5") (pin "P$51") (pinfunction "B21_P$51") (pintype "bidirectional"))
    )
    (net (code "1712") (name "ZZ.13.038") (class "Default")
      (node (ref "U$5") (pin "P$77") (pinfunction "C17_P$77") (pintype "bidirectional"))
    )
    (net (code "1713") (name "ZZ.13.039") (class "Default")
      (node (ref "U$5") (pin "P$79") (pinfunction "C19_P$79") (pintype "bidirectional"))
    )
    (net (code "1714") (name "ZZ.13.040") (class "Default")
      (node (ref "U$5") (pin "P$81") (pinfunction "C21_P$81") (pintype "bidirectional"))
    )
    (net (code "1715") (name "ZZ.13.041") (class "Default")
      (node (ref "U$5") (pin "P$141") (pinfunction "E21_P$141") (pintype "bidirectional"))
    )
    (net (code "1716") (name "ZZ.13.042") (class "Default")
      (node (ref "U$5") (pin "P$168") (pinfunction "F18_P$168") (pintype "bidirectional"))
    )
    (net (code "1717") (name "ZZ.13.043") (class "Default")
      (node (ref "U$5") (pin "P$170") (pinfunction "F20_P$170") (pintype "bidirectional"))
    )
    (net (code "1718") (name "ZZ.13.044") (class "Default")
      (node (ref "U$5") (pin "P$139") (pinfunction "E19_P$139") (pintype "bidirectional"))
    )
    (net (code "1719") (name "ZZ.13.045") (class "Default")
      (node (ref "U$7") (pin "P$77") (pinfunction "C17_P$77") (pintype "bidirectional"))
    )
    (net (code "1720") (name "ZZ.13.046") (class "Default")
      (node (ref "U$5") (pin "P$140") (pinfunction "E20_P$140") (pintype "bidirectional"))
    )
    (net (code "1721") (name "ZZ.13.047") (class "Default")
      (node (ref "U$5") (pin "P$169") (pinfunction "F19_P$169") (pintype "bidirectional"))
    )
    (net (code "1722") (name "ZZ.13.048") (class "Default")
      (node (ref "U$5") (pin "P$167") (pinfunction "F17_P$167") (pintype "bidirectional"))
    )
    (net (code "1723") (name "ZZ.13.049") (class "Default")
      (node (ref "U$7") (pin "P$47") (pinfunction "B17_P$47") (pintype "bidirectional"))
    )
    (net (code "1724") (name "ZZ.13.050") (class "Default")
      (node (ref "U$7") (pin "P$49") (pinfunction "B19_P$49") (pintype "bidirectional"))
    )
    (net (code "1725") (name "ZZ.13.051") (class "Default")
      (node (ref "U$7") (pin "P$51") (pinfunction "B21_P$51") (pintype "bidirectional"))
    )
    (net (code "1726") (name "ZZ.13.052") (class "Default")
      (node (ref "U$7") (pin "P$79") (pinfunction "C19_P$79") (pintype "bidirectional"))
    )
    (net (code "1727") (name "ZZ.13.053") (class "Default")
      (node (ref "U$7") (pin "P$81") (pinfunction "C21_P$81") (pintype "bidirectional"))
    )
    (net (code "1728") (name "ZZ.13.054") (class "Default")
      (node (ref "U$7") (pin "P$107") (pinfunction "D17_P$107") (pintype "bidirectional"))
    )
    (net (code "1729") (name "ZZ.13.055") (class "Default")
      (node (ref "U$7") (pin "P$109") (pinfunction "D19_P$109") (pintype "bidirectional"))
    )
    (net (code "1730") (name "ZZ.13.056") (class "Default")
      (node (ref "U$7") (pin "P$111") (pinfunction "D21_P$111") (pintype "bidirectional"))
    )
    (net (code "1731") (name "ZZ.13.057") (class "Default")
      (node (ref "U$7") (pin "P$170") (pinfunction "F20_P$170") (pintype "bidirectional"))
    )
    (net (code "1732") (name "ZZ.13.058") (class "Default")
      (node (ref "U$7") (pin "P$139") (pinfunction "E19_P$139") (pintype "bidirectional"))
    )
    (net (code "1733") (name "ZZ.13.059") (class "Default")
      (node (ref "U$7") (pin "P$140") (pinfunction "E20_P$140") (pintype "bidirectional"))
    )
    (net (code "1734") (name "ZZ.13.060") (class "Default")
      (node (ref "U$7") (pin "P$169") (pinfunction "F19_P$169") (pintype "bidirectional"))
    )
    (net (code "1735") (name "ZZ.13.061") (class "Default")
      (node (ref "U$7") (pin "P$167") (pinfunction "F17_P$167") (pintype "bidirectional"))
    )
    (net (code "1736") (name "ZZ.13.062") (class "Default")
      (node (ref "U$9") (pin "P$47") (pinfunction "B17_P$47") (pintype "bidirectional"))
    )
    (net (code "1737") (name "ZZ.13.063") (class "Default")
      (node (ref "U$9") (pin "P$49") (pinfunction "B19_P$49") (pintype "bidirectional"))
    )
    (net (code "1738") (name "ZZ.13.064") (class "Default")
      (node (ref "U$9") (pin "P$51") (pinfunction "B21_P$51") (pintype "bidirectional"))
    )
    (net (code "1739") (name "ZZ.13.065") (class "Default")
      (node (ref "U$9") (pin "P$77") (pinfunction "C17_P$77") (pintype "bidirectional"))
    )
    (net (code "1740") (name "ZZ.13.066") (class "Default")
      (node (ref "U$9") (pin "P$79") (pinfunction "C19_P$79") (pintype "bidirectional"))
    )
    (net (code "1741") (name "ZZ.13.067") (class "Default")
      (node (ref "U$9") (pin "P$81") (pinfunction "C21_P$81") (pintype "bidirectional"))
    )
    (net (code "1742") (name "ZZ.13.068") (class "Default")
      (node (ref "U$7") (pin "P$141") (pinfunction "E21_P$141") (pintype "bidirectional"))
    )
    (net (code "1743") (name "ZZ.13.069") (class "Default")
      (node (ref "U$7") (pin "P$168") (pinfunction "F18_P$168") (pintype "bidirectional"))
    )
    (net (code "1744") (name "ZZ.13.070") (class "Default")
      (node (ref "U$9") (pin "P$107") (pinfunction "D17_P$107") (pintype "bidirectional"))
    )
    (net (code "1745") (name "ZZ.13.071") (class "Default")
      (node (ref "U$9") (pin "P$109") (pinfunction "D19_P$109") (pintype "bidirectional"))
    )
    (net (code "1746") (name "ZZ.13.072") (class "Default")
      (node (ref "U$9") (pin "P$111") (pinfunction "D21_P$111") (pintype "bidirectional"))
    )
    (net (code "1747") (name "ZZ.13.073") (class "Default")
      (node (ref "U$9") (pin "P$140") (pinfunction "E20_P$140") (pintype "bidirectional"))
    )
    (net (code "1748") (name "ZZ.13.074") (class "Default")
      (node (ref "U$9") (pin "P$169") (pinfunction "F19_P$169") (pintype "bidirectional"))
    )
    (net (code "1749") (name "ZZ.13.075") (class "Default")
      (node (ref "U$9") (pin "P$167") (pinfunction "F17_P$167") (pintype "bidirectional"))
    )
    (net (code "1750") (name "ZZ.13.076") (class "Default")
      (node (ref "U$11") (pin "P$47") (pinfunction "B17_P$47") (pintype "bidirectional"))
    )
    (net (code "1751") (name "ZZ.13.077") (class "Default")
      (node (ref "U$11") (pin "P$49") (pinfunction "B19_P$49") (pintype "bidirectional"))
    )
    (net (code "1752") (name "ZZ.13.078") (class "Default")
      (node (ref "U$11") (pin "P$51") (pinfunction "B21_P$51") (pintype "bidirectional"))
    )
    (net (code "1753") (name "ZZ.13.079") (class "Default")
      (node (ref "U$9") (pin "P$170") (pinfunction "F20_P$170") (pintype "bidirectional"))
    )
    (net (code "1754") (name "ZZ.13.080") (class "Default")
      (node (ref "U$9") (pin "P$139") (pinfunction "E19_P$139") (pintype "bidirectional"))
    )
    (net (code "1755") (name "ZZ.13.081") (class "Default")
      (node (ref "U$11") (pin "P$77") (pinfunction "C17_P$77") (pintype "bidirectional"))
    )
    (net (code "1756") (name "ZZ.13.082") (class "Default")
      (node (ref "U$11") (pin "P$79") (pinfunction "C19_P$79") (pintype "bidirectional"))
    )
    (net (code "1757") (name "ZZ.13.083") (class "Default")
      (node (ref "U$11") (pin "P$81") (pinfunction "C21_P$81") (pintype "bidirectional"))
    )
    (net (code "1758") (name "ZZ.13.084") (class "Default")
      (node (ref "U$9") (pin "P$141") (pinfunction "E21_P$141") (pintype "bidirectional"))
    )
    (net (code "1759") (name "ZZ.13.085") (class "Default")
      (node (ref "U$9") (pin "P$168") (pinfunction "F18_P$168") (pintype "bidirectional"))
    )
    (net (code "1760") (name "ZZ.13.086") (class "Default")
      (node (ref "U$11") (pin "P$107") (pinfunction "D17_P$107") (pintype "bidirectional"))
    )
    (net (code "1761") (name "ZZ.13.087") (class "Default")
      (node (ref "U$11") (pin "P$109") (pinfunction "D19_P$109") (pintype "bidirectional"))
    )
    (net (code "1762") (name "ZZ.13.088") (class "Default")
      (node (ref "U$11") (pin "P$111") (pinfunction "D21_P$111") (pintype "bidirectional"))
    )
    (net (code "1763") (name "ZZ.13.089") (class "Default")
      (node (ref "U$11") (pin "P$140") (pinfunction "E20_P$140") (pintype "bidirectional"))
    )
    (net (code "1764") (name "ZZ.13.090") (class "Default")
      (node (ref "U$11") (pin "P$169") (pinfunction "F19_P$169") (pintype "bidirectional"))
    )
    (net (code "1765") (name "ZZ.13.091") (class "Default")
      (node (ref "U$11") (pin "P$167") (pinfunction "F17_P$167") (pintype "bidirectional"))
    )
    (net (code "1766") (name "ZZ.13.092") (class "Default")
      (node (ref "U$13") (pin "P$47") (pinfunction "B17_P$47") (pintype "bidirectional"))
    )
    (net (code "1767") (name "ZZ.13.093") (class "Default")
      (node (ref "U$13") (pin "P$49") (pinfunction "B19_P$49") (pintype "bidirectional"))
    )
    (net (code "1768") (name "ZZ.13.094") (class "Default")
      (node (ref "U$13") (pin "P$51") (pinfunction "B21_P$51") (pintype "bidirectional"))
    )
    (net (code "1769") (name "ZZ.13.095") (class "Default")
      (node (ref "U$11") (pin "P$170") (pinfunction "F20_P$170") (pintype "bidirectional"))
    )
    (net (code "1770") (name "ZZ.13.096") (class "Default")
      (node (ref "U$11") (pin "P$139") (pinfunction "E19_P$139") (pintype "bidirectional"))
    )
    (net (code "1771") (name "ZZ.13.097") (class "Default")
      (node (ref "U$13") (pin "P$77") (pinfunction "C17_P$77") (pintype "bidirectional"))
    )
    (net (code "1772") (name "ZZ.13.098") (class "Default")
      (node (ref "U$13") (pin "P$79") (pinfunction "C19_P$79") (pintype "bidirectional"))
    )
    (net (code "1773") (name "ZZ.13.099") (class "Default")
      (node (ref "U$13") (pin "P$81") (pinfunction "C21_P$81") (pintype "bidirectional"))
    )
    (net (code "1774") (name "ZZ.13.100") (class "Default")
      (node (ref "U$11") (pin "P$141") (pinfunction "E21_P$141") (pintype "bidirectional"))
    )
    (net (code "1775") (name "ZZ.13.101") (class "Default")
      (node (ref "U$11") (pin "P$168") (pinfunction "F18_P$168") (pintype "bidirectional"))
    )
    (net (code "1776") (name "ZZ.13.102") (class "Default")
      (node (ref "U$13") (pin "P$107") (pinfunction "D17_P$107") (pintype "bidirectional"))
    )
    (net (code "1777") (name "ZZ.13.103") (class "Default")
      (node (ref "U$13") (pin "P$109") (pinfunction "D19_P$109") (pintype "bidirectional"))
    )
    (net (code "1778") (name "ZZ.13.104") (class "Default")
      (node (ref "U$13") (pin "P$111") (pinfunction "D21_P$111") (pintype "bidirectional"))
    )
    (net (code "1779") (name "ZZ.13.105") (class "Default")
      (node (ref "U$13") (pin "P$140") (pinfunction "E20_P$140") (pintype "bidirectional"))
    )
    (net (code "1780") (name "ZZ.13.106") (class "Default")
      (node (ref "U$13") (pin "P$169") (pinfunction "F19_P$169") (pintype "bidirectional"))
    )
    (net (code "1781") (name "ZZ.13.107") (class "Default")
      (node (ref "U$13") (pin "P$167") (pinfunction "F17_P$167") (pintype "bidirectional"))
    )
    (net (code "1782") (name "ZZ.13.108") (class "Default")
      (node (ref "U$15") (pin "P$47") (pinfunction "B17_P$47") (pintype "bidirectional"))
    )
    (net (code "1783") (name "ZZ.13.109") (class "Default")
      (node (ref "U$15") (pin "P$49") (pinfunction "B19_P$49") (pintype "bidirectional"))
    )
    (net (code "1784") (name "ZZ.13.110") (class "Default")
      (node (ref "U$15") (pin "P$51") (pinfunction "B21_P$51") (pintype "bidirectional"))
    )
    (net (code "1785") (name "ZZ.13.111") (class "Default")
      (node (ref "U$13") (pin "P$170") (pinfunction "F20_P$170") (pintype "bidirectional"))
    )
    (net (code "1786") (name "ZZ.13.112") (class "Default")
      (node (ref "U$13") (pin "P$139") (pinfunction "E19_P$139") (pintype "bidirectional"))
    )
    (net (code "1787") (name "ZZ.13.113") (class "Default")
      (node (ref "U$15") (pin "P$77") (pinfunction "C17_P$77") (pintype "bidirectional"))
    )
    (net (code "1788") (name "ZZ.13.114") (class "Default")
      (node (ref "U$15") (pin "P$79") (pinfunction "C19_P$79") (pintype "bidirectional"))
    )
    (net (code "1789") (name "ZZ.13.115") (class "Default")
      (node (ref "U$15") (pin "P$81") (pinfunction "C21_P$81") (pintype "bidirectional"))
    )
    (net (code "1790") (name "ZZ.13.116") (class "Default")
      (node (ref "U$13") (pin "P$141") (pinfunction "E21_P$141") (pintype "bidirectional"))
    )
    (net (code "1791") (name "ZZ.13.117") (class "Default")
      (node (ref "U$13") (pin "P$168") (pinfunction "F18_P$168") (pintype "bidirectional"))
    )
    (net (code "1792") (name "ZZ.13.118") (class "Default")
      (node (ref "U$15") (pin "P$107") (pinfunction "D17_P$107") (pintype "bidirectional"))
    )
    (net (code "1793") (name "ZZ.13.119") (class "Default")
      (node (ref "U$15") (pin "P$109") (pinfunction "D19_P$109") (pintype "bidirectional"))
    )
    (net (code "1794") (name "ZZ.13.120") (class "Default")
      (node (ref "U$15") (pin "P$111") (pinfunction "D21_P$111") (pintype "bidirectional"))
    )
    (net (code "1795") (name "ZZ.13.121") (class "Default")
      (node (ref "U$15") (pin "P$140") (pinfunction "E20_P$140") (pintype "bidirectional"))
    )
    (net (code "1796") (name "ZZ.13.122") (class "Default")
      (node (ref "U$15") (pin "P$169") (pinfunction "F19_P$169") (pintype "bidirectional"))
    )
    (net (code "1797") (name "ZZ.13.123") (class "Default")
      (node (ref "U$15") (pin "P$167") (pinfunction "F17_P$167") (pintype "bidirectional"))
    )
    (net (code "1798") (name "ZZ.13.124") (class "Default")
      (node (ref "U$15") (pin "P$170") (pinfunction "F20_P$170") (pintype "bidirectional"))
    )
    (net (code "1799") (name "ZZ.13.125") (class "Default")
      (node (ref "U$15") (pin "P$139") (pinfunction "E19_P$139") (pintype "bidirectional"))
    )
    (net (code "1800") (name "ZZ.13.126") (class "Default")
      (node (ref "U$15") (pin "P$141") (pinfunction "E21_P$141") (pintype "bidirectional"))
    )
    (net (code "1801") (name "ZZ.13.127") (class "Default")
      (node (ref "U$15") (pin "P$168") (pinfunction "F18_P$168") (pintype "bidirectional"))
    )
    (net (code "1802") (name "ZZ.14.000") (class "Default")
      (node (ref "U$1") (pin "P$57") (pinfunction "B27_P$57") (pintype "bidirectional"))
    )
    (net (code "1803") (name "ZZ.14.001") (class "Default")
      (node (ref "U$1") (pin "P$87") (pinfunction "C27_P$87") (pintype "bidirectional"))
    )
    (net (code "1804") (name "ZZ.14.002") (class "Default")
      (node (ref "U$1") (pin "P$117") (pinfunction "D27_P$117") (pintype "bidirectional"))
    )
    (net (code "1805") (name "ZZ.14.003") (class "Default")
      (node (ref "U$1") (pin "P$178") (pinfunction "F28_P$178") (pintype "bidirectional"))
    )
    (net (code "1806") (name "ZZ.14.004") (class "Default")
      (node (ref "U$1") (pin "P$145") (pinfunction "E25_P$145") (pintype "bidirectional"))
    )
    (net (code "1807") (name "ZZ.14.005") (class "Default")
      (node (ref "U$1") (pin "P$58") (pinfunction "B28_P$58") (pintype "bidirectional"))
    )
    (net (code "1808") (name "ZZ.14.006") (class "Default")
      (node (ref "U$1") (pin "P$88") (pinfunction "C28_P$88") (pintype "bidirectional"))
    )
    (net (code "1809") (name "ZZ.14.007") (class "Default")
      (node (ref "U$1") (pin "P$118") (pinfunction "D28_P$118") (pintype "bidirectional"))
    )
    (net (code "1810") (name "ZZ.14.008") (class "Default")
      (node (ref "U$1") (pin "P$149") (pinfunction "E29_P$149") (pintype "bidirectional"))
    )
    (net (code "1811") (name "ZZ.14.009") (class "Default")
      (node (ref "U$1") (pin "P$144") (pinfunction "E24_P$144") (pintype "bidirectional"))
    )
    (net (code "1812") (name "ZZ.14.010") (class "Default")
      (node (ref "U$1") (pin "P$59") (pinfunction "B29_P$59") (pintype "bidirectional"))
    )
    (net (code "1813") (name "ZZ.14.011") (class "Default")
      (node (ref "U$1") (pin "P$89") (pinfunction "C29_P$89") (pintype "bidirectional"))
    )
    (net (code "1814") (name "ZZ.14.012") (class "Default")
      (node (ref "U$1") (pin "P$119") (pinfunction "D29_P$119") (pintype "bidirectional"))
    )
    (net (code "1815") (name "ZZ.14.013") (class "Default")
      (node (ref "U$1") (pin "P$179") (pinfunction "F29_P$179") (pintype "bidirectional"))
    )
    (net (code "1816") (name "ZZ.14.014") (class "Default")
      (node (ref "U$1") (pin "P$173") (pinfunction "F23_P$173") (pintype "bidirectional"))
    )
    (net (code "1817") (name "ZZ.14.015") (class "Default")
      (node (ref "U$1") (pin "P$143") (pinfunction "E23_P$143") (pintype "bidirectional"))
    )
    (net (code "1818") (name "ZZ.14.016") (class "Default")
      (node (ref "U$3") (pin "P$57") (pinfunction "B27_P$57") (pintype "bidirectional"))
    )
    (net (code "1819") (name "ZZ.14.017") (class "Default")
      (node (ref "U$3") (pin "P$87") (pinfunction "C27_P$87") (pintype "bidirectional"))
    )
    (net (code "1820") (name "ZZ.14.018") (class "Default")
      (node (ref "U$3") (pin "P$117") (pinfunction "D27_P$117") (pintype "bidirectional"))
    )
    (net (code "1821") (name "ZZ.14.019") (class "Default")
      (node (ref "U$3") (pin "P$178") (pinfunction "F28_P$178") (pintype "bidirectional"))
    )
    (net (code "1822") (name "ZZ.14.020") (class "Default")
      (node (ref "U$3") (pin "P$145") (pinfunction "E25_P$145") (pintype "bidirectional"))
    )
    (net (code "1823") (name "ZZ.14.021") (class "Default")
      (node (ref "U$3") (pin "P$58") (pinfunction "B28_P$58") (pintype "bidirectional"))
    )
    (net (code "1824") (name "ZZ.14.022") (class "Default")
      (node (ref "U$3") (pin "P$88") (pinfunction "C28_P$88") (pintype "bidirectional"))
    )
    (net (code "1825") (name "ZZ.14.023") (class "Default")
      (node (ref "U$3") (pin "P$118") (pinfunction "D28_P$118") (pintype "bidirectional"))
    )
    (net (code "1826") (name "ZZ.14.024") (class "Default")
      (node (ref "U$3") (pin "P$59") (pinfunction "B29_P$59") (pintype "bidirectional"))
    )
    (net (code "1827") (name "ZZ.14.025") (class "Default")
      (node (ref "U$3") (pin "P$89") (pinfunction "C29_P$89") (pintype "bidirectional"))
    )
    (net (code "1828") (name "ZZ.14.026") (class "Default")
      (node (ref "U$3") (pin "P$119") (pinfunction "D29_P$119") (pintype "bidirectional"))
    )
    (net (code "1829") (name "ZZ.14.027") (class "Default")
      (node (ref "U$3") (pin "P$179") (pinfunction "F29_P$179") (pintype "bidirectional"))
    )
    (net (code "1830") (name "ZZ.14.028") (class "Default")
      (node (ref "U$3") (pin "P$173") (pinfunction "F23_P$173") (pintype "bidirectional"))
    )
    (net (code "1831") (name "ZZ.14.029") (class "Default")
      (node (ref "U$3") (pin "P$143") (pinfunction "E23_P$143") (pintype "bidirectional"))
    )
    (net (code "1832") (name "ZZ.14.030") (class "Default")
      (node (ref "U$3") (pin "P$149") (pinfunction "E29_P$149") (pintype "bidirectional"))
    )
    (net (code "1833") (name "ZZ.14.031") (class "Default")
      (node (ref "U$3") (pin "P$144") (pinfunction "E24_P$144") (pintype "bidirectional"))
    )
    (net (code "1834") (name "ZZ.14.032") (class "Default")
      (node (ref "U$5") (pin "P$57") (pinfunction "B27_P$57") (pintype "bidirectional"))
    )
    (net (code "1835") (name "ZZ.14.033") (class "Default")
      (node (ref "U$5") (pin "P$87") (pinfunction "C27_P$87") (pintype "bidirectional"))
    )
    (net (code "1836") (name "ZZ.14.034") (class "Default")
      (node (ref "U$5") (pin "P$117") (pinfunction "D27_P$117") (pintype "bidirectional"))
    )
    (net (code "1837") (name "ZZ.14.035") (class "Default")
      (node (ref "U$5") (pin "P$178") (pinfunction "F28_P$178") (pintype "bidirectional"))
    )
    (net (code "1838") (name "ZZ.14.036") (class "Default")
      (node (ref "U$5") (pin "P$58") (pinfunction "B28_P$58") (pintype "bidirectional"))
    )
    (net (code "1839") (name "ZZ.14.037") (class "Default")
      (node (ref "U$5") (pin "P$88") (pinfunction "C28_P$88") (pintype "bidirectional"))
    )
    (net (code "1840") (name "ZZ.14.038") (class "Default")
      (node (ref "U$5") (pin "P$59") (pinfunction "B29_P$59") (pintype "bidirectional"))
    )
    (net (code "1841") (name "ZZ.14.039") (class "Default")
      (node (ref "U$5") (pin "P$89") (pinfunction "C29_P$89") (pintype "bidirectional"))
    )
    (net (code "1842") (name "ZZ.14.040") (class "Default")
      (node (ref "U$5") (pin "P$119") (pinfunction "D29_P$119") (pintype "bidirectional"))
    )
    (net (code "1843") (name "ZZ.14.041") (class "Default")
      (node (ref "U$5") (pin "P$179") (pinfunction "F29_P$179") (pintype "bidirectional"))
    )
    (net (code "1844") (name "ZZ.14.042") (class "Default")
      (node (ref "U$5") (pin "P$173") (pinfunction "F23_P$173") (pintype "bidirectional"))
    )
    (net (code "1845") (name "ZZ.14.043") (class "Default")
      (node (ref "U$5") (pin "P$143") (pinfunction "E23_P$143") (pintype "bidirectional"))
    )
    (net (code "1846") (name "ZZ.14.044") (class "Default")
      (node (ref "U$5") (pin "P$118") (pinfunction "D28_P$118") (pintype "bidirectional"))
    )
    (net (code "1847") (name "ZZ.14.045") (class "Default")
      (node (ref "U$5") (pin "P$149") (pinfunction "E29_P$149") (pintype "bidirectional"))
    )
    (net (code "1848") (name "ZZ.14.046") (class "Default")
      (node (ref "U$5") (pin "P$144") (pinfunction "E24_P$144") (pintype "bidirectional"))
    )
    (net (code "1849") (name "ZZ.14.047") (class "Default")
      (node (ref "U$5") (pin "P$145") (pinfunction "E25_P$145") (pintype "bidirectional"))
    )
    (net (code "1850") (name "ZZ.14.048") (class "Default")
      (node (ref "U$7") (pin "P$57") (pinfunction "B27_P$57") (pintype "bidirectional"))
    )
    (net (code "1851") (name "ZZ.14.049") (class "Default")
      (node (ref "U$7") (pin "P$58") (pinfunction "B28_P$58") (pintype "bidirectional"))
    )
    (net (code "1852") (name "ZZ.14.050") (class "Default")
      (node (ref "U$7") (pin "P$88") (pinfunction "C28_P$88") (pintype "bidirectional"))
    )
    (net (code "1853") (name "ZZ.14.051") (class "Default")
      (node (ref "U$7") (pin "P$59") (pinfunction "B29_P$59") (pintype "bidirectional"))
    )
    (net (code "1854") (name "ZZ.14.052") (class "Default")
      (node (ref "U$7") (pin "P$89") (pinfunction "C29_P$89") (pintype "bidirectional"))
    )
    (net (code "1855") (name "ZZ.14.053") (class "Default")
      (node (ref "U$7") (pin "P$119") (pinfunction "D29_P$119") (pintype "bidirectional"))
    )
    (net (code "1856") (name "ZZ.14.054") (class "Default")
      (node (ref "U$7") (pin "P$179") (pinfunction "F29_P$179") (pintype "bidirectional"))
    )
    (net (code "1857") (name "ZZ.14.055") (class "Default")
      (node (ref "U$7") (pin "P$173") (pinfunction "F23_P$173") (pintype "bidirectional"))
    )
    (net (code "1858") (name "ZZ.14.056") (class "Default")
      (node (ref "U$7") (pin "P$143") (pinfunction "E23_P$143") (pintype "bidirectional"))
    )
    (net (code "1859") (name "ZZ.14.057") (class "Default")
      (node (ref "U$7") (pin "P$118") (pinfunction "D28_P$118") (pintype "bidirectional"))
    )
    (net (code "1860") (name "ZZ.14.058") (class "Default")
      (node (ref "U$7") (pin "P$149") (pinfunction "E29_P$149") (pintype "bidirectional"))
    )
    (net (code "1861") (name "ZZ.14.059") (class "Default")
      (node (ref "U$7") (pin "P$144") (pinfunction "E24_P$144") (pintype "bidirectional"))
    )
    (net (code "1862") (name "ZZ.14.060") (class "Default")
      (node (ref "U$7") (pin "P$87") (pinfunction "C27_P$87") (pintype "bidirectional"))
    )
    (net (code "1863") (name "ZZ.14.061") (class "Default")
      (node (ref "U$7") (pin "P$117") (pinfunction "D27_P$117") (pintype "bidirectional"))
    )
    (net (code "1864") (name "ZZ.14.062") (class "Default")
      (node (ref "U$7") (pin "P$178") (pinfunction "F28_P$178") (pintype "bidirectional"))
    )
    (net (code "1865") (name "ZZ.14.063") (class "Default")
      (node (ref "U$7") (pin "P$145") (pinfunction "E25_P$145") (pintype "bidirectional"))
    )
    (net (code "1866") (name "ZZ.14.064") (class "Default")
      (node (ref "U$9") (pin "P$59") (pinfunction "B29_P$59") (pintype "bidirectional"))
    )
    (net (code "1867") (name "ZZ.14.065") (class "Default")
      (node (ref "U$9") (pin "P$89") (pinfunction "C29_P$89") (pintype "bidirectional"))
    )
    (net (code "1868") (name "ZZ.14.066") (class "Default")
      (node (ref "U$9") (pin "P$119") (pinfunction "D29_P$119") (pintype "bidirectional"))
    )
    (net (code "1869") (name "ZZ.14.067") (class "Default")
      (node (ref "U$9") (pin "P$179") (pinfunction "F29_P$179") (pintype "bidirectional"))
    )
    (net (code "1870") (name "ZZ.14.068") (class "Default")
      (node (ref "U$9") (pin "P$173") (pinfunction "F23_P$173") (pintype "bidirectional"))
    )
    (net (code "1871") (name "ZZ.14.069") (class "Default")
      (node (ref "U$9") (pin "P$143") (pinfunction "E23_P$143") (pintype "bidirectional"))
    )
    (net (code "1872") (name "ZZ.14.070") (class "Default")
      (node (ref "U$9") (pin "P$58") (pinfunction "B28_P$58") (pintype "bidirectional"))
    )
    (net (code "1873") (name "ZZ.14.071") (class "Default")
      (node (ref "U$9") (pin "P$88") (pinfunction "C28_P$88") (pintype "bidirectional"))
    )
    (net (code "1874") (name "ZZ.14.072") (class "Default")
      (node (ref "U$9") (pin "P$118") (pinfunction "D28_P$118") (pintype "bidirectional"))
    )
    (net (code "1875") (name "ZZ.14.073") (class "Default")
      (node (ref "U$9") (pin "P$149") (pinfunction "E29_P$149") (pintype "bidirectional"))
    )
    (net (code "1876") (name "ZZ.14.074") (class "Default")
      (node (ref "U$9") (pin "P$144") (pinfunction "E24_P$144") (pintype "bidirectional"))
    )
    (net (code "1877") (name "ZZ.14.075") (class "Default")
      (node (ref "U$9") (pin "P$57") (pinfunction "B27_P$57") (pintype "bidirectional"))
    )
    (net (code "1878") (name "ZZ.14.076") (class "Default")
      (node (ref "U$9") (pin "P$87") (pinfunction "C27_P$87") (pintype "bidirectional"))
    )
    (net (code "1879") (name "ZZ.14.077") (class "Default")
      (node (ref "U$9") (pin "P$117") (pinfunction "D27_P$117") (pintype "bidirectional"))
    )
    (net (code "1880") (name "ZZ.14.078") (class "Default")
      (node (ref "U$9") (pin "P$178") (pinfunction "F28_P$178") (pintype "bidirectional"))
    )
    (net (code "1881") (name "ZZ.14.079") (class "Default")
      (node (ref "U$9") (pin "P$145") (pinfunction "E25_P$145") (pintype "bidirectional"))
    )
    (net (code "1882") (name "ZZ.14.080") (class "Default")
      (node (ref "U$11") (pin "P$59") (pinfunction "B29_P$59") (pintype "bidirectional"))
    )
    (net (code "1883") (name "ZZ.14.081") (class "Default")
      (node (ref "U$11") (pin "P$89") (pinfunction "C29_P$89") (pintype "bidirectional"))
    )
    (net (code "1884") (name "ZZ.14.082") (class "Default")
      (node (ref "U$11") (pin "P$119") (pinfunction "D29_P$119") (pintype "bidirectional"))
    )
    (net (code "1885") (name "ZZ.14.083") (class "Default")
      (node (ref "U$11") (pin "P$179") (pinfunction "F29_P$179") (pintype "bidirectional"))
    )
    (net (code "1886") (name "ZZ.14.084") (class "Default")
      (node (ref "U$11") (pin "P$173") (pinfunction "F23_P$173") (pintype "bidirectional"))
    )
    (net (code "1887") (name "ZZ.14.085") (class "Default")
      (node (ref "U$11") (pin "P$143") (pinfunction "E23_P$143") (pintype "bidirectional"))
    )
    (net (code "1888") (name "ZZ.14.086") (class "Default")
      (node (ref "U$11") (pin "P$58") (pinfunction "B28_P$58") (pintype "bidirectional"))
    )
    (net (code "1889") (name "ZZ.14.087") (class "Default")
      (node (ref "U$11") (pin "P$88") (pinfunction "C28_P$88") (pintype "bidirectional"))
    )
    (net (code "1890") (name "ZZ.14.088") (class "Default")
      (node (ref "U$11") (pin "P$118") (pinfunction "D28_P$118") (pintype "bidirectional"))
    )
    (net (code "1891") (name "ZZ.14.089") (class "Default")
      (node (ref "U$11") (pin "P$149") (pinfunction "E29_P$149") (pintype "bidirectional"))
    )
    (net (code "1892") (name "ZZ.14.090") (class "Default")
      (node (ref "U$11") (pin "P$144") (pinfunction "E24_P$144") (pintype "bidirectional"))
    )
    (net (code "1893") (name "ZZ.14.091") (class "Default")
      (node (ref "U$11") (pin "P$57") (pinfunction "B27_P$57") (pintype "bidirectional"))
    )
    (net (code "1894") (name "ZZ.14.092") (class "Default")
      (node (ref "U$11") (pin "P$87") (pinfunction "C27_P$87") (pintype "bidirectional"))
    )
    (net (code "1895") (name "ZZ.14.093") (class "Default")
      (node (ref "U$11") (pin "P$117") (pinfunction "D27_P$117") (pintype "bidirectional"))
    )
    (net (code "1896") (name "ZZ.14.094") (class "Default")
      (node (ref "U$11") (pin "P$178") (pinfunction "F28_P$178") (pintype "bidirectional"))
    )
    (net (code "1897") (name "ZZ.14.095") (class "Default")
      (node (ref "U$11") (pin "P$145") (pinfunction "E25_P$145") (pintype "bidirectional"))
    )
    (net (code "1898") (name "ZZ.14.096") (class "Default")
      (node (ref "U$13") (pin "P$59") (pinfunction "B29_P$59") (pintype "bidirectional"))
    )
    (net (code "1899") (name "ZZ.14.097") (class "Default")
      (node (ref "U$13") (pin "P$89") (pinfunction "C29_P$89") (pintype "bidirectional"))
    )
    (net (code "1900") (name "ZZ.14.098") (class "Default")
      (node (ref "U$13") (pin "P$119") (pinfunction "D29_P$119") (pintype "bidirectional"))
    )
    (net (code "1901") (name "ZZ.14.099") (class "Default")
      (node (ref "U$13") (pin "P$179") (pinfunction "F29_P$179") (pintype "bidirectional"))
    )
    (net (code "1902") (name "ZZ.14.100") (class "Default")
      (node (ref "U$13") (pin "P$173") (pinfunction "F23_P$173") (pintype "bidirectional"))
    )
    (net (code "1903") (name "ZZ.14.101") (class "Default")
      (node (ref "U$13") (pin "P$143") (pinfunction "E23_P$143") (pintype "bidirectional"))
    )
    (net (code "1904") (name "ZZ.14.102") (class "Default")
      (node (ref "U$13") (pin "P$58") (pinfunction "B28_P$58") (pintype "bidirectional"))
    )
    (net (code "1905") (name "ZZ.14.103") (class "Default")
      (node (ref "U$13") (pin "P$88") (pinfunction "C28_P$88") (pintype "bidirectional"))
    )
    (net (code "1906") (name "ZZ.14.104") (class "Default")
      (node (ref "U$13") (pin "P$118") (pinfunction "D28_P$118") (pintype "bidirectional"))
    )
    (net (code "1907") (name "ZZ.14.105") (class "Default")
      (node (ref "U$13") (pin "P$149") (pinfunction "E29_P$149") (pintype "bidirectional"))
    )
    (net (code "1908") (name "ZZ.14.106") (class "Default")
      (node (ref "U$13") (pin "P$144") (pinfunction "E24_P$144") (pintype "bidirectional"))
    )
    (net (code "1909") (name "ZZ.14.107") (class "Default")
      (node (ref "U$13") (pin "P$57") (pinfunction "B27_P$57") (pintype "bidirectional"))
    )
    (net (code "1910") (name "ZZ.14.108") (class "Default")
      (node (ref "U$13") (pin "P$87") (pinfunction "C27_P$87") (pintype "bidirectional"))
    )
    (net (code "1911") (name "ZZ.14.109") (class "Default")
      (node (ref "U$13") (pin "P$117") (pinfunction "D27_P$117") (pintype "bidirectional"))
    )
    (net (code "1912") (name "ZZ.14.110") (class "Default")
      (node (ref "U$13") (pin "P$178") (pinfunction "F28_P$178") (pintype "bidirectional"))
    )
    (net (code "1913") (name "ZZ.14.111") (class "Default")
      (node (ref "U$13") (pin "P$145") (pinfunction "E25_P$145") (pintype "bidirectional"))
    )
    (net (code "1914") (name "ZZ.14.112") (class "Default")
      (node (ref "U$15") (pin "P$59") (pinfunction "B29_P$59") (pintype "bidirectional"))
    )
    (net (code "1915") (name "ZZ.14.113") (class "Default")
      (node (ref "U$15") (pin "P$89") (pinfunction "C29_P$89") (pintype "bidirectional"))
    )
    (net (code "1916") (name "ZZ.14.114") (class "Default")
      (node (ref "U$15") (pin "P$119") (pinfunction "D29_P$119") (pintype "bidirectional"))
    )
    (net (code "1917") (name "ZZ.14.115") (class "Default")
      (node (ref "U$15") (pin "P$179") (pinfunction "F29_P$179") (pintype "bidirectional"))
    )
    (net (code "1918") (name "ZZ.14.116") (class "Default")
      (node (ref "U$15") (pin "P$173") (pinfunction "F23_P$173") (pintype "bidirectional"))
    )
    (net (code "1919") (name "ZZ.14.117") (class "Default")
      (node (ref "U$15") (pin "P$143") (pinfunction "E23_P$143") (pintype "bidirectional"))
    )
    (net (code "1920") (name "ZZ.14.118") (class "Default")
      (node (ref "U$15") (pin "P$58") (pinfunction "B28_P$58") (pintype "bidirectional"))
    )
    (net (code "1921") (name "ZZ.14.119") (class "Default")
      (node (ref "U$15") (pin "P$88") (pinfunction "C28_P$88") (pintype "bidirectional"))
    )
    (net (code "1922") (name "ZZ.14.120") (class "Default")
      (node (ref "U$15") (pin "P$118") (pinfunction "D28_P$118") (pintype "bidirectional"))
    )
    (net (code "1923") (name "ZZ.14.121") (class "Default")
      (node (ref "U$15") (pin "P$149") (pinfunction "E29_P$149") (pintype "bidirectional"))
    )
    (net (code "1924") (name "ZZ.14.122") (class "Default")
      (node (ref "U$15") (pin "P$144") (pinfunction "E24_P$144") (pintype "bidirectional"))
    )
    (net (code "1925") (name "ZZ.14.123") (class "Default")
      (node (ref "U$15") (pin "P$57") (pinfunction "B27_P$57") (pintype "bidirectional"))
    )
    (net (code "1926") (name "ZZ.14.124") (class "Default")
      (node (ref "U$15") (pin "P$87") (pinfunction "C27_P$87") (pintype "bidirectional"))
    )
    (net (code "1927") (name "ZZ.14.125") (class "Default")
      (node (ref "U$15") (pin "P$117") (pinfunction "D27_P$117") (pintype "bidirectional"))
    )
    (net (code "1928") (name "ZZ.14.126") (class "Default")
      (node (ref "U$15") (pin "P$178") (pinfunction "F28_P$178") (pintype "bidirectional"))
    )
    (net (code "1929") (name "ZZ.14.127") (class "Default")
      (node (ref "U$15") (pin "P$145") (pinfunction "E25_P$145") (pintype "bidirectional"))
    )
    (net (code "1930") (name "ZZ.15.000") (class "Default")
      (node (ref "U$1") (pin "P$56") (pinfunction "B26_P$56") (pintype "bidirectional"))
    )
    (net (code "1931") (name "ZZ.15.001") (class "Default")
      (node (ref "U$1") (pin "P$86") (pinfunction "C26_P$86") (pintype "bidirectional"))
    )
    (net (code "1932") (name "ZZ.15.002") (class "Default")
      (node (ref "U$1") (pin "P$116") (pinfunction "D26_P$116") (pintype "bidirectional"))
    )
    (net (code "1933") (name "ZZ.15.003") (class "Default")
      (node (ref "U$1") (pin "P$148") (pinfunction "E28_P$148") (pintype "bidirectional"))
    )
    (net (code "1934") (name "ZZ.15.004") (class "Default")
      (node (ref "U$1") (pin "P$175") (pinfunction "F25_P$175") (pintype "bidirectional"))
    )
    (net (code "1935") (name "ZZ.15.005") (class "Default")
      (node (ref "U$1") (pin "P$55") (pinfunction "B25_P$55") (pintype "bidirectional"))
    )
    (net (code "1936") (name "ZZ.15.006") (class "Default")
      (node (ref "U$1") (pin "P$85") (pinfunction "C25_P$85") (pintype "bidirectional"))
    )
    (net (code "1937") (name "ZZ.15.007") (class "Default")
      (node (ref "U$1") (pin "P$115") (pinfunction "D25_P$115") (pintype "bidirectional"))
    )
    (net (code "1938") (name "ZZ.15.008") (class "Default")
      (node (ref "U$1") (pin "P$177") (pinfunction "F27_P$177") (pintype "bidirectional"))
    )
    (net (code "1939") (name "ZZ.15.009") (class "Default")
      (node (ref "U$1") (pin "P$146") (pinfunction "E26_P$146") (pintype "bidirectional"))
    )
    (net (code "1940") (name "ZZ.15.010") (class "Default")
      (node (ref "U$1") (pin "P$54") (pinfunction "B24_P$54") (pintype "bidirectional"))
    )
    (net (code "1941") (name "ZZ.15.011") (class "Default")
      (node (ref "U$1") (pin "P$84") (pinfunction "C24_P$84") (pintype "bidirectional"))
    )
    (net (code "1942") (name "ZZ.15.012") (class "Default")
      (node (ref "U$1") (pin "P$114") (pinfunction "D24_P$114") (pintype "bidirectional"))
    )
    (net (code "1943") (name "ZZ.15.013") (class "Default")
      (node (ref "U$1") (pin "P$147") (pinfunction "E27_P$147") (pintype "bidirectional"))
    )
    (net (code "1944") (name "ZZ.15.014") (class "Default")
      (node (ref "U$1") (pin "P$176") (pinfunction "F26_P$176") (pintype "bidirectional"))
    )
    (net (code "1945") (name "ZZ.15.015") (class "Default")
      (node (ref "U$1") (pin "P$174") (pinfunction "F24_P$174") (pintype "bidirectional"))
    )
    (net (code "1946") (name "ZZ.15.016") (class "Default")
      (node (ref "U$3") (pin "P$56") (pinfunction "B26_P$56") (pintype "bidirectional"))
    )
    (net (code "1947") (name "ZZ.15.017") (class "Default")
      (node (ref "U$3") (pin "P$86") (pinfunction "C26_P$86") (pintype "bidirectional"))
    )
    (net (code "1948") (name "ZZ.15.018") (class "Default")
      (node (ref "U$3") (pin "P$116") (pinfunction "D26_P$116") (pintype "bidirectional"))
    )
    (net (code "1949") (name "ZZ.15.019") (class "Default")
      (node (ref "U$3") (pin "P$148") (pinfunction "E28_P$148") (pintype "bidirectional"))
    )
    (net (code "1950") (name "ZZ.15.020") (class "Default")
      (node (ref "U$3") (pin "P$175") (pinfunction "F25_P$175") (pintype "bidirectional"))
    )
    (net (code "1951") (name "ZZ.15.021") (class "Default")
      (node (ref "U$3") (pin "P$55") (pinfunction "B25_P$55") (pintype "bidirectional"))
    )
    (net (code "1952") (name "ZZ.15.022") (class "Default")
      (node (ref "U$3") (pin "P$85") (pinfunction "C25_P$85") (pintype "bidirectional"))
    )
    (net (code "1953") (name "ZZ.15.023") (class "Default")
      (node (ref "U$3") (pin "P$115") (pinfunction "D25_P$115") (pintype "bidirectional"))
    )
    (net (code "1954") (name "ZZ.15.024") (class "Default")
      (node (ref "U$3") (pin "P$54") (pinfunction "B24_P$54") (pintype "bidirectional"))
    )
    (net (code "1955") (name "ZZ.15.025") (class "Default")
      (node (ref "U$3") (pin "P$84") (pinfunction "C24_P$84") (pintype "bidirectional"))
    )
    (net (code "1956") (name "ZZ.15.026") (class "Default")
      (node (ref "U$3") (pin "P$114") (pinfunction "D24_P$114") (pintype "bidirectional"))
    )
    (net (code "1957") (name "ZZ.15.027") (class "Default")
      (node (ref "U$3") (pin "P$147") (pinfunction "E27_P$147") (pintype "bidirectional"))
    )
    (net (code "1958") (name "ZZ.15.028") (class "Default")
      (node (ref "U$3") (pin "P$176") (pinfunction "F26_P$176") (pintype "bidirectional"))
    )
    (net (code "1959") (name "ZZ.15.029") (class "Default")
      (node (ref "U$3") (pin "P$174") (pinfunction "F24_P$174") (pintype "bidirectional"))
    )
    (net (code "1960") (name "ZZ.15.030") (class "Default")
      (node (ref "U$3") (pin "P$177") (pinfunction "F27_P$177") (pintype "bidirectional"))
    )
    (net (code "1961") (name "ZZ.15.031") (class "Default")
      (node (ref "U$3") (pin "P$146") (pinfunction "E26_P$146") (pintype "bidirectional"))
    )
    (net (code "1962") (name "ZZ.15.032") (class "Default")
      (node (ref "U$5") (pin "P$56") (pinfunction "B26_P$56") (pintype "bidirectional"))
    )
    (net (code "1963") (name "ZZ.15.033") (class "Default")
      (node (ref "U$5") (pin "P$86") (pinfunction "C26_P$86") (pintype "bidirectional"))
    )
    (net (code "1964") (name "ZZ.15.034") (class "Default")
      (node (ref "U$5") (pin "P$116") (pinfunction "D26_P$116") (pintype "bidirectional"))
    )
    (net (code "1965") (name "ZZ.15.035") (class "Default")
      (node (ref "U$5") (pin "P$148") (pinfunction "E28_P$148") (pintype "bidirectional"))
    )
    (net (code "1966") (name "ZZ.15.036") (class "Default")
      (node (ref "U$5") (pin "P$55") (pinfunction "B25_P$55") (pintype "bidirectional"))
    )
    (net (code "1967") (name "ZZ.15.037") (class "Default")
      (node (ref "U$5") (pin "P$85") (pinfunction "C25_P$85") (pintype "bidirectional"))
    )
    (net (code "1968") (name "ZZ.15.038") (class "Default")
      (node (ref "U$5") (pin "P$54") (pinfunction "B24_P$54") (pintype "bidirectional"))
    )
    (net (code "1969") (name "ZZ.15.039") (class "Default")
      (node (ref "U$5") (pin "P$84") (pinfunction "C24_P$84") (pintype "bidirectional"))
    )
    (net (code "1970") (name "ZZ.15.040") (class "Default")
      (node (ref "U$5") (pin "P$114") (pinfunction "D24_P$114") (pintype "bidirectional"))
    )
    (net (code "1971") (name "ZZ.15.041") (class "Default")
      (node (ref "U$5") (pin "P$147") (pinfunction "E27_P$147") (pintype "bidirectional"))
    )
    (net (code "1972") (name "ZZ.15.042") (class "Default")
      (node (ref "U$5") (pin "P$176") (pinfunction "F26_P$176") (pintype "bidirectional"))
    )
    (net (code "1973") (name "ZZ.15.043") (class "Default")
      (node (ref "U$5") (pin "P$174") (pinfunction "F24_P$174") (pintype "bidirectional"))
    )
    (net (code "1974") (name "ZZ.15.044") (class "Default")
      (node (ref "U$5") (pin "P$115") (pinfunction "D25_P$115") (pintype "bidirectional"))
    )
    (net (code "1975") (name "ZZ.15.045") (class "Default")
      (node (ref "U$5") (pin "P$177") (pinfunction "F27_P$177") (pintype "bidirectional"))
    )
    (net (code "1976") (name "ZZ.15.046") (class "Default")
      (node (ref "U$5") (pin "P$146") (pinfunction "E26_P$146") (pintype "bidirectional"))
    )
    (net (code "1977") (name "ZZ.15.047") (class "Default")
      (node (ref "U$5") (pin "P$175") (pinfunction "F25_P$175") (pintype "bidirectional"))
    )
    (net (code "1978") (name "ZZ.15.048") (class "Default")
      (node (ref "U$7") (pin "P$56") (pinfunction "B26_P$56") (pintype "bidirectional"))
    )
    (net (code "1979") (name "ZZ.15.049") (class "Default")
      (node (ref "U$7") (pin "P$55") (pinfunction "B25_P$55") (pintype "bidirectional"))
    )
    (net (code "1980") (name "ZZ.15.050") (class "Default")
      (node (ref "U$7") (pin "P$85") (pinfunction "C25_P$85") (pintype "bidirectional"))
    )
    (net (code "1981") (name "ZZ.15.051") (class "Default")
      (node (ref "U$7") (pin "P$54") (pinfunction "B24_P$54") (pintype "bidirectional"))
    )
    (net (code "1982") (name "ZZ.15.052") (class "Default")
      (node (ref "U$7") (pin "P$84") (pinfunction "C24_P$84") (pintype "bidirectional"))
    )
    (net (code "1983") (name "ZZ.15.053") (class "Default")
      (node (ref "U$7") (pin "P$114") (pinfunction "D24_P$114") (pintype "bidirectional"))
    )
    (net (code "1984") (name "ZZ.15.054") (class "Default")
      (node (ref "U$7") (pin "P$147") (pinfunction "E27_P$147") (pintype "bidirectional"))
    )
    (net (code "1985") (name "ZZ.15.055") (class "Default")
      (node (ref "U$7") (pin "P$176") (pinfunction "F26_P$176") (pintype "bidirectional"))
    )
    (net (code "1986") (name "ZZ.15.056") (class "Default")
      (node (ref "U$7") (pin "P$174") (pinfunction "F24_P$174") (pintype "bidirectional"))
    )
    (net (code "1987") (name "ZZ.15.057") (class "Default")
      (node (ref "U$7") (pin "P$115") (pinfunction "D25_P$115") (pintype "bidirectional"))
    )
    (net (code "1988") (name "ZZ.15.058") (class "Default")
      (node (ref "U$7") (pin "P$177") (pinfunction "F27_P$177") (pintype "bidirectional"))
    )
    (net (code "1989") (name "ZZ.15.059") (class "Default")
      (node (ref "U$7") (pin "P$146") (pinfunction "E26_P$146") (pintype "bidirectional"))
    )
    (net (code "1990") (name "ZZ.15.060") (class "Default")
      (node (ref "U$7") (pin "P$86") (pinfunction "C26_P$86") (pintype "bidirectional"))
    )
    (net (code "1991") (name "ZZ.15.061") (class "Default")
      (node (ref "U$7") (pin "P$116") (pinfunction "D26_P$116") (pintype "bidirectional"))
    )
    (net (code "1992") (name "ZZ.15.062") (class "Default")
      (node (ref "U$7") (pin "P$148") (pinfunction "E28_P$148") (pintype "bidirectional"))
    )
    (net (code "1993") (name "ZZ.15.063") (class "Default")
      (node (ref "U$7") (pin "P$175") (pinfunction "F25_P$175") (pintype "bidirectional"))
    )
    (net (code "1994") (name "ZZ.15.064") (class "Default")
      (node (ref "U$9") (pin "P$54") (pinfunction "B24_P$54") (pintype "bidirectional"))
    )
    (net (code "1995") (name "ZZ.15.065") (class "Default")
      (node (ref "U$9") (pin "P$84") (pinfunction "C24_P$84") (pintype "bidirectional"))
    )
    (net (code "1996") (name "ZZ.15.066") (class "Default")
      (node (ref "U$9") (pin "P$114") (pinfunction "D24_P$114") (pintype "bidirectional"))
    )
    (net (code "1997") (name "ZZ.15.067") (class "Default")
      (node (ref "U$9") (pin "P$147") (pinfunction "E27_P$147") (pintype "bidirectional"))
    )
    (net (code "1998") (name "ZZ.15.068") (class "Default")
      (node (ref "U$9") (pin "P$176") (pinfunction "F26_P$176") (pintype "bidirectional"))
    )
    (net (code "1999") (name "ZZ.15.069") (class "Default")
      (node (ref "U$9") (pin "P$174") (pinfunction "F24_P$174") (pintype "bidirectional"))
    )
    (net (code "2000") (name "ZZ.15.070") (class "Default")
      (node (ref "U$9") (pin "P$55") (pinfunction "B25_P$55") (pintype "bidirectional"))
    )
    (net (code "2001") (name "ZZ.15.071") (class "Default")
      (node (ref "U$9") (pin "P$85") (pinfunction "C25_P$85") (pintype "bidirectional"))
    )
    (net (code "2002") (name "ZZ.15.072") (class "Default")
      (node (ref "U$9") (pin "P$115") (pinfunction "D25_P$115") (pintype "bidirectional"))
    )
    (net (code "2003") (name "ZZ.15.073") (class "Default")
      (node (ref "U$9") (pin "P$177") (pinfunction "F27_P$177") (pintype "bidirectional"))
    )
    (net (code "2004") (name "ZZ.15.074") (class "Default")
      (node (ref "U$9") (pin "P$146") (pinfunction "E26_P$146") (pintype "bidirectional"))
    )
    (net (code "2005") (name "ZZ.15.075") (class "Default")
      (node (ref "U$9") (pin "P$56") (pinfunction "B26_P$56") (pintype "bidirectional"))
    )
    (net (code "2006") (name "ZZ.15.076") (class "Default")
      (node (ref "U$9") (pin "P$86") (pinfunction "C26_P$86") (pintype "bidirectional"))
    )
    (net (code "2007") (name "ZZ.15.077") (class "Default")
      (node (ref "U$9") (pin "P$116") (pinfunction "D26_P$116") (pintype "bidirectional"))
    )
    (net (code "2008") (name "ZZ.15.078") (class "Default")
      (node (ref "U$9") (pin "P$148") (pinfunction "E28_P$148") (pintype "bidirectional"))
    )
    (net (code "2009") (name "ZZ.15.079") (class "Default")
      (node (ref "U$9") (pin "P$175") (pinfunction "F25_P$175") (pintype "bidirectional"))
    )
    (net (code "2010") (name "ZZ.15.080") (class "Default")
      (node (ref "U$11") (pin "P$54") (pinfunction "B24_P$54") (pintype "bidirectional"))
    )
    (net (code "2011") (name "ZZ.15.081") (class "Default")
      (node (ref "U$11") (pin "P$84") (pinfunction "C24_P$84") (pintype "bidirectional"))
    )
    (net (code "2012") (name "ZZ.15.082") (class "Default")
      (node (ref "U$11") (pin "P$114") (pinfunction "D24_P$114") (pintype "bidirectional"))
    )
    (net (code "2013") (name "ZZ.15.083") (class "Default")
      (node (ref "U$11") (pin "P$147") (pinfunction "E27_P$147") (pintype "bidirectional"))
    )
    (net (code "2014") (name "ZZ.15.084") (class "Default")
      (node (ref "U$11") (pin "P$176") (pinfunction "F26_P$176") (pintype "bidirectional"))
    )
    (net (code "2015") (name "ZZ.15.085") (class "Default")
      (node (ref "U$11") (pin "P$174") (pinfunction "F24_P$174") (pintype "bidirectional"))
    )
    (net (code "2016") (name "ZZ.15.086") (class "Default")
      (node (ref "U$11") (pin "P$55") (pinfunction "B25_P$55") (pintype "bidirectional"))
    )
    (net (code "2017") (name "ZZ.15.087") (class "Default")
      (node (ref "U$11") (pin "P$85") (pinfunction "C25_P$85") (pintype "bidirectional"))
    )
    (net (code "2018") (name "ZZ.15.088") (class "Default")
      (node (ref "U$11") (pin "P$115") (pinfunction "D25_P$115") (pintype "bidirectional"))
    )
    (net (code "2019") (name "ZZ.15.089") (class "Default")
      (node (ref "U$11") (pin "P$177") (pinfunction "F27_P$177") (pintype "bidirectional"))
    )
    (net (code "2020") (name "ZZ.15.090") (class "Default")
      (node (ref "U$11") (pin "P$146") (pinfunction "E26_P$146") (pintype "bidirectional"))
    )
    (net (code "2021") (name "ZZ.15.091") (class "Default")
      (node (ref "U$11") (pin "P$56") (pinfunction "B26_P$56") (pintype "bidirectional"))
    )
    (net (code "2022") (name "ZZ.15.092") (class "Default")
      (node (ref "U$11") (pin "P$86") (pinfunction "C26_P$86") (pintype "bidirectional"))
    )
    (net (code "2023") (name "ZZ.15.093") (class "Default")
      (node (ref "U$11") (pin "P$116") (pinfunction "D26_P$116") (pintype "bidirectional"))
    )
    (net (code "2024") (name "ZZ.15.094") (class "Default")
      (node (ref "U$11") (pin "P$148") (pinfunction "E28_P$148") (pintype "bidirectional"))
    )
    (net (code "2025") (name "ZZ.15.095") (class "Default")
      (node (ref "U$11") (pin "P$175") (pinfunction "F25_P$175") (pintype "bidirectional"))
    )
    (net (code "2026") (name "ZZ.15.096") (class "Default")
      (node (ref "U$13") (pin "P$54") (pinfunction "B24_P$54") (pintype "bidirectional"))
    )
    (net (code "2027") (name "ZZ.15.097") (class "Default")
      (node (ref "U$13") (pin "P$84") (pinfunction "C24_P$84") (pintype "bidirectional"))
    )
    (net (code "2028") (name "ZZ.15.098") (class "Default")
      (node (ref "U$13") (pin "P$114") (pinfunction "D24_P$114") (pintype "bidirectional"))
    )
    (net (code "2029") (name "ZZ.15.099") (class "Default")
      (node (ref "U$13") (pin "P$147") (pinfunction "E27_P$147") (pintype "bidirectional"))
    )
    (net (code "2030") (name "ZZ.15.100") (class "Default")
      (node (ref "U$13") (pin "P$176") (pinfunction "F26_P$176") (pintype "bidirectional"))
    )
    (net (code "2031") (name "ZZ.15.101") (class "Default")
      (node (ref "U$13") (pin "P$174") (pinfunction "F24_P$174") (pintype "bidirectional"))
    )
    (net (code "2032") (name "ZZ.15.102") (class "Default")
      (node (ref "U$13") (pin "P$55") (pinfunction "B25_P$55") (pintype "bidirectional"))
    )
    (net (code "2033") (name "ZZ.15.103") (class "Default")
      (node (ref "U$13") (pin "P$85") (pinfunction "C25_P$85") (pintype "bidirectional"))
    )
    (net (code "2034") (name "ZZ.15.104") (class "Default")
      (node (ref "U$13") (pin "P$115") (pinfunction "D25_P$115") (pintype "bidirectional"))
    )
    (net (code "2035") (name "ZZ.15.105") (class "Default")
      (node (ref "U$13") (pin "P$177") (pinfunction "F27_P$177") (pintype "bidirectional"))
    )
    (net (code "2036") (name "ZZ.15.106") (class "Default")
      (node (ref "U$13") (pin "P$146") (pinfunction "E26_P$146") (pintype "bidirectional"))
    )
    (net (code "2037") (name "ZZ.15.107") (class "Default")
      (node (ref "U$13") (pin "P$56") (pinfunction "B26_P$56") (pintype "bidirectional"))
    )
    (net (code "2038") (name "ZZ.15.108") (class "Default")
      (node (ref "U$13") (pin "P$86") (pinfunction "C26_P$86") (pintype "bidirectional"))
    )
    (net (code "2039") (name "ZZ.15.109") (class "Default")
      (node (ref "U$13") (pin "P$116") (pinfunction "D26_P$116") (pintype "bidirectional"))
    )
    (net (code "2040") (name "ZZ.15.110") (class "Default")
      (node (ref "U$13") (pin "P$148") (pinfunction "E28_P$148") (pintype "bidirectional"))
    )
    (net (code "2041") (name "ZZ.15.111") (class "Default")
      (node (ref "U$13") (pin "P$175") (pinfunction "F25_P$175") (pintype "bidirectional"))
    )
    (net (code "2042") (name "ZZ.15.112") (class "Default")
      (node (ref "U$15") (pin "P$54") (pinfunction "B24_P$54") (pintype "bidirectional"))
    )
    (net (code "2043") (name "ZZ.15.113") (class "Default")
      (node (ref "U$15") (pin "P$84") (pinfunction "C24_P$84") (pintype "bidirectional"))
    )
    (net (code "2044") (name "ZZ.15.114") (class "Default")
      (node (ref "U$15") (pin "P$114") (pinfunction "D24_P$114") (pintype "bidirectional"))
    )
    (net (code "2045") (name "ZZ.15.115") (class "Default")
      (node (ref "U$15") (pin "P$147") (pinfunction "E27_P$147") (pintype "bidirectional"))
    )
    (net (code "2046") (name "ZZ.15.116") (class "Default")
      (node (ref "U$15") (pin "P$176") (pinfunction "F26_P$176") (pintype "bidirectional"))
    )
    (net (code "2047") (name "ZZ.15.117") (class "Default")
      (node (ref "U$15") (pin "P$174") (pinfunction "F24_P$174") (pintype "bidirectional"))
    )
    (net (code "2048") (name "ZZ.15.118") (class "Default")
      (node (ref "U$15") (pin "P$55") (pinfunction "B25_P$55") (pintype "bidirectional"))
    )
    (net (code "2049") (name "ZZ.15.119") (class "Default")
      (node (ref "U$15") (pin "P$85") (pinfunction "C25_P$85") (pintype "bidirectional"))
    )
    (net (code "2050") (name "ZZ.15.120") (class "Default")
      (node (ref "U$15") (pin "P$115") (pinfunction "D25_P$115") (pintype "bidirectional"))
    )
    (net (code "2051") (name "ZZ.15.121") (class "Default")
      (node (ref "U$15") (pin "P$177") (pinfunction "F27_P$177") (pintype "bidirectional"))
    )
    (net (code "2052") (name "ZZ.15.122") (class "Default")
      (node (ref "U$15") (pin "P$146") (pinfunction "E26_P$146") (pintype "bidirectional"))
    )
    (net (code "2053") (name "ZZ.15.123") (class "Default")
      (node (ref "U$15") (pin "P$56") (pinfunction "B26_P$56") (pintype "bidirectional"))
    )
    (net (code "2054") (name "ZZ.15.124") (class "Default")
      (node (ref "U$15") (pin "P$86") (pinfunction "C26_P$86") (pintype "bidirectional"))
    )
    (net (code "2055") (name "ZZ.15.125") (class "Default")
      (node (ref "U$15") (pin "P$116") (pinfunction "D26_P$116") (pintype "bidirectional"))
    )
    (net (code "2056") (name "ZZ.15.126") (class "Default")
      (node (ref "U$15") (pin "P$148") (pinfunction "E28_P$148") (pintype "bidirectional"))
    )
    (net (code "2057") (name "ZZ.15.127") (class "Default")
      (node (ref "U$15") (pin "P$175") (pinfunction "F25_P$175") (pintype "bidirectional"))
    )
    (net (code "2058") (name "unconnected-(U$2-A30-PadP$30)") (class "Default")
      (node (ref "U$2") (pin "P$30") (pinfunction "A30_P$30") (pintype "bidirectional"))
    )
    (net (code "2059") (name "unconnected-(U$4-A30-PadP$30)") (class "Default")
      (node (ref "U$4") (pin "P$30") (pinfunction "A30_P$30") (pintype "bidirectional"))
    )
    (net (code "2060") (name "unconnected-(U$6-A30-PadP$30)") (class "Default")
      (node (ref "U$6") (pin "P$30") (pinfunction "A30_P$30") (pintype "bidirectional"))
    )
    (net (code "2061") (name "unconnected-(U$8-A30-PadP$30)") (class "Default")
      (node (ref "U$8") (pin "P$30") (pinfunction "A30_P$30") (pintype "bidirectional"))
    )
    (net (code "2062") (name "unconnected-(U$10-A30-PadP$30)") (class "Default")
      (node (ref "U$10") (pin "P$30") (pinfunction "A30_P$30") (pintype "bidirectional"))
    )
    (net (code "2063") (name "unconnected-(U$12-A30-PadP$30)") (class "Default")
      (node (ref "U$12") (pin "P$30") (pinfunction "A30_P$30") (pintype "bidirectional"))
    )
    (net (code "2064") (name "unconnected-(U$14-A30-PadP$30)") (class "Default")
      (node (ref "U$14") (pin "P$30") (pinfunction "A30_P$30") (pintype "bidirectional"))
    )
    (net (code "2065") (name "unconnected-(U$16-A30-PadP$30)") (class "Default")
      (node (ref "U$16") (pin "P$30") (pinfunction "A30_P$30") (pintype "bidirectional"))
    )
  )
)
